# Lafferty1ab.net
KiCad netlist of a schematic drawn in EAGLE
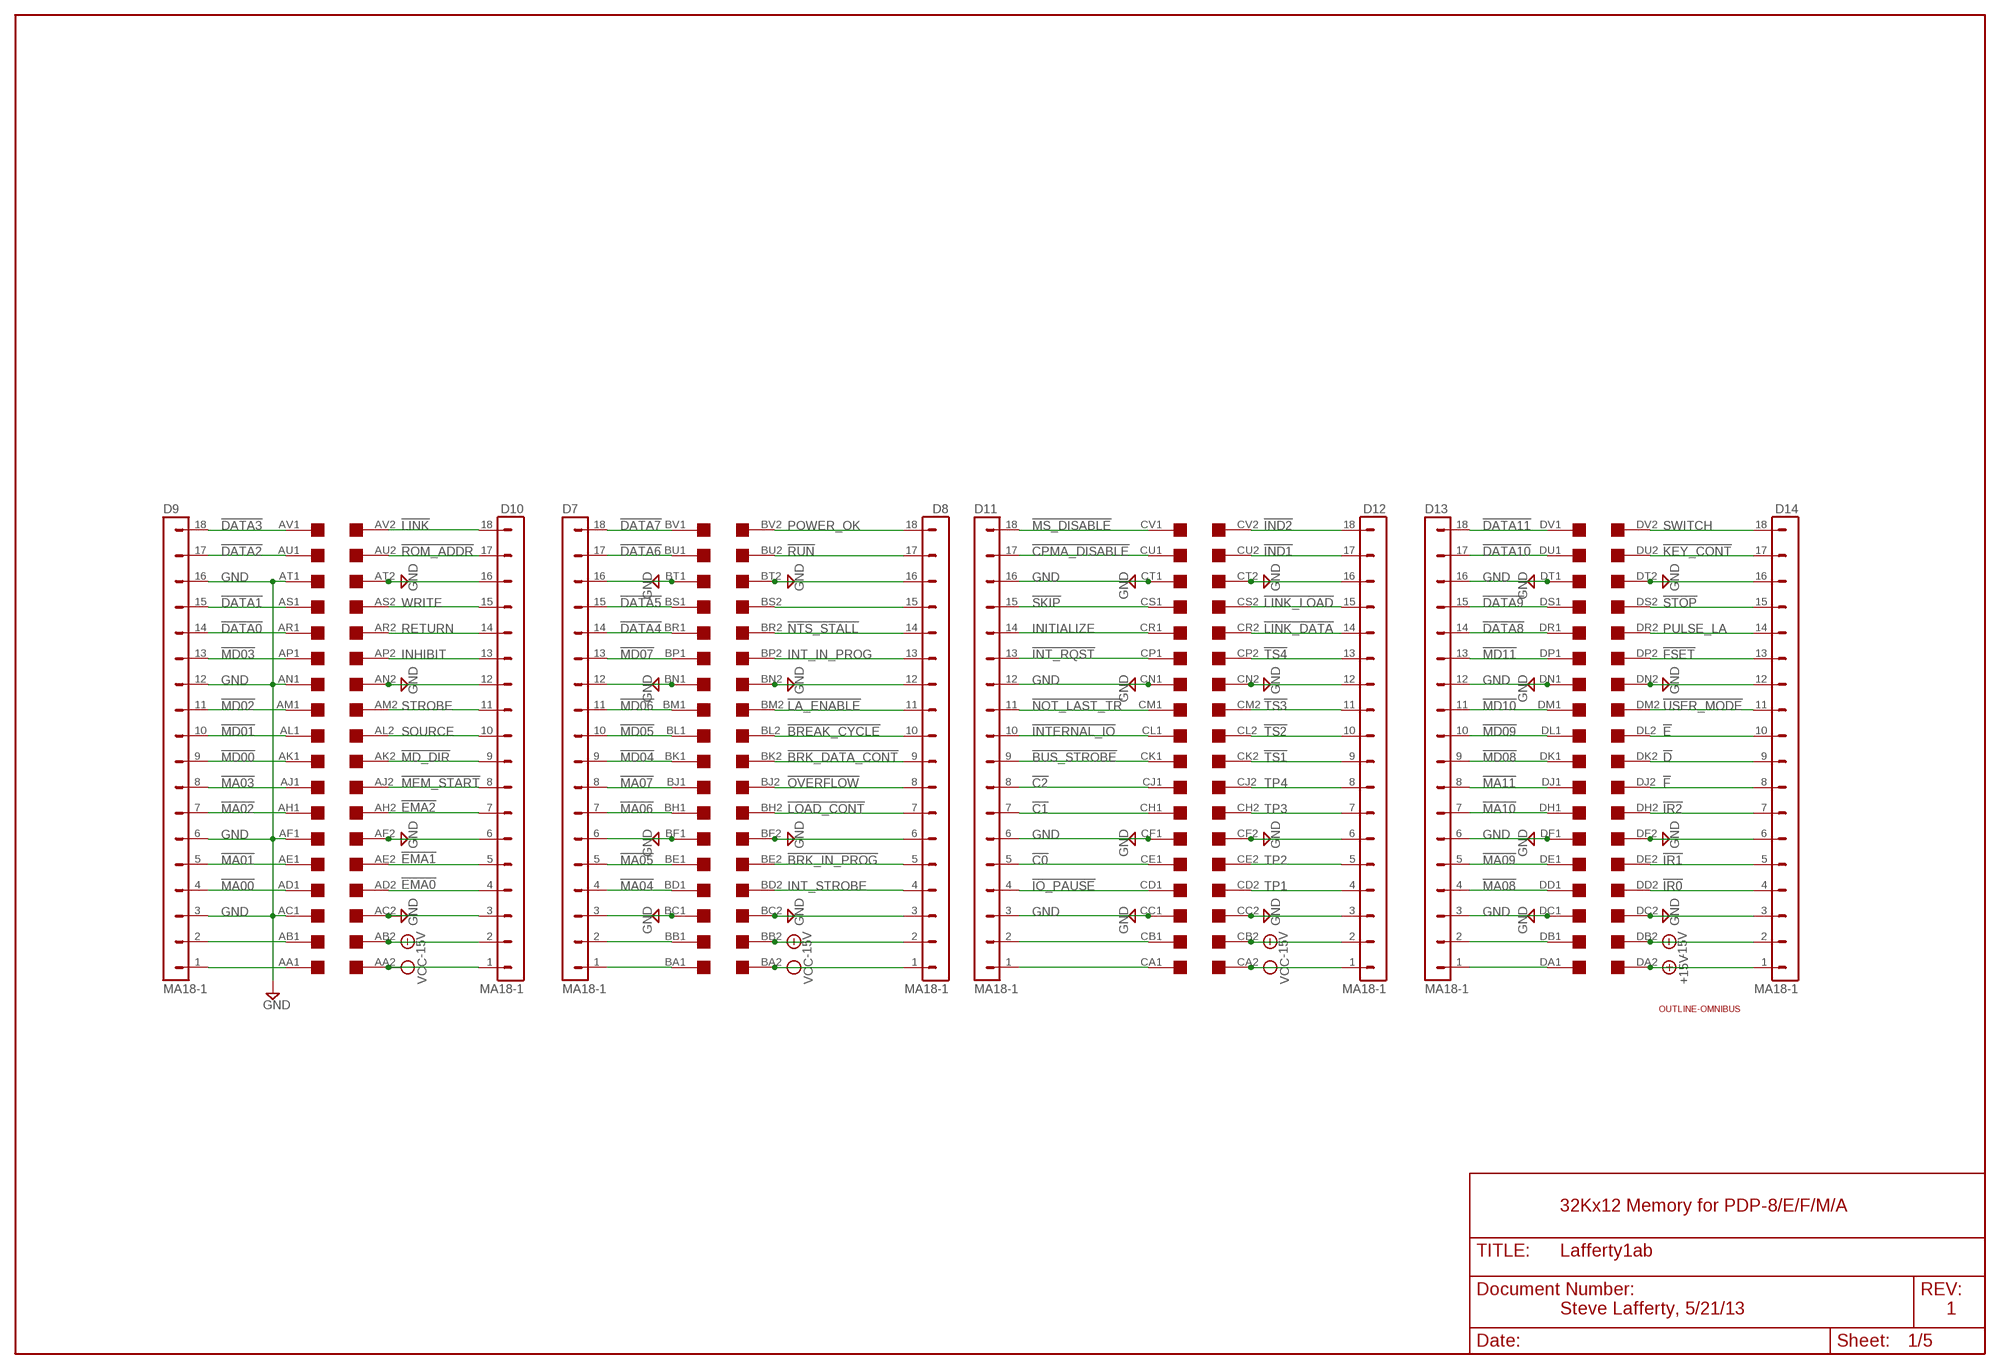
[diagram p0: schematic, sheet 1]
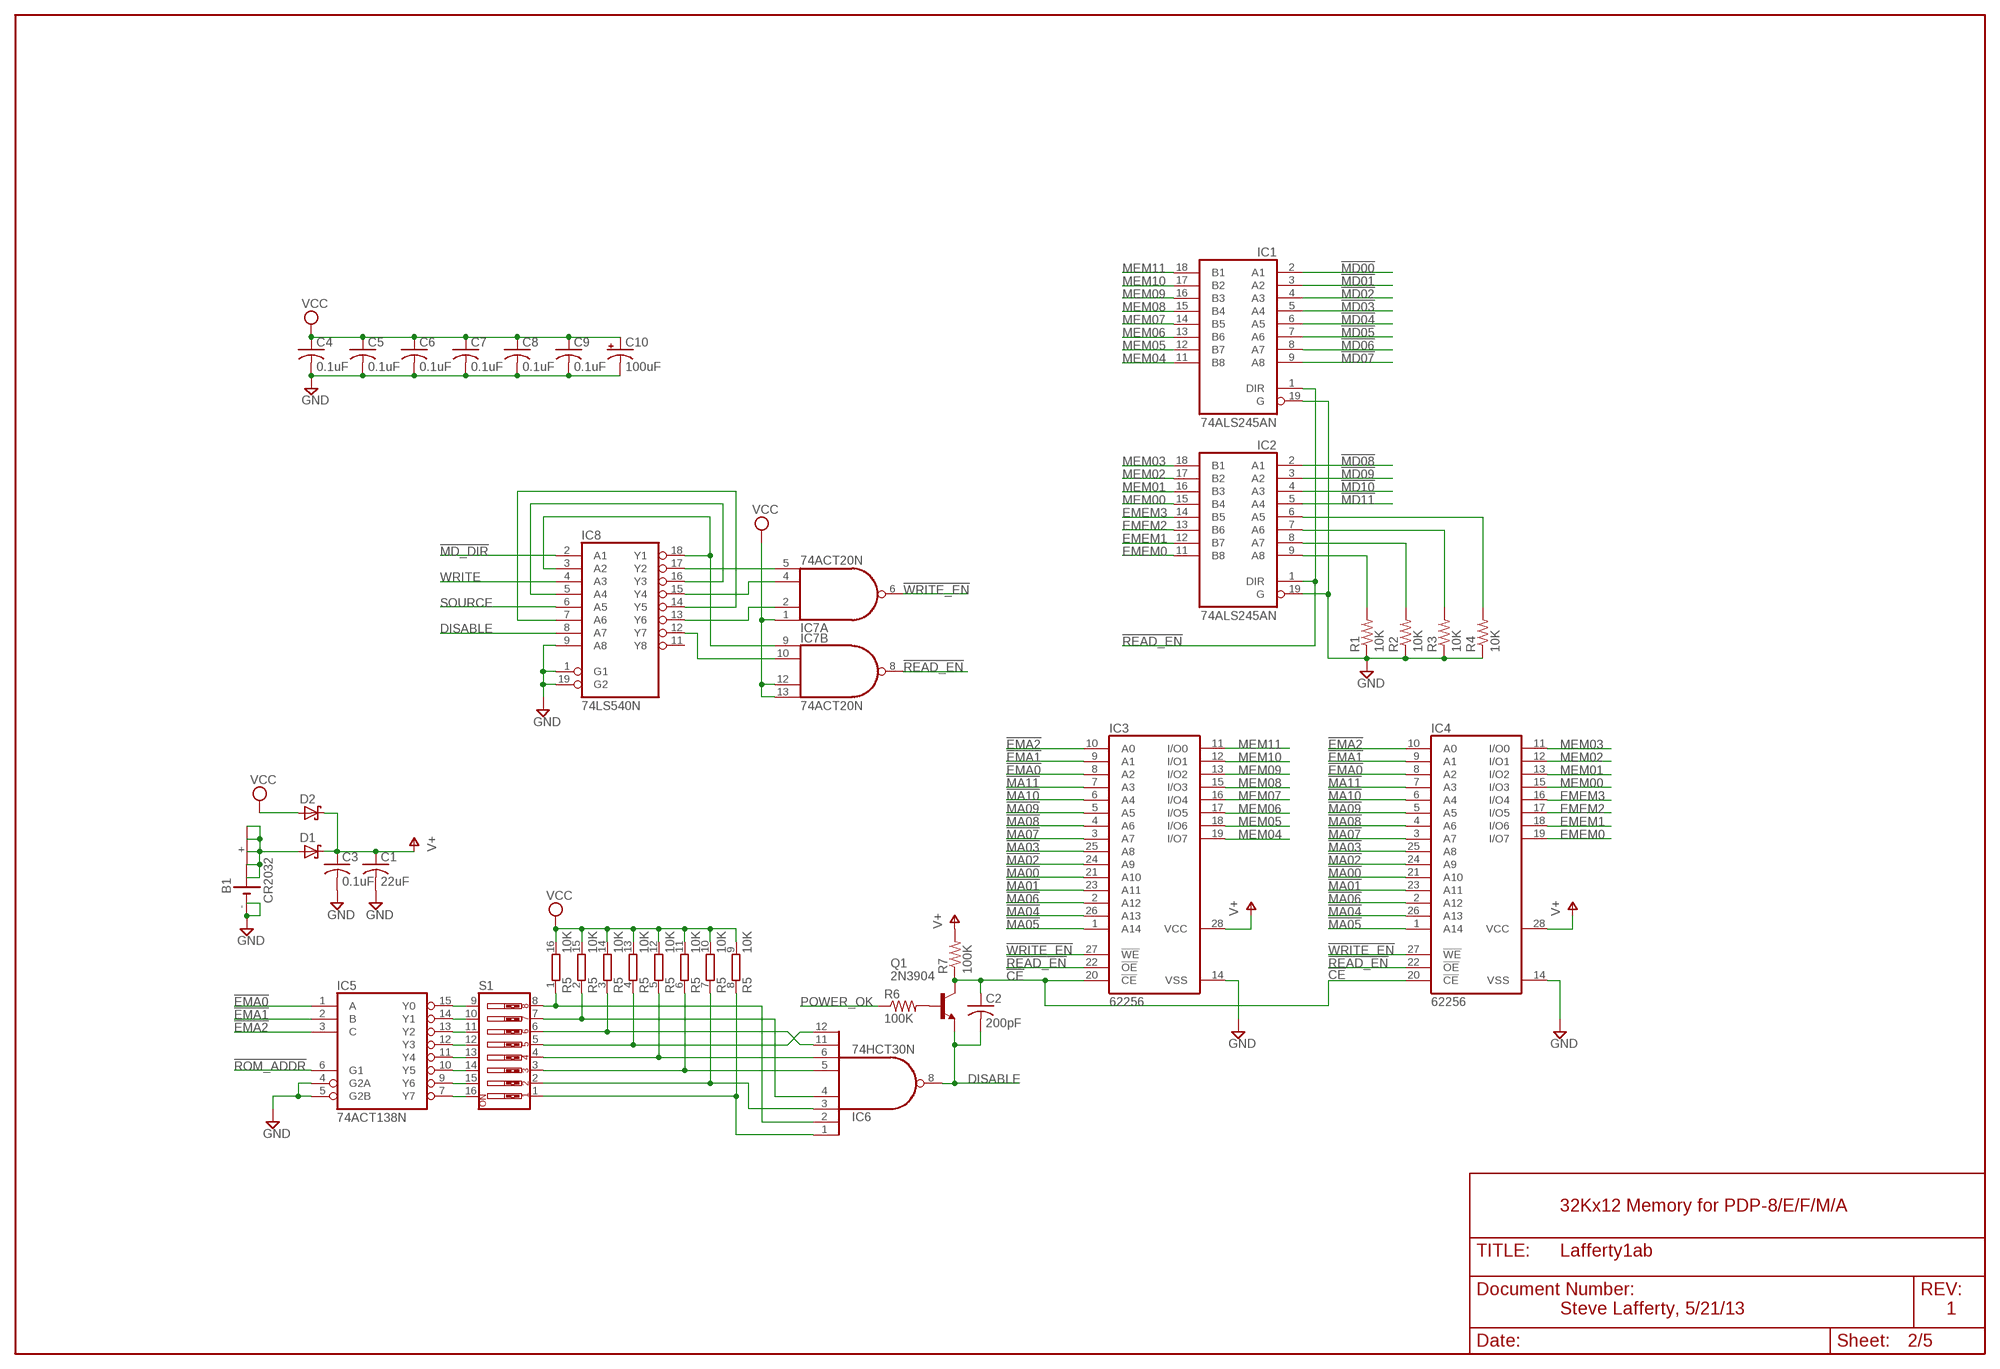
[diagram p1: schematic, sheet 2]
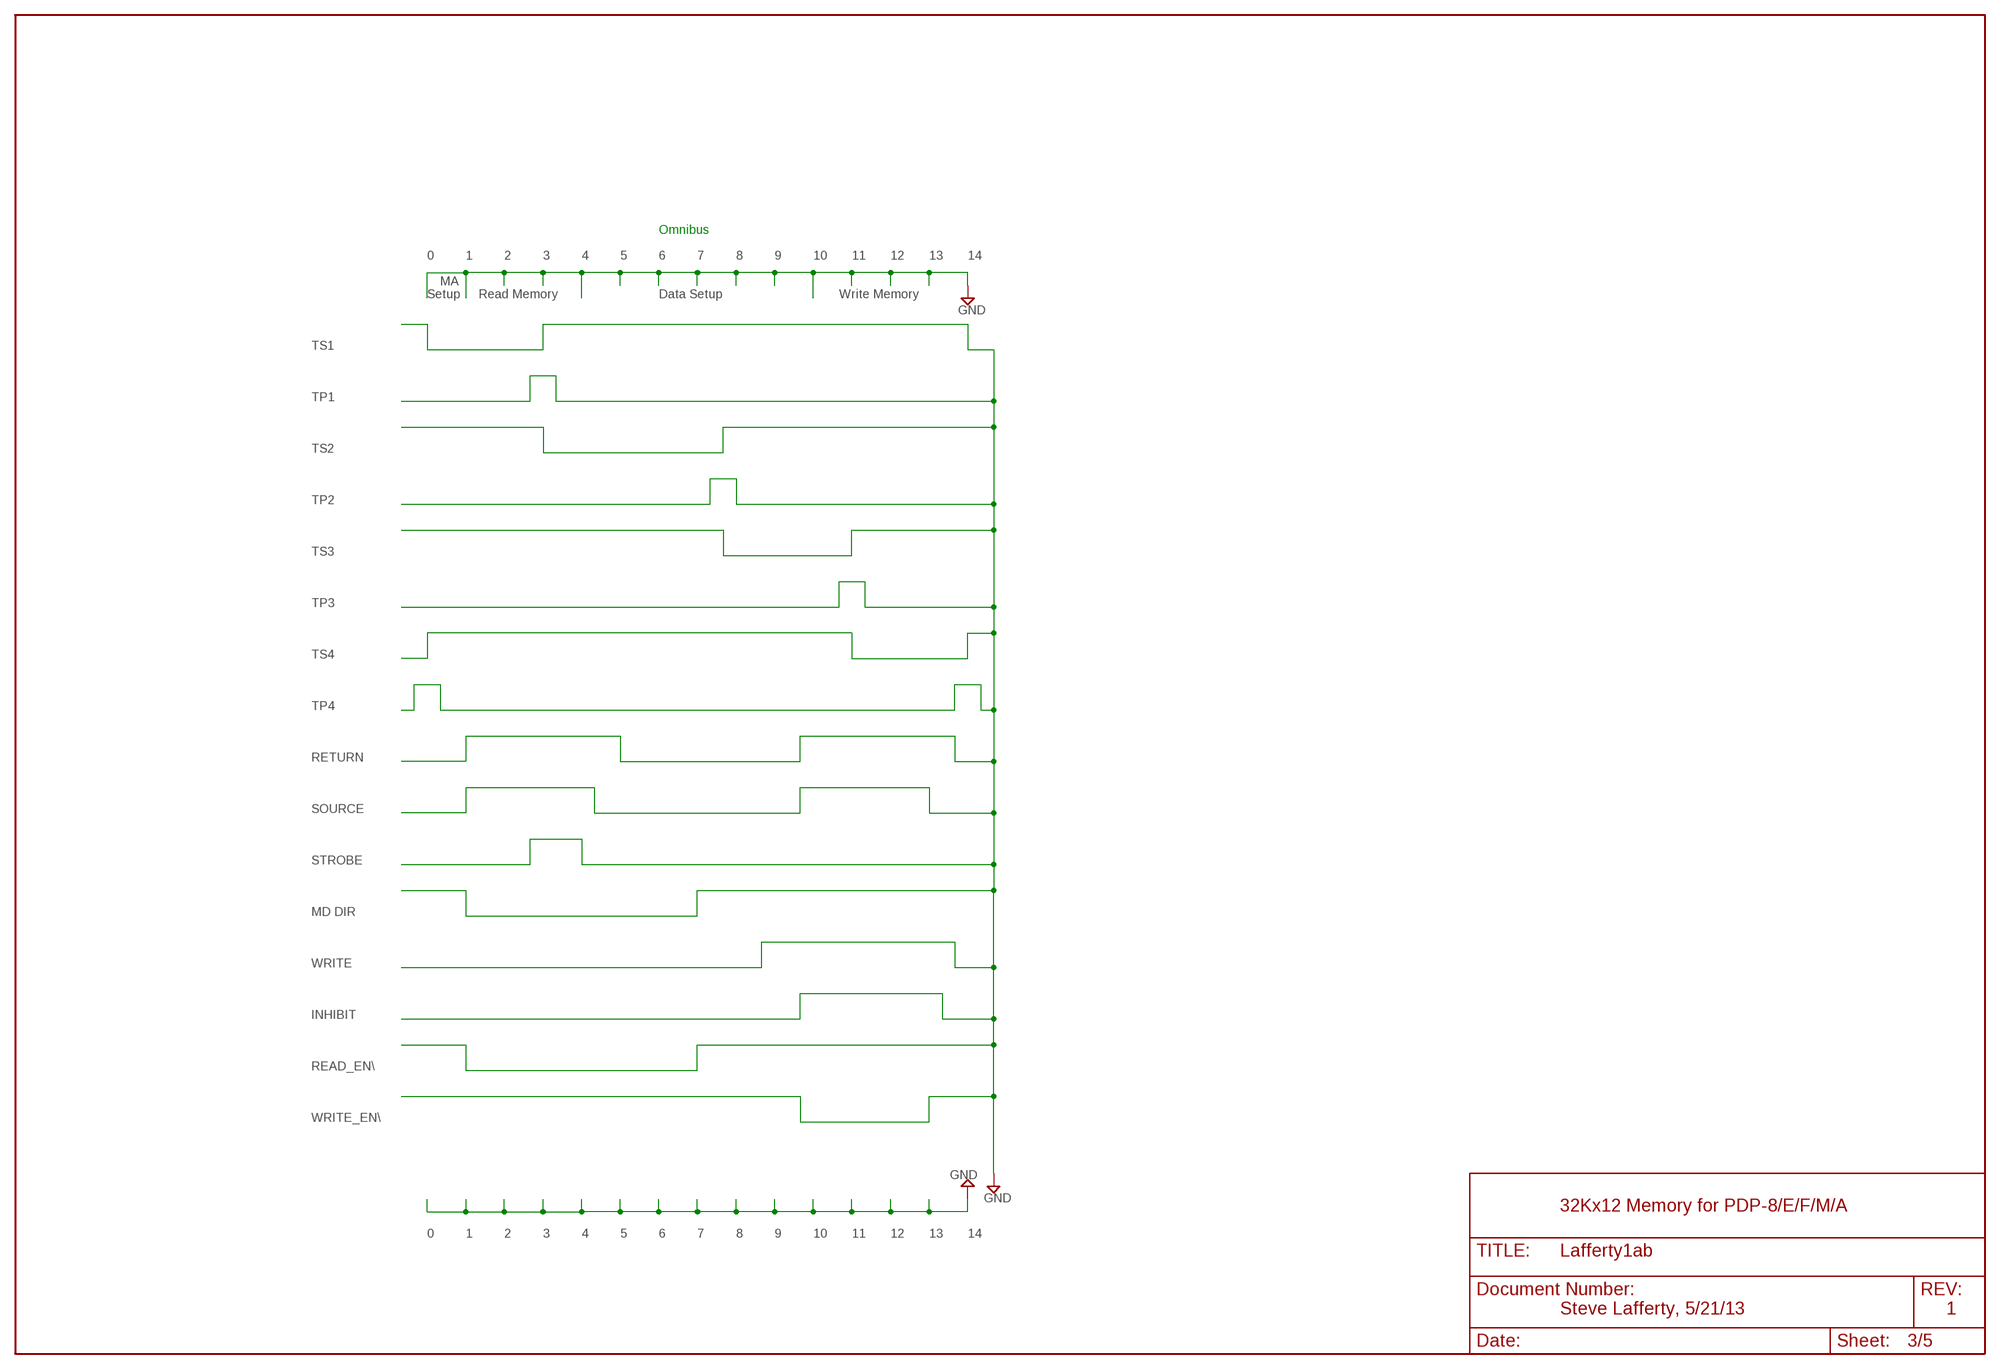
[diagram p2: schematic, sheet 3]
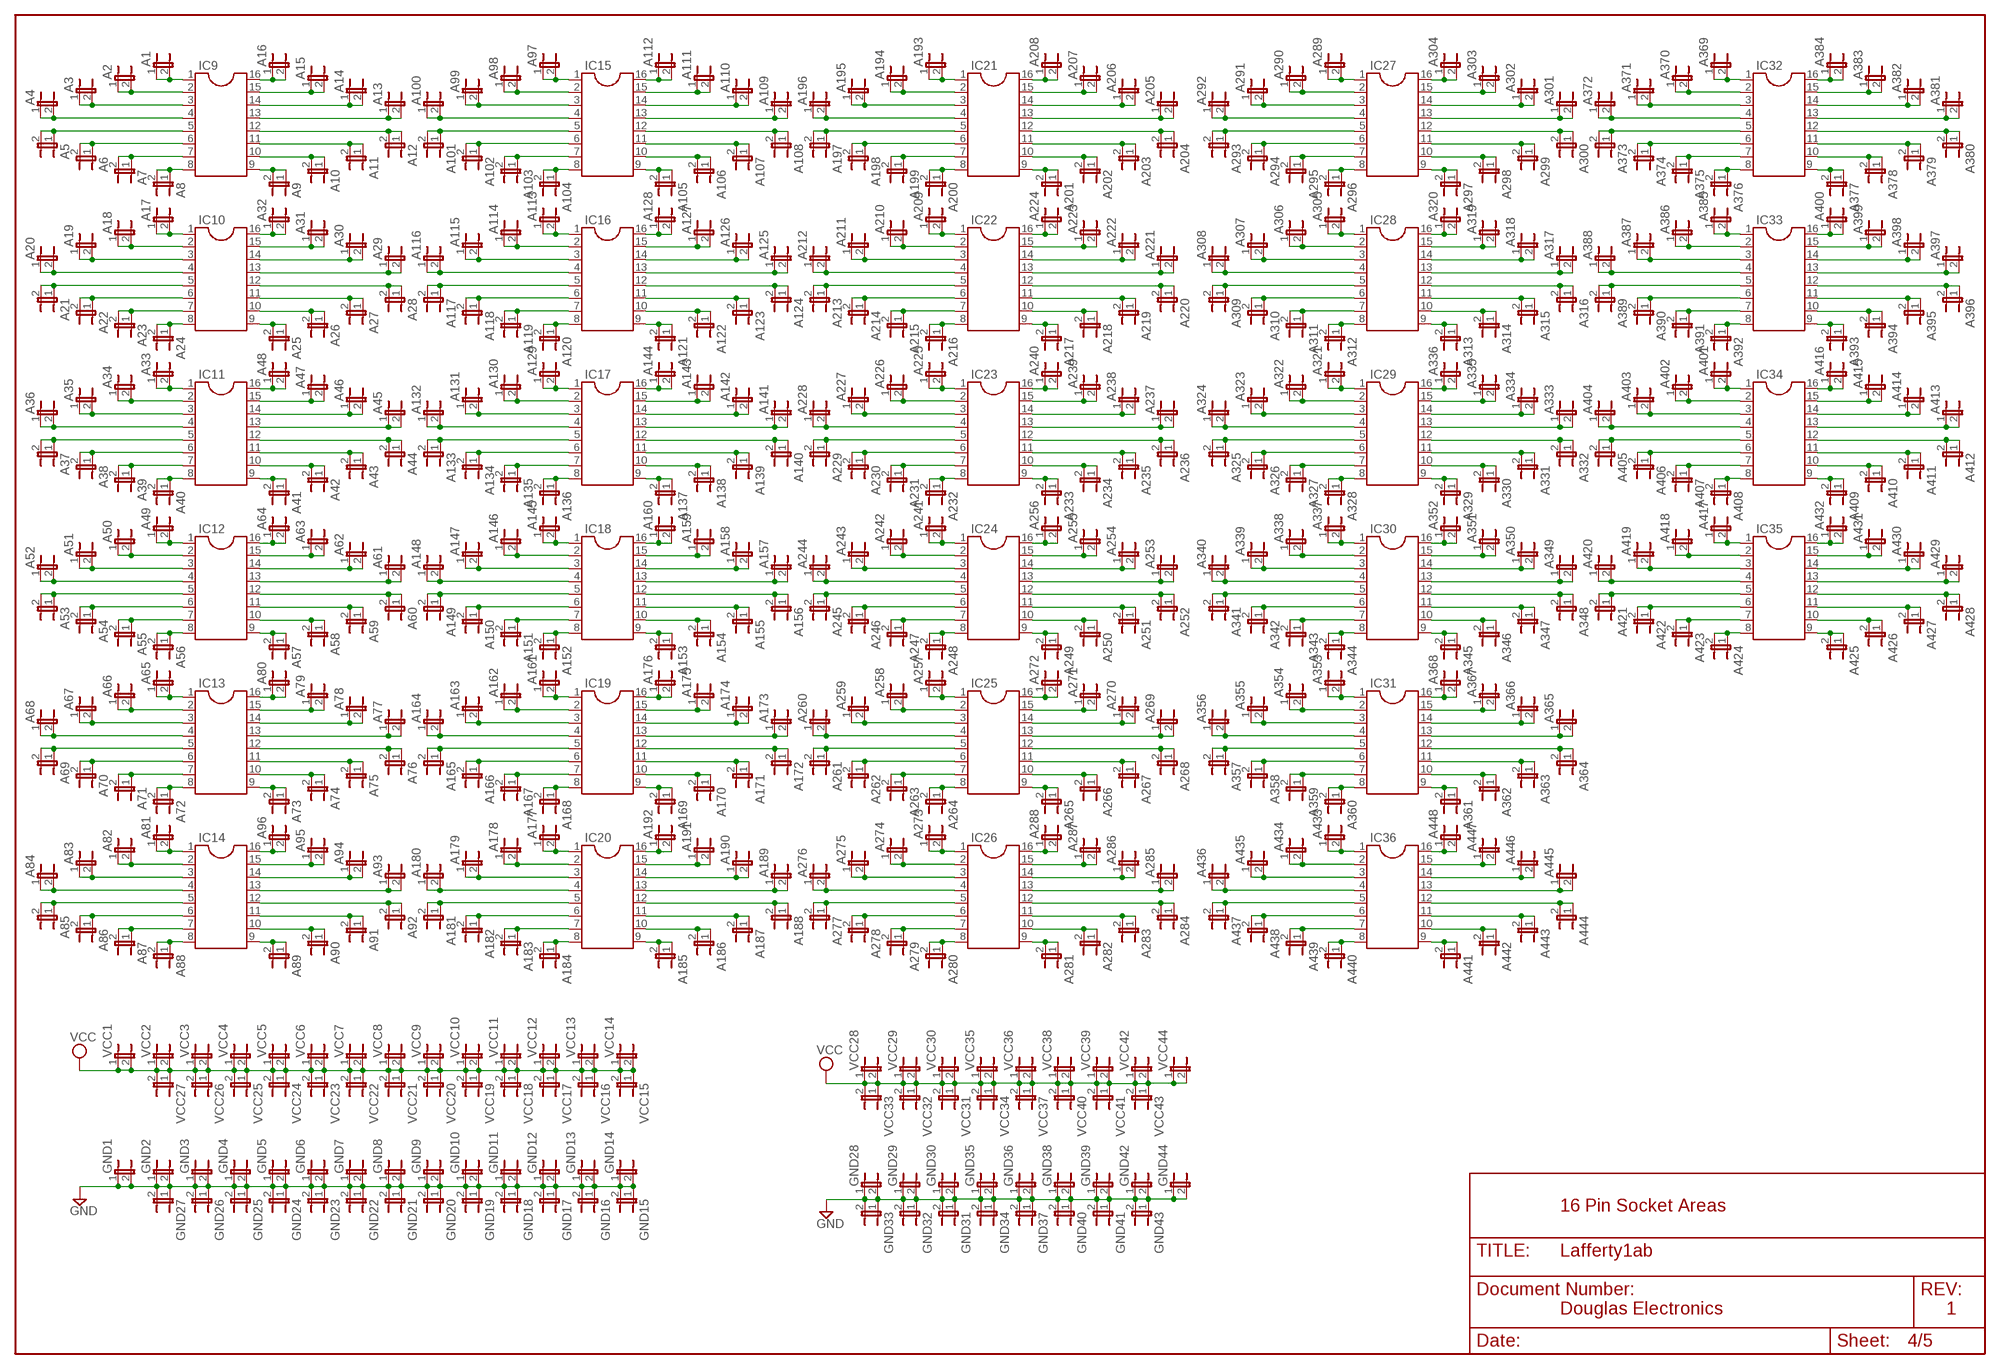
[diagram p3: schematic, sheet 4]
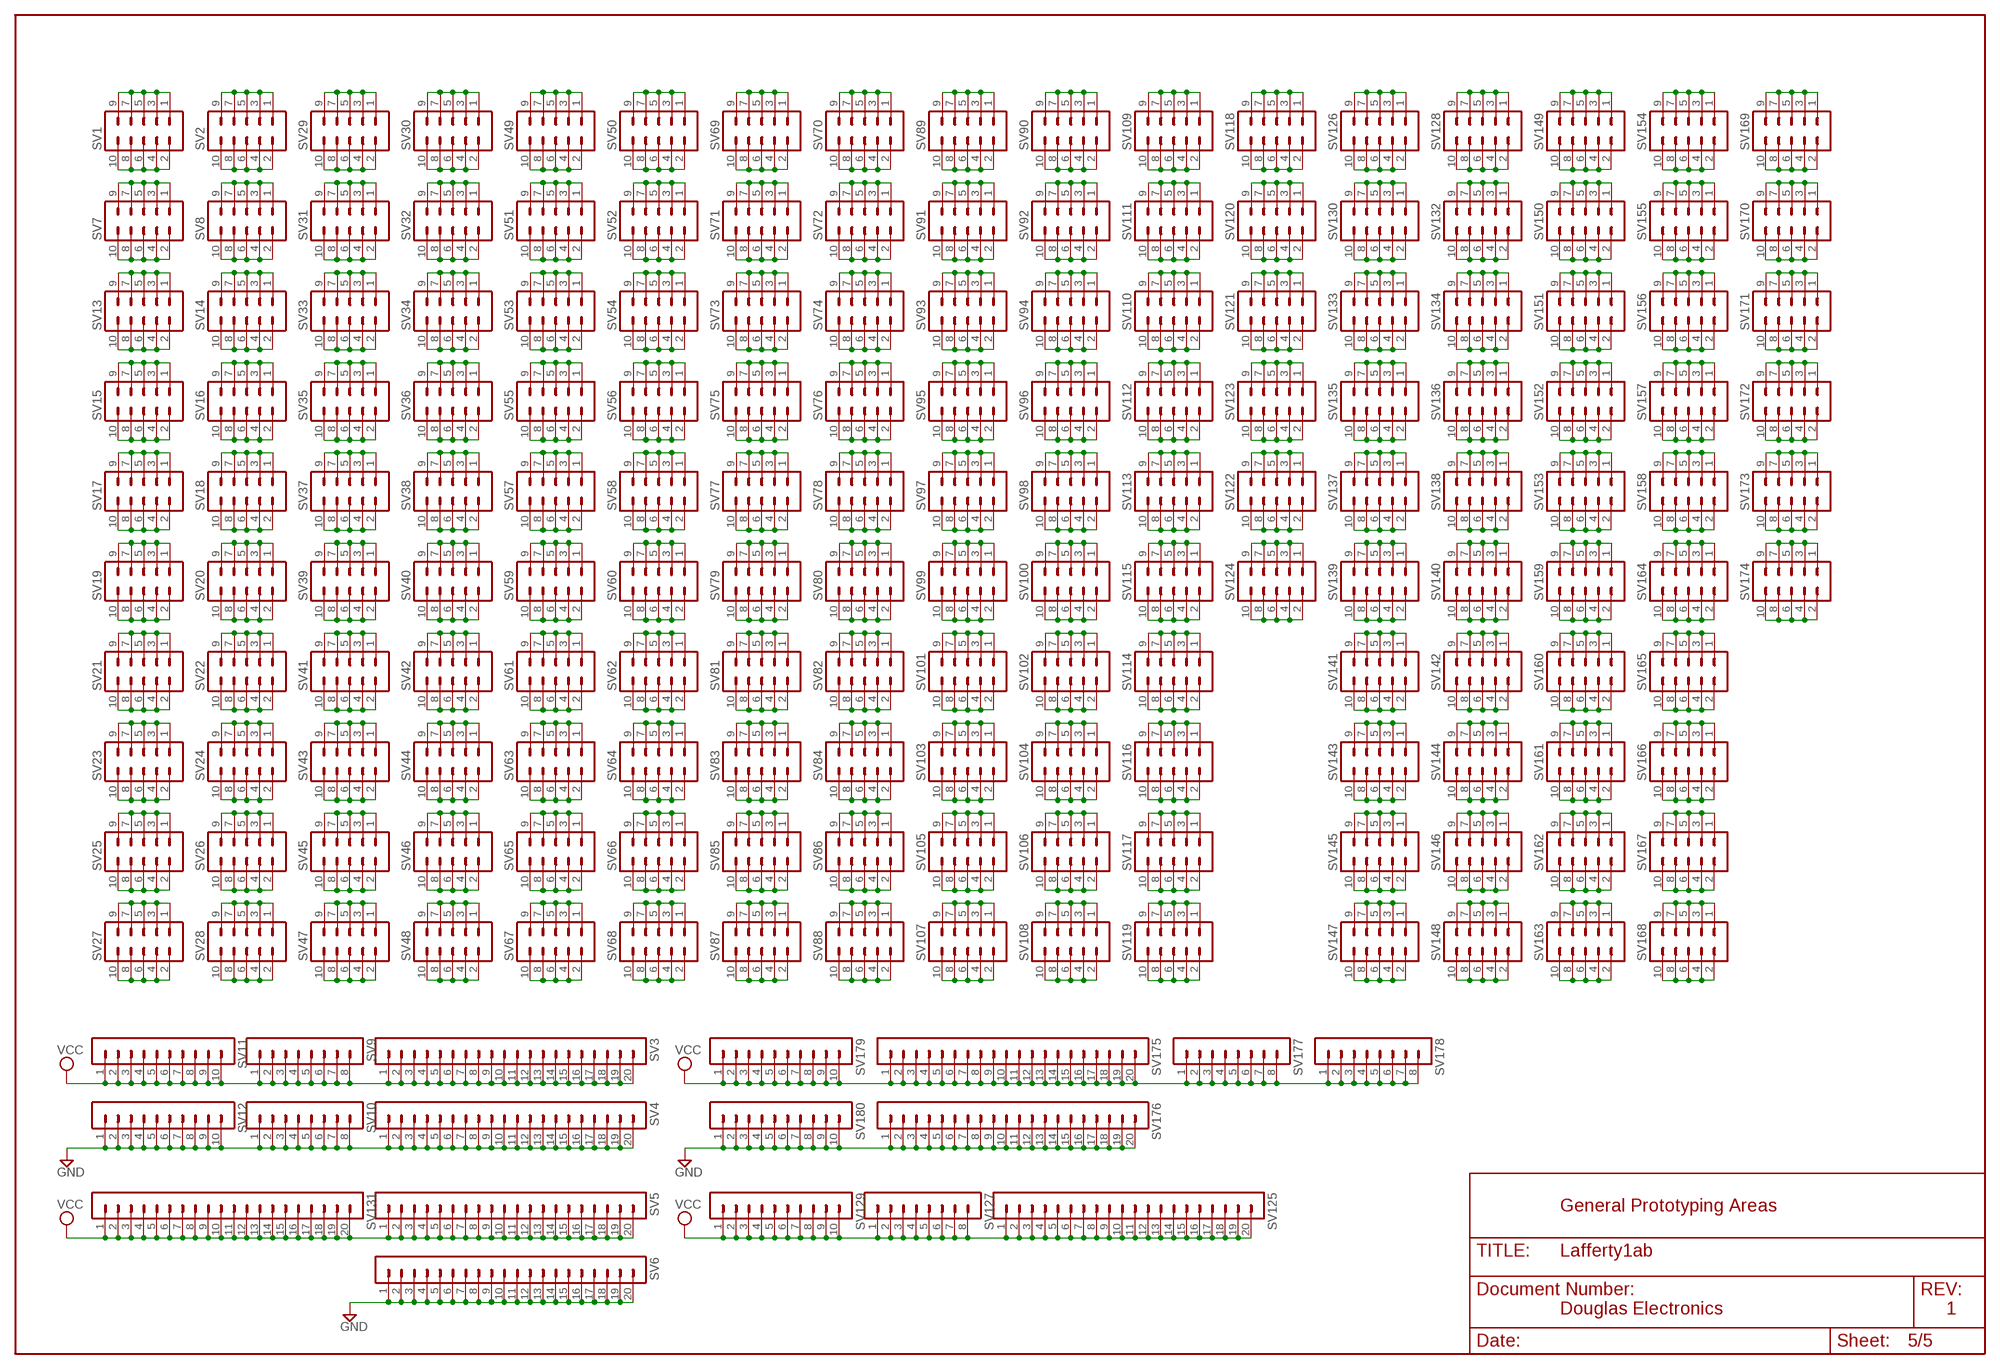
[diagram p4: schematic, sheet 5]

(export (version "E")
  (design (tool "Eeschema 10.0.6"))
  (components
    (comp (ref "D7")
      (value "MA18-1")
      (footprint "eagle-import:MA18-1")
      (libsource (lib "eagle-import") (part "MA18-1"))
    )
    (comp (ref "D8")
      (value "MA18-1")
      (footprint "eagle-import:MA18-1")
      (libsource (lib "eagle-import") (part "MA18-1"))
    )
    (comp (ref "D9")
      (value "MA18-1")
      (footprint "eagle-import:MA18-1")
      (libsource (lib "eagle-import") (part "MA18-1"))
    )
    (comp (ref "D10")
      (value "MA18-1")
      (footprint "eagle-import:MA18-1")
      (libsource (lib "eagle-import") (part "MA18-1"))
    )
    (comp (ref "D11")
      (value "MA18-1")
      (footprint "eagle-import:MA18-1")
      (libsource (lib "eagle-import") (part "MA18-1"))
    )
    (comp (ref "D12")
      (value "MA18-1")
      (footprint "eagle-import:MA18-1")
      (libsource (lib "eagle-import") (part "MA18-1"))
    )
    (comp (ref "D13")
      (value "MA18-1")
      (footprint "eagle-import:MA18-1")
      (libsource (lib "eagle-import") (part "MA18-1"))
    )
    (comp (ref "D14")
      (value "MA18-1")
      (footprint "eagle-import:MA18-1")
      (libsource (lib "eagle-import") (part "MA18-1"))
    )
    (comp (ref "U$1")
      (value "OUTLINE-OMNIBUS")
      (footprint "eagle-import:OMNIBUS")
      (libsource (lib "eagle-import") (part "OUTLINE-OMNIBUS"))
    )
    (comp (ref "U$2")
      (value "QUAD")
      (footprint "eagle-import:EDGE-CON8")
      (libsource (lib "eagle-import") (part "QUAD"))
    )
    (comp (ref "SV1")
      (value "MA05-2")
      (footprint "eagle-import:MA05-2")
      (libsource (lib "eagle-import") (part "MA05-2"))
    )
    (comp (ref "SV2")
      (value "MA05-2")
      (footprint "eagle-import:MA05-2")
      (libsource (lib "eagle-import") (part "MA05-2"))
    )
    (comp (ref "SV3")
      (value "MA20-1")
      (footprint "eagle-import:MA20-1")
      (libsource (lib "eagle-import") (part "MA20-1"))
    )
    (comp (ref "SV4")
      (value "MA20-1")
      (footprint "eagle-import:MA20-1")
      (libsource (lib "eagle-import") (part "MA20-1"))
    )
    (comp (ref "SV5")
      (value "MA20-1")
      (footprint "eagle-import:MA20-1")
      (libsource (lib "eagle-import") (part "MA20-1"))
    )
    (comp (ref "SV6")
      (value "MA20-1")
      (footprint "eagle-import:MA20-1")
      (libsource (lib "eagle-import") (part "MA20-1"))
    )
    (comp (ref "SV7")
      (value "MA05-2")
      (footprint "eagle-import:MA05-2")
      (libsource (lib "eagle-import") (part "MA05-2"))
    )
    (comp (ref "SV8")
      (value "MA05-2")
      (footprint "eagle-import:MA05-2")
      (libsource (lib "eagle-import") (part "MA05-2"))
    )
    (comp (ref "SV9")
      (value "MA08-1")
      (footprint "eagle-import:MA08-1")
      (libsource (lib "eagle-import") (part "MA08-1"))
    )
    (comp (ref "SV10")
      (value "MA08-1")
      (footprint "eagle-import:MA08-1")
      (libsource (lib "eagle-import") (part "MA08-1"))
    )
    (comp (ref "SV11")
      (value "MA10-1")
      (footprint "eagle-import:MA10-1")
      (libsource (lib "eagle-import") (part "MA10-1"))
    )
    (comp (ref "SV12")
      (value "MA10-1")
      (footprint "eagle-import:MA10-1")
      (libsource (lib "eagle-import") (part "MA10-1"))
    )
    (comp (ref "SV13")
      (value "MA05-2")
      (footprint "eagle-import:MA05-2")
      (libsource (lib "eagle-import") (part "MA05-2"))
    )
    (comp (ref "SV14")
      (value "MA05-2")
      (footprint "eagle-import:MA05-2")
      (libsource (lib "eagle-import") (part "MA05-2"))
    )
    (comp (ref "SV15")
      (value "MA05-2")
      (footprint "eagle-import:MA05-2")
      (libsource (lib "eagle-import") (part "MA05-2"))
    )
    (comp (ref "SV16")
      (value "MA05-2")
      (footprint "eagle-import:MA05-2")
      (libsource (lib "eagle-import") (part "MA05-2"))
    )
    (comp (ref "SV17")
      (value "MA05-2")
      (footprint "eagle-import:MA05-2")
      (libsource (lib "eagle-import") (part "MA05-2"))
    )
    (comp (ref "SV18")
      (value "MA05-2")
      (footprint "eagle-import:MA05-2")
      (libsource (lib "eagle-import") (part "MA05-2"))
    )
    (comp (ref "SV19")
      (value "MA05-2")
      (footprint "eagle-import:MA05-2")
      (libsource (lib "eagle-import") (part "MA05-2"))
    )
    (comp (ref "SV20")
      (value "MA05-2")
      (footprint "eagle-import:MA05-2")
      (libsource (lib "eagle-import") (part "MA05-2"))
    )
    (comp (ref "SV21")
      (value "MA05-2")
      (footprint "eagle-import:MA05-2")
      (libsource (lib "eagle-import") (part "MA05-2"))
    )
    (comp (ref "SV22")
      (value "MA05-2")
      (footprint "eagle-import:MA05-2")
      (libsource (lib "eagle-import") (part "MA05-2"))
    )
    (comp (ref "SV23")
      (value "MA05-2")
      (footprint "eagle-import:MA05-2")
      (libsource (lib "eagle-import") (part "MA05-2"))
    )
    (comp (ref "SV24")
      (value "MA05-2")
      (footprint "eagle-import:MA05-2")
      (libsource (lib "eagle-import") (part "MA05-2"))
    )
    (comp (ref "SV25")
      (value "MA05-2")
      (footprint "eagle-import:MA05-2")
      (libsource (lib "eagle-import") (part "MA05-2"))
    )
    (comp (ref "SV26")
      (value "MA05-2")
      (footprint "eagle-import:MA05-2")
      (libsource (lib "eagle-import") (part "MA05-2"))
    )
    (comp (ref "SV27")
      (value "MA05-2")
      (footprint "eagle-import:MA05-2")
      (libsource (lib "eagle-import") (part "MA05-2"))
    )
    (comp (ref "SV28")
      (value "MA05-2")
      (footprint "eagle-import:MA05-2")
      (libsource (lib "eagle-import") (part "MA05-2"))
    )
    (comp (ref "SV29")
      (value "MA05-2")
      (footprint "eagle-import:MA05-2")
      (libsource (lib "eagle-import") (part "MA05-2"))
    )
    (comp (ref "SV30")
      (value "MA05-2")
      (footprint "eagle-import:MA05-2")
      (libsource (lib "eagle-import") (part "MA05-2"))
    )
    (comp (ref "SV31")
      (value "MA05-2")
      (footprint "eagle-import:MA05-2")
      (libsource (lib "eagle-import") (part "MA05-2"))
    )
    (comp (ref "SV32")
      (value "MA05-2")
      (footprint "eagle-import:MA05-2")
      (libsource (lib "eagle-import") (part "MA05-2"))
    )
    (comp (ref "SV33")
      (value "MA05-2")
      (footprint "eagle-import:MA05-2")
      (libsource (lib "eagle-import") (part "MA05-2"))
    )
    (comp (ref "SV34")
      (value "MA05-2")
      (footprint "eagle-import:MA05-2")
      (libsource (lib "eagle-import") (part "MA05-2"))
    )
    (comp (ref "SV35")
      (value "MA05-2")
      (footprint "eagle-import:MA05-2")
      (libsource (lib "eagle-import") (part "MA05-2"))
    )
    (comp (ref "SV36")
      (value "MA05-2")
      (footprint "eagle-import:MA05-2")
      (libsource (lib "eagle-import") (part "MA05-2"))
    )
    (comp (ref "SV37")
      (value "MA05-2")
      (footprint "eagle-import:MA05-2")
      (libsource (lib "eagle-import") (part "MA05-2"))
    )
    (comp (ref "SV38")
      (value "MA05-2")
      (footprint "eagle-import:MA05-2")
      (libsource (lib "eagle-import") (part "MA05-2"))
    )
    (comp (ref "SV39")
      (value "MA05-2")
      (footprint "eagle-import:MA05-2")
      (libsource (lib "eagle-import") (part "MA05-2"))
    )
    (comp (ref "SV40")
      (value "MA05-2")
      (footprint "eagle-import:MA05-2")
      (libsource (lib "eagle-import") (part "MA05-2"))
    )
    (comp (ref "SV41")
      (value "MA05-2")
      (footprint "eagle-import:MA05-2")
      (libsource (lib "eagle-import") (part "MA05-2"))
    )
    (comp (ref "SV42")
      (value "MA05-2")
      (footprint "eagle-import:MA05-2")
      (libsource (lib "eagle-import") (part "MA05-2"))
    )
    (comp (ref "SV43")
      (value "MA05-2")
      (footprint "eagle-import:MA05-2")
      (libsource (lib "eagle-import") (part "MA05-2"))
    )
    (comp (ref "SV44")
      (value "MA05-2")
      (footprint "eagle-import:MA05-2")
      (libsource (lib "eagle-import") (part "MA05-2"))
    )
    (comp (ref "SV45")
      (value "MA05-2")
      (footprint "eagle-import:MA05-2")
      (libsource (lib "eagle-import") (part "MA05-2"))
    )
    (comp (ref "SV46")
      (value "MA05-2")
      (footprint "eagle-import:MA05-2")
      (libsource (lib "eagle-import") (part "MA05-2"))
    )
    (comp (ref "SV47")
      (value "MA05-2")
      (footprint "eagle-import:MA05-2")
      (libsource (lib "eagle-import") (part "MA05-2"))
    )
    (comp (ref "SV48")
      (value "MA05-2")
      (footprint "eagle-import:MA05-2")
      (libsource (lib "eagle-import") (part "MA05-2"))
    )
    (comp (ref "SV49")
      (value "MA05-2")
      (footprint "eagle-import:MA05-2")
      (libsource (lib "eagle-import") (part "MA05-2"))
    )
    (comp (ref "SV50")
      (value "MA05-2")
      (footprint "eagle-import:MA05-2")
      (libsource (lib "eagle-import") (part "MA05-2"))
    )
    (comp (ref "SV51")
      (value "MA05-2")
      (footprint "eagle-import:MA05-2")
      (libsource (lib "eagle-import") (part "MA05-2"))
    )
    (comp (ref "SV52")
      (value "MA05-2")
      (footprint "eagle-import:MA05-2")
      (libsource (lib "eagle-import") (part "MA05-2"))
    )
    (comp (ref "SV53")
      (value "MA05-2")
      (footprint "eagle-import:MA05-2")
      (libsource (lib "eagle-import") (part "MA05-2"))
    )
    (comp (ref "SV54")
      (value "MA05-2")
      (footprint "eagle-import:MA05-2")
      (libsource (lib "eagle-import") (part "MA05-2"))
    )
    (comp (ref "SV55")
      (value "MA05-2")
      (footprint "eagle-import:MA05-2")
      (libsource (lib "eagle-import") (part "MA05-2"))
    )
    (comp (ref "SV56")
      (value "MA05-2")
      (footprint "eagle-import:MA05-2")
      (libsource (lib "eagle-import") (part "MA05-2"))
    )
    (comp (ref "SV57")
      (value "MA05-2")
      (footprint "eagle-import:MA05-2")
      (libsource (lib "eagle-import") (part "MA05-2"))
    )
    (comp (ref "SV58")
      (value "MA05-2")
      (footprint "eagle-import:MA05-2")
      (libsource (lib "eagle-import") (part "MA05-2"))
    )
    (comp (ref "SV59")
      (value "MA05-2")
      (footprint "eagle-import:MA05-2")
      (libsource (lib "eagle-import") (part "MA05-2"))
    )
    (comp (ref "SV60")
      (value "MA05-2")
      (footprint "eagle-import:MA05-2")
      (libsource (lib "eagle-import") (part "MA05-2"))
    )
    (comp (ref "SV61")
      (value "MA05-2")
      (footprint "eagle-import:MA05-2")
      (libsource (lib "eagle-import") (part "MA05-2"))
    )
    (comp (ref "SV62")
      (value "MA05-2")
      (footprint "eagle-import:MA05-2")
      (libsource (lib "eagle-import") (part "MA05-2"))
    )
    (comp (ref "SV63")
      (value "MA05-2")
      (footprint "eagle-import:MA05-2")
      (libsource (lib "eagle-import") (part "MA05-2"))
    )
    (comp (ref "SV64")
      (value "MA05-2")
      (footprint "eagle-import:MA05-2")
      (libsource (lib "eagle-import") (part "MA05-2"))
    )
    (comp (ref "SV65")
      (value "MA05-2")
      (footprint "eagle-import:MA05-2")
      (libsource (lib "eagle-import") (part "MA05-2"))
    )
    (comp (ref "SV66")
      (value "MA05-2")
      (footprint "eagle-import:MA05-2")
      (libsource (lib "eagle-import") (part "MA05-2"))
    )
    (comp (ref "SV67")
      (value "MA05-2")
      (footprint "eagle-import:MA05-2")
      (libsource (lib "eagle-import") (part "MA05-2"))
    )
    (comp (ref "SV68")
      (value "MA05-2")
      (footprint "eagle-import:MA05-2")
      (libsource (lib "eagle-import") (part "MA05-2"))
    )
    (comp (ref "SV69")
      (value "MA05-2")
      (footprint "eagle-import:MA05-2")
      (libsource (lib "eagle-import") (part "MA05-2"))
    )
    (comp (ref "SV70")
      (value "MA05-2")
      (footprint "eagle-import:MA05-2")
      (libsource (lib "eagle-import") (part "MA05-2"))
    )
    (comp (ref "SV71")
      (value "MA05-2")
      (footprint "eagle-import:MA05-2")
      (libsource (lib "eagle-import") (part "MA05-2"))
    )
    (comp (ref "SV72")
      (value "MA05-2")
      (footprint "eagle-import:MA05-2")
      (libsource (lib "eagle-import") (part "MA05-2"))
    )
    (comp (ref "SV73")
      (value "MA05-2")
      (footprint "eagle-import:MA05-2")
      (libsource (lib "eagle-import") (part "MA05-2"))
    )
    (comp (ref "SV74")
      (value "MA05-2")
      (footprint "eagle-import:MA05-2")
      (libsource (lib "eagle-import") (part "MA05-2"))
    )
    (comp (ref "SV75")
      (value "MA05-2")
      (footprint "eagle-import:MA05-2")
      (libsource (lib "eagle-import") (part "MA05-2"))
    )
    (comp (ref "SV76")
      (value "MA05-2")
      (footprint "eagle-import:MA05-2")
      (libsource (lib "eagle-import") (part "MA05-2"))
    )
    (comp (ref "SV77")
      (value "MA05-2")
      (footprint "eagle-import:MA05-2")
      (libsource (lib "eagle-import") (part "MA05-2"))
    )
    (comp (ref "SV78")
      (value "MA05-2")
      (footprint "eagle-import:MA05-2")
      (libsource (lib "eagle-import") (part "MA05-2"))
    )
    (comp (ref "SV79")
      (value "MA05-2")
      (footprint "eagle-import:MA05-2")
      (libsource (lib "eagle-import") (part "MA05-2"))
    )
    (comp (ref "SV80")
      (value "MA05-2")
      (footprint "eagle-import:MA05-2")
      (libsource (lib "eagle-import") (part "MA05-2"))
    )
    (comp (ref "SV81")
      (value "MA05-2")
      (footprint "eagle-import:MA05-2")
      (libsource (lib "eagle-import") (part "MA05-2"))
    )
    (comp (ref "SV82")
      (value "MA05-2")
      (footprint "eagle-import:MA05-2")
      (libsource (lib "eagle-import") (part "MA05-2"))
    )
    (comp (ref "SV83")
      (value "MA05-2")
      (footprint "eagle-import:MA05-2")
      (libsource (lib "eagle-import") (part "MA05-2"))
    )
    (comp (ref "SV84")
      (value "MA05-2")
      (footprint "eagle-import:MA05-2")
      (libsource (lib "eagle-import") (part "MA05-2"))
    )
    (comp (ref "SV85")
      (value "MA05-2")
      (footprint "eagle-import:MA05-2")
      (libsource (lib "eagle-import") (part "MA05-2"))
    )
    (comp (ref "SV86")
      (value "MA05-2")
      (footprint "eagle-import:MA05-2")
      (libsource (lib "eagle-import") (part "MA05-2"))
    )
    (comp (ref "SV87")
      (value "MA05-2")
      (footprint "eagle-import:MA05-2")
      (libsource (lib "eagle-import") (part "MA05-2"))
    )
    (comp (ref "SV88")
      (value "MA05-2")
      (footprint "eagle-import:MA05-2")
      (libsource (lib "eagle-import") (part "MA05-2"))
    )
    (comp (ref "SV89")
      (value "MA05-2")
      (footprint "eagle-import:MA05-2")
      (libsource (lib "eagle-import") (part "MA05-2"))
    )
    (comp (ref "SV90")
      (value "MA05-2")
      (footprint "eagle-import:MA05-2")
      (libsource (lib "eagle-import") (part "MA05-2"))
    )
    (comp (ref "SV91")
      (value "MA05-2")
      (footprint "eagle-import:MA05-2")
      (libsource (lib "eagle-import") (part "MA05-2"))
    )
    (comp (ref "SV92")
      (value "MA05-2")
      (footprint "eagle-import:MA05-2")
      (libsource (lib "eagle-import") (part "MA05-2"))
    )
    (comp (ref "SV93")
      (value "MA05-2")
      (footprint "eagle-import:MA05-2")
      (libsource (lib "eagle-import") (part "MA05-2"))
    )
    (comp (ref "SV94")
      (value "MA05-2")
      (footprint "eagle-import:MA05-2")
      (libsource (lib "eagle-import") (part "MA05-2"))
    )
    (comp (ref "SV95")
      (value "MA05-2")
      (footprint "eagle-import:MA05-2")
      (libsource (lib "eagle-import") (part "MA05-2"))
    )
    (comp (ref "SV96")
      (value "MA05-2")
      (footprint "eagle-import:MA05-2")
      (libsource (lib "eagle-import") (part "MA05-2"))
    )
    (comp (ref "SV97")
      (value "MA05-2")
      (footprint "eagle-import:MA05-2")
      (libsource (lib "eagle-import") (part "MA05-2"))
    )
    (comp (ref "SV98")
      (value "MA05-2")
      (footprint "eagle-import:MA05-2")
      (libsource (lib "eagle-import") (part "MA05-2"))
    )
    (comp (ref "SV99")
      (value "MA05-2")
      (footprint "eagle-import:MA05-2")
      (libsource (lib "eagle-import") (part "MA05-2"))
    )
    (comp (ref "SV100")
      (value "MA05-2")
      (footprint "eagle-import:MA05-2")
      (libsource (lib "eagle-import") (part "MA05-2"))
    )
    (comp (ref "SV101")
      (value "MA05-2")
      (footprint "eagle-import:MA05-2")
      (libsource (lib "eagle-import") (part "MA05-2"))
    )
    (comp (ref "SV102")
      (value "MA05-2")
      (footprint "eagle-import:MA05-2")
      (libsource (lib "eagle-import") (part "MA05-2"))
    )
    (comp (ref "SV103")
      (value "MA05-2")
      (footprint "eagle-import:MA05-2")
      (libsource (lib "eagle-import") (part "MA05-2"))
    )
    (comp (ref "SV104")
      (value "MA05-2")
      (footprint "eagle-import:MA05-2")
      (libsource (lib "eagle-import") (part "MA05-2"))
    )
    (comp (ref "SV105")
      (value "MA05-2")
      (footprint "eagle-import:MA05-2")
      (libsource (lib "eagle-import") (part "MA05-2"))
    )
    (comp (ref "SV106")
      (value "MA05-2")
      (footprint "eagle-import:MA05-2")
      (libsource (lib "eagle-import") (part "MA05-2"))
    )
    (comp (ref "SV107")
      (value "MA05-2")
      (footprint "eagle-import:MA05-2")
      (libsource (lib "eagle-import") (part "MA05-2"))
    )
    (comp (ref "SV108")
      (value "MA05-2")
      (footprint "eagle-import:MA05-2")
      (libsource (lib "eagle-import") (part "MA05-2"))
    )
    (comp (ref "SV109")
      (value "MA05-2")
      (footprint "eagle-import:MA05-2")
      (libsource (lib "eagle-import") (part "MA05-2"))
    )
    (comp (ref "SV110")
      (value "MA05-2")
      (footprint "eagle-import:MA05-2")
      (libsource (lib "eagle-import") (part "MA05-2"))
    )
    (comp (ref "SV111")
      (value "MA05-2")
      (footprint "eagle-import:MA05-2")
      (libsource (lib "eagle-import") (part "MA05-2"))
    )
    (comp (ref "SV112")
      (value "MA05-2")
      (footprint "eagle-import:MA05-2")
      (libsource (lib "eagle-import") (part "MA05-2"))
    )
    (comp (ref "SV113")
      (value "MA05-2")
      (footprint "eagle-import:MA05-2")
      (libsource (lib "eagle-import") (part "MA05-2"))
    )
    (comp (ref "SV114")
      (value "MA05-2")
      (footprint "eagle-import:MA05-2")
      (libsource (lib "eagle-import") (part "MA05-2"))
    )
    (comp (ref "SV115")
      (value "MA05-2")
      (footprint "eagle-import:MA05-2")
      (libsource (lib "eagle-import") (part "MA05-2"))
    )
    (comp (ref "SV116")
      (value "MA05-2")
      (footprint "eagle-import:MA05-2")
      (libsource (lib "eagle-import") (part "MA05-2"))
    )
    (comp (ref "SV117")
      (value "MA05-2")
      (footprint "eagle-import:MA05-2")
      (libsource (lib "eagle-import") (part "MA05-2"))
    )
    (comp (ref "SV118")
      (value "MA05-2")
      (footprint "eagle-import:MA05-2")
      (libsource (lib "eagle-import") (part "MA05-2"))
    )
    (comp (ref "SV119")
      (value "MA05-2")
      (footprint "eagle-import:MA05-2")
      (libsource (lib "eagle-import") (part "MA05-2"))
    )
    (comp (ref "SV120")
      (value "MA05-2")
      (footprint "eagle-import:MA05-2")
      (libsource (lib "eagle-import") (part "MA05-2"))
    )
    (comp (ref "SV121")
      (value "MA05-2")
      (footprint "eagle-import:MA05-2")
      (libsource (lib "eagle-import") (part "MA05-2"))
    )
    (comp (ref "SV122")
      (value "MA05-2")
      (footprint "eagle-import:MA05-2")
      (libsource (lib "eagle-import") (part "MA05-2"))
    )
    (comp (ref "SV123")
      (value "MA05-2")
      (footprint "eagle-import:MA05-2")
      (libsource (lib "eagle-import") (part "MA05-2"))
    )
    (comp (ref "SV124")
      (value "MA05-2")
      (footprint "eagle-import:MA05-2")
      (libsource (lib "eagle-import") (part "MA05-2"))
    )
    (comp (ref "SV125")
      (value "MA20-1")
      (footprint "eagle-import:MA20-1")
      (libsource (lib "eagle-import") (part "MA20-1"))
    )
    (comp (ref "SV126")
      (value "MA05-2")
      (footprint "eagle-import:MA05-2")
      (libsource (lib "eagle-import") (part "MA05-2"))
    )
    (comp (ref "SV127")
      (value "MA08-1")
      (footprint "eagle-import:MA08-1")
      (libsource (lib "eagle-import") (part "MA08-1"))
    )
    (comp (ref "SV128")
      (value "MA05-2")
      (footprint "eagle-import:MA05-2")
      (libsource (lib "eagle-import") (part "MA05-2"))
    )
    (comp (ref "SV129")
      (value "MA10-1")
      (footprint "eagle-import:MA10-1")
      (libsource (lib "eagle-import") (part "MA10-1"))
    )
    (comp (ref "SV130")
      (value "MA05-2")
      (footprint "eagle-import:MA05-2")
      (libsource (lib "eagle-import") (part "MA05-2"))
    )
    (comp (ref "SV131")
      (value "MA20-1")
      (footprint "eagle-import:MA20-1")
      (libsource (lib "eagle-import") (part "MA20-1"))
    )
    (comp (ref "SV132")
      (value "MA05-2")
      (footprint "eagle-import:MA05-2")
      (libsource (lib "eagle-import") (part "MA05-2"))
    )
    (comp (ref "SV133")
      (value "MA05-2")
      (footprint "eagle-import:MA05-2")
      (libsource (lib "eagle-import") (part "MA05-2"))
    )
    (comp (ref "SV134")
      (value "MA05-2")
      (footprint "eagle-import:MA05-2")
      (libsource (lib "eagle-import") (part "MA05-2"))
    )
    (comp (ref "SV135")
      (value "MA05-2")
      (footprint "eagle-import:MA05-2")
      (libsource (lib "eagle-import") (part "MA05-2"))
    )
    (comp (ref "SV136")
      (value "MA05-2")
      (footprint "eagle-import:MA05-2")
      (libsource (lib "eagle-import") (part "MA05-2"))
    )
    (comp (ref "SV137")
      (value "MA05-2")
      (footprint "eagle-import:MA05-2")
      (libsource (lib "eagle-import") (part "MA05-2"))
    )
    (comp (ref "SV138")
      (value "MA05-2")
      (footprint "eagle-import:MA05-2")
      (libsource (lib "eagle-import") (part "MA05-2"))
    )
    (comp (ref "SV139")
      (value "MA05-2")
      (footprint "eagle-import:MA05-2")
      (libsource (lib "eagle-import") (part "MA05-2"))
    )
    (comp (ref "SV140")
      (value "MA05-2")
      (footprint "eagle-import:MA05-2")
      (libsource (lib "eagle-import") (part "MA05-2"))
    )
    (comp (ref "SV141")
      (value "MA05-2")
      (footprint "eagle-import:MA05-2")
      (libsource (lib "eagle-import") (part "MA05-2"))
    )
    (comp (ref "SV142")
      (value "MA05-2")
      (footprint "eagle-import:MA05-2")
      (libsource (lib "eagle-import") (part "MA05-2"))
    )
    (comp (ref "SV143")
      (value "MA05-2")
      (footprint "eagle-import:MA05-2")
      (libsource (lib "eagle-import") (part "MA05-2"))
    )
    (comp (ref "SV144")
      (value "MA05-2")
      (footprint "eagle-import:MA05-2")
      (libsource (lib "eagle-import") (part "MA05-2"))
    )
    (comp (ref "SV145")
      (value "MA05-2")
      (footprint "eagle-import:MA05-2")
      (libsource (lib "eagle-import") (part "MA05-2"))
    )
    (comp (ref "SV146")
      (value "MA05-2")
      (footprint "eagle-import:MA05-2")
      (libsource (lib "eagle-import") (part "MA05-2"))
    )
    (comp (ref "SV147")
      (value "MA05-2")
      (footprint "eagle-import:MA05-2")
      (libsource (lib "eagle-import") (part "MA05-2"))
    )
    (comp (ref "SV148")
      (value "MA05-2")
      (footprint "eagle-import:MA05-2")
      (libsource (lib "eagle-import") (part "MA05-2"))
    )
    (comp (ref "SV149")
      (value "MA05-2")
      (footprint "eagle-import:MA05-2")
      (libsource (lib "eagle-import") (part "MA05-2"))
    )
    (comp (ref "SV150")
      (value "MA05-2")
      (footprint "eagle-import:MA05-2")
      (libsource (lib "eagle-import") (part "MA05-2"))
    )
    (comp (ref "SV151")
      (value "MA05-2")
      (footprint "eagle-import:MA05-2")
      (libsource (lib "eagle-import") (part "MA05-2"))
    )
    (comp (ref "SV152")
      (value "MA05-2")
      (footprint "eagle-import:MA05-2")
      (libsource (lib "eagle-import") (part "MA05-2"))
    )
    (comp (ref "SV153")
      (value "MA05-2")
      (footprint "eagle-import:MA05-2")
      (libsource (lib "eagle-import") (part "MA05-2"))
    )
    (comp (ref "SV154")
      (value "MA05-2")
      (footprint "eagle-import:MA05-2")
      (libsource (lib "eagle-import") (part "MA05-2"))
    )
    (comp (ref "SV155")
      (value "MA05-2")
      (footprint "eagle-import:MA05-2")
      (libsource (lib "eagle-import") (part "MA05-2"))
    )
    (comp (ref "SV156")
      (value "MA05-2")
      (footprint "eagle-import:MA05-2")
      (libsource (lib "eagle-import") (part "MA05-2"))
    )
    (comp (ref "SV157")
      (value "MA05-2")
      (footprint "eagle-import:MA05-2")
      (libsource (lib "eagle-import") (part "MA05-2"))
    )
    (comp (ref "SV158")
      (value "MA05-2")
      (footprint "eagle-import:MA05-2")
      (libsource (lib "eagle-import") (part "MA05-2"))
    )
    (comp (ref "SV159")
      (value "MA05-2")
      (footprint "eagle-import:MA05-2")
      (libsource (lib "eagle-import") (part "MA05-2"))
    )
    (comp (ref "SV160")
      (value "MA05-2")
      (footprint "eagle-import:MA05-2")
      (libsource (lib "eagle-import") (part "MA05-2"))
    )
    (comp (ref "SV161")
      (value "MA05-2")
      (footprint "eagle-import:MA05-2")
      (libsource (lib "eagle-import") (part "MA05-2"))
    )
    (comp (ref "SV162")
      (value "MA05-2")
      (footprint "eagle-import:MA05-2")
      (libsource (lib "eagle-import") (part "MA05-2"))
    )
    (comp (ref "SV163")
      (value "MA05-2")
      (footprint "eagle-import:MA05-2")
      (libsource (lib "eagle-import") (part "MA05-2"))
    )
    (comp (ref "SV164")
      (value "MA05-2")
      (footprint "eagle-import:MA05-2")
      (libsource (lib "eagle-import") (part "MA05-2"))
    )
    (comp (ref "SV165")
      (value "MA05-2")
      (footprint "eagle-import:MA05-2")
      (libsource (lib "eagle-import") (part "MA05-2"))
    )
    (comp (ref "SV166")
      (value "MA05-2")
      (footprint "eagle-import:MA05-2")
      (libsource (lib "eagle-import") (part "MA05-2"))
    )
    (comp (ref "SV167")
      (value "MA05-2")
      (footprint "eagle-import:MA05-2")
      (libsource (lib "eagle-import") (part "MA05-2"))
    )
    (comp (ref "SV168")
      (value "MA05-2")
      (footprint "eagle-import:MA05-2")
      (libsource (lib "eagle-import") (part "MA05-2"))
    )
    (comp (ref "SV169")
      (value "MA05-2")
      (footprint "eagle-import:MA05-2")
      (libsource (lib "eagle-import") (part "MA05-2"))
    )
    (comp (ref "SV170")
      (value "MA05-2")
      (footprint "eagle-import:MA05-2")
      (libsource (lib "eagle-import") (part "MA05-2"))
    )
    (comp (ref "SV171")
      (value "MA05-2")
      (footprint "eagle-import:MA05-2")
      (libsource (lib "eagle-import") (part "MA05-2"))
    )
    (comp (ref "SV172")
      (value "MA05-2")
      (footprint "eagle-import:MA05-2")
      (libsource (lib "eagle-import") (part "MA05-2"))
    )
    (comp (ref "SV173")
      (value "MA05-2")
      (footprint "eagle-import:MA05-2")
      (libsource (lib "eagle-import") (part "MA05-2"))
    )
    (comp (ref "SV174")
      (value "MA05-2")
      (footprint "eagle-import:MA05-2")
      (libsource (lib "eagle-import") (part "MA05-2"))
    )
    (comp (ref "SV175")
      (value "MA20-1")
      (footprint "eagle-import:MA20-1")
      (libsource (lib "eagle-import") (part "MA20-1"))
    )
    (comp (ref "SV176")
      (value "MA20-1")
      (footprint "eagle-import:MA20-1")
      (libsource (lib "eagle-import") (part "MA20-1"))
    )
    (comp (ref "SV177")
      (value "MA08-1")
      (footprint "eagle-import:MA08-1")
      (libsource (lib "eagle-import") (part "MA08-1"))
    )
    (comp (ref "SV178")
      (value "MA08-1")
      (footprint "eagle-import:MA08-1")
      (libsource (lib "eagle-import") (part "MA08-1"))
    )
    (comp (ref "SV179")
      (value "MA10-1")
      (footprint "eagle-import:MA10-1")
      (libsource (lib "eagle-import") (part "MA10-1"))
    )
    (comp (ref "SV180")
      (value "MA10-1")
      (footprint "eagle-import:MA10-1")
      (libsource (lib "eagle-import") (part "MA10-1"))
    )
    (comp (ref "A1")
      (value "JP1E")
      (footprint "eagle-import:JP1")
      (libsource (lib "eagle-import") (part "JP1E"))
    )
    (comp (ref "A2")
      (value "JP1E")
      (footprint "eagle-import:JP1")
      (libsource (lib "eagle-import") (part "JP1E"))
    )
    (comp (ref "A3")
      (value "JP1E")
      (footprint "eagle-import:JP1")
      (libsource (lib "eagle-import") (part "JP1E"))
    )
    (comp (ref "A4")
      (value "JP1E")
      (footprint "eagle-import:JP1")
      (libsource (lib "eagle-import") (part "JP1E"))
    )
    (comp (ref "A5")
      (value "JP1E")
      (footprint "eagle-import:JP1")
      (libsource (lib "eagle-import") (part "JP1E"))
    )
    (comp (ref "A6")
      (value "JP1E")
      (footprint "eagle-import:JP1")
      (libsource (lib "eagle-import") (part "JP1E"))
    )
    (comp (ref "A7")
      (value "JP1E")
      (footprint "eagle-import:JP1")
      (libsource (lib "eagle-import") (part "JP1E"))
    )
    (comp (ref "A8")
      (value "JP1E")
      (footprint "eagle-import:JP1")
      (libsource (lib "eagle-import") (part "JP1E"))
    )
    (comp (ref "A9")
      (value "JP1E")
      (footprint "eagle-import:JP1")
      (libsource (lib "eagle-import") (part "JP1E"))
    )
    (comp (ref "A10")
      (value "JP1E")
      (footprint "eagle-import:JP1")
      (libsource (lib "eagle-import") (part "JP1E"))
    )
    (comp (ref "A11")
      (value "JP1E")
      (footprint "eagle-import:JP1")
      (libsource (lib "eagle-import") (part "JP1E"))
    )
    (comp (ref "A12")
      (value "JP1E")
      (footprint "eagle-import:JP1")
      (libsource (lib "eagle-import") (part "JP1E"))
    )
    (comp (ref "A13")
      (value "JP1E")
      (footprint "eagle-import:JP1")
      (libsource (lib "eagle-import") (part "JP1E"))
    )
    (comp (ref "A14")
      (value "JP1E")
      (footprint "eagle-import:JP1")
      (libsource (lib "eagle-import") (part "JP1E"))
    )
    (comp (ref "A15")
      (value "JP1E")
      (footprint "eagle-import:JP1")
      (libsource (lib "eagle-import") (part "JP1E"))
    )
    (comp (ref "A16")
      (value "JP1E")
      (footprint "eagle-import:JP1")
      (libsource (lib "eagle-import") (part "JP1E"))
    )
    (comp (ref "A17")
      (value "JP1E")
      (footprint "eagle-import:JP1")
      (libsource (lib "eagle-import") (part "JP1E"))
    )
    (comp (ref "A18")
      (value "JP1E")
      (footprint "eagle-import:JP1")
      (libsource (lib "eagle-import") (part "JP1E"))
    )
    (comp (ref "A19")
      (value "JP1E")
      (footprint "eagle-import:JP1")
      (libsource (lib "eagle-import") (part "JP1E"))
    )
    (comp (ref "A20")
      (value "JP1E")
      (footprint "eagle-import:JP1")
      (libsource (lib "eagle-import") (part "JP1E"))
    )
    (comp (ref "A21")
      (value "JP1E")
      (footprint "eagle-import:JP1")
      (libsource (lib "eagle-import") (part "JP1E"))
    )
    (comp (ref "A22")
      (value "JP1E")
      (footprint "eagle-import:JP1")
      (libsource (lib "eagle-import") (part "JP1E"))
    )
    (comp (ref "A23")
      (value "JP1E")
      (footprint "eagle-import:JP1")
      (libsource (lib "eagle-import") (part "JP1E"))
    )
    (comp (ref "A24")
      (value "JP1E")
      (footprint "eagle-import:JP1")
      (libsource (lib "eagle-import") (part "JP1E"))
    )
    (comp (ref "A25")
      (value "JP1E")
      (footprint "eagle-import:JP1")
      (libsource (lib "eagle-import") (part "JP1E"))
    )
    (comp (ref "A26")
      (value "JP1E")
      (footprint "eagle-import:JP1")
      (libsource (lib "eagle-import") (part "JP1E"))
    )
    (comp (ref "A27")
      (value "JP1E")
      (footprint "eagle-import:JP1")
      (libsource (lib "eagle-import") (part "JP1E"))
    )
    (comp (ref "A28")
      (value "JP1E")
      (footprint "eagle-import:JP1")
      (libsource (lib "eagle-import") (part "JP1E"))
    )
    (comp (ref "A29")
      (value "JP1E")
      (footprint "eagle-import:JP1")
      (libsource (lib "eagle-import") (part "JP1E"))
    )
    (comp (ref "A30")
      (value "JP1E")
      (footprint "eagle-import:JP1")
      (libsource (lib "eagle-import") (part "JP1E"))
    )
    (comp (ref "A31")
      (value "JP1E")
      (footprint "eagle-import:JP1")
      (libsource (lib "eagle-import") (part "JP1E"))
    )
    (comp (ref "A32")
      (value "JP1E")
      (footprint "eagle-import:JP1")
      (libsource (lib "eagle-import") (part "JP1E"))
    )
    (comp (ref "A33")
      (value "JP1E")
      (footprint "eagle-import:JP1")
      (libsource (lib "eagle-import") (part "JP1E"))
    )
    (comp (ref "A34")
      (value "JP1E")
      (footprint "eagle-import:JP1")
      (libsource (lib "eagle-import") (part "JP1E"))
    )
    (comp (ref "A35")
      (value "JP1E")
      (footprint "eagle-import:JP1")
      (libsource (lib "eagle-import") (part "JP1E"))
    )
    (comp (ref "A36")
      (value "JP1E")
      (footprint "eagle-import:JP1")
      (libsource (lib "eagle-import") (part "JP1E"))
    )
    (comp (ref "A37")
      (value "JP1E")
      (footprint "eagle-import:JP1")
      (libsource (lib "eagle-import") (part "JP1E"))
    )
    (comp (ref "A38")
      (value "JP1E")
      (footprint "eagle-import:JP1")
      (libsource (lib "eagle-import") (part "JP1E"))
    )
    (comp (ref "A39")
      (value "JP1E")
      (footprint "eagle-import:JP1")
      (libsource (lib "eagle-import") (part "JP1E"))
    )
    (comp (ref "A40")
      (value "JP1E")
      (footprint "eagle-import:JP1")
      (libsource (lib "eagle-import") (part "JP1E"))
    )
    (comp (ref "A41")
      (value "JP1E")
      (footprint "eagle-import:JP1")
      (libsource (lib "eagle-import") (part "JP1E"))
    )
    (comp (ref "A42")
      (value "JP1E")
      (footprint "eagle-import:JP1")
      (libsource (lib "eagle-import") (part "JP1E"))
    )
    (comp (ref "A43")
      (value "JP1E")
      (footprint "eagle-import:JP1")
      (libsource (lib "eagle-import") (part "JP1E"))
    )
    (comp (ref "A44")
      (value "JP1E")
      (footprint "eagle-import:JP1")
      (libsource (lib "eagle-import") (part "JP1E"))
    )
    (comp (ref "A45")
      (value "JP1E")
      (footprint "eagle-import:JP1")
      (libsource (lib "eagle-import") (part "JP1E"))
    )
    (comp (ref "A46")
      (value "JP1E")
      (footprint "eagle-import:JP1")
      (libsource (lib "eagle-import") (part "JP1E"))
    )
    (comp (ref "A47")
      (value "JP1E")
      (footprint "eagle-import:JP1")
      (libsource (lib "eagle-import") (part "JP1E"))
    )
    (comp (ref "A48")
      (value "JP1E")
      (footprint "eagle-import:JP1")
      (libsource (lib "eagle-import") (part "JP1E"))
    )
    (comp (ref "A49")
      (value "JP1E")
      (footprint "eagle-import:JP1")
      (libsource (lib "eagle-import") (part "JP1E"))
    )
    (comp (ref "A50")
      (value "JP1E")
      (footprint "eagle-import:JP1")
      (libsource (lib "eagle-import") (part "JP1E"))
    )
    (comp (ref "A51")
      (value "JP1E")
      (footprint "eagle-import:JP1")
      (libsource (lib "eagle-import") (part "JP1E"))
    )
    (comp (ref "A52")
      (value "JP1E")
      (footprint "eagle-import:JP1")
      (libsource (lib "eagle-import") (part "JP1E"))
    )
    (comp (ref "A53")
      (value "JP1E")
      (footprint "eagle-import:JP1")
      (libsource (lib "eagle-import") (part "JP1E"))
    )
    (comp (ref "A54")
      (value "JP1E")
      (footprint "eagle-import:JP1")
      (libsource (lib "eagle-import") (part "JP1E"))
    )
    (comp (ref "A55")
      (value "JP1E")
      (footprint "eagle-import:JP1")
      (libsource (lib "eagle-import") (part "JP1E"))
    )
    (comp (ref "A56")
      (value "JP1E")
      (footprint "eagle-import:JP1")
      (libsource (lib "eagle-import") (part "JP1E"))
    )
    (comp (ref "A57")
      (value "JP1E")
      (footprint "eagle-import:JP1")
      (libsource (lib "eagle-import") (part "JP1E"))
    )
    (comp (ref "A58")
      (value "JP1E")
      (footprint "eagle-import:JP1")
      (libsource (lib "eagle-import") (part "JP1E"))
    )
    (comp (ref "A59")
      (value "JP1E")
      (footprint "eagle-import:JP1")
      (libsource (lib "eagle-import") (part "JP1E"))
    )
    (comp (ref "A60")
      (value "JP1E")
      (footprint "eagle-import:JP1")
      (libsource (lib "eagle-import") (part "JP1E"))
    )
    (comp (ref "A61")
      (value "JP1E")
      (footprint "eagle-import:JP1")
      (libsource (lib "eagle-import") (part "JP1E"))
    )
    (comp (ref "A62")
      (value "JP1E")
      (footprint "eagle-import:JP1")
      (libsource (lib "eagle-import") (part "JP1E"))
    )
    (comp (ref "A63")
      (value "JP1E")
      (footprint "eagle-import:JP1")
      (libsource (lib "eagle-import") (part "JP1E"))
    )
    (comp (ref "A64")
      (value "JP1E")
      (footprint "eagle-import:JP1")
      (libsource (lib "eagle-import") (part "JP1E"))
    )
    (comp (ref "A65")
      (value "JP1E")
      (footprint "eagle-import:JP1")
      (libsource (lib "eagle-import") (part "JP1E"))
    )
    (comp (ref "A66")
      (value "JP1E")
      (footprint "eagle-import:JP1")
      (libsource (lib "eagle-import") (part "JP1E"))
    )
    (comp (ref "A67")
      (value "JP1E")
      (footprint "eagle-import:JP1")
      (libsource (lib "eagle-import") (part "JP1E"))
    )
    (comp (ref "A68")
      (value "JP1E")
      (footprint "eagle-import:JP1")
      (libsource (lib "eagle-import") (part "JP1E"))
    )
    (comp (ref "A69")
      (value "JP1E")
      (footprint "eagle-import:JP1")
      (libsource (lib "eagle-import") (part "JP1E"))
    )
    (comp (ref "A70")
      (value "JP1E")
      (footprint "eagle-import:JP1")
      (libsource (lib "eagle-import") (part "JP1E"))
    )
    (comp (ref "A71")
      (value "JP1E")
      (footprint "eagle-import:JP1")
      (libsource (lib "eagle-import") (part "JP1E"))
    )
    (comp (ref "A72")
      (value "JP1E")
      (footprint "eagle-import:JP1")
      (libsource (lib "eagle-import") (part "JP1E"))
    )
    (comp (ref "A73")
      (value "JP1E")
      (footprint "eagle-import:JP1")
      (libsource (lib "eagle-import") (part "JP1E"))
    )
    (comp (ref "A74")
      (value "JP1E")
      (footprint "eagle-import:JP1")
      (libsource (lib "eagle-import") (part "JP1E"))
    )
    (comp (ref "A75")
      (value "JP1E")
      (footprint "eagle-import:JP1")
      (libsource (lib "eagle-import") (part "JP1E"))
    )
    (comp (ref "A76")
      (value "JP1E")
      (footprint "eagle-import:JP1")
      (libsource (lib "eagle-import") (part "JP1E"))
    )
    (comp (ref "A77")
      (value "JP1E")
      (footprint "eagle-import:JP1")
      (libsource (lib "eagle-import") (part "JP1E"))
    )
    (comp (ref "A78")
      (value "JP1E")
      (footprint "eagle-import:JP1")
      (libsource (lib "eagle-import") (part "JP1E"))
    )
    (comp (ref "A79")
      (value "JP1E")
      (footprint "eagle-import:JP1")
      (libsource (lib "eagle-import") (part "JP1E"))
    )
    (comp (ref "A80")
      (value "JP1E")
      (footprint "eagle-import:JP1")
      (libsource (lib "eagle-import") (part "JP1E"))
    )
    (comp (ref "A81")
      (value "JP1E")
      (footprint "eagle-import:JP1")
      (libsource (lib "eagle-import") (part "JP1E"))
    )
    (comp (ref "A82")
      (value "JP1E")
      (footprint "eagle-import:JP1")
      (libsource (lib "eagle-import") (part "JP1E"))
    )
    (comp (ref "A83")
      (value "JP1E")
      (footprint "eagle-import:JP1")
      (libsource (lib "eagle-import") (part "JP1E"))
    )
    (comp (ref "A84")
      (value "JP1E")
      (footprint "eagle-import:JP1")
      (libsource (lib "eagle-import") (part "JP1E"))
    )
    (comp (ref "A85")
      (value "JP1E")
      (footprint "eagle-import:JP1")
      (libsource (lib "eagle-import") (part "JP1E"))
    )
    (comp (ref "A86")
      (value "JP1E")
      (footprint "eagle-import:JP1")
      (libsource (lib "eagle-import") (part "JP1E"))
    )
    (comp (ref "A87")
      (value "JP1E")
      (footprint "eagle-import:JP1")
      (libsource (lib "eagle-import") (part "JP1E"))
    )
    (comp (ref "A88")
      (value "JP1E")
      (footprint "eagle-import:JP1")
      (libsource (lib "eagle-import") (part "JP1E"))
    )
    (comp (ref "A89")
      (value "JP1E")
      (footprint "eagle-import:JP1")
      (libsource (lib "eagle-import") (part "JP1E"))
    )
    (comp (ref "A90")
      (value "JP1E")
      (footprint "eagle-import:JP1")
      (libsource (lib "eagle-import") (part "JP1E"))
    )
    (comp (ref "A91")
      (value "JP1E")
      (footprint "eagle-import:JP1")
      (libsource (lib "eagle-import") (part "JP1E"))
    )
    (comp (ref "A92")
      (value "JP1E")
      (footprint "eagle-import:JP1")
      (libsource (lib "eagle-import") (part "JP1E"))
    )
    (comp (ref "A93")
      (value "JP1E")
      (footprint "eagle-import:JP1")
      (libsource (lib "eagle-import") (part "JP1E"))
    )
    (comp (ref "A94")
      (value "JP1E")
      (footprint "eagle-import:JP1")
      (libsource (lib "eagle-import") (part "JP1E"))
    )
    (comp (ref "A95")
      (value "JP1E")
      (footprint "eagle-import:JP1")
      (libsource (lib "eagle-import") (part "JP1E"))
    )
    (comp (ref "A96")
      (value "JP1E")
      (footprint "eagle-import:JP1")
      (libsource (lib "eagle-import") (part "JP1E"))
    )
    (comp (ref "A97")
      (value "JP1E")
      (footprint "eagle-import:JP1")
      (libsource (lib "eagle-import") (part "JP1E"))
    )
    (comp (ref "A98")
      (value "JP1E")
      (footprint "eagle-import:JP1")
      (libsource (lib "eagle-import") (part "JP1E"))
    )
    (comp (ref "A99")
      (value "JP1E")
      (footprint "eagle-import:JP1")
      (libsource (lib "eagle-import") (part "JP1E"))
    )
    (comp (ref "A100")
      (value "JP1E")
      (footprint "eagle-import:JP1")
      (libsource (lib "eagle-import") (part "JP1E"))
    )
    (comp (ref "A101")
      (value "JP1E")
      (footprint "eagle-import:JP1")
      (libsource (lib "eagle-import") (part "JP1E"))
    )
    (comp (ref "A102")
      (value "JP1E")
      (footprint "eagle-import:JP1")
      (libsource (lib "eagle-import") (part "JP1E"))
    )
    (comp (ref "A103")
      (value "JP1E")
      (footprint "eagle-import:JP1")
      (libsource (lib "eagle-import") (part "JP1E"))
    )
    (comp (ref "A104")
      (value "JP1E")
      (footprint "eagle-import:JP1")
      (libsource (lib "eagle-import") (part "JP1E"))
    )
    (comp (ref "A105")
      (value "JP1E")
      (footprint "eagle-import:JP1")
      (libsource (lib "eagle-import") (part "JP1E"))
    )
    (comp (ref "A106")
      (value "JP1E")
      (footprint "eagle-import:JP1")
      (libsource (lib "eagle-import") (part "JP1E"))
    )
    (comp (ref "A107")
      (value "JP1E")
      (footprint "eagle-import:JP1")
      (libsource (lib "eagle-import") (part "JP1E"))
    )
    (comp (ref "A108")
      (value "JP1E")
      (footprint "eagle-import:JP1")
      (libsource (lib "eagle-import") (part "JP1E"))
    )
    (comp (ref "A109")
      (value "JP1E")
      (footprint "eagle-import:JP1")
      (libsource (lib "eagle-import") (part "JP1E"))
    )
    (comp (ref "A110")
      (value "JP1E")
      (footprint "eagle-import:JP1")
      (libsource (lib "eagle-import") (part "JP1E"))
    )
    (comp (ref "A111")
      (value "JP1E")
      (footprint "eagle-import:JP1")
      (libsource (lib "eagle-import") (part "JP1E"))
    )
    (comp (ref "A112")
      (value "JP1E")
      (footprint "eagle-import:JP1")
      (libsource (lib "eagle-import") (part "JP1E"))
    )
    (comp (ref "A113")
      (value "JP1E")
      (footprint "eagle-import:JP1")
      (libsource (lib "eagle-import") (part "JP1E"))
    )
    (comp (ref "A114")
      (value "JP1E")
      (footprint "eagle-import:JP1")
      (libsource (lib "eagle-import") (part "JP1E"))
    )
    (comp (ref "A115")
      (value "JP1E")
      (footprint "eagle-import:JP1")
      (libsource (lib "eagle-import") (part "JP1E"))
    )
    (comp (ref "A116")
      (value "JP1E")
      (footprint "eagle-import:JP1")
      (libsource (lib "eagle-import") (part "JP1E"))
    )
    (comp (ref "A117")
      (value "JP1E")
      (footprint "eagle-import:JP1")
      (libsource (lib "eagle-import") (part "JP1E"))
    )
    (comp (ref "A118")
      (value "JP1E")
      (footprint "eagle-import:JP1")
      (libsource (lib "eagle-import") (part "JP1E"))
    )
    (comp (ref "A119")
      (value "JP1E")
      (footprint "eagle-import:JP1")
      (libsource (lib "eagle-import") (part "JP1E"))
    )
    (comp (ref "A120")
      (value "JP1E")
      (footprint "eagle-import:JP1")
      (libsource (lib "eagle-import") (part "JP1E"))
    )
    (comp (ref "A121")
      (value "JP1E")
      (footprint "eagle-import:JP1")
      (libsource (lib "eagle-import") (part "JP1E"))
    )
    (comp (ref "A122")
      (value "JP1E")
      (footprint "eagle-import:JP1")
      (libsource (lib "eagle-import") (part "JP1E"))
    )
    (comp (ref "A123")
      (value "JP1E")
      (footprint "eagle-import:JP1")
      (libsource (lib "eagle-import") (part "JP1E"))
    )
    (comp (ref "A124")
      (value "JP1E")
      (footprint "eagle-import:JP1")
      (libsource (lib "eagle-import") (part "JP1E"))
    )
    (comp (ref "A125")
      (value "JP1E")
      (footprint "eagle-import:JP1")
      (libsource (lib "eagle-import") (part "JP1E"))
    )
    (comp (ref "A126")
      (value "JP1E")
      (footprint "eagle-import:JP1")
      (libsource (lib "eagle-import") (part "JP1E"))
    )
    (comp (ref "A127")
      (value "JP1E")
      (footprint "eagle-import:JP1")
      (libsource (lib "eagle-import") (part "JP1E"))
    )
    (comp (ref "A128")
      (value "JP1E")
      (footprint "eagle-import:JP1")
      (libsource (lib "eagle-import") (part "JP1E"))
    )
    (comp (ref "A129")
      (value "JP1E")
      (footprint "eagle-import:JP1")
      (libsource (lib "eagle-import") (part "JP1E"))
    )
    (comp (ref "A130")
      (value "JP1E")
      (footprint "eagle-import:JP1")
      (libsource (lib "eagle-import") (part "JP1E"))
    )
    (comp (ref "A131")
      (value "JP1E")
      (footprint "eagle-import:JP1")
      (libsource (lib "eagle-import") (part "JP1E"))
    )
    (comp (ref "A132")
      (value "JP1E")
      (footprint "eagle-import:JP1")
      (libsource (lib "eagle-import") (part "JP1E"))
    )
    (comp (ref "A133")
      (value "JP1E")
      (footprint "eagle-import:JP1")
      (libsource (lib "eagle-import") (part "JP1E"))
    )
    (comp (ref "A134")
      (value "JP1E")
      (footprint "eagle-import:JP1")
      (libsource (lib "eagle-import") (part "JP1E"))
    )
    (comp (ref "A135")
      (value "JP1E")
      (footprint "eagle-import:JP1")
      (libsource (lib "eagle-import") (part "JP1E"))
    )
    (comp (ref "A136")
      (value "JP1E")
      (footprint "eagle-import:JP1")
      (libsource (lib "eagle-import") (part "JP1E"))
    )
    (comp (ref "A137")
      (value "JP1E")
      (footprint "eagle-import:JP1")
      (libsource (lib "eagle-import") (part "JP1E"))
    )
    (comp (ref "A138")
      (value "JP1E")
      (footprint "eagle-import:JP1")
      (libsource (lib "eagle-import") (part "JP1E"))
    )
    (comp (ref "A139")
      (value "JP1E")
      (footprint "eagle-import:JP1")
      (libsource (lib "eagle-import") (part "JP1E"))
    )
    (comp (ref "A140")
      (value "JP1E")
      (footprint "eagle-import:JP1")
      (libsource (lib "eagle-import") (part "JP1E"))
    )
    (comp (ref "A141")
      (value "JP1E")
      (footprint "eagle-import:JP1")
      (libsource (lib "eagle-import") (part "JP1E"))
    )
    (comp (ref "A142")
      (value "JP1E")
      (footprint "eagle-import:JP1")
      (libsource (lib "eagle-import") (part "JP1E"))
    )
    (comp (ref "A143")
      (value "JP1E")
      (footprint "eagle-import:JP1")
      (libsource (lib "eagle-import") (part "JP1E"))
    )
    (comp (ref "A144")
      (value "JP1E")
      (footprint "eagle-import:JP1")
      (libsource (lib "eagle-import") (part "JP1E"))
    )
    (comp (ref "A145")
      (value "JP1E")
      (footprint "eagle-import:JP1")
      (libsource (lib "eagle-import") (part "JP1E"))
    )
    (comp (ref "A146")
      (value "JP1E")
      (footprint "eagle-import:JP1")
      (libsource (lib "eagle-import") (part "JP1E"))
    )
    (comp (ref "A147")
      (value "JP1E")
      (footprint "eagle-import:JP1")
      (libsource (lib "eagle-import") (part "JP1E"))
    )
    (comp (ref "A148")
      (value "JP1E")
      (footprint "eagle-import:JP1")
      (libsource (lib "eagle-import") (part "JP1E"))
    )
    (comp (ref "A149")
      (value "JP1E")
      (footprint "eagle-import:JP1")
      (libsource (lib "eagle-import") (part "JP1E"))
    )
    (comp (ref "A150")
      (value "JP1E")
      (footprint "eagle-import:JP1")
      (libsource (lib "eagle-import") (part "JP1E"))
    )
    (comp (ref "A151")
      (value "JP1E")
      (footprint "eagle-import:JP1")
      (libsource (lib "eagle-import") (part "JP1E"))
    )
    (comp (ref "A152")
      (value "JP1E")
      (footprint "eagle-import:JP1")
      (libsource (lib "eagle-import") (part "JP1E"))
    )
    (comp (ref "A153")
      (value "JP1E")
      (footprint "eagle-import:JP1")
      (libsource (lib "eagle-import") (part "JP1E"))
    )
    (comp (ref "A154")
      (value "JP1E")
      (footprint "eagle-import:JP1")
      (libsource (lib "eagle-import") (part "JP1E"))
    )
    (comp (ref "A155")
      (value "JP1E")
      (footprint "eagle-import:JP1")
      (libsource (lib "eagle-import") (part "JP1E"))
    )
    (comp (ref "A156")
      (value "JP1E")
      (footprint "eagle-import:JP1")
      (libsource (lib "eagle-import") (part "JP1E"))
    )
    (comp (ref "A157")
      (value "JP1E")
      (footprint "eagle-import:JP1")
      (libsource (lib "eagle-import") (part "JP1E"))
    )
    (comp (ref "A158")
      (value "JP1E")
      (footprint "eagle-import:JP1")
      (libsource (lib "eagle-import") (part "JP1E"))
    )
    (comp (ref "A159")
      (value "JP1E")
      (footprint "eagle-import:JP1")
      (libsource (lib "eagle-import") (part "JP1E"))
    )
    (comp (ref "A160")
      (value "JP1E")
      (footprint "eagle-import:JP1")
      (libsource (lib "eagle-import") (part "JP1E"))
    )
    (comp (ref "A161")
      (value "JP1E")
      (footprint "eagle-import:JP1")
      (libsource (lib "eagle-import") (part "JP1E"))
    )
    (comp (ref "A162")
      (value "JP1E")
      (footprint "eagle-import:JP1")
      (libsource (lib "eagle-import") (part "JP1E"))
    )
    (comp (ref "A163")
      (value "JP1E")
      (footprint "eagle-import:JP1")
      (libsource (lib "eagle-import") (part "JP1E"))
    )
    (comp (ref "A164")
      (value "JP1E")
      (footprint "eagle-import:JP1")
      (libsource (lib "eagle-import") (part "JP1E"))
    )
    (comp (ref "A165")
      (value "JP1E")
      (footprint "eagle-import:JP1")
      (libsource (lib "eagle-import") (part "JP1E"))
    )
    (comp (ref "A166")
      (value "JP1E")
      (footprint "eagle-import:JP1")
      (libsource (lib "eagle-import") (part "JP1E"))
    )
    (comp (ref "A167")
      (value "JP1E")
      (footprint "eagle-import:JP1")
      (libsource (lib "eagle-import") (part "JP1E"))
    )
    (comp (ref "A168")
      (value "JP1E")
      (footprint "eagle-import:JP1")
      (libsource (lib "eagle-import") (part "JP1E"))
    )
    (comp (ref "A169")
      (value "JP1E")
      (footprint "eagle-import:JP1")
      (libsource (lib "eagle-import") (part "JP1E"))
    )
    (comp (ref "A170")
      (value "JP1E")
      (footprint "eagle-import:JP1")
      (libsource (lib "eagle-import") (part "JP1E"))
    )
    (comp (ref "A171")
      (value "JP1E")
      (footprint "eagle-import:JP1")
      (libsource (lib "eagle-import") (part "JP1E"))
    )
    (comp (ref "A172")
      (value "JP1E")
      (footprint "eagle-import:JP1")
      (libsource (lib "eagle-import") (part "JP1E"))
    )
    (comp (ref "A173")
      (value "JP1E")
      (footprint "eagle-import:JP1")
      (libsource (lib "eagle-import") (part "JP1E"))
    )
    (comp (ref "A174")
      (value "JP1E")
      (footprint "eagle-import:JP1")
      (libsource (lib "eagle-import") (part "JP1E"))
    )
    (comp (ref "A175")
      (value "JP1E")
      (footprint "eagle-import:JP1")
      (libsource (lib "eagle-import") (part "JP1E"))
    )
    (comp (ref "A176")
      (value "JP1E")
      (footprint "eagle-import:JP1")
      (libsource (lib "eagle-import") (part "JP1E"))
    )
    (comp (ref "A177")
      (value "JP1E")
      (footprint "eagle-import:JP1")
      (libsource (lib "eagle-import") (part "JP1E"))
    )
    (comp (ref "A178")
      (value "JP1E")
      (footprint "eagle-import:JP1")
      (libsource (lib "eagle-import") (part "JP1E"))
    )
    (comp (ref "A179")
      (value "JP1E")
      (footprint "eagle-import:JP1")
      (libsource (lib "eagle-import") (part "JP1E"))
    )
    (comp (ref "A180")
      (value "JP1E")
      (footprint "eagle-import:JP1")
      (libsource (lib "eagle-import") (part "JP1E"))
    )
    (comp (ref "A181")
      (value "JP1E")
      (footprint "eagle-import:JP1")
      (libsource (lib "eagle-import") (part "JP1E"))
    )
    (comp (ref "A182")
      (value "JP1E")
      (footprint "eagle-import:JP1")
      (libsource (lib "eagle-import") (part "JP1E"))
    )
    (comp (ref "A183")
      (value "JP1E")
      (footprint "eagle-import:JP1")
      (libsource (lib "eagle-import") (part "JP1E"))
    )
    (comp (ref "A184")
      (value "JP1E")
      (footprint "eagle-import:JP1")
      (libsource (lib "eagle-import") (part "JP1E"))
    )
    (comp (ref "A185")
      (value "JP1E")
      (footprint "eagle-import:JP1")
      (libsource (lib "eagle-import") (part "JP1E"))
    )
    (comp (ref "A186")
      (value "JP1E")
      (footprint "eagle-import:JP1")
      (libsource (lib "eagle-import") (part "JP1E"))
    )
    (comp (ref "A187")
      (value "JP1E")
      (footprint "eagle-import:JP1")
      (libsource (lib "eagle-import") (part "JP1E"))
    )
    (comp (ref "A188")
      (value "JP1E")
      (footprint "eagle-import:JP1")
      (libsource (lib "eagle-import") (part "JP1E"))
    )
    (comp (ref "A189")
      (value "JP1E")
      (footprint "eagle-import:JP1")
      (libsource (lib "eagle-import") (part "JP1E"))
    )
    (comp (ref "A190")
      (value "JP1E")
      (footprint "eagle-import:JP1")
      (libsource (lib "eagle-import") (part "JP1E"))
    )
    (comp (ref "A191")
      (value "JP1E")
      (footprint "eagle-import:JP1")
      (libsource (lib "eagle-import") (part "JP1E"))
    )
    (comp (ref "A192")
      (value "JP1E")
      (footprint "eagle-import:JP1")
      (libsource (lib "eagle-import") (part "JP1E"))
    )
    (comp (ref "A193")
      (value "JP1E")
      (footprint "eagle-import:JP1")
      (libsource (lib "eagle-import") (part "JP1E"))
    )
    (comp (ref "A194")
      (value "JP1E")
      (footprint "eagle-import:JP1")
      (libsource (lib "eagle-import") (part "JP1E"))
    )
    (comp (ref "A195")
      (value "JP1E")
      (footprint "eagle-import:JP1")
      (libsource (lib "eagle-import") (part "JP1E"))
    )
    (comp (ref "A196")
      (value "JP1E")
      (footprint "eagle-import:JP1")
      (libsource (lib "eagle-import") (part "JP1E"))
    )
    (comp (ref "A197")
      (value "JP1E")
      (footprint "eagle-import:JP1")
      (libsource (lib "eagle-import") (part "JP1E"))
    )
    (comp (ref "A198")
      (value "JP1E")
      (footprint "eagle-import:JP1")
      (libsource (lib "eagle-import") (part "JP1E"))
    )
    (comp (ref "A199")
      (value "JP1E")
      (footprint "eagle-import:JP1")
      (libsource (lib "eagle-import") (part "JP1E"))
    )
    (comp (ref "A200")
      (value "JP1E")
      (footprint "eagle-import:JP1")
      (libsource (lib "eagle-import") (part "JP1E"))
    )
    (comp (ref "A201")
      (value "JP1E")
      (footprint "eagle-import:JP1")
      (libsource (lib "eagle-import") (part "JP1E"))
    )
    (comp (ref "A202")
      (value "JP1E")
      (footprint "eagle-import:JP1")
      (libsource (lib "eagle-import") (part "JP1E"))
    )
    (comp (ref "A203")
      (value "JP1E")
      (footprint "eagle-import:JP1")
      (libsource (lib "eagle-import") (part "JP1E"))
    )
    (comp (ref "A204")
      (value "JP1E")
      (footprint "eagle-import:JP1")
      (libsource (lib "eagle-import") (part "JP1E"))
    )
    (comp (ref "A205")
      (value "JP1E")
      (footprint "eagle-import:JP1")
      (libsource (lib "eagle-import") (part "JP1E"))
    )
    (comp (ref "A206")
      (value "JP1E")
      (footprint "eagle-import:JP1")
      (libsource (lib "eagle-import") (part "JP1E"))
    )
    (comp (ref "A207")
      (value "JP1E")
      (footprint "eagle-import:JP1")
      (libsource (lib "eagle-import") (part "JP1E"))
    )
    (comp (ref "A208")
      (value "JP1E")
      (footprint "eagle-import:JP1")
      (libsource (lib "eagle-import") (part "JP1E"))
    )
    (comp (ref "A209")
      (value "JP1E")
      (footprint "eagle-import:JP1")
      (libsource (lib "eagle-import") (part "JP1E"))
    )
    (comp (ref "A210")
      (value "JP1E")
      (footprint "eagle-import:JP1")
      (libsource (lib "eagle-import") (part "JP1E"))
    )
    (comp (ref "A211")
      (value "JP1E")
      (footprint "eagle-import:JP1")
      (libsource (lib "eagle-import") (part "JP1E"))
    )
    (comp (ref "A212")
      (value "JP1E")
      (footprint "eagle-import:JP1")
      (libsource (lib "eagle-import") (part "JP1E"))
    )
    (comp (ref "A213")
      (value "JP1E")
      (footprint "eagle-import:JP1")
      (libsource (lib "eagle-import") (part "JP1E"))
    )
    (comp (ref "A214")
      (value "JP1E")
      (footprint "eagle-import:JP1")
      (libsource (lib "eagle-import") (part "JP1E"))
    )
    (comp (ref "A215")
      (value "JP1E")
      (footprint "eagle-import:JP1")
      (libsource (lib "eagle-import") (part "JP1E"))
    )
    (comp (ref "A216")
      (value "JP1E")
      (footprint "eagle-import:JP1")
      (libsource (lib "eagle-import") (part "JP1E"))
    )
    (comp (ref "A217")
      (value "JP1E")
      (footprint "eagle-import:JP1")
      (libsource (lib "eagle-import") (part "JP1E"))
    )
    (comp (ref "A218")
      (value "JP1E")
      (footprint "eagle-import:JP1")
      (libsource (lib "eagle-import") (part "JP1E"))
    )
    (comp (ref "A219")
      (value "JP1E")
      (footprint "eagle-import:JP1")
      (libsource (lib "eagle-import") (part "JP1E"))
    )
    (comp (ref "A220")
      (value "JP1E")
      (footprint "eagle-import:JP1")
      (libsource (lib "eagle-import") (part "JP1E"))
    )
    (comp (ref "A221")
      (value "JP1E")
      (footprint "eagle-import:JP1")
      (libsource (lib "eagle-import") (part "JP1E"))
    )
    (comp (ref "A222")
      (value "JP1E")
      (footprint "eagle-import:JP1")
      (libsource (lib "eagle-import") (part "JP1E"))
    )
    (comp (ref "A223")
      (value "JP1E")
      (footprint "eagle-import:JP1")
      (libsource (lib "eagle-import") (part "JP1E"))
    )
    (comp (ref "A224")
      (value "JP1E")
      (footprint "eagle-import:JP1")
      (libsource (lib "eagle-import") (part "JP1E"))
    )
    (comp (ref "A225")
      (value "JP1E")
      (footprint "eagle-import:JP1")
      (libsource (lib "eagle-import") (part "JP1E"))
    )
    (comp (ref "A226")
      (value "JP1E")
      (footprint "eagle-import:JP1")
      (libsource (lib "eagle-import") (part "JP1E"))
    )
    (comp (ref "A227")
      (value "JP1E")
      (footprint "eagle-import:JP1")
      (libsource (lib "eagle-import") (part "JP1E"))
    )
    (comp (ref "A228")
      (value "JP1E")
      (footprint "eagle-import:JP1")
      (libsource (lib "eagle-import") (part "JP1E"))
    )
    (comp (ref "A229")
      (value "JP1E")
      (footprint "eagle-import:JP1")
      (libsource (lib "eagle-import") (part "JP1E"))
    )
    (comp (ref "A230")
      (value "JP1E")
      (footprint "eagle-import:JP1")
      (libsource (lib "eagle-import") (part "JP1E"))
    )
    (comp (ref "A231")
      (value "JP1E")
      (footprint "eagle-import:JP1")
      (libsource (lib "eagle-import") (part "JP1E"))
    )
    (comp (ref "A232")
      (value "JP1E")
      (footprint "eagle-import:JP1")
      (libsource (lib "eagle-import") (part "JP1E"))
    )
    (comp (ref "A233")
      (value "JP1E")
      (footprint "eagle-import:JP1")
      (libsource (lib "eagle-import") (part "JP1E"))
    )
    (comp (ref "A234")
      (value "JP1E")
      (footprint "eagle-import:JP1")
      (libsource (lib "eagle-import") (part "JP1E"))
    )
    (comp (ref "A235")
      (value "JP1E")
      (footprint "eagle-import:JP1")
      (libsource (lib "eagle-import") (part "JP1E"))
    )
    (comp (ref "A236")
      (value "JP1E")
      (footprint "eagle-import:JP1")
      (libsource (lib "eagle-import") (part "JP1E"))
    )
    (comp (ref "A237")
      (value "JP1E")
      (footprint "eagle-import:JP1")
      (libsource (lib "eagle-import") (part "JP1E"))
    )
    (comp (ref "A238")
      (value "JP1E")
      (footprint "eagle-import:JP1")
      (libsource (lib "eagle-import") (part "JP1E"))
    )
    (comp (ref "A239")
      (value "JP1E")
      (footprint "eagle-import:JP1")
      (libsource (lib "eagle-import") (part "JP1E"))
    )
    (comp (ref "A240")
      (value "JP1E")
      (footprint "eagle-import:JP1")
      (libsource (lib "eagle-import") (part "JP1E"))
    )
    (comp (ref "A241")
      (value "JP1E")
      (footprint "eagle-import:JP1")
      (libsource (lib "eagle-import") (part "JP1E"))
    )
    (comp (ref "A242")
      (value "JP1E")
      (footprint "eagle-import:JP1")
      (libsource (lib "eagle-import") (part "JP1E"))
    )
    (comp (ref "A243")
      (value "JP1E")
      (footprint "eagle-import:JP1")
      (libsource (lib "eagle-import") (part "JP1E"))
    )
    (comp (ref "A244")
      (value "JP1E")
      (footprint "eagle-import:JP1")
      (libsource (lib "eagle-import") (part "JP1E"))
    )
    (comp (ref "A245")
      (value "JP1E")
      (footprint "eagle-import:JP1")
      (libsource (lib "eagle-import") (part "JP1E"))
    )
    (comp (ref "A246")
      (value "JP1E")
      (footprint "eagle-import:JP1")
      (libsource (lib "eagle-import") (part "JP1E"))
    )
    (comp (ref "A247")
      (value "JP1E")
      (footprint "eagle-import:JP1")
      (libsource (lib "eagle-import") (part "JP1E"))
    )
    (comp (ref "A248")
      (value "JP1E")
      (footprint "eagle-import:JP1")
      (libsource (lib "eagle-import") (part "JP1E"))
    )
    (comp (ref "A249")
      (value "JP1E")
      (footprint "eagle-import:JP1")
      (libsource (lib "eagle-import") (part "JP1E"))
    )
    (comp (ref "A250")
      (value "JP1E")
      (footprint "eagle-import:JP1")
      (libsource (lib "eagle-import") (part "JP1E"))
    )
    (comp (ref "A251")
      (value "JP1E")
      (footprint "eagle-import:JP1")
      (libsource (lib "eagle-import") (part "JP1E"))
    )
    (comp (ref "A252")
      (value "JP1E")
      (footprint "eagle-import:JP1")
      (libsource (lib "eagle-import") (part "JP1E"))
    )
    (comp (ref "A253")
      (value "JP1E")
      (footprint "eagle-import:JP1")
      (libsource (lib "eagle-import") (part "JP1E"))
    )
    (comp (ref "A254")
      (value "JP1E")
      (footprint "eagle-import:JP1")
      (libsource (lib "eagle-import") (part "JP1E"))
    )
    (comp (ref "A255")
      (value "JP1E")
      (footprint "eagle-import:JP1")
      (libsource (lib "eagle-import") (part "JP1E"))
    )
    (comp (ref "A256")
      (value "JP1E")
      (footprint "eagle-import:JP1")
      (libsource (lib "eagle-import") (part "JP1E"))
    )
    (comp (ref "A257")
      (value "JP1E")
      (footprint "eagle-import:JP1")
      (libsource (lib "eagle-import") (part "JP1E"))
    )
    (comp (ref "A258")
      (value "JP1E")
      (footprint "eagle-import:JP1")
      (libsource (lib "eagle-import") (part "JP1E"))
    )
    (comp (ref "A259")
      (value "JP1E")
      (footprint "eagle-import:JP1")
      (libsource (lib "eagle-import") (part "JP1E"))
    )
    (comp (ref "A260")
      (value "JP1E")
      (footprint "eagle-import:JP1")
      (libsource (lib "eagle-import") (part "JP1E"))
    )
    (comp (ref "A261")
      (value "JP1E")
      (footprint "eagle-import:JP1")
      (libsource (lib "eagle-import") (part "JP1E"))
    )
    (comp (ref "A262")
      (value "JP1E")
      (footprint "eagle-import:JP1")
      (libsource (lib "eagle-import") (part "JP1E"))
    )
    (comp (ref "A263")
      (value "JP1E")
      (footprint "eagle-import:JP1")
      (libsource (lib "eagle-import") (part "JP1E"))
    )
    (comp (ref "A264")
      (value "JP1E")
      (footprint "eagle-import:JP1")
      (libsource (lib "eagle-import") (part "JP1E"))
    )
    (comp (ref "A265")
      (value "JP1E")
      (footprint "eagle-import:JP1")
      (libsource (lib "eagle-import") (part "JP1E"))
    )
    (comp (ref "A266")
      (value "JP1E")
      (footprint "eagle-import:JP1")
      (libsource (lib "eagle-import") (part "JP1E"))
    )
    (comp (ref "A267")
      (value "JP1E")
      (footprint "eagle-import:JP1")
      (libsource (lib "eagle-import") (part "JP1E"))
    )
    (comp (ref "A268")
      (value "JP1E")
      (footprint "eagle-import:JP1")
      (libsource (lib "eagle-import") (part "JP1E"))
    )
    (comp (ref "A269")
      (value "JP1E")
      (footprint "eagle-import:JP1")
      (libsource (lib "eagle-import") (part "JP1E"))
    )
    (comp (ref "A270")
      (value "JP1E")
      (footprint "eagle-import:JP1")
      (libsource (lib "eagle-import") (part "JP1E"))
    )
    (comp (ref "A271")
      (value "JP1E")
      (footprint "eagle-import:JP1")
      (libsource (lib "eagle-import") (part "JP1E"))
    )
    (comp (ref "A272")
      (value "JP1E")
      (footprint "eagle-import:JP1")
      (libsource (lib "eagle-import") (part "JP1E"))
    )
    (comp (ref "A273")
      (value "JP1E")
      (footprint "eagle-import:JP1")
      (libsource (lib "eagle-import") (part "JP1E"))
    )
    (comp (ref "A274")
      (value "JP1E")
      (footprint "eagle-import:JP1")
      (libsource (lib "eagle-import") (part "JP1E"))
    )
    (comp (ref "A275")
      (value "JP1E")
      (footprint "eagle-import:JP1")
      (libsource (lib "eagle-import") (part "JP1E"))
    )
    (comp (ref "A276")
      (value "JP1E")
      (footprint "eagle-import:JP1")
      (libsource (lib "eagle-import") (part "JP1E"))
    )
    (comp (ref "A277")
      (value "JP1E")
      (footprint "eagle-import:JP1")
      (libsource (lib "eagle-import") (part "JP1E"))
    )
    (comp (ref "A278")
      (value "JP1E")
      (footprint "eagle-import:JP1")
      (libsource (lib "eagle-import") (part "JP1E"))
    )
    (comp (ref "A279")
      (value "JP1E")
      (footprint "eagle-import:JP1")
      (libsource (lib "eagle-import") (part "JP1E"))
    )
    (comp (ref "A280")
      (value "JP1E")
      (footprint "eagle-import:JP1")
      (libsource (lib "eagle-import") (part "JP1E"))
    )
    (comp (ref "A281")
      (value "JP1E")
      (footprint "eagle-import:JP1")
      (libsource (lib "eagle-import") (part "JP1E"))
    )
    (comp (ref "A282")
      (value "JP1E")
      (footprint "eagle-import:JP1")
      (libsource (lib "eagle-import") (part "JP1E"))
    )
    (comp (ref "A283")
      (value "JP1E")
      (footprint "eagle-import:JP1")
      (libsource (lib "eagle-import") (part "JP1E"))
    )
    (comp (ref "A284")
      (value "JP1E")
      (footprint "eagle-import:JP1")
      (libsource (lib "eagle-import") (part "JP1E"))
    )
    (comp (ref "A285")
      (value "JP1E")
      (footprint "eagle-import:JP1")
      (libsource (lib "eagle-import") (part "JP1E"))
    )
    (comp (ref "A286")
      (value "JP1E")
      (footprint "eagle-import:JP1")
      (libsource (lib "eagle-import") (part "JP1E"))
    )
    (comp (ref "A287")
      (value "JP1E")
      (footprint "eagle-import:JP1")
      (libsource (lib "eagle-import") (part "JP1E"))
    )
    (comp (ref "A288")
      (value "JP1E")
      (footprint "eagle-import:JP1")
      (libsource (lib "eagle-import") (part "JP1E"))
    )
    (comp (ref "A289")
      (value "JP1E")
      (footprint "eagle-import:JP1")
      (libsource (lib "eagle-import") (part "JP1E"))
    )
    (comp (ref "A290")
      (value "JP1E")
      (footprint "eagle-import:JP1")
      (libsource (lib "eagle-import") (part "JP1E"))
    )
    (comp (ref "A291")
      (value "JP1E")
      (footprint "eagle-import:JP1")
      (libsource (lib "eagle-import") (part "JP1E"))
    )
    (comp (ref "A292")
      (value "JP1E")
      (footprint "eagle-import:JP1")
      (libsource (lib "eagle-import") (part "JP1E"))
    )
    (comp (ref "A293")
      (value "JP1E")
      (footprint "eagle-import:JP1")
      (libsource (lib "eagle-import") (part "JP1E"))
    )
    (comp (ref "A294")
      (value "JP1E")
      (footprint "eagle-import:JP1")
      (libsource (lib "eagle-import") (part "JP1E"))
    )
    (comp (ref "A295")
      (value "JP1E")
      (footprint "eagle-import:JP1")
      (libsource (lib "eagle-import") (part "JP1E"))
    )
    (comp (ref "A296")
      (value "JP1E")
      (footprint "eagle-import:JP1")
      (libsource (lib "eagle-import") (part "JP1E"))
    )
    (comp (ref "A297")
      (value "JP1E")
      (footprint "eagle-import:JP1")
      (libsource (lib "eagle-import") (part "JP1E"))
    )
    (comp (ref "A298")
      (value "JP1E")
      (footprint "eagle-import:JP1")
      (libsource (lib "eagle-import") (part "JP1E"))
    )
    (comp (ref "A299")
      (value "JP1E")
      (footprint "eagle-import:JP1")
      (libsource (lib "eagle-import") (part "JP1E"))
    )
    (comp (ref "A300")
      (value "JP1E")
      (footprint "eagle-import:JP1")
      (libsource (lib "eagle-import") (part "JP1E"))
    )
    (comp (ref "A301")
      (value "JP1E")
      (footprint "eagle-import:JP1")
      (libsource (lib "eagle-import") (part "JP1E"))
    )
    (comp (ref "A302")
      (value "JP1E")
      (footprint "eagle-import:JP1")
      (libsource (lib "eagle-import") (part "JP1E"))
    )
    (comp (ref "A303")
      (value "JP1E")
      (footprint "eagle-import:JP1")
      (libsource (lib "eagle-import") (part "JP1E"))
    )
    (comp (ref "A304")
      (value "JP1E")
      (footprint "eagle-import:JP1")
      (libsource (lib "eagle-import") (part "JP1E"))
    )
    (comp (ref "A305")
      (value "JP1E")
      (footprint "eagle-import:JP1")
      (libsource (lib "eagle-import") (part "JP1E"))
    )
    (comp (ref "A306")
      (value "JP1E")
      (footprint "eagle-import:JP1")
      (libsource (lib "eagle-import") (part "JP1E"))
    )
    (comp (ref "A307")
      (value "JP1E")
      (footprint "eagle-import:JP1")
      (libsource (lib "eagle-import") (part "JP1E"))
    )
    (comp (ref "A308")
      (value "JP1E")
      (footprint "eagle-import:JP1")
      (libsource (lib "eagle-import") (part "JP1E"))
    )
    (comp (ref "A309")
      (value "JP1E")
      (footprint "eagle-import:JP1")
      (libsource (lib "eagle-import") (part "JP1E"))
    )
    (comp (ref "A310")
      (value "JP1E")
      (footprint "eagle-import:JP1")
      (libsource (lib "eagle-import") (part "JP1E"))
    )
    (comp (ref "A311")
      (value "JP1E")
      (footprint "eagle-import:JP1")
      (libsource (lib "eagle-import") (part "JP1E"))
    )
    (comp (ref "A312")
      (value "JP1E")
      (footprint "eagle-import:JP1")
      (libsource (lib "eagle-import") (part "JP1E"))
    )
    (comp (ref "A313")
      (value "JP1E")
      (footprint "eagle-import:JP1")
      (libsource (lib "eagle-import") (part "JP1E"))
    )
    (comp (ref "A314")
      (value "JP1E")
      (footprint "eagle-import:JP1")
      (libsource (lib "eagle-import") (part "JP1E"))
    )
    (comp (ref "A315")
      (value "JP1E")
      (footprint "eagle-import:JP1")
      (libsource (lib "eagle-import") (part "JP1E"))
    )
    (comp (ref "A316")
      (value "JP1E")
      (footprint "eagle-import:JP1")
      (libsource (lib "eagle-import") (part "JP1E"))
    )
    (comp (ref "A317")
      (value "JP1E")
      (footprint "eagle-import:JP1")
      (libsource (lib "eagle-import") (part "JP1E"))
    )
    (comp (ref "A318")
      (value "JP1E")
      (footprint "eagle-import:JP1")
      (libsource (lib "eagle-import") (part "JP1E"))
    )
    (comp (ref "A319")
      (value "JP1E")
      (footprint "eagle-import:JP1")
      (libsource (lib "eagle-import") (part "JP1E"))
    )
    (comp (ref "A320")
      (value "JP1E")
      (footprint "eagle-import:JP1")
      (libsource (lib "eagle-import") (part "JP1E"))
    )
    (comp (ref "A321")
      (value "JP1E")
      (footprint "eagle-import:JP1")
      (libsource (lib "eagle-import") (part "JP1E"))
    )
    (comp (ref "A322")
      (value "JP1E")
      (footprint "eagle-import:JP1")
      (libsource (lib "eagle-import") (part "JP1E"))
    )
    (comp (ref "A323")
      (value "JP1E")
      (footprint "eagle-import:JP1")
      (libsource (lib "eagle-import") (part "JP1E"))
    )
    (comp (ref "A324")
      (value "JP1E")
      (footprint "eagle-import:JP1")
      (libsource (lib "eagle-import") (part "JP1E"))
    )
    (comp (ref "A325")
      (value "JP1E")
      (footprint "eagle-import:JP1")
      (libsource (lib "eagle-import") (part "JP1E"))
    )
    (comp (ref "A326")
      (value "JP1E")
      (footprint "eagle-import:JP1")
      (libsource (lib "eagle-import") (part "JP1E"))
    )
    (comp (ref "A327")
      (value "JP1E")
      (footprint "eagle-import:JP1")
      (libsource (lib "eagle-import") (part "JP1E"))
    )
    (comp (ref "A328")
      (value "JP1E")
      (footprint "eagle-import:JP1")
      (libsource (lib "eagle-import") (part "JP1E"))
    )
    (comp (ref "A329")
      (value "JP1E")
      (footprint "eagle-import:JP1")
      (libsource (lib "eagle-import") (part "JP1E"))
    )
    (comp (ref "A330")
      (value "JP1E")
      (footprint "eagle-import:JP1")
      (libsource (lib "eagle-import") (part "JP1E"))
    )
    (comp (ref "A331")
      (value "JP1E")
      (footprint "eagle-import:JP1")
      (libsource (lib "eagle-import") (part "JP1E"))
    )
    (comp (ref "A332")
      (value "JP1E")
      (footprint "eagle-import:JP1")
      (libsource (lib "eagle-import") (part "JP1E"))
    )
    (comp (ref "A333")
      (value "JP1E")
      (footprint "eagle-import:JP1")
      (libsource (lib "eagle-import") (part "JP1E"))
    )
    (comp (ref "A334")
      (value "JP1E")
      (footprint "eagle-import:JP1")
      (libsource (lib "eagle-import") (part "JP1E"))
    )
    (comp (ref "A335")
      (value "JP1E")
      (footprint "eagle-import:JP1")
      (libsource (lib "eagle-import") (part "JP1E"))
    )
    (comp (ref "A336")
      (value "JP1E")
      (footprint "eagle-import:JP1")
      (libsource (lib "eagle-import") (part "JP1E"))
    )
    (comp (ref "A337")
      (value "JP1E")
      (footprint "eagle-import:JP1")
      (libsource (lib "eagle-import") (part "JP1E"))
    )
    (comp (ref "A338")
      (value "JP1E")
      (footprint "eagle-import:JP1")
      (libsource (lib "eagle-import") (part "JP1E"))
    )
    (comp (ref "A339")
      (value "JP1E")
      (footprint "eagle-import:JP1")
      (libsource (lib "eagle-import") (part "JP1E"))
    )
    (comp (ref "A340")
      (value "JP1E")
      (footprint "eagle-import:JP1")
      (libsource (lib "eagle-import") (part "JP1E"))
    )
    (comp (ref "A341")
      (value "JP1E")
      (footprint "eagle-import:JP1")
      (libsource (lib "eagle-import") (part "JP1E"))
    )
    (comp (ref "A342")
      (value "JP1E")
      (footprint "eagle-import:JP1")
      (libsource (lib "eagle-import") (part "JP1E"))
    )
    (comp (ref "A343")
      (value "JP1E")
      (footprint "eagle-import:JP1")
      (libsource (lib "eagle-import") (part "JP1E"))
    )
    (comp (ref "A344")
      (value "JP1E")
      (footprint "eagle-import:JP1")
      (libsource (lib "eagle-import") (part "JP1E"))
    )
    (comp (ref "A345")
      (value "JP1E")
      (footprint "eagle-import:JP1")
      (libsource (lib "eagle-import") (part "JP1E"))
    )
    (comp (ref "A346")
      (value "JP1E")
      (footprint "eagle-import:JP1")
      (libsource (lib "eagle-import") (part "JP1E"))
    )
    (comp (ref "A347")
      (value "JP1E")
      (footprint "eagle-import:JP1")
      (libsource (lib "eagle-import") (part "JP1E"))
    )
    (comp (ref "A348")
      (value "JP1E")
      (footprint "eagle-import:JP1")
      (libsource (lib "eagle-import") (part "JP1E"))
    )
    (comp (ref "A349")
      (value "JP1E")
      (footprint "eagle-import:JP1")
      (libsource (lib "eagle-import") (part "JP1E"))
    )
    (comp (ref "A350")
      (value "JP1E")
      (footprint "eagle-import:JP1")
      (libsource (lib "eagle-import") (part "JP1E"))
    )
    (comp (ref "A351")
      (value "JP1E")
      (footprint "eagle-import:JP1")
      (libsource (lib "eagle-import") (part "JP1E"))
    )
    (comp (ref "A352")
      (value "JP1E")
      (footprint "eagle-import:JP1")
      (libsource (lib "eagle-import") (part "JP1E"))
    )
    (comp (ref "A353")
      (value "JP1E")
      (footprint "eagle-import:JP1")
      (libsource (lib "eagle-import") (part "JP1E"))
    )
    (comp (ref "A354")
      (value "JP1E")
      (footprint "eagle-import:JP1")
      (libsource (lib "eagle-import") (part "JP1E"))
    )
    (comp (ref "A355")
      (value "JP1E")
      (footprint "eagle-import:JP1")
      (libsource (lib "eagle-import") (part "JP1E"))
    )
    (comp (ref "A356")
      (value "JP1E")
      (footprint "eagle-import:JP1")
      (libsource (lib "eagle-import") (part "JP1E"))
    )
    (comp (ref "A357")
      (value "JP1E")
      (footprint "eagle-import:JP1")
      (libsource (lib "eagle-import") (part "JP1E"))
    )
    (comp (ref "A358")
      (value "JP1E")
      (footprint "eagle-import:JP1")
      (libsource (lib "eagle-import") (part "JP1E"))
    )
    (comp (ref "A359")
      (value "JP1E")
      (footprint "eagle-import:JP1")
      (libsource (lib "eagle-import") (part "JP1E"))
    )
    (comp (ref "A360")
      (value "JP1E")
      (footprint "eagle-import:JP1")
      (libsource (lib "eagle-import") (part "JP1E"))
    )
    (comp (ref "A361")
      (value "JP1E")
      (footprint "eagle-import:JP1")
      (libsource (lib "eagle-import") (part "JP1E"))
    )
    (comp (ref "A362")
      (value "JP1E")
      (footprint "eagle-import:JP1")
      (libsource (lib "eagle-import") (part "JP1E"))
    )
    (comp (ref "A363")
      (value "JP1E")
      (footprint "eagle-import:JP1")
      (libsource (lib "eagle-import") (part "JP1E"))
    )
    (comp (ref "A364")
      (value "JP1E")
      (footprint "eagle-import:JP1")
      (libsource (lib "eagle-import") (part "JP1E"))
    )
    (comp (ref "A365")
      (value "JP1E")
      (footprint "eagle-import:JP1")
      (libsource (lib "eagle-import") (part "JP1E"))
    )
    (comp (ref "A366")
      (value "JP1E")
      (footprint "eagle-import:JP1")
      (libsource (lib "eagle-import") (part "JP1E"))
    )
    (comp (ref "A367")
      (value "JP1E")
      (footprint "eagle-import:JP1")
      (libsource (lib "eagle-import") (part "JP1E"))
    )
    (comp (ref "A368")
      (value "JP1E")
      (footprint "eagle-import:JP1")
      (libsource (lib "eagle-import") (part "JP1E"))
    )
    (comp (ref "A369")
      (value "JP1E")
      (footprint "eagle-import:JP1")
      (libsource (lib "eagle-import") (part "JP1E"))
    )
    (comp (ref "A370")
      (value "JP1E")
      (footprint "eagle-import:JP1")
      (libsource (lib "eagle-import") (part "JP1E"))
    )
    (comp (ref "A371")
      (value "JP1E")
      (footprint "eagle-import:JP1")
      (libsource (lib "eagle-import") (part "JP1E"))
    )
    (comp (ref "A372")
      (value "JP1E")
      (footprint "eagle-import:JP1")
      (libsource (lib "eagle-import") (part "JP1E"))
    )
    (comp (ref "A373")
      (value "JP1E")
      (footprint "eagle-import:JP1")
      (libsource (lib "eagle-import") (part "JP1E"))
    )
    (comp (ref "A374")
      (value "JP1E")
      (footprint "eagle-import:JP1")
      (libsource (lib "eagle-import") (part "JP1E"))
    )
    (comp (ref "A375")
      (value "JP1E")
      (footprint "eagle-import:JP1")
      (libsource (lib "eagle-import") (part "JP1E"))
    )
    (comp (ref "A376")
      (value "JP1E")
      (footprint "eagle-import:JP1")
      (libsource (lib "eagle-import") (part "JP1E"))
    )
    (comp (ref "A377")
      (value "JP1E")
      (footprint "eagle-import:JP1")
      (libsource (lib "eagle-import") (part "JP1E"))
    )
    (comp (ref "A378")
      (value "JP1E")
      (footprint "eagle-import:JP1")
      (libsource (lib "eagle-import") (part "JP1E"))
    )
    (comp (ref "A379")
      (value "JP1E")
      (footprint "eagle-import:JP1")
      (libsource (lib "eagle-import") (part "JP1E"))
    )
    (comp (ref "A380")
      (value "JP1E")
      (footprint "eagle-import:JP1")
      (libsource (lib "eagle-import") (part "JP1E"))
    )
    (comp (ref "A381")
      (value "JP1E")
      (footprint "eagle-import:JP1")
      (libsource (lib "eagle-import") (part "JP1E"))
    )
    (comp (ref "A382")
      (value "JP1E")
      (footprint "eagle-import:JP1")
      (libsource (lib "eagle-import") (part "JP1E"))
    )
    (comp (ref "A383")
      (value "JP1E")
      (footprint "eagle-import:JP1")
      (libsource (lib "eagle-import") (part "JP1E"))
    )
    (comp (ref "A384")
      (value "JP1E")
      (footprint "eagle-import:JP1")
      (libsource (lib "eagle-import") (part "JP1E"))
    )
    (comp (ref "A385")
      (value "JP1E")
      (footprint "eagle-import:JP1")
      (libsource (lib "eagle-import") (part "JP1E"))
    )
    (comp (ref "A386")
      (value "JP1E")
      (footprint "eagle-import:JP1")
      (libsource (lib "eagle-import") (part "JP1E"))
    )
    (comp (ref "A387")
      (value "JP1E")
      (footprint "eagle-import:JP1")
      (libsource (lib "eagle-import") (part "JP1E"))
    )
    (comp (ref "A388")
      (value "JP1E")
      (footprint "eagle-import:JP1")
      (libsource (lib "eagle-import") (part "JP1E"))
    )
    (comp (ref "A389")
      (value "JP1E")
      (footprint "eagle-import:JP1")
      (libsource (lib "eagle-import") (part "JP1E"))
    )
    (comp (ref "A390")
      (value "JP1E")
      (footprint "eagle-import:JP1")
      (libsource (lib "eagle-import") (part "JP1E"))
    )
    (comp (ref "A391")
      (value "JP1E")
      (footprint "eagle-import:JP1")
      (libsource (lib "eagle-import") (part "JP1E"))
    )
    (comp (ref "A392")
      (value "JP1E")
      (footprint "eagle-import:JP1")
      (libsource (lib "eagle-import") (part "JP1E"))
    )
    (comp (ref "A393")
      (value "JP1E")
      (footprint "eagle-import:JP1")
      (libsource (lib "eagle-import") (part "JP1E"))
    )
    (comp (ref "A394")
      (value "JP1E")
      (footprint "eagle-import:JP1")
      (libsource (lib "eagle-import") (part "JP1E"))
    )
    (comp (ref "A395")
      (value "JP1E")
      (footprint "eagle-import:JP1")
      (libsource (lib "eagle-import") (part "JP1E"))
    )
    (comp (ref "A396")
      (value "JP1E")
      (footprint "eagle-import:JP1")
      (libsource (lib "eagle-import") (part "JP1E"))
    )
    (comp (ref "A397")
      (value "JP1E")
      (footprint "eagle-import:JP1")
      (libsource (lib "eagle-import") (part "JP1E"))
    )
    (comp (ref "A398")
      (value "JP1E")
      (footprint "eagle-import:JP1")
      (libsource (lib "eagle-import") (part "JP1E"))
    )
    (comp (ref "A399")
      (value "JP1E")
      (footprint "eagle-import:JP1")
      (libsource (lib "eagle-import") (part "JP1E"))
    )
    (comp (ref "A400")
      (value "JP1E")
      (footprint "eagle-import:JP1")
      (libsource (lib "eagle-import") (part "JP1E"))
    )
    (comp (ref "A401")
      (value "JP1E")
      (footprint "eagle-import:JP1")
      (libsource (lib "eagle-import") (part "JP1E"))
    )
    (comp (ref "A402")
      (value "JP1E")
      (footprint "eagle-import:JP1")
      (libsource (lib "eagle-import") (part "JP1E"))
    )
    (comp (ref "A403")
      (value "JP1E")
      (footprint "eagle-import:JP1")
      (libsource (lib "eagle-import") (part "JP1E"))
    )
    (comp (ref "A404")
      (value "JP1E")
      (footprint "eagle-import:JP1")
      (libsource (lib "eagle-import") (part "JP1E"))
    )
    (comp (ref "A405")
      (value "JP1E")
      (footprint "eagle-import:JP1")
      (libsource (lib "eagle-import") (part "JP1E"))
    )
    (comp (ref "A406")
      (value "JP1E")
      (footprint "eagle-import:JP1")
      (libsource (lib "eagle-import") (part "JP1E"))
    )
    (comp (ref "A407")
      (value "JP1E")
      (footprint "eagle-import:JP1")
      (libsource (lib "eagle-import") (part "JP1E"))
    )
    (comp (ref "A408")
      (value "JP1E")
      (footprint "eagle-import:JP1")
      (libsource (lib "eagle-import") (part "JP1E"))
    )
    (comp (ref "A409")
      (value "JP1E")
      (footprint "eagle-import:JP1")
      (libsource (lib "eagle-import") (part "JP1E"))
    )
    (comp (ref "A410")
      (value "JP1E")
      (footprint "eagle-import:JP1")
      (libsource (lib "eagle-import") (part "JP1E"))
    )
    (comp (ref "A411")
      (value "JP1E")
      (footprint "eagle-import:JP1")
      (libsource (lib "eagle-import") (part "JP1E"))
    )
    (comp (ref "A412")
      (value "JP1E")
      (footprint "eagle-import:JP1")
      (libsource (lib "eagle-import") (part "JP1E"))
    )
    (comp (ref "A413")
      (value "JP1E")
      (footprint "eagle-import:JP1")
      (libsource (lib "eagle-import") (part "JP1E"))
    )
    (comp (ref "A414")
      (value "JP1E")
      (footprint "eagle-import:JP1")
      (libsource (lib "eagle-import") (part "JP1E"))
    )
    (comp (ref "A415")
      (value "JP1E")
      (footprint "eagle-import:JP1")
      (libsource (lib "eagle-import") (part "JP1E"))
    )
    (comp (ref "A416")
      (value "JP1E")
      (footprint "eagle-import:JP1")
      (libsource (lib "eagle-import") (part "JP1E"))
    )
    (comp (ref "A417")
      (value "JP1E")
      (footprint "eagle-import:JP1")
      (libsource (lib "eagle-import") (part "JP1E"))
    )
    (comp (ref "A418")
      (value "JP1E")
      (footprint "eagle-import:JP1")
      (libsource (lib "eagle-import") (part "JP1E"))
    )
    (comp (ref "A419")
      (value "JP1E")
      (footprint "eagle-import:JP1")
      (libsource (lib "eagle-import") (part "JP1E"))
    )
    (comp (ref "A420")
      (value "JP1E")
      (footprint "eagle-import:JP1")
      (libsource (lib "eagle-import") (part "JP1E"))
    )
    (comp (ref "A421")
      (value "JP1E")
      (footprint "eagle-import:JP1")
      (libsource (lib "eagle-import") (part "JP1E"))
    )
    (comp (ref "A422")
      (value "JP1E")
      (footprint "eagle-import:JP1")
      (libsource (lib "eagle-import") (part "JP1E"))
    )
    (comp (ref "A423")
      (value "JP1E")
      (footprint "eagle-import:JP1")
      (libsource (lib "eagle-import") (part "JP1E"))
    )
    (comp (ref "A424")
      (value "JP1E")
      (footprint "eagle-import:JP1")
      (libsource (lib "eagle-import") (part "JP1E"))
    )
    (comp (ref "A425")
      (value "JP1E")
      (footprint "eagle-import:JP1")
      (libsource (lib "eagle-import") (part "JP1E"))
    )
    (comp (ref "A426")
      (value "JP1E")
      (footprint "eagle-import:JP1")
      (libsource (lib "eagle-import") (part "JP1E"))
    )
    (comp (ref "A427")
      (value "JP1E")
      (footprint "eagle-import:JP1")
      (libsource (lib "eagle-import") (part "JP1E"))
    )
    (comp (ref "A428")
      (value "JP1E")
      (footprint "eagle-import:JP1")
      (libsource (lib "eagle-import") (part "JP1E"))
    )
    (comp (ref "A429")
      (value "JP1E")
      (footprint "eagle-import:JP1")
      (libsource (lib "eagle-import") (part "JP1E"))
    )
    (comp (ref "A430")
      (value "JP1E")
      (footprint "eagle-import:JP1")
      (libsource (lib "eagle-import") (part "JP1E"))
    )
    (comp (ref "A431")
      (value "JP1E")
      (footprint "eagle-import:JP1")
      (libsource (lib "eagle-import") (part "JP1E"))
    )
    (comp (ref "A432")
      (value "JP1E")
      (footprint "eagle-import:JP1")
      (libsource (lib "eagle-import") (part "JP1E"))
    )
    (comp (ref "A433")
      (value "JP1E")
      (footprint "eagle-import:JP1")
      (libsource (lib "eagle-import") (part "JP1E"))
    )
    (comp (ref "A434")
      (value "JP1E")
      (footprint "eagle-import:JP1")
      (libsource (lib "eagle-import") (part "JP1E"))
    )
    (comp (ref "A435")
      (value "JP1E")
      (footprint "eagle-import:JP1")
      (libsource (lib "eagle-import") (part "JP1E"))
    )
    (comp (ref "A436")
      (value "JP1E")
      (footprint "eagle-import:JP1")
      (libsource (lib "eagle-import") (part "JP1E"))
    )
    (comp (ref "A437")
      (value "JP1E")
      (footprint "eagle-import:JP1")
      (libsource (lib "eagle-import") (part "JP1E"))
    )
    (comp (ref "A438")
      (value "JP1E")
      (footprint "eagle-import:JP1")
      (libsource (lib "eagle-import") (part "JP1E"))
    )
    (comp (ref "A439")
      (value "JP1E")
      (footprint "eagle-import:JP1")
      (libsource (lib "eagle-import") (part "JP1E"))
    )
    (comp (ref "A440")
      (value "JP1E")
      (footprint "eagle-import:JP1")
      (libsource (lib "eagle-import") (part "JP1E"))
    )
    (comp (ref "A441")
      (value "JP1E")
      (footprint "eagle-import:JP1")
      (libsource (lib "eagle-import") (part "JP1E"))
    )
    (comp (ref "A442")
      (value "JP1E")
      (footprint "eagle-import:JP1")
      (libsource (lib "eagle-import") (part "JP1E"))
    )
    (comp (ref "A443")
      (value "JP1E")
      (footprint "eagle-import:JP1")
      (libsource (lib "eagle-import") (part "JP1E"))
    )
    (comp (ref "A444")
      (value "JP1E")
      (footprint "eagle-import:JP1")
      (libsource (lib "eagle-import") (part "JP1E"))
    )
    (comp (ref "A445")
      (value "JP1E")
      (footprint "eagle-import:JP1")
      (libsource (lib "eagle-import") (part "JP1E"))
    )
    (comp (ref "A446")
      (value "JP1E")
      (footprint "eagle-import:JP1")
      (libsource (lib "eagle-import") (part "JP1E"))
    )
    (comp (ref "A447")
      (value "JP1E")
      (footprint "eagle-import:JP1")
      (libsource (lib "eagle-import") (part "JP1E"))
    )
    (comp (ref "A448")
      (value "JP1E")
      (footprint "eagle-import:JP1")
      (libsource (lib "eagle-import") (part "JP1E"))
    )
    (comp (ref "GND1")
      (value "JP1E")
      (footprint "eagle-import:JP1")
      (libsource (lib "eagle-import") (part "JP1E"))
    )
    (comp (ref "GND2")
      (value "JP1E")
      (footprint "eagle-import:JP1")
      (libsource (lib "eagle-import") (part "JP1E"))
    )
    (comp (ref "GND3")
      (value "JP1E")
      (footprint "eagle-import:JP1")
      (libsource (lib "eagle-import") (part "JP1E"))
    )
    (comp (ref "GND4")
      (value "JP1E")
      (footprint "eagle-import:JP1")
      (libsource (lib "eagle-import") (part "JP1E"))
    )
    (comp (ref "GND5")
      (value "JP1E")
      (footprint "eagle-import:JP1")
      (libsource (lib "eagle-import") (part "JP1E"))
    )
    (comp (ref "GND6")
      (value "JP1E")
      (footprint "eagle-import:JP1")
      (libsource (lib "eagle-import") (part "JP1E"))
    )
    (comp (ref "GND7")
      (value "JP1E")
      (footprint "eagle-import:JP1")
      (libsource (lib "eagle-import") (part "JP1E"))
    )
    (comp (ref "GND8")
      (value "JP1E")
      (footprint "eagle-import:JP1")
      (libsource (lib "eagle-import") (part "JP1E"))
    )
    (comp (ref "GND9")
      (value "JP1E")
      (footprint "eagle-import:JP1")
      (libsource (lib "eagle-import") (part "JP1E"))
    )
    (comp (ref "GND10")
      (value "JP1E")
      (footprint "eagle-import:JP1")
      (libsource (lib "eagle-import") (part "JP1E"))
    )
    (comp (ref "GND11")
      (value "JP1E")
      (footprint "eagle-import:JP1")
      (libsource (lib "eagle-import") (part "JP1E"))
    )
    (comp (ref "GND12")
      (value "JP1E")
      (footprint "eagle-import:JP1")
      (libsource (lib "eagle-import") (part "JP1E"))
    )
    (comp (ref "GND13")
      (value "JP1E")
      (footprint "eagle-import:JP1")
      (libsource (lib "eagle-import") (part "JP1E"))
    )
    (comp (ref "GND14")
      (value "JP1E")
      (footprint "eagle-import:JP1")
      (libsource (lib "eagle-import") (part "JP1E"))
    )
    (comp (ref "GND15")
      (value "JP1E")
      (footprint "eagle-import:JP1")
      (libsource (lib "eagle-import") (part "JP1E"))
    )
    (comp (ref "GND16")
      (value "JP1E")
      (footprint "eagle-import:JP1")
      (libsource (lib "eagle-import") (part "JP1E"))
    )
    (comp (ref "GND17")
      (value "JP1E")
      (footprint "eagle-import:JP1")
      (libsource (lib "eagle-import") (part "JP1E"))
    )
    (comp (ref "GND18")
      (value "JP1E")
      (footprint "eagle-import:JP1")
      (libsource (lib "eagle-import") (part "JP1E"))
    )
    (comp (ref "GND19")
      (value "JP1E")
      (footprint "eagle-import:JP1")
      (libsource (lib "eagle-import") (part "JP1E"))
    )
    (comp (ref "GND20")
      (value "JP1E")
      (footprint "eagle-import:JP1")
      (libsource (lib "eagle-import") (part "JP1E"))
    )
    (comp (ref "GND21")
      (value "JP1E")
      (footprint "eagle-import:JP1")
      (libsource (lib "eagle-import") (part "JP1E"))
    )
    (comp (ref "GND22")
      (value "JP1E")
      (footprint "eagle-import:JP1")
      (libsource (lib "eagle-import") (part "JP1E"))
    )
    (comp (ref "GND23")
      (value "JP1E")
      (footprint "eagle-import:JP1")
      (libsource (lib "eagle-import") (part "JP1E"))
    )
    (comp (ref "GND24")
      (value "JP1E")
      (footprint "eagle-import:JP1")
      (libsource (lib "eagle-import") (part "JP1E"))
    )
    (comp (ref "GND25")
      (value "JP1E")
      (footprint "eagle-import:JP1")
      (libsource (lib "eagle-import") (part "JP1E"))
    )
    (comp (ref "GND26")
      (value "JP1E")
      (footprint "eagle-import:JP1")
      (libsource (lib "eagle-import") (part "JP1E"))
    )
    (comp (ref "GND27")
      (value "JP1E")
      (footprint "eagle-import:JP1")
      (libsource (lib "eagle-import") (part "JP1E"))
    )
    (comp (ref "GND28")
      (value "JP1E")
      (footprint "eagle-import:JP1")
      (libsource (lib "eagle-import") (part "JP1E"))
    )
    (comp (ref "GND29")
      (value "JP1E")
      (footprint "eagle-import:JP1")
      (libsource (lib "eagle-import") (part "JP1E"))
    )
    (comp (ref "GND30")
      (value "JP1E")
      (footprint "eagle-import:JP1")
      (libsource (lib "eagle-import") (part "JP1E"))
    )
    (comp (ref "GND31")
      (value "JP1E")
      (footprint "eagle-import:JP1")
      (libsource (lib "eagle-import") (part "JP1E"))
    )
    (comp (ref "GND32")
      (value "JP1E")
      (footprint "eagle-import:JP1")
      (libsource (lib "eagle-import") (part "JP1E"))
    )
    (comp (ref "GND33")
      (value "JP1E")
      (footprint "eagle-import:JP1")
      (libsource (lib "eagle-import") (part "JP1E"))
    )
    (comp (ref "GND34")
      (value "JP1E")
      (footprint "eagle-import:JP1")
      (libsource (lib "eagle-import") (part "JP1E"))
    )
    (comp (ref "GND35")
      (value "JP1E")
      (footprint "eagle-import:JP1")
      (libsource (lib "eagle-import") (part "JP1E"))
    )
    (comp (ref "GND36")
      (value "JP1E")
      (footprint "eagle-import:JP1")
      (libsource (lib "eagle-import") (part "JP1E"))
    )
    (comp (ref "GND37")
      (value "JP1E")
      (footprint "eagle-import:JP1")
      (libsource (lib "eagle-import") (part "JP1E"))
    )
    (comp (ref "GND38")
      (value "JP1E")
      (footprint "eagle-import:JP1")
      (libsource (lib "eagle-import") (part "JP1E"))
    )
    (comp (ref "GND39")
      (value "JP1E")
      (footprint "eagle-import:JP1")
      (libsource (lib "eagle-import") (part "JP1E"))
    )
    (comp (ref "GND40")
      (value "JP1E")
      (footprint "eagle-import:JP1")
      (libsource (lib "eagle-import") (part "JP1E"))
    )
    (comp (ref "GND41")
      (value "JP1E")
      (footprint "eagle-import:JP1")
      (libsource (lib "eagle-import") (part "JP1E"))
    )
    (comp (ref "GND42")
      (value "JP1E")
      (footprint "eagle-import:JP1")
      (libsource (lib "eagle-import") (part "JP1E"))
    )
    (comp (ref "GND43")
      (value "JP1E")
      (footprint "eagle-import:JP1")
      (libsource (lib "eagle-import") (part "JP1E"))
    )
    (comp (ref "GND44")
      (value "JP1E")
      (footprint "eagle-import:JP1")
      (libsource (lib "eagle-import") (part "JP1E"))
    )
    (comp (ref "IC9")
      (value "DIL16")
      (footprint "eagle-import:DIL16")
      (libsource (lib "eagle-import") (part "DIL16"))
    )
    (comp (ref "IC10")
      (value "DIL16")
      (footprint "eagle-import:DIL16")
      (libsource (lib "eagle-import") (part "DIL16"))
    )
    (comp (ref "IC11")
      (value "DIL16")
      (footprint "eagle-import:DIL16")
      (libsource (lib "eagle-import") (part "DIL16"))
    )
    (comp (ref "IC12")
      (value "DIL16")
      (footprint "eagle-import:DIL16")
      (libsource (lib "eagle-import") (part "DIL16"))
    )
    (comp (ref "IC13")
      (value "DIL16")
      (footprint "eagle-import:DIL16")
      (libsource (lib "eagle-import") (part "DIL16"))
    )
    (comp (ref "IC14")
      (value "DIL16")
      (footprint "eagle-import:DIL16")
      (libsource (lib "eagle-import") (part "DIL16"))
    )
    (comp (ref "IC15")
      (value "DIL16")
      (footprint "eagle-import:DIL16")
      (libsource (lib "eagle-import") (part "DIL16"))
    )
    (comp (ref "IC16")
      (value "DIL16")
      (footprint "eagle-import:DIL16")
      (libsource (lib "eagle-import") (part "DIL16"))
    )
    (comp (ref "IC17")
      (value "DIL16")
      (footprint "eagle-import:DIL16")
      (libsource (lib "eagle-import") (part "DIL16"))
    )
    (comp (ref "IC18")
      (value "DIL16")
      (footprint "eagle-import:DIL16")
      (libsource (lib "eagle-import") (part "DIL16"))
    )
    (comp (ref "IC19")
      (value "DIL16")
      (footprint "eagle-import:DIL16")
      (libsource (lib "eagle-import") (part "DIL16"))
    )
    (comp (ref "IC20")
      (value "DIL16")
      (footprint "eagle-import:DIL16")
      (libsource (lib "eagle-import") (part "DIL16"))
    )
    (comp (ref "IC21")
      (value "DIL16")
      (footprint "eagle-import:DIL16")
      (libsource (lib "eagle-import") (part "DIL16"))
    )
    (comp (ref "IC22")
      (value "DIL16")
      (footprint "eagle-import:DIL16")
      (libsource (lib "eagle-import") (part "DIL16"))
    )
    (comp (ref "IC23")
      (value "DIL16")
      (footprint "eagle-import:DIL16")
      (libsource (lib "eagle-import") (part "DIL16"))
    )
    (comp (ref "IC24")
      (value "DIL16")
      (footprint "eagle-import:DIL16")
      (libsource (lib "eagle-import") (part "DIL16"))
    )
    (comp (ref "IC25")
      (value "DIL16")
      (footprint "eagle-import:DIL16")
      (libsource (lib "eagle-import") (part "DIL16"))
    )
    (comp (ref "IC26")
      (value "DIL16")
      (footprint "eagle-import:DIL16")
      (libsource (lib "eagle-import") (part "DIL16"))
    )
    (comp (ref "IC27")
      (value "DIL16")
      (footprint "eagle-import:DIL16")
      (libsource (lib "eagle-import") (part "DIL16"))
    )
    (comp (ref "IC28")
      (value "DIL16")
      (footprint "eagle-import:DIL16")
      (libsource (lib "eagle-import") (part "DIL16"))
    )
    (comp (ref "IC29")
      (value "DIL16")
      (footprint "eagle-import:DIL16")
      (libsource (lib "eagle-import") (part "DIL16"))
    )
    (comp (ref "IC30")
      (value "DIL16")
      (footprint "eagle-import:DIL16")
      (libsource (lib "eagle-import") (part "DIL16"))
    )
    (comp (ref "IC31")
      (value "DIL16")
      (footprint "eagle-import:DIL16")
      (libsource (lib "eagle-import") (part "DIL16"))
    )
    (comp (ref "IC32")
      (value "DIL16")
      (footprint "eagle-import:DIL16")
      (libsource (lib "eagle-import") (part "DIL16"))
    )
    (comp (ref "IC33")
      (value "DIL16")
      (footprint "eagle-import:DIL16")
      (libsource (lib "eagle-import") (part "DIL16"))
    )
    (comp (ref "IC34")
      (value "DIL16")
      (footprint "eagle-import:DIL16")
      (libsource (lib "eagle-import") (part "DIL16"))
    )
    (comp (ref "IC35")
      (value "DIL16")
      (footprint "eagle-import:DIL16")
      (libsource (lib "eagle-import") (part "DIL16"))
    )
    (comp (ref "IC36")
      (value "DIL16")
      (footprint "eagle-import:DIL16")
      (libsource (lib "eagle-import") (part "DIL16"))
    )
    (comp (ref "VCC1")
      (value "JP1E")
      (footprint "eagle-import:JP1")
      (libsource (lib "eagle-import") (part "JP1E"))
    )
    (comp (ref "VCC2")
      (value "JP1E")
      (footprint "eagle-import:JP1")
      (libsource (lib "eagle-import") (part "JP1E"))
    )
    (comp (ref "VCC3")
      (value "JP1E")
      (footprint "eagle-import:JP1")
      (libsource (lib "eagle-import") (part "JP1E"))
    )
    (comp (ref "VCC4")
      (value "JP1E")
      (footprint "eagle-import:JP1")
      (libsource (lib "eagle-import") (part "JP1E"))
    )
    (comp (ref "VCC5")
      (value "JP1E")
      (footprint "eagle-import:JP1")
      (libsource (lib "eagle-import") (part "JP1E"))
    )
    (comp (ref "VCC6")
      (value "JP1E")
      (footprint "eagle-import:JP1")
      (libsource (lib "eagle-import") (part "JP1E"))
    )
    (comp (ref "VCC7")
      (value "JP1E")
      (footprint "eagle-import:JP1")
      (libsource (lib "eagle-import") (part "JP1E"))
    )
    (comp (ref "VCC8")
      (value "JP1E")
      (footprint "eagle-import:JP1")
      (libsource (lib "eagle-import") (part "JP1E"))
    )
    (comp (ref "VCC9")
      (value "JP1E")
      (footprint "eagle-import:JP1")
      (libsource (lib "eagle-import") (part "JP1E"))
    )
    (comp (ref "VCC10")
      (value "JP1E")
      (footprint "eagle-import:JP1")
      (libsource (lib "eagle-import") (part "JP1E"))
    )
    (comp (ref "VCC11")
      (value "JP1E")
      (footprint "eagle-import:JP1")
      (libsource (lib "eagle-import") (part "JP1E"))
    )
    (comp (ref "VCC12")
      (value "JP1E")
      (footprint "eagle-import:JP1")
      (libsource (lib "eagle-import") (part "JP1E"))
    )
    (comp (ref "VCC13")
      (value "JP1E")
      (footprint "eagle-import:JP1")
      (libsource (lib "eagle-import") (part "JP1E"))
    )
    (comp (ref "VCC14")
      (value "JP1E")
      (footprint "eagle-import:JP1")
      (libsource (lib "eagle-import") (part "JP1E"))
    )
    (comp (ref "VCC15")
      (value "JP1E")
      (footprint "eagle-import:JP1")
      (libsource (lib "eagle-import") (part "JP1E"))
    )
    (comp (ref "VCC16")
      (value "JP1E")
      (footprint "eagle-import:JP1")
      (libsource (lib "eagle-import") (part "JP1E"))
    )
    (comp (ref "VCC17")
      (value "JP1E")
      (footprint "eagle-import:JP1")
      (libsource (lib "eagle-import") (part "JP1E"))
    )
    (comp (ref "VCC18")
      (value "JP1E")
      (footprint "eagle-import:JP1")
      (libsource (lib "eagle-import") (part "JP1E"))
    )
    (comp (ref "VCC19")
      (value "JP1E")
      (footprint "eagle-import:JP1")
      (libsource (lib "eagle-import") (part "JP1E"))
    )
    (comp (ref "VCC20")
      (value "JP1E")
      (footprint "eagle-import:JP1")
      (libsource (lib "eagle-import") (part "JP1E"))
    )
    (comp (ref "VCC21")
      (value "JP1E")
      (footprint "eagle-import:JP1")
      (libsource (lib "eagle-import") (part "JP1E"))
    )
    (comp (ref "VCC22")
      (value "JP1E")
      (footprint "eagle-import:JP1")
      (libsource (lib "eagle-import") (part "JP1E"))
    )
    (comp (ref "VCC23")
      (value "JP1E")
      (footprint "eagle-import:JP1")
      (libsource (lib "eagle-import") (part "JP1E"))
    )
    (comp (ref "VCC24")
      (value "JP1E")
      (footprint "eagle-import:JP1")
      (libsource (lib "eagle-import") (part "JP1E"))
    )
    (comp (ref "VCC25")
      (value "JP1E")
      (footprint "eagle-import:JP1")
      (libsource (lib "eagle-import") (part "JP1E"))
    )
    (comp (ref "VCC26")
      (value "JP1E")
      (footprint "eagle-import:JP1")
      (libsource (lib "eagle-import") (part "JP1E"))
    )
    (comp (ref "VCC27")
      (value "JP1E")
      (footprint "eagle-import:JP1")
      (libsource (lib "eagle-import") (part "JP1E"))
    )
    (comp (ref "VCC28")
      (value "JP1E")
      (footprint "eagle-import:JP1")
      (libsource (lib "eagle-import") (part "JP1E"))
    )
    (comp (ref "VCC29")
      (value "JP1E")
      (footprint "eagle-import:JP1")
      (libsource (lib "eagle-import") (part "JP1E"))
    )
    (comp (ref "VCC30")
      (value "JP1E")
      (footprint "eagle-import:JP1")
      (libsource (lib "eagle-import") (part "JP1E"))
    )
    (comp (ref "VCC31")
      (value "JP1E")
      (footprint "eagle-import:JP1")
      (libsource (lib "eagle-import") (part "JP1E"))
    )
    (comp (ref "VCC32")
      (value "JP1E")
      (footprint "eagle-import:JP1")
      (libsource (lib "eagle-import") (part "JP1E"))
    )
    (comp (ref "VCC33")
      (value "JP1E")
      (footprint "eagle-import:JP1")
      (libsource (lib "eagle-import") (part "JP1E"))
    )
    (comp (ref "VCC34")
      (value "JP1E")
      (footprint "eagle-import:JP1")
      (libsource (lib "eagle-import") (part "JP1E"))
    )
    (comp (ref "VCC35")
      (value "JP1E")
      (footprint "eagle-import:JP1")
      (libsource (lib "eagle-import") (part "JP1E"))
    )
    (comp (ref "VCC36")
      (value "JP1E")
      (footprint "eagle-import:JP1")
      (libsource (lib "eagle-import") (part "JP1E"))
    )
    (comp (ref "VCC37")
      (value "JP1E")
      (footprint "eagle-import:JP1")
      (libsource (lib "eagle-import") (part "JP1E"))
    )
    (comp (ref "VCC38")
      (value "JP1E")
      (footprint "eagle-import:JP1")
      (libsource (lib "eagle-import") (part "JP1E"))
    )
    (comp (ref "VCC39")
      (value "JP1E")
      (footprint "eagle-import:JP1")
      (libsource (lib "eagle-import") (part "JP1E"))
    )
    (comp (ref "VCC40")
      (value "JP1E")
      (footprint "eagle-import:JP1")
      (libsource (lib "eagle-import") (part "JP1E"))
    )
    (comp (ref "VCC41")
      (value "JP1E")
      (footprint "eagle-import:JP1")
      (libsource (lib "eagle-import") (part "JP1E"))
    )
    (comp (ref "VCC42")
      (value "JP1E")
      (footprint "eagle-import:JP1")
      (libsource (lib "eagle-import") (part "JP1E"))
    )
    (comp (ref "VCC43")
      (value "JP1E")
      (footprint "eagle-import:JP1")
      (libsource (lib "eagle-import") (part "JP1E"))
    )
    (comp (ref "VCC44")
      (value "JP1E")
      (footprint "eagle-import:JP1")
      (libsource (lib "eagle-import") (part "JP1E"))
    )
    (comp (ref "B1")
      (value "CR2032")
      (footprint "eagle-import:B2430UNI")
      (libsource (lib "eagle-import") (part "B2430UNI"))
    )
    (comp (ref "C1")
      (value "22uF")
      (footprint "eagle-import:C050-025X075")
      (libsource (lib "eagle-import") (part "C-US050-025X075"))
    )
    (comp (ref "C2")
      (value "200pF")
      (footprint "eagle-import:C050-025X075")
      (libsource (lib "eagle-import") (part "C-US050-025X075"))
    )
    (comp (ref "C3")
      (value "0.1uF")
      (footprint "eagle-import:C050-025X075")
      (libsource (lib "eagle-import") (part "C-US050-025X075"))
    )
    (comp (ref "C4")
      (value "0.1uF")
      (footprint "eagle-import:C050-025X075")
      (libsource (lib "eagle-import") (part "C-US050-025X075"))
    )
    (comp (ref "C5")
      (value "0.1uF")
      (footprint "eagle-import:C050-025X075")
      (libsource (lib "eagle-import") (part "C-US050-025X075"))
    )
    (comp (ref "C6")
      (value "0.1uF")
      (footprint "eagle-import:C050-025X075")
      (libsource (lib "eagle-import") (part "C-US050-025X075"))
    )
    (comp (ref "C7")
      (value "0.1uF")
      (footprint "eagle-import:C050-025X075")
      (libsource (lib "eagle-import") (part "C-US050-025X075"))
    )
    (comp (ref "C8")
      (value "0.1uF")
      (footprint "eagle-import:C050-025X075")
      (libsource (lib "eagle-import") (part "C-US050-025X075"))
    )
    (comp (ref "C9")
      (value "0.1uF")
      (footprint "eagle-import:C050-025X075")
      (libsource (lib "eagle-import") (part "C-US050-025X075"))
    )
    (comp (ref "C10")
      (value "100uF")
      (footprint "eagle-import:E12-8")
      (libsource (lib "eagle-import") (part "CPOL-USE20-8AXIAL"))
    )
    (comp (ref "D1")
      (value "BAT19")
      (footprint "eagle-import:DO35-10")
      (libsource (lib "eagle-import") (part "BAT19"))
    )
    (comp (ref "D2")
      (value "BAT19")
      (footprint "eagle-import:DO35-10")
      (libsource (lib "eagle-import") (part "BAT19"))
    )
    (comp (ref "IC1")
      (value "74ALS245AN")
      (footprint "eagle-import:DIL20")
      (libsource (lib "eagle-import") (part "74245NLS"))
    )
    (comp (ref "IC2")
      (value "74ALS245AN")
      (footprint "eagle-import:DIL20")
      (libsource (lib "eagle-import") (part "74245NLS"))
    )
    (comp (ref "IC3")
      (value "62256")
      (footprint "eagle-import:DIL28-6")
      (libsource (lib "eagle-import") (part "58C256P"))
    )
    (comp (ref "IC4")
      (value "62256")
      (footprint "eagle-import:DIL28-6")
      (libsource (lib "eagle-import") (part "58C256P"))
    )
    (comp (ref "IC5")
      (value "74ACT138N")
      (footprint "eagle-import:DIL16")
      (libsource (lib "eagle-import") (part "74138NLS"))
    )
    (comp (ref "IC6")
      (value "74HCT30N")
      (footprint "eagle-import:DIL14")
      (libsource (lib "eagle-import") (part "7430NLS"))
    )
    (comp (ref "IC7")
      (value "74ACT20N")
      (footprint "eagle-import:DIL14")
      (libsource (lib "eagle-import") (part "7420NLS"))
    )
    (comp (ref "IC8")
      (value "74LS540N")
      (footprint "eagle-import:DIL20")
      (libsource (lib "eagle-import") (part "74540NLS"))
    )
    (comp (ref "Q1")
      (value "2N3904")
      (footprint "eagle-import:TO92")
      (libsource (lib "eagle-import") (part "2N3904"))
    )
    (comp (ref "R1")
      (value "10K")
      (footprint "eagle-import:0207_10")
      (libsource (lib "eagle-import") (part "R-US_0207/10"))
    )
    (comp (ref "R2")
      (value "10K")
      (footprint "eagle-import:0207_10")
      (libsource (lib "eagle-import") (part "R-US_0207/10"))
    )
    (comp (ref "R3")
      (value "10K")
      (footprint "eagle-import:0207_10")
      (libsource (lib "eagle-import") (part "R-US_0207/10"))
    )
    (comp (ref "R4")
      (value "10K")
      (footprint "eagle-import:0207_10")
      (libsource (lib "eagle-import") (part "R-US_0207/10"))
    )
    (comp (ref "R5")
      (value "10K")
      (footprint "eagle-import:DIL16")
      (libsource (lib "eagle-import") (part "8R-P"))
    )
    (comp (ref "R6")
      (value "100K")
      (footprint "eagle-import:0207_10")
      (libsource (lib "eagle-import") (part "R-US_0207/10"))
    )
    (comp (ref "R7")
      (value "100K")
      (footprint "eagle-import:0207_10")
      (libsource (lib "eagle-import") (part "R-US_0207/10"))
    )
    (comp (ref "S1")
      (value "SW_DIP-8")
      (footprint "eagle-import:EDG-08")
      (libsource (lib "eagle-import") (part "SW_DIP-8"))
    )
  )
  (nets
    (net (code "1") (name "+15V") (class "Default")
      (node (ref "D14") (pin "1") (pinfunction "1_1") (pintype "passive"))
      (node (ref "U$2") (pin "DA2") (pinfunction "1_DA2") (pintype "passive"))
    )
    (net (code "2") (name "-15V") (class "Default")
      (node (ref "D10") (pin "2") (pinfunction "2_2") (pintype "passive"))
      (node (ref "D12") (pin "2") (pinfunction "2_2") (pintype "passive"))
      (node (ref "D14") (pin "2") (pinfunction "2_2") (pintype "passive"))
      (node (ref "D8") (pin "2") (pinfunction "2_2") (pintype "passive"))
      (node (ref "U$2") (pin "AB2") (pinfunction "1_AB2") (pintype "passive"))
      (node (ref "U$2") (pin "BB2") (pinfunction "1_BB2") (pintype "passive"))
      (node (ref "U$2") (pin "CB2") (pinfunction "1_CB2") (pintype "passive"))
      (node (ref "U$2") (pin "DB2") (pinfunction "1_DB2") (pintype "passive"))
    )
    (net (code "3") (name "DISABLE") (class "Default")
      (node (ref "C2") (pin "2") (pinfunction "2_2") (pintype "passive"))
      (node (ref "IC6") (pin "8") (pinfunction "O_8") (pintype "output"))
      (node (ref "IC8") (pin "8") (pinfunction "A7_8") (pintype "input"))
      (node (ref "Q1") (pin "3") (pinfunction "E_3") (pintype "passive"))
    )
    (net (code "4") (name "EMEM0") (class "Default")
      (node (ref "IC2") (pin "11") (pinfunction "B8_11") (pintype "bidirectional"))
      (node (ref "IC4") (pin "19") (pinfunction "I/O7_19") (pintype "tri_state"))
    )
    (net (code "5") (name "EMEM1") (class "Default")
      (node (ref "IC2") (pin "12") (pinfunction "B7_12") (pintype "bidirectional"))
      (node (ref "IC4") (pin "18") (pinfunction "I/O6_18") (pintype "tri_state"))
    )
    (net (code "6") (name "EMEM2") (class "Default")
      (node (ref "IC2") (pin "13") (pinfunction "B6_13") (pintype "bidirectional"))
      (node (ref "IC4") (pin "17") (pinfunction "I/O5_17") (pintype "tri_state"))
    )
    (net (code "7") (name "EMEM3") (class "Default")
      (node (ref "IC2") (pin "14") (pinfunction "B5_14") (pintype "bidirectional"))
      (node (ref "IC4") (pin "16") (pinfunction "I/O4_16") (pintype "tri_state"))
    )
    (net (code "8") (name "GND") (class "Default")
      (node (ref "B1") (pin "-") (pinfunction "-_-") (pintype "passive"))
      (node (ref "B1") (pin "-@1") (pinfunction "-_-@1") (pintype "passive"))
      (node (ref "C1") (pin "2") (pinfunction "2_2") (pintype "passive"))
      (node (ref "C10") (pin "-") (pinfunction "-_-") (pintype "passive"))
      (node (ref "C3") (pin "2") (pinfunction "2_2") (pintype "passive"))
      (node (ref "C4") (pin "2") (pinfunction "2_2") (pintype "passive"))
      (node (ref "C5") (pin "2") (pinfunction "2_2") (pintype "passive"))
      (node (ref "C6") (pin "2") (pinfunction "2_2") (pintype "passive"))
      (node (ref "C7") (pin "2") (pinfunction "2_2") (pintype "passive"))
      (node (ref "C8") (pin "2") (pinfunction "2_2") (pintype "passive"))
      (node (ref "C9") (pin "2") (pinfunction "2_2") (pintype "passive"))
      (node (ref "D10") (pin "12") (pinfunction "12_12") (pintype "passive"))
      (node (ref "D10") (pin "16") (pinfunction "16_16") (pintype "passive"))
      (node (ref "D10") (pin "3") (pinfunction "3_3") (pintype "passive"))
      (node (ref "D10") (pin "6") (pinfunction "6_6") (pintype "passive"))
      (node (ref "D11") (pin "12") (pinfunction "12_12") (pintype "passive"))
      (node (ref "D11") (pin "16") (pinfunction "16_16") (pintype "passive"))
      (node (ref "D11") (pin "3") (pinfunction "3_3") (pintype "passive"))
      (node (ref "D11") (pin "6") (pinfunction "6_6") (pintype "passive"))
      (node (ref "D12") (pin "12") (pinfunction "12_12") (pintype "passive"))
      (node (ref "D12") (pin "16") (pinfunction "16_16") (pintype "passive"))
      (node (ref "D12") (pin "3") (pinfunction "3_3") (pintype "passive"))
      (node (ref "D12") (pin "6") (pinfunction "6_6") (pintype "passive"))
      (node (ref "D13") (pin "12") (pinfunction "12_12") (pintype "passive"))
      (node (ref "D13") (pin "16") (pinfunction "16_16") (pintype "passive"))
      (node (ref "D13") (pin "3") (pinfunction "3_3") (pintype "passive"))
      (node (ref "D13") (pin "6") (pinfunction "6_6") (pintype "passive"))
      (node (ref "D14") (pin "12") (pinfunction "12_12") (pintype "passive"))
      (node (ref "D14") (pin "16") (pinfunction "16_16") (pintype "passive"))
      (node (ref "D14") (pin "3") (pinfunction "3_3") (pintype "passive"))
      (node (ref "D14") (pin "6") (pinfunction "6_6") (pintype "passive"))
      (node (ref "D7") (pin "12") (pinfunction "12_12") (pintype "passive"))
      (node (ref "D7") (pin "16") (pinfunction "16_16") (pintype "passive"))
      (node (ref "D7") (pin "3") (pinfunction "3_3") (pintype "passive"))
      (node (ref "D7") (pin "6") (pinfunction "6_6") (pintype "passive"))
      (node (ref "D8") (pin "12") (pinfunction "12_12") (pintype "passive"))
      (node (ref "D8") (pin "16") (pinfunction "16_16") (pintype "passive"))
      (node (ref "D8") (pin "3") (pinfunction "3_3") (pintype "passive"))
      (node (ref "D8") (pin "6") (pinfunction "6_6") (pintype "passive"))
      (node (ref "D9") (pin "12") (pinfunction "12_12") (pintype "passive"))
      (node (ref "D9") (pin "16") (pinfunction "16_16") (pintype "passive"))
      (node (ref "D9") (pin "3") (pinfunction "3_3") (pintype "passive"))
      (node (ref "D9") (pin "6") (pinfunction "6_6") (pintype "passive"))
      (node (ref "GND1") (pin "1") (pinfunction "1_1") (pintype "passive"))
      (node (ref "GND1") (pin "2") (pinfunction "2_2") (pintype "passive"))
      (node (ref "GND10") (pin "1") (pinfunction "1_1") (pintype "passive"))
      (node (ref "GND10") (pin "2") (pinfunction "2_2") (pintype "passive"))
      (node (ref "GND11") (pin "1") (pinfunction "1_1") (pintype "passive"))
      (node (ref "GND11") (pin "2") (pinfunction "2_2") (pintype "passive"))
      (node (ref "GND12") (pin "1") (pinfunction "1_1") (pintype "passive"))
      (node (ref "GND12") (pin "2") (pinfunction "2_2") (pintype "passive"))
      (node (ref "GND13") (pin "1") (pinfunction "1_1") (pintype "passive"))
      (node (ref "GND13") (pin "2") (pinfunction "2_2") (pintype "passive"))
      (node (ref "GND14") (pin "1") (pinfunction "1_1") (pintype "passive"))
      (node (ref "GND14") (pin "2") (pinfunction "2_2") (pintype "passive"))
      (node (ref "GND15") (pin "1") (pinfunction "1_1") (pintype "passive"))
      (node (ref "GND15") (pin "2") (pinfunction "2_2") (pintype "passive"))
      (node (ref "GND16") (pin "1") (pinfunction "1_1") (pintype "passive"))
      (node (ref "GND16") (pin "2") (pinfunction "2_2") (pintype "passive"))
      (node (ref "GND17") (pin "1") (pinfunction "1_1") (pintype "passive"))
      (node (ref "GND17") (pin "2") (pinfunction "2_2") (pintype "passive"))
      (node (ref "GND18") (pin "1") (pinfunction "1_1") (pintype "passive"))
      (node (ref "GND18") (pin "2") (pinfunction "2_2") (pintype "passive"))
      (node (ref "GND19") (pin "1") (pinfunction "1_1") (pintype "passive"))
      (node (ref "GND19") (pin "2") (pinfunction "2_2") (pintype "passive"))
      (node (ref "GND2") (pin "1") (pinfunction "1_1") (pintype "passive"))
      (node (ref "GND2") (pin "2") (pinfunction "2_2") (pintype "passive"))
      (node (ref "GND20") (pin "1") (pinfunction "1_1") (pintype "passive"))
      (node (ref "GND20") (pin "2") (pinfunction "2_2") (pintype "passive"))
      (node (ref "GND21") (pin "1") (pinfunction "1_1") (pintype "passive"))
      (node (ref "GND21") (pin "2") (pinfunction "2_2") (pintype "passive"))
      (node (ref "GND22") (pin "1") (pinfunction "1_1") (pintype "passive"))
      (node (ref "GND22") (pin "2") (pinfunction "2_2") (pintype "passive"))
      (node (ref "GND23") (pin "1") (pinfunction "1_1") (pintype "passive"))
      (node (ref "GND23") (pin "2") (pinfunction "2_2") (pintype "passive"))
      (node (ref "GND24") (pin "1") (pinfunction "1_1") (pintype "passive"))
      (node (ref "GND24") (pin "2") (pinfunction "2_2") (pintype "passive"))
      (node (ref "GND25") (pin "1") (pinfunction "1_1") (pintype "passive"))
      (node (ref "GND25") (pin "2") (pinfunction "2_2") (pintype "passive"))
      (node (ref "GND26") (pin "1") (pinfunction "1_1") (pintype "passive"))
      (node (ref "GND26") (pin "2") (pinfunction "2_2") (pintype "passive"))
      (node (ref "GND27") (pin "1") (pinfunction "1_1") (pintype "passive"))
      (node (ref "GND27") (pin "2") (pinfunction "2_2") (pintype "passive"))
      (node (ref "GND28") (pin "1") (pinfunction "1_1") (pintype "passive"))
      (node (ref "GND28") (pin "2") (pinfunction "2_2") (pintype "passive"))
      (node (ref "GND29") (pin "1") (pinfunction "1_1") (pintype "passive"))
      (node (ref "GND29") (pin "2") (pinfunction "2_2") (pintype "passive"))
      (node (ref "GND3") (pin "1") (pinfunction "1_1") (pintype "passive"))
      (node (ref "GND3") (pin "2") (pinfunction "2_2") (pintype "passive"))
      (node (ref "GND30") (pin "1") (pinfunction "1_1") (pintype "passive"))
      (node (ref "GND30") (pin "2") (pinfunction "2_2") (pintype "passive"))
      (node (ref "GND31") (pin "1") (pinfunction "1_1") (pintype "passive"))
      (node (ref "GND31") (pin "2") (pinfunction "2_2") (pintype "passive"))
      (node (ref "GND32") (pin "1") (pinfunction "1_1") (pintype "passive"))
      (node (ref "GND32") (pin "2") (pinfunction "2_2") (pintype "passive"))
      (node (ref "GND33") (pin "1") (pinfunction "1_1") (pintype "passive"))
      (node (ref "GND33") (pin "2") (pinfunction "2_2") (pintype "passive"))
      (node (ref "GND34") (pin "1") (pinfunction "1_1") (pintype "passive"))
      (node (ref "GND34") (pin "2") (pinfunction "2_2") (pintype "passive"))
      (node (ref "GND35") (pin "1") (pinfunction "1_1") (pintype "passive"))
      (node (ref "GND35") (pin "2") (pinfunction "2_2") (pintype "passive"))
      (node (ref "GND36") (pin "1") (pinfunction "1_1") (pintype "passive"))
      (node (ref "GND36") (pin "2") (pinfunction "2_2") (pintype "passive"))
      (node (ref "GND37") (pin "1") (pinfunction "1_1") (pintype "passive"))
      (node (ref "GND37") (pin "2") (pinfunction "2_2") (pintype "passive"))
      (node (ref "GND38") (pin "1") (pinfunction "1_1") (pintype "passive"))
      (node (ref "GND38") (pin "2") (pinfunction "2_2") (pintype "passive"))
      (node (ref "GND39") (pin "1") (pinfunction "1_1") (pintype "passive"))
      (node (ref "GND39") (pin "2") (pinfunction "2_2") (pintype "passive"))
      (node (ref "GND4") (pin "1") (pinfunction "1_1") (pintype "passive"))
      (node (ref "GND4") (pin "2") (pinfunction "2_2") (pintype "passive"))
      (node (ref "GND40") (pin "1") (pinfunction "1_1") (pintype "passive"))
      (node (ref "GND40") (pin "2") (pinfunction "2_2") (pintype "passive"))
      (node (ref "GND41") (pin "1") (pinfunction "1_1") (pintype "passive"))
      (node (ref "GND41") (pin "2") (pinfunction "2_2") (pintype "passive"))
      (node (ref "GND42") (pin "1") (pinfunction "1_1") (pintype "passive"))
      (node (ref "GND42") (pin "2") (pinfunction "2_2") (pintype "passive"))
      (node (ref "GND43") (pin "1") (pinfunction "1_1") (pintype "passive"))
      (node (ref "GND43") (pin "2") (pinfunction "2_2") (pintype "passive"))
      (node (ref "GND44") (pin "1") (pinfunction "1_1") (pintype "passive"))
      (node (ref "GND44") (pin "2") (pinfunction "2_2") (pintype "passive"))
      (node (ref "GND5") (pin "1") (pinfunction "1_1") (pintype "passive"))
      (node (ref "GND5") (pin "2") (pinfunction "2_2") (pintype "passive"))
      (node (ref "GND6") (pin "1") (pinfunction "1_1") (pintype "passive"))
      (node (ref "GND6") (pin "2") (pinfunction "2_2") (pintype "passive"))
      (node (ref "GND7") (pin "1") (pinfunction "1_1") (pintype "passive"))
      (node (ref "GND7") (pin "2") (pinfunction "2_2") (pintype "passive"))
      (node (ref "GND8") (pin "1") (pinfunction "1_1") (pintype "passive"))
      (node (ref "GND8") (pin "2") (pinfunction "2_2") (pintype "passive"))
      (node (ref "GND9") (pin "1") (pinfunction "1_1") (pintype "passive"))
      (node (ref "GND9") (pin "2") (pinfunction "2_2") (pintype "passive"))
      (node (ref "IC1") (pin "19") (pinfunction "G_19") (pintype "input"))
      (node (ref "IC2") (pin "19") (pinfunction "G_19") (pintype "input"))
      (node (ref "IC3") (pin "14") (pinfunction "VSS_14") (pintype "power_in"))
      (node (ref "IC4") (pin "14") (pinfunction "VSS_14") (pintype "power_in"))
      (node (ref "IC5") (pin "4") (pinfunction "G2A_4") (pintype "input"))
      (node (ref "IC5") (pin "5") (pinfunction "G2B_5") (pintype "input"))
      (node (ref "IC8") (pin "1") (pinfunction "G1_1") (pintype "input"))
      (node (ref "IC8") (pin "19") (pinfunction "G2_19") (pintype "input"))
      (node (ref "IC8") (pin "9") (pinfunction "A8_9") (pintype "input"))
      (node (ref "R1") (pin "1") (pinfunction "1_1") (pintype "passive"))
      (node (ref "R2") (pin "1") (pinfunction "1_1") (pintype "passive"))
      (node (ref "R3") (pin "1") (pinfunction "1_1") (pintype "passive"))
      (node (ref "R4") (pin "1") (pinfunction "1_1") (pintype "passive"))
      (node (ref "SV10") (pin "1") (pinfunction "1_1") (pintype "passive"))
      (node (ref "SV10") (pin "2") (pinfunction "2_2") (pintype "passive"))
      (node (ref "SV10") (pin "3") (pinfunction "3_3") (pintype "passive"))
      (node (ref "SV10") (pin "4") (pinfunction "4_4") (pintype "passive"))
      (node (ref "SV10") (pin "5") (pinfunction "5_5") (pintype "passive"))
      (node (ref "SV10") (pin "6") (pinfunction "6_6") (pintype "passive"))
      (node (ref "SV10") (pin "7") (pinfunction "7_7") (pintype "passive"))
      (node (ref "SV10") (pin "8") (pinfunction "8_8") (pintype "passive"))
      (node (ref "SV12") (pin "1") (pinfunction "1_1") (pintype "passive"))
      (node (ref "SV12") (pin "10") (pinfunction "10_10") (pintype "passive"))
      (node (ref "SV12") (pin "2") (pinfunction "2_2") (pintype "passive"))
      (node (ref "SV12") (pin "3") (pinfunction "3_3") (pintype "passive"))
      (node (ref "SV12") (pin "4") (pinfunction "4_4") (pintype "passive"))
      (node (ref "SV12") (pin "5") (pinfunction "5_5") (pintype "passive"))
      (node (ref "SV12") (pin "6") (pinfunction "6_6") (pintype "passive"))
      (node (ref "SV12") (pin "7") (pinfunction "7_7") (pintype "passive"))
      (node (ref "SV12") (pin "8") (pinfunction "8_8") (pintype "passive"))
      (node (ref "SV12") (pin "9") (pinfunction "9_9") (pintype "passive"))
      (node (ref "SV176") (pin "1") (pinfunction "1_1") (pintype "passive"))
      (node (ref "SV176") (pin "10") (pinfunction "10_10") (pintype "passive"))
      (node (ref "SV176") (pin "11") (pinfunction "11_11") (pintype "passive"))
      (node (ref "SV176") (pin "12") (pinfunction "12_12") (pintype "passive"))
      (node (ref "SV176") (pin "13") (pinfunction "13_13") (pintype "passive"))
      (node (ref "SV176") (pin "14") (pinfunction "14_14") (pintype "passive"))
      (node (ref "SV176") (pin "15") (pinfunction "15_15") (pintype "passive"))
      (node (ref "SV176") (pin "16") (pinfunction "16_16") (pintype "passive"))
      (node (ref "SV176") (pin "17") (pinfunction "17_17") (pintype "passive"))
      (node (ref "SV176") (pin "18") (pinfunction "18_18") (pintype "passive"))
      (node (ref "SV176") (pin "19") (pinfunction "19_19") (pintype "passive"))
      (node (ref "SV176") (pin "2") (pinfunction "2_2") (pintype "passive"))
      (node (ref "SV176") (pin "20") (pinfunction "20_20") (pintype "passive"))
      (node (ref "SV176") (pin "3") (pinfunction "3_3") (pintype "passive"))
      (node (ref "SV176") (pin "4") (pinfunction "4_4") (pintype "passive"))
      (node (ref "SV176") (pin "5") (pinfunction "5_5") (pintype "passive"))
      (node (ref "SV176") (pin "6") (pinfunction "6_6") (pintype "passive"))
      (node (ref "SV176") (pin "7") (pinfunction "7_7") (pintype "passive"))
      (node (ref "SV176") (pin "8") (pinfunction "8_8") (pintype "passive"))
      (node (ref "SV176") (pin "9") (pinfunction "9_9") (pintype "passive"))
      (node (ref "SV180") (pin "1") (pinfunction "1_1") (pintype "passive"))
      (node (ref "SV180") (pin "10") (pinfunction "10_10") (pintype "passive"))
      (node (ref "SV180") (pin "2") (pinfunction "2_2") (pintype "passive"))
      (node (ref "SV180") (pin "3") (pinfunction "3_3") (pintype "passive"))
      (node (ref "SV180") (pin "4") (pinfunction "4_4") (pintype "passive"))
      (node (ref "SV180") (pin "5") (pinfunction "5_5") (pintype "passive"))
      (node (ref "SV180") (pin "6") (pinfunction "6_6") (pintype "passive"))
      (node (ref "SV180") (pin "7") (pinfunction "7_7") (pintype "passive"))
      (node (ref "SV180") (pin "8") (pinfunction "8_8") (pintype "passive"))
      (node (ref "SV180") (pin "9") (pinfunction "9_9") (pintype "passive"))
      (node (ref "SV4") (pin "1") (pinfunction "1_1") (pintype "passive"))
      (node (ref "SV4") (pin "10") (pinfunction "10_10") (pintype "passive"))
      (node (ref "SV4") (pin "11") (pinfunction "11_11") (pintype "passive"))
      (node (ref "SV4") (pin "12") (pinfunction "12_12") (pintype "passive"))
      (node (ref "SV4") (pin "13") (pinfunction "13_13") (pintype "passive"))
      (node (ref "SV4") (pin "14") (pinfunction "14_14") (pintype "passive"))
      (node (ref "SV4") (pin "15") (pinfunction "15_15") (pintype "passive"))
      (node (ref "SV4") (pin "16") (pinfunction "16_16") (pintype "passive"))
      (node (ref "SV4") (pin "17") (pinfunction "17_17") (pintype "passive"))
      (node (ref "SV4") (pin "18") (pinfunction "18_18") (pintype "passive"))
      (node (ref "SV4") (pin "19") (pinfunction "19_19") (pintype "passive"))
      (node (ref "SV4") (pin "2") (pinfunction "2_2") (pintype "passive"))
      (node (ref "SV4") (pin "20") (pinfunction "20_20") (pintype "passive"))
      (node (ref "SV4") (pin "3") (pinfunction "3_3") (pintype "passive"))
      (node (ref "SV4") (pin "4") (pinfunction "4_4") (pintype "passive"))
      (node (ref "SV4") (pin "5") (pinfunction "5_5") (pintype "passive"))
      (node (ref "SV4") (pin "6") (pinfunction "6_6") (pintype "passive"))
      (node (ref "SV4") (pin "7") (pinfunction "7_7") (pintype "passive"))
      (node (ref "SV4") (pin "8") (pinfunction "8_8") (pintype "passive"))
      (node (ref "SV4") (pin "9") (pinfunction "9_9") (pintype "passive"))
      (node (ref "SV6") (pin "1") (pinfunction "1_1") (pintype "passive"))
      (node (ref "SV6") (pin "10") (pinfunction "10_10") (pintype "passive"))
      (node (ref "SV6") (pin "11") (pinfunction "11_11") (pintype "passive"))
      (node (ref "SV6") (pin "12") (pinfunction "12_12") (pintype "passive"))
      (node (ref "SV6") (pin "13") (pinfunction "13_13") (pintype "passive"))
      (node (ref "SV6") (pin "14") (pinfunction "14_14") (pintype "passive"))
      (node (ref "SV6") (pin "15") (pinfunction "15_15") (pintype "passive"))
      (node (ref "SV6") (pin "16") (pinfunction "16_16") (pintype "passive"))
      (node (ref "SV6") (pin "17") (pinfunction "17_17") (pintype "passive"))
      (node (ref "SV6") (pin "18") (pinfunction "18_18") (pintype "passive"))
      (node (ref "SV6") (pin "19") (pinfunction "19_19") (pintype "passive"))
      (node (ref "SV6") (pin "2") (pinfunction "2_2") (pintype "passive"))
      (node (ref "SV6") (pin "20") (pinfunction "20_20") (pintype "passive"))
      (node (ref "SV6") (pin "3") (pinfunction "3_3") (pintype "passive"))
      (node (ref "SV6") (pin "4") (pinfunction "4_4") (pintype "passive"))
      (node (ref "SV6") (pin "5") (pinfunction "5_5") (pintype "passive"))
      (node (ref "SV6") (pin "6") (pinfunction "6_6") (pintype "passive"))
      (node (ref "SV6") (pin "7") (pinfunction "7_7") (pintype "passive"))
      (node (ref "SV6") (pin "8") (pinfunction "8_8") (pintype "passive"))
      (node (ref "SV6") (pin "9") (pinfunction "9_9") (pintype "passive"))
      (node (ref "U$2") (pin "AC1") (pinfunction "1_AC1") (pintype "passive"))
      (node (ref "U$2") (pin "AC2") (pinfunction "1_AC2") (pintype "passive"))
      (node (ref "U$2") (pin "AF1") (pinfunction "1_AF1") (pintype "passive"))
      (node (ref "U$2") (pin "AF2") (pinfunction "1_AF2") (pintype "passive"))
      (node (ref "U$2") (pin "AN1") (pinfunction "1_AN1") (pintype "passive"))
      (node (ref "U$2") (pin "AN2") (pinfunction "1_AN2") (pintype "passive"))
      (node (ref "U$2") (pin "AT1") (pinfunction "1_AT1") (pintype "passive"))
      (node (ref "U$2") (pin "AT2") (pinfunction "1_AT2") (pintype "passive"))
      (node (ref "U$2") (pin "BC1") (pinfunction "1_BC1") (pintype "passive"))
      (node (ref "U$2") (pin "BC2") (pinfunction "1_BC2") (pintype "passive"))
      (node (ref "U$2") (pin "BF1") (pinfunction "1_BF1") (pintype "passive"))
      (node (ref "U$2") (pin "BF2") (pinfunction "1_BF2") (pintype "passive"))
      (node (ref "U$2") (pin "BN1") (pinfunction "1_BN1") (pintype "passive"))
      (node (ref "U$2") (pin "BN2") (pinfunction "1_BN2") (pintype "passive"))
      (node (ref "U$2") (pin "BT1") (pinfunction "1_BT1") (pintype "passive"))
      (node (ref "U$2") (pin "BT2") (pinfunction "1_BT2") (pintype "passive"))
      (node (ref "U$2") (pin "CC1") (pinfunction "1_CC1") (pintype "passive"))
      (node (ref "U$2") (pin "CC2") (pinfunction "1_CC2") (pintype "passive"))
      (node (ref "U$2") (pin "CF1") (pinfunction "1_CF1") (pintype "passive"))
      (node (ref "U$2") (pin "CF2") (pinfunction "1_CF2") (pintype "passive"))
      (node (ref "U$2") (pin "CN1") (pinfunction "1_CN1") (pintype "passive"))
      (node (ref "U$2") (pin "CN2") (pinfunction "1_CN2") (pintype "passive"))
      (node (ref "U$2") (pin "CT1") (pinfunction "1_CT1") (pintype "passive"))
      (node (ref "U$2") (pin "CT2") (pinfunction "1_CT2") (pintype "passive"))
      (node (ref "U$2") (pin "DC1") (pinfunction "1_DC1") (pintype "passive"))
      (node (ref "U$2") (pin "DC2") (pinfunction "1_DC2") (pintype "passive"))
      (node (ref "U$2") (pin "DF1") (pinfunction "1_DF1") (pintype "passive"))
      (node (ref "U$2") (pin "DF2") (pinfunction "1_DF2") (pintype "passive"))
      (node (ref "U$2") (pin "DN1") (pinfunction "1_DN1") (pintype "passive"))
      (node (ref "U$2") (pin "DN2") (pinfunction "1_DN2") (pintype "passive"))
      (node (ref "U$2") (pin "DT1") (pinfunction "1_DT1") (pintype "passive"))
      (node (ref "U$2") (pin "DT2") (pinfunction "1_DT2") (pintype "passive"))
    )
    (net (code "9") (name "INHIBIT") (class "Default")
      (node (ref "D10") (pin "13") (pinfunction "13_13") (pintype "passive"))
      (node (ref "U$2") (pin "AP2") (pinfunction "1_AP2") (pintype "passive"))
    )
    (net (code "10") (name "INITIALIZE") (class "Default")
      (node (ref "D11") (pin "14") (pinfunction "14_14") (pintype "passive"))
      (node (ref "U$2") (pin "CR1") (pinfunction "1_CR1") (pintype "passive"))
    )
    (net (code "11") (name "INT_IN_PROG") (class "Default")
      (node (ref "D8") (pin "13") (pinfunction "13_13") (pintype "passive"))
      (node (ref "U$2") (pin "BP2") (pinfunction "1_BP2") (pintype "passive"))
    )
    (net (code "12") (name "INT_STROBE") (class "Default")
      (node (ref "D8") (pin "4") (pinfunction "4_4") (pintype "passive"))
      (node (ref "U$2") (pin "BD2") (pinfunction "1_BD2") (pintype "passive"))
    )
    (net (code "13") (name "MEM00") (class "Default")
      (node (ref "IC2") (pin "15") (pinfunction "B4_15") (pintype "bidirectional"))
      (node (ref "IC4") (pin "15") (pinfunction "I/O3_15") (pintype "tri_state"))
    )
    (net (code "14") (name "MEM01") (class "Default")
      (node (ref "IC2") (pin "16") (pinfunction "B3_16") (pintype "bidirectional"))
      (node (ref "IC4") (pin "13") (pinfunction "I/O2_13") (pintype "tri_state"))
    )
    (net (code "15") (name "MEM02") (class "Default")
      (node (ref "IC2") (pin "17") (pinfunction "B2_17") (pintype "bidirectional"))
      (node (ref "IC4") (pin "12") (pinfunction "I/O1_12") (pintype "tri_state"))
    )
    (net (code "16") (name "MEM03") (class "Default")
      (node (ref "IC2") (pin "18") (pinfunction "B1_18") (pintype "bidirectional"))
      (node (ref "IC4") (pin "11") (pinfunction "I/O0_11") (pintype "tri_state"))
    )
    (net (code "17") (name "MEM04") (class "Default")
      (node (ref "IC1") (pin "11") (pinfunction "B8_11") (pintype "bidirectional"))
      (node (ref "IC3") (pin "19") (pinfunction "I/O7_19") (pintype "tri_state"))
    )
    (net (code "18") (name "MEM05") (class "Default")
      (node (ref "IC1") (pin "12") (pinfunction "B7_12") (pintype "bidirectional"))
      (node (ref "IC3") (pin "18") (pinfunction "I/O6_18") (pintype "tri_state"))
    )
    (net (code "19") (name "MEM06") (class "Default")
      (node (ref "IC1") (pin "13") (pinfunction "B6_13") (pintype "bidirectional"))
      (node (ref "IC3") (pin "17") (pinfunction "I/O5_17") (pintype "tri_state"))
    )
    (net (code "20") (name "MEM07") (class "Default")
      (node (ref "IC1") (pin "14") (pinfunction "B5_14") (pintype "bidirectional"))
      (node (ref "IC3") (pin "16") (pinfunction "I/O4_16") (pintype "tri_state"))
    )
    (net (code "21") (name "MEM08") (class "Default")
      (node (ref "IC1") (pin "15") (pinfunction "B4_15") (pintype "bidirectional"))
      (node (ref "IC3") (pin "15") (pinfunction "I/O3_15") (pintype "tri_state"))
    )
    (net (code "22") (name "MEM09") (class "Default")
      (node (ref "IC1") (pin "16") (pinfunction "B3_16") (pintype "bidirectional"))
      (node (ref "IC3") (pin "13") (pinfunction "I/O2_13") (pintype "tri_state"))
    )
    (net (code "23") (name "MEM10") (class "Default")
      (node (ref "IC1") (pin "17") (pinfunction "B2_17") (pintype "bidirectional"))
      (node (ref "IC3") (pin "12") (pinfunction "I/O1_12") (pintype "tri_state"))
    )
    (net (code "24") (name "MEM11") (class "Default")
      (node (ref "IC1") (pin "18") (pinfunction "B1_18") (pintype "bidirectional"))
      (node (ref "IC3") (pin "11") (pinfunction "I/O0_11") (pintype "tri_state"))
    )
    (net (code "25") (name "Net-(A1-Pad1)") (class "Default")
      (node (ref "A1") (pin "1") (pinfunction "1_1") (pintype "passive"))
      (node (ref "A1") (pin "2") (pinfunction "2_2") (pintype "passive"))
      (node (ref "IC9") (pin "1") (pinfunction "1_1") (pintype "passive"))
    )
    (net (code "26") (name "Net-(A2-Pad1)") (class "Default")
      (node (ref "A2") (pin "1") (pinfunction "1_1") (pintype "passive"))
      (node (ref "A2") (pin "2") (pinfunction "2_2") (pintype "passive"))
      (node (ref "IC9") (pin "2") (pinfunction "2_2") (pintype "passive"))
    )
    (net (code "27") (name "Net-(A3-Pad1)") (class "Default")
      (node (ref "A3") (pin "1") (pinfunction "1_1") (pintype "passive"))
      (node (ref "A3") (pin "2") (pinfunction "2_2") (pintype "passive"))
      (node (ref "IC9") (pin "3") (pinfunction "3_3") (pintype "passive"))
    )
    (net (code "28") (name "Net-(A4-Pad1)") (class "Default")
      (node (ref "A4") (pin "1") (pinfunction "1_1") (pintype "passive"))
      (node (ref "A4") (pin "2") (pinfunction "2_2") (pintype "passive"))
      (node (ref "IC9") (pin "4") (pinfunction "4_4") (pintype "passive"))
    )
    (net (code "29") (name "Net-(A5-Pad1)") (class "Default")
      (node (ref "A5") (pin "1") (pinfunction "1_1") (pintype "passive"))
      (node (ref "A5") (pin "2") (pinfunction "2_2") (pintype "passive"))
      (node (ref "IC9") (pin "5") (pinfunction "5_5") (pintype "passive"))
    )
    (net (code "30") (name "Net-(A6-Pad1)") (class "Default")
      (node (ref "A6") (pin "1") (pinfunction "1_1") (pintype "passive"))
      (node (ref "A6") (pin "2") (pinfunction "2_2") (pintype "passive"))
      (node (ref "IC9") (pin "6") (pinfunction "6_6") (pintype "passive"))
    )
    (net (code "31") (name "Net-(A7-Pad1)") (class "Default")
      (node (ref "A7") (pin "1") (pinfunction "1_1") (pintype "passive"))
      (node (ref "A7") (pin "2") (pinfunction "2_2") (pintype "passive"))
      (node (ref "IC9") (pin "7") (pinfunction "7_7") (pintype "passive"))
    )
    (net (code "32") (name "Net-(A8-Pad1)") (class "Default")
      (node (ref "A8") (pin "1") (pinfunction "1_1") (pintype "passive"))
      (node (ref "A8") (pin "2") (pinfunction "2_2") (pintype "passive"))
      (node (ref "IC9") (pin "8") (pinfunction "8_8") (pintype "passive"))
    )
    (net (code "33") (name "Net-(A9-Pad1)") (class "Default")
      (node (ref "A9") (pin "1") (pinfunction "1_1") (pintype "passive"))
      (node (ref "A9") (pin "2") (pinfunction "2_2") (pintype "passive"))
      (node (ref "IC9") (pin "9") (pinfunction "9_9") (pintype "passive"))
    )
    (net (code "34") (name "Net-(A10-Pad1)") (class "Default")
      (node (ref "A10") (pin "1") (pinfunction "1_1") (pintype "passive"))
      (node (ref "A10") (pin "2") (pinfunction "2_2") (pintype "passive"))
      (node (ref "IC9") (pin "10") (pinfunction "10_10") (pintype "passive"))
    )
    (net (code "35") (name "Net-(A11-Pad1)") (class "Default")
      (node (ref "A11") (pin "1") (pinfunction "1_1") (pintype "passive"))
      (node (ref "A11") (pin "2") (pinfunction "2_2") (pintype "passive"))
      (node (ref "IC9") (pin "11") (pinfunction "11_11") (pintype "passive"))
    )
    (net (code "36") (name "Net-(A12-Pad1)") (class "Default")
      (node (ref "A12") (pin "1") (pinfunction "1_1") (pintype "passive"))
      (node (ref "A12") (pin "2") (pinfunction "2_2") (pintype "passive"))
      (node (ref "IC9") (pin "12") (pinfunction "12_12") (pintype "passive"))
    )
    (net (code "37") (name "Net-(A13-Pad1)") (class "Default")
      (node (ref "A13") (pin "1") (pinfunction "1_1") (pintype "passive"))
      (node (ref "A13") (pin "2") (pinfunction "2_2") (pintype "passive"))
      (node (ref "IC9") (pin "13") (pinfunction "13_13") (pintype "passive"))
    )
    (net (code "38") (name "Net-(A14-Pad1)") (class "Default")
      (node (ref "A14") (pin "1") (pinfunction "1_1") (pintype "passive"))
      (node (ref "A14") (pin "2") (pinfunction "2_2") (pintype "passive"))
      (node (ref "IC9") (pin "14") (pinfunction "14_14") (pintype "passive"))
    )
    (net (code "39") (name "Net-(A15-Pad1)") (class "Default")
      (node (ref "A15") (pin "1") (pinfunction "1_1") (pintype "passive"))
      (node (ref "A15") (pin "2") (pinfunction "2_2") (pintype "passive"))
      (node (ref "IC9") (pin "15") (pinfunction "15_15") (pintype "passive"))
    )
    (net (code "40") (name "Net-(A16-Pad1)") (class "Default")
      (node (ref "A16") (pin "1") (pinfunction "1_1") (pintype "passive"))
      (node (ref "A16") (pin "2") (pinfunction "2_2") (pintype "passive"))
      (node (ref "IC9") (pin "16") (pinfunction "16_16") (pintype "passive"))
    )
    (net (code "41") (name "Net-(A17-Pad1)") (class "Default")
      (node (ref "A17") (pin "1") (pinfunction "1_1") (pintype "passive"))
      (node (ref "A17") (pin "2") (pinfunction "2_2") (pintype "passive"))
      (node (ref "IC10") (pin "1") (pinfunction "1_1") (pintype "passive"))
    )
    (net (code "42") (name "Net-(A18-Pad1)") (class "Default")
      (node (ref "A18") (pin "1") (pinfunction "1_1") (pintype "passive"))
      (node (ref "A18") (pin "2") (pinfunction "2_2") (pintype "passive"))
      (node (ref "IC10") (pin "2") (pinfunction "2_2") (pintype "passive"))
    )
    (net (code "43") (name "Net-(A19-Pad1)") (class "Default")
      (node (ref "A19") (pin "1") (pinfunction "1_1") (pintype "passive"))
      (node (ref "A19") (pin "2") (pinfunction "2_2") (pintype "passive"))
      (node (ref "IC10") (pin "3") (pinfunction "3_3") (pintype "passive"))
    )
    (net (code "44") (name "Net-(A20-Pad1)") (class "Default")
      (node (ref "A20") (pin "1") (pinfunction "1_1") (pintype "passive"))
      (node (ref "A20") (pin "2") (pinfunction "2_2") (pintype "passive"))
      (node (ref "IC10") (pin "4") (pinfunction "4_4") (pintype "passive"))
    )
    (net (code "45") (name "Net-(A21-Pad1)") (class "Default")
      (node (ref "A21") (pin "1") (pinfunction "1_1") (pintype "passive"))
      (node (ref "A21") (pin "2") (pinfunction "2_2") (pintype "passive"))
      (node (ref "IC10") (pin "5") (pinfunction "5_5") (pintype "passive"))
    )
    (net (code "46") (name "Net-(A22-Pad1)") (class "Default")
      (node (ref "A22") (pin "1") (pinfunction "1_1") (pintype "passive"))
      (node (ref "A22") (pin "2") (pinfunction "2_2") (pintype "passive"))
      (node (ref "IC10") (pin "6") (pinfunction "6_6") (pintype "passive"))
    )
    (net (code "47") (name "Net-(A23-Pad1)") (class "Default")
      (node (ref "A23") (pin "1") (pinfunction "1_1") (pintype "passive"))
      (node (ref "A23") (pin "2") (pinfunction "2_2") (pintype "passive"))
      (node (ref "IC10") (pin "7") (pinfunction "7_7") (pintype "passive"))
    )
    (net (code "48") (name "Net-(A24-Pad1)") (class "Default")
      (node (ref "A24") (pin "1") (pinfunction "1_1") (pintype "passive"))
      (node (ref "A24") (pin "2") (pinfunction "2_2") (pintype "passive"))
      (node (ref "IC10") (pin "8") (pinfunction "8_8") (pintype "passive"))
    )
    (net (code "49") (name "Net-(A25-Pad1)") (class "Default")
      (node (ref "A25") (pin "1") (pinfunction "1_1") (pintype "passive"))
      (node (ref "A25") (pin "2") (pinfunction "2_2") (pintype "passive"))
      (node (ref "IC10") (pin "9") (pinfunction "9_9") (pintype "passive"))
    )
    (net (code "50") (name "Net-(A26-Pad1)") (class "Default")
      (node (ref "A26") (pin "1") (pinfunction "1_1") (pintype "passive"))
      (node (ref "A26") (pin "2") (pinfunction "2_2") (pintype "passive"))
      (node (ref "IC10") (pin "10") (pinfunction "10_10") (pintype "passive"))
    )
    (net (code "51") (name "Net-(A27-Pad1)") (class "Default")
      (node (ref "A27") (pin "1") (pinfunction "1_1") (pintype "passive"))
      (node (ref "A27") (pin "2") (pinfunction "2_2") (pintype "passive"))
      (node (ref "IC10") (pin "11") (pinfunction "11_11") (pintype "passive"))
    )
    (net (code "52") (name "Net-(A28-Pad1)") (class "Default")
      (node (ref "A28") (pin "1") (pinfunction "1_1") (pintype "passive"))
      (node (ref "A28") (pin "2") (pinfunction "2_2") (pintype "passive"))
      (node (ref "IC10") (pin "12") (pinfunction "12_12") (pintype "passive"))
    )
    (net (code "53") (name "Net-(A29-Pad1)") (class "Default")
      (node (ref "A29") (pin "1") (pinfunction "1_1") (pintype "passive"))
      (node (ref "A29") (pin "2") (pinfunction "2_2") (pintype "passive"))
      (node (ref "IC10") (pin "13") (pinfunction "13_13") (pintype "passive"))
    )
    (net (code "54") (name "Net-(A30-Pad1)") (class "Default")
      (node (ref "A30") (pin "1") (pinfunction "1_1") (pintype "passive"))
      (node (ref "A30") (pin "2") (pinfunction "2_2") (pintype "passive"))
      (node (ref "IC10") (pin "14") (pinfunction "14_14") (pintype "passive"))
    )
    (net (code "55") (name "Net-(A31-Pad1)") (class "Default")
      (node (ref "A31") (pin "1") (pinfunction "1_1") (pintype "passive"))
      (node (ref "A31") (pin "2") (pinfunction "2_2") (pintype "passive"))
      (node (ref "IC10") (pin "15") (pinfunction "15_15") (pintype "passive"))
    )
    (net (code "56") (name "Net-(A32-Pad1)") (class "Default")
      (node (ref "A32") (pin "1") (pinfunction "1_1") (pintype "passive"))
      (node (ref "A32") (pin "2") (pinfunction "2_2") (pintype "passive"))
      (node (ref "IC10") (pin "16") (pinfunction "16_16") (pintype "passive"))
    )
    (net (code "57") (name "Net-(A33-Pad1)") (class "Default")
      (node (ref "A33") (pin "1") (pinfunction "1_1") (pintype "passive"))
      (node (ref "A33") (pin "2") (pinfunction "2_2") (pintype "passive"))
      (node (ref "IC11") (pin "1") (pinfunction "1_1") (pintype "passive"))
    )
    (net (code "58") (name "Net-(A34-Pad1)") (class "Default")
      (node (ref "A34") (pin "1") (pinfunction "1_1") (pintype "passive"))
      (node (ref "A34") (pin "2") (pinfunction "2_2") (pintype "passive"))
      (node (ref "IC11") (pin "2") (pinfunction "2_2") (pintype "passive"))
    )
    (net (code "59") (name "Net-(A35-Pad1)") (class "Default")
      (node (ref "A35") (pin "1") (pinfunction "1_1") (pintype "passive"))
      (node (ref "A35") (pin "2") (pinfunction "2_2") (pintype "passive"))
      (node (ref "IC11") (pin "3") (pinfunction "3_3") (pintype "passive"))
    )
    (net (code "60") (name "Net-(A36-Pad1)") (class "Default")
      (node (ref "A36") (pin "1") (pinfunction "1_1") (pintype "passive"))
      (node (ref "A36") (pin "2") (pinfunction "2_2") (pintype "passive"))
      (node (ref "IC11") (pin "4") (pinfunction "4_4") (pintype "passive"))
    )
    (net (code "61") (name "Net-(A37-Pad1)") (class "Default")
      (node (ref "A37") (pin "1") (pinfunction "1_1") (pintype "passive"))
      (node (ref "A37") (pin "2") (pinfunction "2_2") (pintype "passive"))
      (node (ref "IC11") (pin "5") (pinfunction "5_5") (pintype "passive"))
    )
    (net (code "62") (name "Net-(A38-Pad1)") (class "Default")
      (node (ref "A38") (pin "1") (pinfunction "1_1") (pintype "passive"))
      (node (ref "A38") (pin "2") (pinfunction "2_2") (pintype "passive"))
      (node (ref "IC11") (pin "6") (pinfunction "6_6") (pintype "passive"))
    )
    (net (code "63") (name "Net-(A39-Pad1)") (class "Default")
      (node (ref "A39") (pin "1") (pinfunction "1_1") (pintype "passive"))
      (node (ref "A39") (pin "2") (pinfunction "2_2") (pintype "passive"))
      (node (ref "IC11") (pin "7") (pinfunction "7_7") (pintype "passive"))
    )
    (net (code "64") (name "Net-(A40-Pad1)") (class "Default")
      (node (ref "A40") (pin "1") (pinfunction "1_1") (pintype "passive"))
      (node (ref "A40") (pin "2") (pinfunction "2_2") (pintype "passive"))
      (node (ref "IC11") (pin "8") (pinfunction "8_8") (pintype "passive"))
    )
    (net (code "65") (name "Net-(A41-Pad1)") (class "Default")
      (node (ref "A41") (pin "1") (pinfunction "1_1") (pintype "passive"))
      (node (ref "A41") (pin "2") (pinfunction "2_2") (pintype "passive"))
      (node (ref "IC11") (pin "9") (pinfunction "9_9") (pintype "passive"))
    )
    (net (code "66") (name "Net-(A42-Pad1)") (class "Default")
      (node (ref "A42") (pin "1") (pinfunction "1_1") (pintype "passive"))
      (node (ref "A42") (pin "2") (pinfunction "2_2") (pintype "passive"))
      (node (ref "IC11") (pin "10") (pinfunction "10_10") (pintype "passive"))
    )
    (net (code "67") (name "Net-(A43-Pad1)") (class "Default")
      (node (ref "A43") (pin "1") (pinfunction "1_1") (pintype "passive"))
      (node (ref "A43") (pin "2") (pinfunction "2_2") (pintype "passive"))
      (node (ref "IC11") (pin "11") (pinfunction "11_11") (pintype "passive"))
    )
    (net (code "68") (name "Net-(A44-Pad1)") (class "Default")
      (node (ref "A44") (pin "1") (pinfunction "1_1") (pintype "passive"))
      (node (ref "A44") (pin "2") (pinfunction "2_2") (pintype "passive"))
      (node (ref "IC11") (pin "12") (pinfunction "12_12") (pintype "passive"))
    )
    (net (code "69") (name "Net-(A45-Pad1)") (class "Default")
      (node (ref "A45") (pin "1") (pinfunction "1_1") (pintype "passive"))
      (node (ref "A45") (pin "2") (pinfunction "2_2") (pintype "passive"))
      (node (ref "IC11") (pin "13") (pinfunction "13_13") (pintype "passive"))
    )
    (net (code "70") (name "Net-(A46-Pad1)") (class "Default")
      (node (ref "A46") (pin "1") (pinfunction "1_1") (pintype "passive"))
      (node (ref "A46") (pin "2") (pinfunction "2_2") (pintype "passive"))
      (node (ref "IC11") (pin "14") (pinfunction "14_14") (pintype "passive"))
    )
    (net (code "71") (name "Net-(A47-Pad1)") (class "Default")
      (node (ref "A47") (pin "1") (pinfunction "1_1") (pintype "passive"))
      (node (ref "A47") (pin "2") (pinfunction "2_2") (pintype "passive"))
      (node (ref "IC11") (pin "15") (pinfunction "15_15") (pintype "passive"))
    )
    (net (code "72") (name "Net-(A48-Pad1)") (class "Default")
      (node (ref "A48") (pin "1") (pinfunction "1_1") (pintype "passive"))
      (node (ref "A48") (pin "2") (pinfunction "2_2") (pintype "passive"))
      (node (ref "IC11") (pin "16") (pinfunction "16_16") (pintype "passive"))
    )
    (net (code "73") (name "Net-(A49-Pad1)") (class "Default")
      (node (ref "A49") (pin "1") (pinfunction "1_1") (pintype "passive"))
      (node (ref "A49") (pin "2") (pinfunction "2_2") (pintype "passive"))
      (node (ref "IC12") (pin "1") (pinfunction "1_1") (pintype "passive"))
    )
    (net (code "74") (name "Net-(A50-Pad1)") (class "Default")
      (node (ref "A50") (pin "1") (pinfunction "1_1") (pintype "passive"))
      (node (ref "A50") (pin "2") (pinfunction "2_2") (pintype "passive"))
      (node (ref "IC12") (pin "2") (pinfunction "2_2") (pintype "passive"))
    )
    (net (code "75") (name "Net-(A51-Pad1)") (class "Default")
      (node (ref "A51") (pin "1") (pinfunction "1_1") (pintype "passive"))
      (node (ref "A51") (pin "2") (pinfunction "2_2") (pintype "passive"))
      (node (ref "IC12") (pin "3") (pinfunction "3_3") (pintype "passive"))
    )
    (net (code "76") (name "Net-(A52-Pad1)") (class "Default")
      (node (ref "A52") (pin "1") (pinfunction "1_1") (pintype "passive"))
      (node (ref "A52") (pin "2") (pinfunction "2_2") (pintype "passive"))
      (node (ref "IC12") (pin "4") (pinfunction "4_4") (pintype "passive"))
    )
    (net (code "77") (name "Net-(A53-Pad1)") (class "Default")
      (node (ref "A53") (pin "1") (pinfunction "1_1") (pintype "passive"))
      (node (ref "A53") (pin "2") (pinfunction "2_2") (pintype "passive"))
      (node (ref "IC12") (pin "5") (pinfunction "5_5") (pintype "passive"))
    )
    (net (code "78") (name "Net-(A54-Pad1)") (class "Default")
      (node (ref "A54") (pin "1") (pinfunction "1_1") (pintype "passive"))
      (node (ref "A54") (pin "2") (pinfunction "2_2") (pintype "passive"))
      (node (ref "IC12") (pin "6") (pinfunction "6_6") (pintype "passive"))
    )
    (net (code "79") (name "Net-(A55-Pad1)") (class "Default")
      (node (ref "A55") (pin "1") (pinfunction "1_1") (pintype "passive"))
      (node (ref "A55") (pin "2") (pinfunction "2_2") (pintype "passive"))
      (node (ref "IC12") (pin "7") (pinfunction "7_7") (pintype "passive"))
    )
    (net (code "80") (name "Net-(A56-Pad1)") (class "Default")
      (node (ref "A56") (pin "1") (pinfunction "1_1") (pintype "passive"))
      (node (ref "A56") (pin "2") (pinfunction "2_2") (pintype "passive"))
      (node (ref "IC12") (pin "8") (pinfunction "8_8") (pintype "passive"))
    )
    (net (code "81") (name "Net-(A57-Pad1)") (class "Default")
      (node (ref "A57") (pin "1") (pinfunction "1_1") (pintype "passive"))
      (node (ref "A57") (pin "2") (pinfunction "2_2") (pintype "passive"))
      (node (ref "IC12") (pin "9") (pinfunction "9_9") (pintype "passive"))
    )
    (net (code "82") (name "Net-(A58-Pad1)") (class "Default")
      (node (ref "A58") (pin "1") (pinfunction "1_1") (pintype "passive"))
      (node (ref "A58") (pin "2") (pinfunction "2_2") (pintype "passive"))
      (node (ref "IC12") (pin "10") (pinfunction "10_10") (pintype "passive"))
    )
    (net (code "83") (name "Net-(A59-Pad1)") (class "Default")
      (node (ref "A59") (pin "1") (pinfunction "1_1") (pintype "passive"))
      (node (ref "A59") (pin "2") (pinfunction "2_2") (pintype "passive"))
      (node (ref "IC12") (pin "11") (pinfunction "11_11") (pintype "passive"))
    )
    (net (code "84") (name "Net-(A60-Pad1)") (class "Default")
      (node (ref "A60") (pin "1") (pinfunction "1_1") (pintype "passive"))
      (node (ref "A60") (pin "2") (pinfunction "2_2") (pintype "passive"))
      (node (ref "IC12") (pin "12") (pinfunction "12_12") (pintype "passive"))
    )
    (net (code "85") (name "Net-(A61-Pad1)") (class "Default")
      (node (ref "A61") (pin "1") (pinfunction "1_1") (pintype "passive"))
      (node (ref "A61") (pin "2") (pinfunction "2_2") (pintype "passive"))
      (node (ref "IC12") (pin "13") (pinfunction "13_13") (pintype "passive"))
    )
    (net (code "86") (name "Net-(A62-Pad1)") (class "Default")
      (node (ref "A62") (pin "1") (pinfunction "1_1") (pintype "passive"))
      (node (ref "A62") (pin "2") (pinfunction "2_2") (pintype "passive"))
      (node (ref "IC12") (pin "14") (pinfunction "14_14") (pintype "passive"))
    )
    (net (code "87") (name "Net-(A63-Pad1)") (class "Default")
      (node (ref "A63") (pin "1") (pinfunction "1_1") (pintype "passive"))
      (node (ref "A63") (pin "2") (pinfunction "2_2") (pintype "passive"))
      (node (ref "IC12") (pin "15") (pinfunction "15_15") (pintype "passive"))
    )
    (net (code "88") (name "Net-(A64-Pad1)") (class "Default")
      (node (ref "A64") (pin "1") (pinfunction "1_1") (pintype "passive"))
      (node (ref "A64") (pin "2") (pinfunction "2_2") (pintype "passive"))
      (node (ref "IC12") (pin "16") (pinfunction "16_16") (pintype "passive"))
    )
    (net (code "89") (name "Net-(A65-Pad1)") (class "Default")
      (node (ref "A65") (pin "1") (pinfunction "1_1") (pintype "passive"))
      (node (ref "A65") (pin "2") (pinfunction "2_2") (pintype "passive"))
      (node (ref "IC13") (pin "1") (pinfunction "1_1") (pintype "passive"))
    )
    (net (code "90") (name "Net-(A66-Pad1)") (class "Default")
      (node (ref "A66") (pin "1") (pinfunction "1_1") (pintype "passive"))
      (node (ref "A66") (pin "2") (pinfunction "2_2") (pintype "passive"))
      (node (ref "IC13") (pin "2") (pinfunction "2_2") (pintype "passive"))
    )
    (net (code "91") (name "Net-(A67-Pad1)") (class "Default")
      (node (ref "A67") (pin "1") (pinfunction "1_1") (pintype "passive"))
      (node (ref "A67") (pin "2") (pinfunction "2_2") (pintype "passive"))
      (node (ref "IC13") (pin "3") (pinfunction "3_3") (pintype "passive"))
    )
    (net (code "92") (name "Net-(A68-Pad1)") (class "Default")
      (node (ref "A68") (pin "1") (pinfunction "1_1") (pintype "passive"))
      (node (ref "A68") (pin "2") (pinfunction "2_2") (pintype "passive"))
      (node (ref "IC13") (pin "4") (pinfunction "4_4") (pintype "passive"))
    )
    (net (code "93") (name "Net-(A69-Pad1)") (class "Default")
      (node (ref "A69") (pin "1") (pinfunction "1_1") (pintype "passive"))
      (node (ref "A69") (pin "2") (pinfunction "2_2") (pintype "passive"))
      (node (ref "IC13") (pin "5") (pinfunction "5_5") (pintype "passive"))
    )
    (net (code "94") (name "Net-(A70-Pad1)") (class "Default")
      (node (ref "A70") (pin "1") (pinfunction "1_1") (pintype "passive"))
      (node (ref "A70") (pin "2") (pinfunction "2_2") (pintype "passive"))
      (node (ref "IC13") (pin "6") (pinfunction "6_6") (pintype "passive"))
    )
    (net (code "95") (name "Net-(A71-Pad1)") (class "Default")
      (node (ref "A71") (pin "1") (pinfunction "1_1") (pintype "passive"))
      (node (ref "A71") (pin "2") (pinfunction "2_2") (pintype "passive"))
      (node (ref "IC13") (pin "7") (pinfunction "7_7") (pintype "passive"))
    )
    (net (code "96") (name "Net-(A72-Pad1)") (class "Default")
      (node (ref "A72") (pin "1") (pinfunction "1_1") (pintype "passive"))
      (node (ref "A72") (pin "2") (pinfunction "2_2") (pintype "passive"))
      (node (ref "IC13") (pin "8") (pinfunction "8_8") (pintype "passive"))
    )
    (net (code "97") (name "Net-(A73-Pad1)") (class "Default")
      (node (ref "A73") (pin "1") (pinfunction "1_1") (pintype "passive"))
      (node (ref "A73") (pin "2") (pinfunction "2_2") (pintype "passive"))
      (node (ref "IC13") (pin "9") (pinfunction "9_9") (pintype "passive"))
    )
    (net (code "98") (name "Net-(A74-Pad1)") (class "Default")
      (node (ref "A74") (pin "1") (pinfunction "1_1") (pintype "passive"))
      (node (ref "A74") (pin "2") (pinfunction "2_2") (pintype "passive"))
      (node (ref "IC13") (pin "10") (pinfunction "10_10") (pintype "passive"))
    )
    (net (code "99") (name "Net-(A75-Pad1)") (class "Default")
      (node (ref "A75") (pin "1") (pinfunction "1_1") (pintype "passive"))
      (node (ref "A75") (pin "2") (pinfunction "2_2") (pintype "passive"))
      (node (ref "IC13") (pin "11") (pinfunction "11_11") (pintype "passive"))
    )
    (net (code "100") (name "Net-(A76-Pad1)") (class "Default")
      (node (ref "A76") (pin "1") (pinfunction "1_1") (pintype "passive"))
      (node (ref "A76") (pin "2") (pinfunction "2_2") (pintype "passive"))
      (node (ref "IC13") (pin "12") (pinfunction "12_12") (pintype "passive"))
    )
    (net (code "101") (name "Net-(A77-Pad1)") (class "Default")
      (node (ref "A77") (pin "1") (pinfunction "1_1") (pintype "passive"))
      (node (ref "A77") (pin "2") (pinfunction "2_2") (pintype "passive"))
      (node (ref "IC13") (pin "13") (pinfunction "13_13") (pintype "passive"))
    )
    (net (code "102") (name "Net-(A78-Pad1)") (class "Default")
      (node (ref "A78") (pin "1") (pinfunction "1_1") (pintype "passive"))
      (node (ref "A78") (pin "2") (pinfunction "2_2") (pintype "passive"))
      (node (ref "IC13") (pin "14") (pinfunction "14_14") (pintype "passive"))
    )
    (net (code "103") (name "Net-(A79-Pad1)") (class "Default")
      (node (ref "A79") (pin "1") (pinfunction "1_1") (pintype "passive"))
      (node (ref "A79") (pin "2") (pinfunction "2_2") (pintype "passive"))
      (node (ref "IC13") (pin "15") (pinfunction "15_15") (pintype "passive"))
    )
    (net (code "104") (name "Net-(A80-Pad1)") (class "Default")
      (node (ref "A80") (pin "1") (pinfunction "1_1") (pintype "passive"))
      (node (ref "A80") (pin "2") (pinfunction "2_2") (pintype "passive"))
      (node (ref "IC13") (pin "16") (pinfunction "16_16") (pintype "passive"))
    )
    (net (code "105") (name "Net-(A81-Pad1)") (class "Default")
      (node (ref "A81") (pin "1") (pinfunction "1_1") (pintype "passive"))
      (node (ref "A81") (pin "2") (pinfunction "2_2") (pintype "passive"))
      (node (ref "IC14") (pin "1") (pinfunction "1_1") (pintype "passive"))
    )
    (net (code "106") (name "Net-(A82-Pad1)") (class "Default")
      (node (ref "A82") (pin "1") (pinfunction "1_1") (pintype "passive"))
      (node (ref "A82") (pin "2") (pinfunction "2_2") (pintype "passive"))
      (node (ref "IC14") (pin "2") (pinfunction "2_2") (pintype "passive"))
    )
    (net (code "107") (name "Net-(A83-Pad1)") (class "Default")
      (node (ref "A83") (pin "1") (pinfunction "1_1") (pintype "passive"))
      (node (ref "A83") (pin "2") (pinfunction "2_2") (pintype "passive"))
      (node (ref "IC14") (pin "3") (pinfunction "3_3") (pintype "passive"))
    )
    (net (code "108") (name "Net-(A84-Pad1)") (class "Default")
      (node (ref "A84") (pin "1") (pinfunction "1_1") (pintype "passive"))
      (node (ref "A84") (pin "2") (pinfunction "2_2") (pintype "passive"))
      (node (ref "IC14") (pin "4") (pinfunction "4_4") (pintype "passive"))
    )
    (net (code "109") (name "Net-(A85-Pad1)") (class "Default")
      (node (ref "A85") (pin "1") (pinfunction "1_1") (pintype "passive"))
      (node (ref "A85") (pin "2") (pinfunction "2_2") (pintype "passive"))
      (node (ref "IC14") (pin "5") (pinfunction "5_5") (pintype "passive"))
    )
    (net (code "110") (name "Net-(A86-Pad1)") (class "Default")
      (node (ref "A86") (pin "1") (pinfunction "1_1") (pintype "passive"))
      (node (ref "A86") (pin "2") (pinfunction "2_2") (pintype "passive"))
      (node (ref "IC14") (pin "6") (pinfunction "6_6") (pintype "passive"))
    )
    (net (code "111") (name "Net-(A87-Pad1)") (class "Default")
      (node (ref "A87") (pin "1") (pinfunction "1_1") (pintype "passive"))
      (node (ref "A87") (pin "2") (pinfunction "2_2") (pintype "passive"))
      (node (ref "IC14") (pin "7") (pinfunction "7_7") (pintype "passive"))
    )
    (net (code "112") (name "Net-(A88-Pad1)") (class "Default")
      (node (ref "A88") (pin "1") (pinfunction "1_1") (pintype "passive"))
      (node (ref "A88") (pin "2") (pinfunction "2_2") (pintype "passive"))
      (node (ref "IC14") (pin "8") (pinfunction "8_8") (pintype "passive"))
    )
    (net (code "113") (name "Net-(A89-Pad1)") (class "Default")
      (node (ref "A89") (pin "1") (pinfunction "1_1") (pintype "passive"))
      (node (ref "A89") (pin "2") (pinfunction "2_2") (pintype "passive"))
      (node (ref "IC14") (pin "9") (pinfunction "9_9") (pintype "passive"))
    )
    (net (code "114") (name "Net-(A90-Pad1)") (class "Default")
      (node (ref "A90") (pin "1") (pinfunction "1_1") (pintype "passive"))
      (node (ref "A90") (pin "2") (pinfunction "2_2") (pintype "passive"))
      (node (ref "IC14") (pin "10") (pinfunction "10_10") (pintype "passive"))
    )
    (net (code "115") (name "Net-(A91-Pad1)") (class "Default")
      (node (ref "A91") (pin "1") (pinfunction "1_1") (pintype "passive"))
      (node (ref "A91") (pin "2") (pinfunction "2_2") (pintype "passive"))
      (node (ref "IC14") (pin "11") (pinfunction "11_11") (pintype "passive"))
    )
    (net (code "116") (name "Net-(A92-Pad1)") (class "Default")
      (node (ref "A92") (pin "1") (pinfunction "1_1") (pintype "passive"))
      (node (ref "A92") (pin "2") (pinfunction "2_2") (pintype "passive"))
      (node (ref "IC14") (pin "12") (pinfunction "12_12") (pintype "passive"))
    )
    (net (code "117") (name "Net-(A93-Pad1)") (class "Default")
      (node (ref "A93") (pin "1") (pinfunction "1_1") (pintype "passive"))
      (node (ref "A93") (pin "2") (pinfunction "2_2") (pintype "passive"))
      (node (ref "IC14") (pin "13") (pinfunction "13_13") (pintype "passive"))
    )
    (net (code "118") (name "Net-(A94-Pad1)") (class "Default")
      (node (ref "A94") (pin "1") (pinfunction "1_1") (pintype "passive"))
      (node (ref "A94") (pin "2") (pinfunction "2_2") (pintype "passive"))
      (node (ref "IC14") (pin "14") (pinfunction "14_14") (pintype "passive"))
    )
    (net (code "119") (name "Net-(A95-Pad1)") (class "Default")
      (node (ref "A95") (pin "1") (pinfunction "1_1") (pintype "passive"))
      (node (ref "A95") (pin "2") (pinfunction "2_2") (pintype "passive"))
      (node (ref "IC14") (pin "15") (pinfunction "15_15") (pintype "passive"))
    )
    (net (code "120") (name "Net-(A96-Pad1)") (class "Default")
      (node (ref "A96") (pin "1") (pinfunction "1_1") (pintype "passive"))
      (node (ref "A96") (pin "2") (pinfunction "2_2") (pintype "passive"))
      (node (ref "IC14") (pin "16") (pinfunction "16_16") (pintype "passive"))
    )
    (net (code "121") (name "Net-(A97-Pad1)") (class "Default")
      (node (ref "A97") (pin "1") (pinfunction "1_1") (pintype "passive"))
      (node (ref "A97") (pin "2") (pinfunction "2_2") (pintype "passive"))
      (node (ref "IC15") (pin "1") (pinfunction "1_1") (pintype "passive"))
    )
    (net (code "122") (name "Net-(A98-Pad1)") (class "Default")
      (node (ref "A98") (pin "1") (pinfunction "1_1") (pintype "passive"))
      (node (ref "A98") (pin "2") (pinfunction "2_2") (pintype "passive"))
      (node (ref "IC15") (pin "2") (pinfunction "2_2") (pintype "passive"))
    )
    (net (code "123") (name "Net-(A99-Pad1)") (class "Default")
      (node (ref "A99") (pin "1") (pinfunction "1_1") (pintype "passive"))
      (node (ref "A99") (pin "2") (pinfunction "2_2") (pintype "passive"))
      (node (ref "IC15") (pin "3") (pinfunction "3_3") (pintype "passive"))
    )
    (net (code "124") (name "Net-(A100-Pad1)") (class "Default")
      (node (ref "A100") (pin "1") (pinfunction "1_1") (pintype "passive"))
      (node (ref "A100") (pin "2") (pinfunction "2_2") (pintype "passive"))
      (node (ref "IC15") (pin "4") (pinfunction "4_4") (pintype "passive"))
    )
    (net (code "125") (name "Net-(A101-Pad1)") (class "Default")
      (node (ref "A101") (pin "1") (pinfunction "1_1") (pintype "passive"))
      (node (ref "A101") (pin "2") (pinfunction "2_2") (pintype "passive"))
      (node (ref "IC15") (pin "5") (pinfunction "5_5") (pintype "passive"))
    )
    (net (code "126") (name "Net-(A102-Pad1)") (class "Default")
      (node (ref "A102") (pin "1") (pinfunction "1_1") (pintype "passive"))
      (node (ref "A102") (pin "2") (pinfunction "2_2") (pintype "passive"))
      (node (ref "IC15") (pin "6") (pinfunction "6_6") (pintype "passive"))
    )
    (net (code "127") (name "Net-(A103-Pad1)") (class "Default")
      (node (ref "A103") (pin "1") (pinfunction "1_1") (pintype "passive"))
      (node (ref "A103") (pin "2") (pinfunction "2_2") (pintype "passive"))
      (node (ref "IC15") (pin "7") (pinfunction "7_7") (pintype "passive"))
    )
    (net (code "128") (name "Net-(A104-Pad1)") (class "Default")
      (node (ref "A104") (pin "1") (pinfunction "1_1") (pintype "passive"))
      (node (ref "A104") (pin "2") (pinfunction "2_2") (pintype "passive"))
      (node (ref "IC15") (pin "8") (pinfunction "8_8") (pintype "passive"))
    )
    (net (code "129") (name "Net-(A105-Pad1)") (class "Default")
      (node (ref "A105") (pin "1") (pinfunction "1_1") (pintype "passive"))
      (node (ref "A105") (pin "2") (pinfunction "2_2") (pintype "passive"))
      (node (ref "IC15") (pin "9") (pinfunction "9_9") (pintype "passive"))
    )
    (net (code "130") (name "Net-(A106-Pad1)") (class "Default")
      (node (ref "A106") (pin "1") (pinfunction "1_1") (pintype "passive"))
      (node (ref "A106") (pin "2") (pinfunction "2_2") (pintype "passive"))
      (node (ref "IC15") (pin "10") (pinfunction "10_10") (pintype "passive"))
    )
    (net (code "131") (name "Net-(A107-Pad1)") (class "Default")
      (node (ref "A107") (pin "1") (pinfunction "1_1") (pintype "passive"))
      (node (ref "A107") (pin "2") (pinfunction "2_2") (pintype "passive"))
      (node (ref "IC15") (pin "11") (pinfunction "11_11") (pintype "passive"))
    )
    (net (code "132") (name "Net-(A108-Pad1)") (class "Default")
      (node (ref "A108") (pin "1") (pinfunction "1_1") (pintype "passive"))
      (node (ref "A108") (pin "2") (pinfunction "2_2") (pintype "passive"))
      (node (ref "IC15") (pin "12") (pinfunction "12_12") (pintype "passive"))
    )
    (net (code "133") (name "Net-(A109-Pad1)") (class "Default")
      (node (ref "A109") (pin "1") (pinfunction "1_1") (pintype "passive"))
      (node (ref "A109") (pin "2") (pinfunction "2_2") (pintype "passive"))
      (node (ref "IC15") (pin "13") (pinfunction "13_13") (pintype "passive"))
    )
    (net (code "134") (name "Net-(A110-Pad1)") (class "Default")
      (node (ref "A110") (pin "1") (pinfunction "1_1") (pintype "passive"))
      (node (ref "A110") (pin "2") (pinfunction "2_2") (pintype "passive"))
      (node (ref "IC15") (pin "14") (pinfunction "14_14") (pintype "passive"))
    )
    (net (code "135") (name "Net-(A111-Pad1)") (class "Default")
      (node (ref "A111") (pin "1") (pinfunction "1_1") (pintype "passive"))
      (node (ref "A111") (pin "2") (pinfunction "2_2") (pintype "passive"))
      (node (ref "IC15") (pin "15") (pinfunction "15_15") (pintype "passive"))
    )
    (net (code "136") (name "Net-(A112-Pad1)") (class "Default")
      (node (ref "A112") (pin "1") (pinfunction "1_1") (pintype "passive"))
      (node (ref "A112") (pin "2") (pinfunction "2_2") (pintype "passive"))
      (node (ref "IC15") (pin "16") (pinfunction "16_16") (pintype "passive"))
    )
    (net (code "137") (name "Net-(A113-Pad1)") (class "Default")
      (node (ref "A113") (pin "1") (pinfunction "1_1") (pintype "passive"))
      (node (ref "A113") (pin "2") (pinfunction "2_2") (pintype "passive"))
      (node (ref "IC16") (pin "1") (pinfunction "1_1") (pintype "passive"))
    )
    (net (code "138") (name "Net-(A114-Pad1)") (class "Default")
      (node (ref "A114") (pin "1") (pinfunction "1_1") (pintype "passive"))
      (node (ref "A114") (pin "2") (pinfunction "2_2") (pintype "passive"))
      (node (ref "IC16") (pin "2") (pinfunction "2_2") (pintype "passive"))
    )
    (net (code "139") (name "Net-(A115-Pad1)") (class "Default")
      (node (ref "A115") (pin "1") (pinfunction "1_1") (pintype "passive"))
      (node (ref "A115") (pin "2") (pinfunction "2_2") (pintype "passive"))
      (node (ref "IC16") (pin "3") (pinfunction "3_3") (pintype "passive"))
    )
    (net (code "140") (name "Net-(A116-Pad1)") (class "Default")
      (node (ref "A116") (pin "1") (pinfunction "1_1") (pintype "passive"))
      (node (ref "A116") (pin "2") (pinfunction "2_2") (pintype "passive"))
      (node (ref "IC16") (pin "4") (pinfunction "4_4") (pintype "passive"))
    )
    (net (code "141") (name "Net-(A117-Pad1)") (class "Default")
      (node (ref "A117") (pin "1") (pinfunction "1_1") (pintype "passive"))
      (node (ref "A117") (pin "2") (pinfunction "2_2") (pintype "passive"))
      (node (ref "IC16") (pin "5") (pinfunction "5_5") (pintype "passive"))
    )
    (net (code "142") (name "Net-(A118-Pad1)") (class "Default")
      (node (ref "A118") (pin "1") (pinfunction "1_1") (pintype "passive"))
      (node (ref "A118") (pin "2") (pinfunction "2_2") (pintype "passive"))
      (node (ref "IC16") (pin "6") (pinfunction "6_6") (pintype "passive"))
    )
    (net (code "143") (name "Net-(A119-Pad1)") (class "Default")
      (node (ref "A119") (pin "1") (pinfunction "1_1") (pintype "passive"))
      (node (ref "A119") (pin "2") (pinfunction "2_2") (pintype "passive"))
      (node (ref "IC16") (pin "7") (pinfunction "7_7") (pintype "passive"))
    )
    (net (code "144") (name "Net-(A120-Pad1)") (class "Default")
      (node (ref "A120") (pin "1") (pinfunction "1_1") (pintype "passive"))
      (node (ref "A120") (pin "2") (pinfunction "2_2") (pintype "passive"))
      (node (ref "IC16") (pin "8") (pinfunction "8_8") (pintype "passive"))
    )
    (net (code "145") (name "Net-(A121-Pad1)") (class "Default")
      (node (ref "A121") (pin "1") (pinfunction "1_1") (pintype "passive"))
      (node (ref "A121") (pin "2") (pinfunction "2_2") (pintype "passive"))
      (node (ref "IC16") (pin "9") (pinfunction "9_9") (pintype "passive"))
    )
    (net (code "146") (name "Net-(A122-Pad1)") (class "Default")
      (node (ref "A122") (pin "1") (pinfunction "1_1") (pintype "passive"))
      (node (ref "A122") (pin "2") (pinfunction "2_2") (pintype "passive"))
      (node (ref "IC16") (pin "10") (pinfunction "10_10") (pintype "passive"))
    )
    (net (code "147") (name "Net-(A123-Pad1)") (class "Default")
      (node (ref "A123") (pin "1") (pinfunction "1_1") (pintype "passive"))
      (node (ref "A123") (pin "2") (pinfunction "2_2") (pintype "passive"))
      (node (ref "IC16") (pin "11") (pinfunction "11_11") (pintype "passive"))
    )
    (net (code "148") (name "Net-(A124-Pad1)") (class "Default")
      (node (ref "A124") (pin "1") (pinfunction "1_1") (pintype "passive"))
      (node (ref "A124") (pin "2") (pinfunction "2_2") (pintype "passive"))
      (node (ref "IC16") (pin "12") (pinfunction "12_12") (pintype "passive"))
    )
    (net (code "149") (name "Net-(A125-Pad1)") (class "Default")
      (node (ref "A125") (pin "1") (pinfunction "1_1") (pintype "passive"))
      (node (ref "A125") (pin "2") (pinfunction "2_2") (pintype "passive"))
      (node (ref "IC16") (pin "13") (pinfunction "13_13") (pintype "passive"))
    )
    (net (code "150") (name "Net-(A126-Pad1)") (class "Default")
      (node (ref "A126") (pin "1") (pinfunction "1_1") (pintype "passive"))
      (node (ref "A126") (pin "2") (pinfunction "2_2") (pintype "passive"))
      (node (ref "IC16") (pin "14") (pinfunction "14_14") (pintype "passive"))
    )
    (net (code "151") (name "Net-(A127-Pad1)") (class "Default")
      (node (ref "A127") (pin "1") (pinfunction "1_1") (pintype "passive"))
      (node (ref "A127") (pin "2") (pinfunction "2_2") (pintype "passive"))
      (node (ref "IC16") (pin "15") (pinfunction "15_15") (pintype "passive"))
    )
    (net (code "152") (name "Net-(A128-Pad1)") (class "Default")
      (node (ref "A128") (pin "1") (pinfunction "1_1") (pintype "passive"))
      (node (ref "A128") (pin "2") (pinfunction "2_2") (pintype "passive"))
      (node (ref "IC16") (pin "16") (pinfunction "16_16") (pintype "passive"))
    )
    (net (code "153") (name "Net-(A129-Pad1)") (class "Default")
      (node (ref "A129") (pin "1") (pinfunction "1_1") (pintype "passive"))
      (node (ref "A129") (pin "2") (pinfunction "2_2") (pintype "passive"))
      (node (ref "IC17") (pin "1") (pinfunction "1_1") (pintype "passive"))
    )
    (net (code "154") (name "Net-(A130-Pad1)") (class "Default")
      (node (ref "A130") (pin "1") (pinfunction "1_1") (pintype "passive"))
      (node (ref "A130") (pin "2") (pinfunction "2_2") (pintype "passive"))
      (node (ref "IC17") (pin "2") (pinfunction "2_2") (pintype "passive"))
    )
    (net (code "155") (name "Net-(A131-Pad1)") (class "Default")
      (node (ref "A131") (pin "1") (pinfunction "1_1") (pintype "passive"))
      (node (ref "A131") (pin "2") (pinfunction "2_2") (pintype "passive"))
      (node (ref "IC17") (pin "3") (pinfunction "3_3") (pintype "passive"))
    )
    (net (code "156") (name "Net-(A132-Pad1)") (class "Default")
      (node (ref "A132") (pin "1") (pinfunction "1_1") (pintype "passive"))
      (node (ref "A132") (pin "2") (pinfunction "2_2") (pintype "passive"))
      (node (ref "IC17") (pin "4") (pinfunction "4_4") (pintype "passive"))
    )
    (net (code "157") (name "Net-(A133-Pad1)") (class "Default")
      (node (ref "A133") (pin "1") (pinfunction "1_1") (pintype "passive"))
      (node (ref "A133") (pin "2") (pinfunction "2_2") (pintype "passive"))
      (node (ref "IC17") (pin "5") (pinfunction "5_5") (pintype "passive"))
    )
    (net (code "158") (name "Net-(A134-Pad1)") (class "Default")
      (node (ref "A134") (pin "1") (pinfunction "1_1") (pintype "passive"))
      (node (ref "A134") (pin "2") (pinfunction "2_2") (pintype "passive"))
      (node (ref "IC17") (pin "6") (pinfunction "6_6") (pintype "passive"))
    )
    (net (code "159") (name "Net-(A135-Pad1)") (class "Default")
      (node (ref "A135") (pin "1") (pinfunction "1_1") (pintype "passive"))
      (node (ref "A135") (pin "2") (pinfunction "2_2") (pintype "passive"))
      (node (ref "IC17") (pin "7") (pinfunction "7_7") (pintype "passive"))
    )
    (net (code "160") (name "Net-(A136-Pad1)") (class "Default")
      (node (ref "A136") (pin "1") (pinfunction "1_1") (pintype "passive"))
      (node (ref "A136") (pin "2") (pinfunction "2_2") (pintype "passive"))
      (node (ref "IC17") (pin "8") (pinfunction "8_8") (pintype "passive"))
    )
    (net (code "161") (name "Net-(A137-Pad1)") (class "Default")
      (node (ref "A137") (pin "1") (pinfunction "1_1") (pintype "passive"))
      (node (ref "A137") (pin "2") (pinfunction "2_2") (pintype "passive"))
      (node (ref "IC17") (pin "9") (pinfunction "9_9") (pintype "passive"))
    )
    (net (code "162") (name "Net-(A138-Pad1)") (class "Default")
      (node (ref "A138") (pin "1") (pinfunction "1_1") (pintype "passive"))
      (node (ref "A138") (pin "2") (pinfunction "2_2") (pintype "passive"))
      (node (ref "IC17") (pin "10") (pinfunction "10_10") (pintype "passive"))
    )
    (net (code "163") (name "Net-(A139-Pad1)") (class "Default")
      (node (ref "A139") (pin "1") (pinfunction "1_1") (pintype "passive"))
      (node (ref "A139") (pin "2") (pinfunction "2_2") (pintype "passive"))
      (node (ref "IC17") (pin "11") (pinfunction "11_11") (pintype "passive"))
    )
    (net (code "164") (name "Net-(A140-Pad1)") (class "Default")
      (node (ref "A140") (pin "1") (pinfunction "1_1") (pintype "passive"))
      (node (ref "A140") (pin "2") (pinfunction "2_2") (pintype "passive"))
      (node (ref "IC17") (pin "12") (pinfunction "12_12") (pintype "passive"))
    )
    (net (code "165") (name "Net-(A141-Pad1)") (class "Default")
      (node (ref "A141") (pin "1") (pinfunction "1_1") (pintype "passive"))
      (node (ref "A141") (pin "2") (pinfunction "2_2") (pintype "passive"))
      (node (ref "IC17") (pin "13") (pinfunction "13_13") (pintype "passive"))
    )
    (net (code "166") (name "Net-(A142-Pad1)") (class "Default")
      (node (ref "A142") (pin "1") (pinfunction "1_1") (pintype "passive"))
      (node (ref "A142") (pin "2") (pinfunction "2_2") (pintype "passive"))
      (node (ref "IC17") (pin "14") (pinfunction "14_14") (pintype "passive"))
    )
    (net (code "167") (name "Net-(A143-Pad1)") (class "Default")
      (node (ref "A143") (pin "1") (pinfunction "1_1") (pintype "passive"))
      (node (ref "A143") (pin "2") (pinfunction "2_2") (pintype "passive"))
      (node (ref "IC17") (pin "15") (pinfunction "15_15") (pintype "passive"))
    )
    (net (code "168") (name "Net-(A144-Pad1)") (class "Default")
      (node (ref "A144") (pin "1") (pinfunction "1_1") (pintype "passive"))
      (node (ref "A144") (pin "2") (pinfunction "2_2") (pintype "passive"))
      (node (ref "IC17") (pin "16") (pinfunction "16_16") (pintype "passive"))
    )
    (net (code "169") (name "Net-(A145-Pad1)") (class "Default")
      (node (ref "A145") (pin "1") (pinfunction "1_1") (pintype "passive"))
      (node (ref "A145") (pin "2") (pinfunction "2_2") (pintype "passive"))
      (node (ref "IC18") (pin "1") (pinfunction "1_1") (pintype "passive"))
    )
    (net (code "170") (name "Net-(A146-Pad1)") (class "Default")
      (node (ref "A146") (pin "1") (pinfunction "1_1") (pintype "passive"))
      (node (ref "A146") (pin "2") (pinfunction "2_2") (pintype "passive"))
      (node (ref "IC18") (pin "2") (pinfunction "2_2") (pintype "passive"))
    )
    (net (code "171") (name "Net-(A147-Pad1)") (class "Default")
      (node (ref "A147") (pin "1") (pinfunction "1_1") (pintype "passive"))
      (node (ref "A147") (pin "2") (pinfunction "2_2") (pintype "passive"))
      (node (ref "IC18") (pin "3") (pinfunction "3_3") (pintype "passive"))
    )
    (net (code "172") (name "Net-(A148-Pad1)") (class "Default")
      (node (ref "A148") (pin "1") (pinfunction "1_1") (pintype "passive"))
      (node (ref "A148") (pin "2") (pinfunction "2_2") (pintype "passive"))
      (node (ref "IC18") (pin "4") (pinfunction "4_4") (pintype "passive"))
    )
    (net (code "173") (name "Net-(A149-Pad1)") (class "Default")
      (node (ref "A149") (pin "1") (pinfunction "1_1") (pintype "passive"))
      (node (ref "A149") (pin "2") (pinfunction "2_2") (pintype "passive"))
      (node (ref "IC18") (pin "5") (pinfunction "5_5") (pintype "passive"))
    )
    (net (code "174") (name "Net-(A150-Pad1)") (class "Default")
      (node (ref "A150") (pin "1") (pinfunction "1_1") (pintype "passive"))
      (node (ref "A150") (pin "2") (pinfunction "2_2") (pintype "passive"))
      (node (ref "IC18") (pin "6") (pinfunction "6_6") (pintype "passive"))
    )
    (net (code "175") (name "Net-(A151-Pad1)") (class "Default")
      (node (ref "A151") (pin "1") (pinfunction "1_1") (pintype "passive"))
      (node (ref "A151") (pin "2") (pinfunction "2_2") (pintype "passive"))
      (node (ref "IC18") (pin "7") (pinfunction "7_7") (pintype "passive"))
    )
    (net (code "176") (name "Net-(A152-Pad1)") (class "Default")
      (node (ref "A152") (pin "1") (pinfunction "1_1") (pintype "passive"))
      (node (ref "A152") (pin "2") (pinfunction "2_2") (pintype "passive"))
      (node (ref "IC18") (pin "8") (pinfunction "8_8") (pintype "passive"))
    )
    (net (code "177") (name "Net-(A153-Pad1)") (class "Default")
      (node (ref "A153") (pin "1") (pinfunction "1_1") (pintype "passive"))
      (node (ref "A153") (pin "2") (pinfunction "2_2") (pintype "passive"))
      (node (ref "IC18") (pin "9") (pinfunction "9_9") (pintype "passive"))
    )
    (net (code "178") (name "Net-(A154-Pad1)") (class "Default")
      (node (ref "A154") (pin "1") (pinfunction "1_1") (pintype "passive"))
      (node (ref "A154") (pin "2") (pinfunction "2_2") (pintype "passive"))
      (node (ref "IC18") (pin "10") (pinfunction "10_10") (pintype "passive"))
    )
    (net (code "179") (name "Net-(A155-Pad1)") (class "Default")
      (node (ref "A155") (pin "1") (pinfunction "1_1") (pintype "passive"))
      (node (ref "A155") (pin "2") (pinfunction "2_2") (pintype "passive"))
      (node (ref "IC18") (pin "11") (pinfunction "11_11") (pintype "passive"))
    )
    (net (code "180") (name "Net-(A156-Pad1)") (class "Default")
      (node (ref "A156") (pin "1") (pinfunction "1_1") (pintype "passive"))
      (node (ref "A156") (pin "2") (pinfunction "2_2") (pintype "passive"))
      (node (ref "IC18") (pin "12") (pinfunction "12_12") (pintype "passive"))
    )
    (net (code "181") (name "Net-(A157-Pad1)") (class "Default")
      (node (ref "A157") (pin "1") (pinfunction "1_1") (pintype "passive"))
      (node (ref "A157") (pin "2") (pinfunction "2_2") (pintype "passive"))
      (node (ref "IC18") (pin "13") (pinfunction "13_13") (pintype "passive"))
    )
    (net (code "182") (name "Net-(A158-Pad1)") (class "Default")
      (node (ref "A158") (pin "1") (pinfunction "1_1") (pintype "passive"))
      (node (ref "A158") (pin "2") (pinfunction "2_2") (pintype "passive"))
      (node (ref "IC18") (pin "14") (pinfunction "14_14") (pintype "passive"))
    )
    (net (code "183") (name "Net-(A159-Pad1)") (class "Default")
      (node (ref "A159") (pin "1") (pinfunction "1_1") (pintype "passive"))
      (node (ref "A159") (pin "2") (pinfunction "2_2") (pintype "passive"))
      (node (ref "IC18") (pin "15") (pinfunction "15_15") (pintype "passive"))
    )
    (net (code "184") (name "Net-(A160-Pad1)") (class "Default")
      (node (ref "A160") (pin "1") (pinfunction "1_1") (pintype "passive"))
      (node (ref "A160") (pin "2") (pinfunction "2_2") (pintype "passive"))
      (node (ref "IC18") (pin "16") (pinfunction "16_16") (pintype "passive"))
    )
    (net (code "185") (name "Net-(A161-Pad1)") (class "Default")
      (node (ref "A161") (pin "1") (pinfunction "1_1") (pintype "passive"))
      (node (ref "A161") (pin "2") (pinfunction "2_2") (pintype "passive"))
      (node (ref "IC19") (pin "1") (pinfunction "1_1") (pintype "passive"))
    )
    (net (code "186") (name "Net-(A162-Pad1)") (class "Default")
      (node (ref "A162") (pin "1") (pinfunction "1_1") (pintype "passive"))
      (node (ref "A162") (pin "2") (pinfunction "2_2") (pintype "passive"))
      (node (ref "IC19") (pin "2") (pinfunction "2_2") (pintype "passive"))
    )
    (net (code "187") (name "Net-(A163-Pad1)") (class "Default")
      (node (ref "A163") (pin "1") (pinfunction "1_1") (pintype "passive"))
      (node (ref "A163") (pin "2") (pinfunction "2_2") (pintype "passive"))
      (node (ref "IC19") (pin "3") (pinfunction "3_3") (pintype "passive"))
    )
    (net (code "188") (name "Net-(A164-Pad1)") (class "Default")
      (node (ref "A164") (pin "1") (pinfunction "1_1") (pintype "passive"))
      (node (ref "A164") (pin "2") (pinfunction "2_2") (pintype "passive"))
      (node (ref "IC19") (pin "4") (pinfunction "4_4") (pintype "passive"))
    )
    (net (code "189") (name "Net-(A165-Pad1)") (class "Default")
      (node (ref "A165") (pin "1") (pinfunction "1_1") (pintype "passive"))
      (node (ref "A165") (pin "2") (pinfunction "2_2") (pintype "passive"))
      (node (ref "IC19") (pin "5") (pinfunction "5_5") (pintype "passive"))
    )
    (net (code "190") (name "Net-(A166-Pad1)") (class "Default")
      (node (ref "A166") (pin "1") (pinfunction "1_1") (pintype "passive"))
      (node (ref "A166") (pin "2") (pinfunction "2_2") (pintype "passive"))
      (node (ref "IC19") (pin "6") (pinfunction "6_6") (pintype "passive"))
    )
    (net (code "191") (name "Net-(A167-Pad1)") (class "Default")
      (node (ref "A167") (pin "1") (pinfunction "1_1") (pintype "passive"))
      (node (ref "A167") (pin "2") (pinfunction "2_2") (pintype "passive"))
      (node (ref "IC19") (pin "7") (pinfunction "7_7") (pintype "passive"))
    )
    (net (code "192") (name "Net-(A168-Pad1)") (class "Default")
      (node (ref "A168") (pin "1") (pinfunction "1_1") (pintype "passive"))
      (node (ref "A168") (pin "2") (pinfunction "2_2") (pintype "passive"))
      (node (ref "IC19") (pin "8") (pinfunction "8_8") (pintype "passive"))
    )
    (net (code "193") (name "Net-(A169-Pad1)") (class "Default")
      (node (ref "A169") (pin "1") (pinfunction "1_1") (pintype "passive"))
      (node (ref "A169") (pin "2") (pinfunction "2_2") (pintype "passive"))
      (node (ref "IC19") (pin "9") (pinfunction "9_9") (pintype "passive"))
    )
    (net (code "194") (name "Net-(A170-Pad1)") (class "Default")
      (node (ref "A170") (pin "1") (pinfunction "1_1") (pintype "passive"))
      (node (ref "A170") (pin "2") (pinfunction "2_2") (pintype "passive"))
      (node (ref "IC19") (pin "10") (pinfunction "10_10") (pintype "passive"))
    )
    (net (code "195") (name "Net-(A171-Pad1)") (class "Default")
      (node (ref "A171") (pin "1") (pinfunction "1_1") (pintype "passive"))
      (node (ref "A171") (pin "2") (pinfunction "2_2") (pintype "passive"))
      (node (ref "IC19") (pin "11") (pinfunction "11_11") (pintype "passive"))
    )
    (net (code "196") (name "Net-(A172-Pad1)") (class "Default")
      (node (ref "A172") (pin "1") (pinfunction "1_1") (pintype "passive"))
      (node (ref "A172") (pin "2") (pinfunction "2_2") (pintype "passive"))
      (node (ref "IC19") (pin "12") (pinfunction "12_12") (pintype "passive"))
    )
    (net (code "197") (name "Net-(A173-Pad1)") (class "Default")
      (node (ref "A173") (pin "1") (pinfunction "1_1") (pintype "passive"))
      (node (ref "A173") (pin "2") (pinfunction "2_2") (pintype "passive"))
      (node (ref "IC19") (pin "13") (pinfunction "13_13") (pintype "passive"))
    )
    (net (code "198") (name "Net-(A174-Pad1)") (class "Default")
      (node (ref "A174") (pin "1") (pinfunction "1_1") (pintype "passive"))
      (node (ref "A174") (pin "2") (pinfunction "2_2") (pintype "passive"))
      (node (ref "IC19") (pin "14") (pinfunction "14_14") (pintype "passive"))
    )
    (net (code "199") (name "Net-(A175-Pad1)") (class "Default")
      (node (ref "A175") (pin "1") (pinfunction "1_1") (pintype "passive"))
      (node (ref "A175") (pin "2") (pinfunction "2_2") (pintype "passive"))
      (node (ref "IC19") (pin "15") (pinfunction "15_15") (pintype "passive"))
    )
    (net (code "200") (name "Net-(A176-Pad1)") (class "Default")
      (node (ref "A176") (pin "1") (pinfunction "1_1") (pintype "passive"))
      (node (ref "A176") (pin "2") (pinfunction "2_2") (pintype "passive"))
      (node (ref "IC19") (pin "16") (pinfunction "16_16") (pintype "passive"))
    )
    (net (code "201") (name "Net-(A177-Pad1)") (class "Default")
      (node (ref "A177") (pin "1") (pinfunction "1_1") (pintype "passive"))
      (node (ref "A177") (pin "2") (pinfunction "2_2") (pintype "passive"))
      (node (ref "IC20") (pin "1") (pinfunction "1_1") (pintype "passive"))
    )
    (net (code "202") (name "Net-(A178-Pad1)") (class "Default")
      (node (ref "A178") (pin "1") (pinfunction "1_1") (pintype "passive"))
      (node (ref "A178") (pin "2") (pinfunction "2_2") (pintype "passive"))
      (node (ref "IC20") (pin "2") (pinfunction "2_2") (pintype "passive"))
    )
    (net (code "203") (name "Net-(A179-Pad1)") (class "Default")
      (node (ref "A179") (pin "1") (pinfunction "1_1") (pintype "passive"))
      (node (ref "A179") (pin "2") (pinfunction "2_2") (pintype "passive"))
      (node (ref "IC20") (pin "3") (pinfunction "3_3") (pintype "passive"))
    )
    (net (code "204") (name "Net-(A180-Pad1)") (class "Default")
      (node (ref "A180") (pin "1") (pinfunction "1_1") (pintype "passive"))
      (node (ref "A180") (pin "2") (pinfunction "2_2") (pintype "passive"))
      (node (ref "IC20") (pin "4") (pinfunction "4_4") (pintype "passive"))
    )
    (net (code "205") (name "Net-(A181-Pad1)") (class "Default")
      (node (ref "A181") (pin "1") (pinfunction "1_1") (pintype "passive"))
      (node (ref "A181") (pin "2") (pinfunction "2_2") (pintype "passive"))
      (node (ref "IC20") (pin "5") (pinfunction "5_5") (pintype "passive"))
    )
    (net (code "206") (name "Net-(A182-Pad1)") (class "Default")
      (node (ref "A182") (pin "1") (pinfunction "1_1") (pintype "passive"))
      (node (ref "A182") (pin "2") (pinfunction "2_2") (pintype "passive"))
      (node (ref "IC20") (pin "6") (pinfunction "6_6") (pintype "passive"))
    )
    (net (code "207") (name "Net-(A183-Pad1)") (class "Default")
      (node (ref "A183") (pin "1") (pinfunction "1_1") (pintype "passive"))
      (node (ref "A183") (pin "2") (pinfunction "2_2") (pintype "passive"))
      (node (ref "IC20") (pin "7") (pinfunction "7_7") (pintype "passive"))
    )
    (net (code "208") (name "Net-(A184-Pad1)") (class "Default")
      (node (ref "A184") (pin "1") (pinfunction "1_1") (pintype "passive"))
      (node (ref "A184") (pin "2") (pinfunction "2_2") (pintype "passive"))
      (node (ref "IC20") (pin "8") (pinfunction "8_8") (pintype "passive"))
    )
    (net (code "209") (name "Net-(A185-Pad1)") (class "Default")
      (node (ref "A185") (pin "1") (pinfunction "1_1") (pintype "passive"))
      (node (ref "A185") (pin "2") (pinfunction "2_2") (pintype "passive"))
      (node (ref "IC20") (pin "9") (pinfunction "9_9") (pintype "passive"))
    )
    (net (code "210") (name "Net-(A186-Pad1)") (class "Default")
      (node (ref "A186") (pin "1") (pinfunction "1_1") (pintype "passive"))
      (node (ref "A186") (pin "2") (pinfunction "2_2") (pintype "passive"))
      (node (ref "IC20") (pin "10") (pinfunction "10_10") (pintype "passive"))
    )
    (net (code "211") (name "Net-(A187-Pad1)") (class "Default")
      (node (ref "A187") (pin "1") (pinfunction "1_1") (pintype "passive"))
      (node (ref "A187") (pin "2") (pinfunction "2_2") (pintype "passive"))
      (node (ref "IC20") (pin "11") (pinfunction "11_11") (pintype "passive"))
    )
    (net (code "212") (name "Net-(A188-Pad1)") (class "Default")
      (node (ref "A188") (pin "1") (pinfunction "1_1") (pintype "passive"))
      (node (ref "A188") (pin "2") (pinfunction "2_2") (pintype "passive"))
      (node (ref "IC20") (pin "12") (pinfunction "12_12") (pintype "passive"))
    )
    (net (code "213") (name "Net-(A189-Pad1)") (class "Default")
      (node (ref "A189") (pin "1") (pinfunction "1_1") (pintype "passive"))
      (node (ref "A189") (pin "2") (pinfunction "2_2") (pintype "passive"))
      (node (ref "IC20") (pin "13") (pinfunction "13_13") (pintype "passive"))
    )
    (net (code "214") (name "Net-(A190-Pad1)") (class "Default")
      (node (ref "A190") (pin "1") (pinfunction "1_1") (pintype "passive"))
      (node (ref "A190") (pin "2") (pinfunction "2_2") (pintype "passive"))
      (node (ref "IC20") (pin "14") (pinfunction "14_14") (pintype "passive"))
    )
    (net (code "215") (name "Net-(A191-Pad1)") (class "Default")
      (node (ref "A191") (pin "1") (pinfunction "1_1") (pintype "passive"))
      (node (ref "A191") (pin "2") (pinfunction "2_2") (pintype "passive"))
      (node (ref "IC20") (pin "15") (pinfunction "15_15") (pintype "passive"))
    )
    (net (code "216") (name "Net-(A192-Pad1)") (class "Default")
      (node (ref "A192") (pin "1") (pinfunction "1_1") (pintype "passive"))
      (node (ref "A192") (pin "2") (pinfunction "2_2") (pintype "passive"))
      (node (ref "IC20") (pin "16") (pinfunction "16_16") (pintype "passive"))
    )
    (net (code "217") (name "Net-(A193-Pad1)") (class "Default")
      (node (ref "A193") (pin "1") (pinfunction "1_1") (pintype "passive"))
      (node (ref "A193") (pin "2") (pinfunction "2_2") (pintype "passive"))
      (node (ref "IC21") (pin "1") (pinfunction "1_1") (pintype "passive"))
    )
    (net (code "218") (name "Net-(A194-Pad1)") (class "Default")
      (node (ref "A194") (pin "1") (pinfunction "1_1") (pintype "passive"))
      (node (ref "A194") (pin "2") (pinfunction "2_2") (pintype "passive"))
      (node (ref "IC21") (pin "2") (pinfunction "2_2") (pintype "passive"))
    )
    (net (code "219") (name "Net-(A195-Pad1)") (class "Default")
      (node (ref "A195") (pin "1") (pinfunction "1_1") (pintype "passive"))
      (node (ref "A195") (pin "2") (pinfunction "2_2") (pintype "passive"))
      (node (ref "IC21") (pin "3") (pinfunction "3_3") (pintype "passive"))
    )
    (net (code "220") (name "Net-(A196-Pad1)") (class "Default")
      (node (ref "A196") (pin "1") (pinfunction "1_1") (pintype "passive"))
      (node (ref "A196") (pin "2") (pinfunction "2_2") (pintype "passive"))
      (node (ref "IC21") (pin "4") (pinfunction "4_4") (pintype "passive"))
    )
    (net (code "221") (name "Net-(A197-Pad1)") (class "Default")
      (node (ref "A197") (pin "1") (pinfunction "1_1") (pintype "passive"))
      (node (ref "A197") (pin "2") (pinfunction "2_2") (pintype "passive"))
      (node (ref "IC21") (pin "5") (pinfunction "5_5") (pintype "passive"))
    )
    (net (code "222") (name "Net-(A198-Pad1)") (class "Default")
      (node (ref "A198") (pin "1") (pinfunction "1_1") (pintype "passive"))
      (node (ref "A198") (pin "2") (pinfunction "2_2") (pintype "passive"))
      (node (ref "IC21") (pin "6") (pinfunction "6_6") (pintype "passive"))
    )
    (net (code "223") (name "Net-(A199-Pad1)") (class "Default")
      (node (ref "A199") (pin "1") (pinfunction "1_1") (pintype "passive"))
      (node (ref "A199") (pin "2") (pinfunction "2_2") (pintype "passive"))
      (node (ref "IC21") (pin "7") (pinfunction "7_7") (pintype "passive"))
    )
    (net (code "224") (name "Net-(A200-Pad1)") (class "Default")
      (node (ref "A200") (pin "1") (pinfunction "1_1") (pintype "passive"))
      (node (ref "A200") (pin "2") (pinfunction "2_2") (pintype "passive"))
      (node (ref "IC21") (pin "8") (pinfunction "8_8") (pintype "passive"))
    )
    (net (code "225") (name "Net-(A201-Pad1)") (class "Default")
      (node (ref "A201") (pin "1") (pinfunction "1_1") (pintype "passive"))
      (node (ref "A201") (pin "2") (pinfunction "2_2") (pintype "passive"))
      (node (ref "IC21") (pin "9") (pinfunction "9_9") (pintype "passive"))
    )
    (net (code "226") (name "Net-(A202-Pad1)") (class "Default")
      (node (ref "A202") (pin "1") (pinfunction "1_1") (pintype "passive"))
      (node (ref "A202") (pin "2") (pinfunction "2_2") (pintype "passive"))
      (node (ref "IC21") (pin "10") (pinfunction "10_10") (pintype "passive"))
    )
    (net (code "227") (name "Net-(A203-Pad1)") (class "Default")
      (node (ref "A203") (pin "1") (pinfunction "1_1") (pintype "passive"))
      (node (ref "A203") (pin "2") (pinfunction "2_2") (pintype "passive"))
      (node (ref "IC21") (pin "11") (pinfunction "11_11") (pintype "passive"))
    )
    (net (code "228") (name "Net-(A204-Pad1)") (class "Default")
      (node (ref "A204") (pin "1") (pinfunction "1_1") (pintype "passive"))
      (node (ref "A204") (pin "2") (pinfunction "2_2") (pintype "passive"))
      (node (ref "IC21") (pin "12") (pinfunction "12_12") (pintype "passive"))
    )
    (net (code "229") (name "Net-(A205-Pad1)") (class "Default")
      (node (ref "A205") (pin "1") (pinfunction "1_1") (pintype "passive"))
      (node (ref "A205") (pin "2") (pinfunction "2_2") (pintype "passive"))
      (node (ref "IC21") (pin "13") (pinfunction "13_13") (pintype "passive"))
    )
    (net (code "230") (name "Net-(A206-Pad1)") (class "Default")
      (node (ref "A206") (pin "1") (pinfunction "1_1") (pintype "passive"))
      (node (ref "A206") (pin "2") (pinfunction "2_2") (pintype "passive"))
      (node (ref "IC21") (pin "14") (pinfunction "14_14") (pintype "passive"))
    )
    (net (code "231") (name "Net-(A207-Pad1)") (class "Default")
      (node (ref "A207") (pin "1") (pinfunction "1_1") (pintype "passive"))
      (node (ref "A207") (pin "2") (pinfunction "2_2") (pintype "passive"))
      (node (ref "IC21") (pin "15") (pinfunction "15_15") (pintype "passive"))
    )
    (net (code "232") (name "Net-(A208-Pad1)") (class "Default")
      (node (ref "A208") (pin "1") (pinfunction "1_1") (pintype "passive"))
      (node (ref "A208") (pin "2") (pinfunction "2_2") (pintype "passive"))
      (node (ref "IC21") (pin "16") (pinfunction "16_16") (pintype "passive"))
    )
    (net (code "233") (name "Net-(A209-Pad1)") (class "Default")
      (node (ref "A209") (pin "1") (pinfunction "1_1") (pintype "passive"))
      (node (ref "A209") (pin "2") (pinfunction "2_2") (pintype "passive"))
      (node (ref "IC22") (pin "1") (pinfunction "1_1") (pintype "passive"))
    )
    (net (code "234") (name "Net-(A210-Pad1)") (class "Default")
      (node (ref "A210") (pin "1") (pinfunction "1_1") (pintype "passive"))
      (node (ref "A210") (pin "2") (pinfunction "2_2") (pintype "passive"))
      (node (ref "IC22") (pin "2") (pinfunction "2_2") (pintype "passive"))
    )
    (net (code "235") (name "Net-(A211-Pad1)") (class "Default")
      (node (ref "A211") (pin "1") (pinfunction "1_1") (pintype "passive"))
      (node (ref "A211") (pin "2") (pinfunction "2_2") (pintype "passive"))
      (node (ref "IC22") (pin "3") (pinfunction "3_3") (pintype "passive"))
    )
    (net (code "236") (name "Net-(A212-Pad1)") (class "Default")
      (node (ref "A212") (pin "1") (pinfunction "1_1") (pintype "passive"))
      (node (ref "A212") (pin "2") (pinfunction "2_2") (pintype "passive"))
      (node (ref "IC22") (pin "4") (pinfunction "4_4") (pintype "passive"))
    )
    (net (code "237") (name "Net-(A213-Pad1)") (class "Default")
      (node (ref "A213") (pin "1") (pinfunction "1_1") (pintype "passive"))
      (node (ref "A213") (pin "2") (pinfunction "2_2") (pintype "passive"))
      (node (ref "IC22") (pin "5") (pinfunction "5_5") (pintype "passive"))
    )
    (net (code "238") (name "Net-(A214-Pad1)") (class "Default")
      (node (ref "A214") (pin "1") (pinfunction "1_1") (pintype "passive"))
      (node (ref "A214") (pin "2") (pinfunction "2_2") (pintype "passive"))
      (node (ref "IC22") (pin "6") (pinfunction "6_6") (pintype "passive"))
    )
    (net (code "239") (name "Net-(A215-Pad1)") (class "Default")
      (node (ref "A215") (pin "1") (pinfunction "1_1") (pintype "passive"))
      (node (ref "A215") (pin "2") (pinfunction "2_2") (pintype "passive"))
      (node (ref "IC22") (pin "7") (pinfunction "7_7") (pintype "passive"))
    )
    (net (code "240") (name "Net-(A216-Pad1)") (class "Default")
      (node (ref "A216") (pin "1") (pinfunction "1_1") (pintype "passive"))
      (node (ref "A216") (pin "2") (pinfunction "2_2") (pintype "passive"))
      (node (ref "IC22") (pin "8") (pinfunction "8_8") (pintype "passive"))
    )
    (net (code "241") (name "Net-(A217-Pad1)") (class "Default")
      (node (ref "A217") (pin "1") (pinfunction "1_1") (pintype "passive"))
      (node (ref "A217") (pin "2") (pinfunction "2_2") (pintype "passive"))
      (node (ref "IC22") (pin "9") (pinfunction "9_9") (pintype "passive"))
    )
    (net (code "242") (name "Net-(A218-Pad1)") (class "Default")
      (node (ref "A218") (pin "1") (pinfunction "1_1") (pintype "passive"))
      (node (ref "A218") (pin "2") (pinfunction "2_2") (pintype "passive"))
      (node (ref "IC22") (pin "10") (pinfunction "10_10") (pintype "passive"))
    )
    (net (code "243") (name "Net-(A219-Pad1)") (class "Default")
      (node (ref "A219") (pin "1") (pinfunction "1_1") (pintype "passive"))
      (node (ref "A219") (pin "2") (pinfunction "2_2") (pintype "passive"))
      (node (ref "IC22") (pin "11") (pinfunction "11_11") (pintype "passive"))
    )
    (net (code "244") (name "Net-(A220-Pad1)") (class "Default")
      (node (ref "A220") (pin "1") (pinfunction "1_1") (pintype "passive"))
      (node (ref "A220") (pin "2") (pinfunction "2_2") (pintype "passive"))
      (node (ref "IC22") (pin "12") (pinfunction "12_12") (pintype "passive"))
    )
    (net (code "245") (name "Net-(A221-Pad1)") (class "Default")
      (node (ref "A221") (pin "1") (pinfunction "1_1") (pintype "passive"))
      (node (ref "A221") (pin "2") (pinfunction "2_2") (pintype "passive"))
      (node (ref "IC22") (pin "13") (pinfunction "13_13") (pintype "passive"))
    )
    (net (code "246") (name "Net-(A222-Pad1)") (class "Default")
      (node (ref "A222") (pin "1") (pinfunction "1_1") (pintype "passive"))
      (node (ref "A222") (pin "2") (pinfunction "2_2") (pintype "passive"))
      (node (ref "IC22") (pin "14") (pinfunction "14_14") (pintype "passive"))
    )
    (net (code "247") (name "Net-(A223-Pad1)") (class "Default")
      (node (ref "A223") (pin "1") (pinfunction "1_1") (pintype "passive"))
      (node (ref "A223") (pin "2") (pinfunction "2_2") (pintype "passive"))
      (node (ref "IC22") (pin "15") (pinfunction "15_15") (pintype "passive"))
    )
    (net (code "248") (name "Net-(A224-Pad1)") (class "Default")
      (node (ref "A224") (pin "1") (pinfunction "1_1") (pintype "passive"))
      (node (ref "A224") (pin "2") (pinfunction "2_2") (pintype "passive"))
      (node (ref "IC22") (pin "16") (pinfunction "16_16") (pintype "passive"))
    )
    (net (code "249") (name "Net-(A225-Pad1)") (class "Default")
      (node (ref "A225") (pin "1") (pinfunction "1_1") (pintype "passive"))
      (node (ref "A225") (pin "2") (pinfunction "2_2") (pintype "passive"))
      (node (ref "IC23") (pin "1") (pinfunction "1_1") (pintype "passive"))
    )
    (net (code "250") (name "Net-(A226-Pad1)") (class "Default")
      (node (ref "A226") (pin "1") (pinfunction "1_1") (pintype "passive"))
      (node (ref "A226") (pin "2") (pinfunction "2_2") (pintype "passive"))
      (node (ref "IC23") (pin "2") (pinfunction "2_2") (pintype "passive"))
    )
    (net (code "251") (name "Net-(A227-Pad1)") (class "Default")
      (node (ref "A227") (pin "1") (pinfunction "1_1") (pintype "passive"))
      (node (ref "A227") (pin "2") (pinfunction "2_2") (pintype "passive"))
      (node (ref "IC23") (pin "3") (pinfunction "3_3") (pintype "passive"))
    )
    (net (code "252") (name "Net-(A228-Pad1)") (class "Default")
      (node (ref "A228") (pin "1") (pinfunction "1_1") (pintype "passive"))
      (node (ref "A228") (pin "2") (pinfunction "2_2") (pintype "passive"))
      (node (ref "IC23") (pin "4") (pinfunction "4_4") (pintype "passive"))
    )
    (net (code "253") (name "Net-(A229-Pad1)") (class "Default")
      (node (ref "A229") (pin "1") (pinfunction "1_1") (pintype "passive"))
      (node (ref "A229") (pin "2") (pinfunction "2_2") (pintype "passive"))
      (node (ref "IC23") (pin "5") (pinfunction "5_5") (pintype "passive"))
    )
    (net (code "254") (name "Net-(A230-Pad1)") (class "Default")
      (node (ref "A230") (pin "1") (pinfunction "1_1") (pintype "passive"))
      (node (ref "A230") (pin "2") (pinfunction "2_2") (pintype "passive"))
      (node (ref "IC23") (pin "6") (pinfunction "6_6") (pintype "passive"))
    )
    (net (code "255") (name "Net-(A231-Pad1)") (class "Default")
      (node (ref "A231") (pin "1") (pinfunction "1_1") (pintype "passive"))
      (node (ref "A231") (pin "2") (pinfunction "2_2") (pintype "passive"))
      (node (ref "IC23") (pin "7") (pinfunction "7_7") (pintype "passive"))
    )
    (net (code "256") (name "Net-(A232-Pad1)") (class "Default")
      (node (ref "A232") (pin "1") (pinfunction "1_1") (pintype "passive"))
      (node (ref "A232") (pin "2") (pinfunction "2_2") (pintype "passive"))
      (node (ref "IC23") (pin "8") (pinfunction "8_8") (pintype "passive"))
    )
    (net (code "257") (name "Net-(A233-Pad1)") (class "Default")
      (node (ref "A233") (pin "1") (pinfunction "1_1") (pintype "passive"))
      (node (ref "A233") (pin "2") (pinfunction "2_2") (pintype "passive"))
      (node (ref "IC23") (pin "9") (pinfunction "9_9") (pintype "passive"))
    )
    (net (code "258") (name "Net-(A234-Pad1)") (class "Default")
      (node (ref "A234") (pin "1") (pinfunction "1_1") (pintype "passive"))
      (node (ref "A234") (pin "2") (pinfunction "2_2") (pintype "passive"))
      (node (ref "IC23") (pin "10") (pinfunction "10_10") (pintype "passive"))
    )
    (net (code "259") (name "Net-(A235-Pad1)") (class "Default")
      (node (ref "A235") (pin "1") (pinfunction "1_1") (pintype "passive"))
      (node (ref "A235") (pin "2") (pinfunction "2_2") (pintype "passive"))
      (node (ref "IC23") (pin "11") (pinfunction "11_11") (pintype "passive"))
    )
    (net (code "260") (name "Net-(A236-Pad1)") (class "Default")
      (node (ref "A236") (pin "1") (pinfunction "1_1") (pintype "passive"))
      (node (ref "A236") (pin "2") (pinfunction "2_2") (pintype "passive"))
      (node (ref "IC23") (pin "12") (pinfunction "12_12") (pintype "passive"))
    )
    (net (code "261") (name "Net-(A237-Pad1)") (class "Default")
      (node (ref "A237") (pin "1") (pinfunction "1_1") (pintype "passive"))
      (node (ref "A237") (pin "2") (pinfunction "2_2") (pintype "passive"))
      (node (ref "IC23") (pin "13") (pinfunction "13_13") (pintype "passive"))
    )
    (net (code "262") (name "Net-(A238-Pad1)") (class "Default")
      (node (ref "A238") (pin "1") (pinfunction "1_1") (pintype "passive"))
      (node (ref "A238") (pin "2") (pinfunction "2_2") (pintype "passive"))
      (node (ref "IC23") (pin "14") (pinfunction "14_14") (pintype "passive"))
    )
    (net (code "263") (name "Net-(A239-Pad1)") (class "Default")
      (node (ref "A239") (pin "1") (pinfunction "1_1") (pintype "passive"))
      (node (ref "A239") (pin "2") (pinfunction "2_2") (pintype "passive"))
      (node (ref "IC23") (pin "15") (pinfunction "15_15") (pintype "passive"))
    )
    (net (code "264") (name "Net-(A240-Pad1)") (class "Default")
      (node (ref "A240") (pin "1") (pinfunction "1_1") (pintype "passive"))
      (node (ref "A240") (pin "2") (pinfunction "2_2") (pintype "passive"))
      (node (ref "IC23") (pin "16") (pinfunction "16_16") (pintype "passive"))
    )
    (net (code "265") (name "Net-(A241-Pad1)") (class "Default")
      (node (ref "A241") (pin "1") (pinfunction "1_1") (pintype "passive"))
      (node (ref "A241") (pin "2") (pinfunction "2_2") (pintype "passive"))
      (node (ref "IC24") (pin "1") (pinfunction "1_1") (pintype "passive"))
    )
    (net (code "266") (name "Net-(A242-Pad1)") (class "Default")
      (node (ref "A242") (pin "1") (pinfunction "1_1") (pintype "passive"))
      (node (ref "A242") (pin "2") (pinfunction "2_2") (pintype "passive"))
      (node (ref "IC24") (pin "2") (pinfunction "2_2") (pintype "passive"))
    )
    (net (code "267") (name "Net-(A243-Pad1)") (class "Default")
      (node (ref "A243") (pin "1") (pinfunction "1_1") (pintype "passive"))
      (node (ref "A243") (pin "2") (pinfunction "2_2") (pintype "passive"))
      (node (ref "IC24") (pin "3") (pinfunction "3_3") (pintype "passive"))
    )
    (net (code "268") (name "Net-(A244-Pad1)") (class "Default")
      (node (ref "A244") (pin "1") (pinfunction "1_1") (pintype "passive"))
      (node (ref "A244") (pin "2") (pinfunction "2_2") (pintype "passive"))
      (node (ref "IC24") (pin "4") (pinfunction "4_4") (pintype "passive"))
    )
    (net (code "269") (name "Net-(A245-Pad1)") (class "Default")
      (node (ref "A245") (pin "1") (pinfunction "1_1") (pintype "passive"))
      (node (ref "A245") (pin "2") (pinfunction "2_2") (pintype "passive"))
      (node (ref "IC24") (pin "5") (pinfunction "5_5") (pintype "passive"))
    )
    (net (code "270") (name "Net-(A246-Pad1)") (class "Default")
      (node (ref "A246") (pin "1") (pinfunction "1_1") (pintype "passive"))
      (node (ref "A246") (pin "2") (pinfunction "2_2") (pintype "passive"))
      (node (ref "IC24") (pin "6") (pinfunction "6_6") (pintype "passive"))
    )
    (net (code "271") (name "Net-(A247-Pad1)") (class "Default")
      (node (ref "A247") (pin "1") (pinfunction "1_1") (pintype "passive"))
      (node (ref "A247") (pin "2") (pinfunction "2_2") (pintype "passive"))
      (node (ref "IC24") (pin "7") (pinfunction "7_7") (pintype "passive"))
    )
    (net (code "272") (name "Net-(A248-Pad1)") (class "Default")
      (node (ref "A248") (pin "1") (pinfunction "1_1") (pintype "passive"))
      (node (ref "A248") (pin "2") (pinfunction "2_2") (pintype "passive"))
      (node (ref "IC24") (pin "8") (pinfunction "8_8") (pintype "passive"))
    )
    (net (code "273") (name "Net-(A249-Pad1)") (class "Default")
      (node (ref "A249") (pin "1") (pinfunction "1_1") (pintype "passive"))
      (node (ref "A249") (pin "2") (pinfunction "2_2") (pintype "passive"))
      (node (ref "IC24") (pin "9") (pinfunction "9_9") (pintype "passive"))
    )
    (net (code "274") (name "Net-(A250-Pad1)") (class "Default")
      (node (ref "A250") (pin "1") (pinfunction "1_1") (pintype "passive"))
      (node (ref "A250") (pin "2") (pinfunction "2_2") (pintype "passive"))
      (node (ref "IC24") (pin "10") (pinfunction "10_10") (pintype "passive"))
    )
    (net (code "275") (name "Net-(A251-Pad1)") (class "Default")
      (node (ref "A251") (pin "1") (pinfunction "1_1") (pintype "passive"))
      (node (ref "A251") (pin "2") (pinfunction "2_2") (pintype "passive"))
      (node (ref "IC24") (pin "11") (pinfunction "11_11") (pintype "passive"))
    )
    (net (code "276") (name "Net-(A252-Pad1)") (class "Default")
      (node (ref "A252") (pin "1") (pinfunction "1_1") (pintype "passive"))
      (node (ref "A252") (pin "2") (pinfunction "2_2") (pintype "passive"))
      (node (ref "IC24") (pin "12") (pinfunction "12_12") (pintype "passive"))
    )
    (net (code "277") (name "Net-(A253-Pad1)") (class "Default")
      (node (ref "A253") (pin "1") (pinfunction "1_1") (pintype "passive"))
      (node (ref "A253") (pin "2") (pinfunction "2_2") (pintype "passive"))
      (node (ref "IC24") (pin "13") (pinfunction "13_13") (pintype "passive"))
    )
    (net (code "278") (name "Net-(A254-Pad1)") (class "Default")
      (node (ref "A254") (pin "1") (pinfunction "1_1") (pintype "passive"))
      (node (ref "A254") (pin "2") (pinfunction "2_2") (pintype "passive"))
      (node (ref "IC24") (pin "14") (pinfunction "14_14") (pintype "passive"))
    )
    (net (code "279") (name "Net-(A255-Pad1)") (class "Default")
      (node (ref "A255") (pin "1") (pinfunction "1_1") (pintype "passive"))
      (node (ref "A255") (pin "2") (pinfunction "2_2") (pintype "passive"))
      (node (ref "IC24") (pin "15") (pinfunction "15_15") (pintype "passive"))
    )
    (net (code "280") (name "Net-(A256-Pad1)") (class "Default")
      (node (ref "A256") (pin "1") (pinfunction "1_1") (pintype "passive"))
      (node (ref "A256") (pin "2") (pinfunction "2_2") (pintype "passive"))
      (node (ref "IC24") (pin "16") (pinfunction "16_16") (pintype "passive"))
    )
    (net (code "281") (name "Net-(A257-Pad1)") (class "Default")
      (node (ref "A257") (pin "1") (pinfunction "1_1") (pintype "passive"))
      (node (ref "A257") (pin "2") (pinfunction "2_2") (pintype "passive"))
      (node (ref "IC25") (pin "1") (pinfunction "1_1") (pintype "passive"))
    )
    (net (code "282") (name "Net-(A258-Pad1)") (class "Default")
      (node (ref "A258") (pin "1") (pinfunction "1_1") (pintype "passive"))
      (node (ref "A258") (pin "2") (pinfunction "2_2") (pintype "passive"))
      (node (ref "IC25") (pin "2") (pinfunction "2_2") (pintype "passive"))
    )
    (net (code "283") (name "Net-(A259-Pad1)") (class "Default")
      (node (ref "A259") (pin "1") (pinfunction "1_1") (pintype "passive"))
      (node (ref "A259") (pin "2") (pinfunction "2_2") (pintype "passive"))
      (node (ref "IC25") (pin "3") (pinfunction "3_3") (pintype "passive"))
    )
    (net (code "284") (name "Net-(A260-Pad1)") (class "Default")
      (node (ref "A260") (pin "1") (pinfunction "1_1") (pintype "passive"))
      (node (ref "A260") (pin "2") (pinfunction "2_2") (pintype "passive"))
      (node (ref "IC25") (pin "4") (pinfunction "4_4") (pintype "passive"))
    )
    (net (code "285") (name "Net-(A261-Pad1)") (class "Default")
      (node (ref "A261") (pin "1") (pinfunction "1_1") (pintype "passive"))
      (node (ref "A261") (pin "2") (pinfunction "2_2") (pintype "passive"))
      (node (ref "IC25") (pin "5") (pinfunction "5_5") (pintype "passive"))
    )
    (net (code "286") (name "Net-(A262-Pad1)") (class "Default")
      (node (ref "A262") (pin "1") (pinfunction "1_1") (pintype "passive"))
      (node (ref "A262") (pin "2") (pinfunction "2_2") (pintype "passive"))
      (node (ref "IC25") (pin "6") (pinfunction "6_6") (pintype "passive"))
    )
    (net (code "287") (name "Net-(A263-Pad1)") (class "Default")
      (node (ref "A263") (pin "1") (pinfunction "1_1") (pintype "passive"))
      (node (ref "A263") (pin "2") (pinfunction "2_2") (pintype "passive"))
      (node (ref "IC25") (pin "7") (pinfunction "7_7") (pintype "passive"))
    )
    (net (code "288") (name "Net-(A264-Pad1)") (class "Default")
      (node (ref "A264") (pin "1") (pinfunction "1_1") (pintype "passive"))
      (node (ref "A264") (pin "2") (pinfunction "2_2") (pintype "passive"))
      (node (ref "IC25") (pin "8") (pinfunction "8_8") (pintype "passive"))
    )
    (net (code "289") (name "Net-(A265-Pad1)") (class "Default")
      (node (ref "A265") (pin "1") (pinfunction "1_1") (pintype "passive"))
      (node (ref "A265") (pin "2") (pinfunction "2_2") (pintype "passive"))
      (node (ref "IC25") (pin "9") (pinfunction "9_9") (pintype "passive"))
    )
    (net (code "290") (name "Net-(A266-Pad1)") (class "Default")
      (node (ref "A266") (pin "1") (pinfunction "1_1") (pintype "passive"))
      (node (ref "A266") (pin "2") (pinfunction "2_2") (pintype "passive"))
      (node (ref "IC25") (pin "10") (pinfunction "10_10") (pintype "passive"))
    )
    (net (code "291") (name "Net-(A267-Pad1)") (class "Default")
      (node (ref "A267") (pin "1") (pinfunction "1_1") (pintype "passive"))
      (node (ref "A267") (pin "2") (pinfunction "2_2") (pintype "passive"))
      (node (ref "IC25") (pin "11") (pinfunction "11_11") (pintype "passive"))
    )
    (net (code "292") (name "Net-(A268-Pad1)") (class "Default")
      (node (ref "A268") (pin "1") (pinfunction "1_1") (pintype "passive"))
      (node (ref "A268") (pin "2") (pinfunction "2_2") (pintype "passive"))
      (node (ref "IC25") (pin "12") (pinfunction "12_12") (pintype "passive"))
    )
    (net (code "293") (name "Net-(A269-Pad1)") (class "Default")
      (node (ref "A269") (pin "1") (pinfunction "1_1") (pintype "passive"))
      (node (ref "A269") (pin "2") (pinfunction "2_2") (pintype "passive"))
      (node (ref "IC25") (pin "13") (pinfunction "13_13") (pintype "passive"))
    )
    (net (code "294") (name "Net-(A270-Pad1)") (class "Default")
      (node (ref "A270") (pin "1") (pinfunction "1_1") (pintype "passive"))
      (node (ref "A270") (pin "2") (pinfunction "2_2") (pintype "passive"))
      (node (ref "IC25") (pin "14") (pinfunction "14_14") (pintype "passive"))
    )
    (net (code "295") (name "Net-(A271-Pad1)") (class "Default")
      (node (ref "A271") (pin "1") (pinfunction "1_1") (pintype "passive"))
      (node (ref "A271") (pin "2") (pinfunction "2_2") (pintype "passive"))
      (node (ref "IC25") (pin "15") (pinfunction "15_15") (pintype "passive"))
    )
    (net (code "296") (name "Net-(A272-Pad1)") (class "Default")
      (node (ref "A272") (pin "1") (pinfunction "1_1") (pintype "passive"))
      (node (ref "A272") (pin "2") (pinfunction "2_2") (pintype "passive"))
      (node (ref "IC25") (pin "16") (pinfunction "16_16") (pintype "passive"))
    )
    (net (code "297") (name "Net-(A273-Pad1)") (class "Default")
      (node (ref "A273") (pin "1") (pinfunction "1_1") (pintype "passive"))
      (node (ref "A273") (pin "2") (pinfunction "2_2") (pintype "passive"))
      (node (ref "IC26") (pin "1") (pinfunction "1_1") (pintype "passive"))
    )
    (net (code "298") (name "Net-(A274-Pad1)") (class "Default")
      (node (ref "A274") (pin "1") (pinfunction "1_1") (pintype "passive"))
      (node (ref "A274") (pin "2") (pinfunction "2_2") (pintype "passive"))
      (node (ref "IC26") (pin "2") (pinfunction "2_2") (pintype "passive"))
    )
    (net (code "299") (name "Net-(A275-Pad1)") (class "Default")
      (node (ref "A275") (pin "1") (pinfunction "1_1") (pintype "passive"))
      (node (ref "A275") (pin "2") (pinfunction "2_2") (pintype "passive"))
      (node (ref "IC26") (pin "3") (pinfunction "3_3") (pintype "passive"))
    )
    (net (code "300") (name "Net-(A276-Pad1)") (class "Default")
      (node (ref "A276") (pin "1") (pinfunction "1_1") (pintype "passive"))
      (node (ref "A276") (pin "2") (pinfunction "2_2") (pintype "passive"))
      (node (ref "IC26") (pin "4") (pinfunction "4_4") (pintype "passive"))
    )
    (net (code "301") (name "Net-(A277-Pad1)") (class "Default")
      (node (ref "A277") (pin "1") (pinfunction "1_1") (pintype "passive"))
      (node (ref "A277") (pin "2") (pinfunction "2_2") (pintype "passive"))
      (node (ref "IC26") (pin "5") (pinfunction "5_5") (pintype "passive"))
    )
    (net (code "302") (name "Net-(A278-Pad1)") (class "Default")
      (node (ref "A278") (pin "1") (pinfunction "1_1") (pintype "passive"))
      (node (ref "A278") (pin "2") (pinfunction "2_2") (pintype "passive"))
      (node (ref "IC26") (pin "6") (pinfunction "6_6") (pintype "passive"))
    )
    (net (code "303") (name "Net-(A279-Pad1)") (class "Default")
      (node (ref "A279") (pin "1") (pinfunction "1_1") (pintype "passive"))
      (node (ref "A279") (pin "2") (pinfunction "2_2") (pintype "passive"))
      (node (ref "IC26") (pin "7") (pinfunction "7_7") (pintype "passive"))
    )
    (net (code "304") (name "Net-(A280-Pad1)") (class "Default")
      (node (ref "A280") (pin "1") (pinfunction "1_1") (pintype "passive"))
      (node (ref "A280") (pin "2") (pinfunction "2_2") (pintype "passive"))
      (node (ref "IC26") (pin "8") (pinfunction "8_8") (pintype "passive"))
    )
    (net (code "305") (name "Net-(A281-Pad1)") (class "Default")
      (node (ref "A281") (pin "1") (pinfunction "1_1") (pintype "passive"))
      (node (ref "A281") (pin "2") (pinfunction "2_2") (pintype "passive"))
      (node (ref "IC26") (pin "9") (pinfunction "9_9") (pintype "passive"))
    )
    (net (code "306") (name "Net-(A282-Pad1)") (class "Default")
      (node (ref "A282") (pin "1") (pinfunction "1_1") (pintype "passive"))
      (node (ref "A282") (pin "2") (pinfunction "2_2") (pintype "passive"))
      (node (ref "IC26") (pin "10") (pinfunction "10_10") (pintype "passive"))
    )
    (net (code "307") (name "Net-(A283-Pad1)") (class "Default")
      (node (ref "A283") (pin "1") (pinfunction "1_1") (pintype "passive"))
      (node (ref "A283") (pin "2") (pinfunction "2_2") (pintype "passive"))
      (node (ref "IC26") (pin "11") (pinfunction "11_11") (pintype "passive"))
    )
    (net (code "308") (name "Net-(A284-Pad1)") (class "Default")
      (node (ref "A284") (pin "1") (pinfunction "1_1") (pintype "passive"))
      (node (ref "A284") (pin "2") (pinfunction "2_2") (pintype "passive"))
      (node (ref "IC26") (pin "12") (pinfunction "12_12") (pintype "passive"))
    )
    (net (code "309") (name "Net-(A285-Pad1)") (class "Default")
      (node (ref "A285") (pin "1") (pinfunction "1_1") (pintype "passive"))
      (node (ref "A285") (pin "2") (pinfunction "2_2") (pintype "passive"))
      (node (ref "IC26") (pin "13") (pinfunction "13_13") (pintype "passive"))
    )
    (net (code "310") (name "Net-(A286-Pad1)") (class "Default")
      (node (ref "A286") (pin "1") (pinfunction "1_1") (pintype "passive"))
      (node (ref "A286") (pin "2") (pinfunction "2_2") (pintype "passive"))
      (node (ref "IC26") (pin "14") (pinfunction "14_14") (pintype "passive"))
    )
    (net (code "311") (name "Net-(A287-Pad1)") (class "Default")
      (node (ref "A287") (pin "1") (pinfunction "1_1") (pintype "passive"))
      (node (ref "A287") (pin "2") (pinfunction "2_2") (pintype "passive"))
      (node (ref "IC26") (pin "15") (pinfunction "15_15") (pintype "passive"))
    )
    (net (code "312") (name "Net-(A288-Pad1)") (class "Default")
      (node (ref "A288") (pin "1") (pinfunction "1_1") (pintype "passive"))
      (node (ref "A288") (pin "2") (pinfunction "2_2") (pintype "passive"))
      (node (ref "IC26") (pin "16") (pinfunction "16_16") (pintype "passive"))
    )
    (net (code "313") (name "Net-(A289-Pad1)") (class "Default")
      (node (ref "A289") (pin "1") (pinfunction "1_1") (pintype "passive"))
      (node (ref "A289") (pin "2") (pinfunction "2_2") (pintype "passive"))
      (node (ref "IC27") (pin "1") (pinfunction "1_1") (pintype "passive"))
    )
    (net (code "314") (name "Net-(A290-Pad1)") (class "Default")
      (node (ref "A290") (pin "1") (pinfunction "1_1") (pintype "passive"))
      (node (ref "A290") (pin "2") (pinfunction "2_2") (pintype "passive"))
      (node (ref "IC27") (pin "2") (pinfunction "2_2") (pintype "passive"))
    )
    (net (code "315") (name "Net-(A291-Pad1)") (class "Default")
      (node (ref "A291") (pin "1") (pinfunction "1_1") (pintype "passive"))
      (node (ref "A291") (pin "2") (pinfunction "2_2") (pintype "passive"))
      (node (ref "IC27") (pin "3") (pinfunction "3_3") (pintype "passive"))
    )
    (net (code "316") (name "Net-(A292-Pad1)") (class "Default")
      (node (ref "A292") (pin "1") (pinfunction "1_1") (pintype "passive"))
      (node (ref "A292") (pin "2") (pinfunction "2_2") (pintype "passive"))
      (node (ref "IC27") (pin "4") (pinfunction "4_4") (pintype "passive"))
    )
    (net (code "317") (name "Net-(A293-Pad1)") (class "Default")
      (node (ref "A293") (pin "1") (pinfunction "1_1") (pintype "passive"))
      (node (ref "A293") (pin "2") (pinfunction "2_2") (pintype "passive"))
      (node (ref "IC27") (pin "5") (pinfunction "5_5") (pintype "passive"))
    )
    (net (code "318") (name "Net-(A294-Pad1)") (class "Default")
      (node (ref "A294") (pin "1") (pinfunction "1_1") (pintype "passive"))
      (node (ref "A294") (pin "2") (pinfunction "2_2") (pintype "passive"))
      (node (ref "IC27") (pin "6") (pinfunction "6_6") (pintype "passive"))
    )
    (net (code "319") (name "Net-(A295-Pad1)") (class "Default")
      (node (ref "A295") (pin "1") (pinfunction "1_1") (pintype "passive"))
      (node (ref "A295") (pin "2") (pinfunction "2_2") (pintype "passive"))
      (node (ref "IC27") (pin "7") (pinfunction "7_7") (pintype "passive"))
    )
    (net (code "320") (name "Net-(A296-Pad1)") (class "Default")
      (node (ref "A296") (pin "1") (pinfunction "1_1") (pintype "passive"))
      (node (ref "A296") (pin "2") (pinfunction "2_2") (pintype "passive"))
      (node (ref "IC27") (pin "8") (pinfunction "8_8") (pintype "passive"))
    )
    (net (code "321") (name "Net-(A297-Pad1)") (class "Default")
      (node (ref "A297") (pin "1") (pinfunction "1_1") (pintype "passive"))
      (node (ref "A297") (pin "2") (pinfunction "2_2") (pintype "passive"))
      (node (ref "IC27") (pin "9") (pinfunction "9_9") (pintype "passive"))
    )
    (net (code "322") (name "Net-(A298-Pad1)") (class "Default")
      (node (ref "A298") (pin "1") (pinfunction "1_1") (pintype "passive"))
      (node (ref "A298") (pin "2") (pinfunction "2_2") (pintype "passive"))
      (node (ref "IC27") (pin "10") (pinfunction "10_10") (pintype "passive"))
    )
    (net (code "323") (name "Net-(A299-Pad1)") (class "Default")
      (node (ref "A299") (pin "1") (pinfunction "1_1") (pintype "passive"))
      (node (ref "A299") (pin "2") (pinfunction "2_2") (pintype "passive"))
      (node (ref "IC27") (pin "11") (pinfunction "11_11") (pintype "passive"))
    )
    (net (code "324") (name "Net-(A300-Pad1)") (class "Default")
      (node (ref "A300") (pin "1") (pinfunction "1_1") (pintype "passive"))
      (node (ref "A300") (pin "2") (pinfunction "2_2") (pintype "passive"))
      (node (ref "IC27") (pin "12") (pinfunction "12_12") (pintype "passive"))
    )
    (net (code "325") (name "Net-(A301-Pad1)") (class "Default")
      (node (ref "A301") (pin "1") (pinfunction "1_1") (pintype "passive"))
      (node (ref "A301") (pin "2") (pinfunction "2_2") (pintype "passive"))
      (node (ref "IC27") (pin "13") (pinfunction "13_13") (pintype "passive"))
    )
    (net (code "326") (name "Net-(A302-Pad1)") (class "Default")
      (node (ref "A302") (pin "1") (pinfunction "1_1") (pintype "passive"))
      (node (ref "A302") (pin "2") (pinfunction "2_2") (pintype "passive"))
      (node (ref "IC27") (pin "14") (pinfunction "14_14") (pintype "passive"))
    )
    (net (code "327") (name "Net-(A303-Pad1)") (class "Default")
      (node (ref "A303") (pin "1") (pinfunction "1_1") (pintype "passive"))
      (node (ref "A303") (pin "2") (pinfunction "2_2") (pintype "passive"))
      (node (ref "IC27") (pin "15") (pinfunction "15_15") (pintype "passive"))
    )
    (net (code "328") (name "Net-(A304-Pad1)") (class "Default")
      (node (ref "A304") (pin "1") (pinfunction "1_1") (pintype "passive"))
      (node (ref "A304") (pin "2") (pinfunction "2_2") (pintype "passive"))
      (node (ref "IC27") (pin "16") (pinfunction "16_16") (pintype "passive"))
    )
    (net (code "329") (name "Net-(A305-Pad1)") (class "Default")
      (node (ref "A305") (pin "1") (pinfunction "1_1") (pintype "passive"))
      (node (ref "A305") (pin "2") (pinfunction "2_2") (pintype "passive"))
      (node (ref "IC28") (pin "1") (pinfunction "1_1") (pintype "passive"))
    )
    (net (code "330") (name "Net-(A306-Pad1)") (class "Default")
      (node (ref "A306") (pin "1") (pinfunction "1_1") (pintype "passive"))
      (node (ref "A306") (pin "2") (pinfunction "2_2") (pintype "passive"))
      (node (ref "IC28") (pin "2") (pinfunction "2_2") (pintype "passive"))
    )
    (net (code "331") (name "Net-(A307-Pad1)") (class "Default")
      (node (ref "A307") (pin "1") (pinfunction "1_1") (pintype "passive"))
      (node (ref "A307") (pin "2") (pinfunction "2_2") (pintype "passive"))
      (node (ref "IC28") (pin "3") (pinfunction "3_3") (pintype "passive"))
    )
    (net (code "332") (name "Net-(A308-Pad1)") (class "Default")
      (node (ref "A308") (pin "1") (pinfunction "1_1") (pintype "passive"))
      (node (ref "A308") (pin "2") (pinfunction "2_2") (pintype "passive"))
      (node (ref "IC28") (pin "4") (pinfunction "4_4") (pintype "passive"))
    )
    (net (code "333") (name "Net-(A309-Pad1)") (class "Default")
      (node (ref "A309") (pin "1") (pinfunction "1_1") (pintype "passive"))
      (node (ref "A309") (pin "2") (pinfunction "2_2") (pintype "passive"))
      (node (ref "IC28") (pin "5") (pinfunction "5_5") (pintype "passive"))
    )
    (net (code "334") (name "Net-(A310-Pad1)") (class "Default")
      (node (ref "A310") (pin "1") (pinfunction "1_1") (pintype "passive"))
      (node (ref "A310") (pin "2") (pinfunction "2_2") (pintype "passive"))
      (node (ref "IC28") (pin "6") (pinfunction "6_6") (pintype "passive"))
    )
    (net (code "335") (name "Net-(A311-Pad1)") (class "Default")
      (node (ref "A311") (pin "1") (pinfunction "1_1") (pintype "passive"))
      (node (ref "A311") (pin "2") (pinfunction "2_2") (pintype "passive"))
      (node (ref "IC28") (pin "7") (pinfunction "7_7") (pintype "passive"))
    )
    (net (code "336") (name "Net-(A312-Pad1)") (class "Default")
      (node (ref "A312") (pin "1") (pinfunction "1_1") (pintype "passive"))
      (node (ref "A312") (pin "2") (pinfunction "2_2") (pintype "passive"))
      (node (ref "IC28") (pin "8") (pinfunction "8_8") (pintype "passive"))
    )
    (net (code "337") (name "Net-(A313-Pad1)") (class "Default")
      (node (ref "A313") (pin "1") (pinfunction "1_1") (pintype "passive"))
      (node (ref "A313") (pin "2") (pinfunction "2_2") (pintype "passive"))
      (node (ref "IC28") (pin "9") (pinfunction "9_9") (pintype "passive"))
    )
    (net (code "338") (name "Net-(A314-Pad1)") (class "Default")
      (node (ref "A314") (pin "1") (pinfunction "1_1") (pintype "passive"))
      (node (ref "A314") (pin "2") (pinfunction "2_2") (pintype "passive"))
      (node (ref "IC28") (pin "10") (pinfunction "10_10") (pintype "passive"))
    )
    (net (code "339") (name "Net-(A315-Pad1)") (class "Default")
      (node (ref "A315") (pin "1") (pinfunction "1_1") (pintype "passive"))
      (node (ref "A315") (pin "2") (pinfunction "2_2") (pintype "passive"))
      (node (ref "IC28") (pin "11") (pinfunction "11_11") (pintype "passive"))
    )
    (net (code "340") (name "Net-(A316-Pad1)") (class "Default")
      (node (ref "A316") (pin "1") (pinfunction "1_1") (pintype "passive"))
      (node (ref "A316") (pin "2") (pinfunction "2_2") (pintype "passive"))
      (node (ref "IC28") (pin "12") (pinfunction "12_12") (pintype "passive"))
    )
    (net (code "341") (name "Net-(A317-Pad1)") (class "Default")
      (node (ref "A317") (pin "1") (pinfunction "1_1") (pintype "passive"))
      (node (ref "A317") (pin "2") (pinfunction "2_2") (pintype "passive"))
      (node (ref "IC28") (pin "13") (pinfunction "13_13") (pintype "passive"))
    )
    (net (code "342") (name "Net-(A318-Pad1)") (class "Default")
      (node (ref "A318") (pin "1") (pinfunction "1_1") (pintype "passive"))
      (node (ref "A318") (pin "2") (pinfunction "2_2") (pintype "passive"))
      (node (ref "IC28") (pin "14") (pinfunction "14_14") (pintype "passive"))
    )
    (net (code "343") (name "Net-(A319-Pad1)") (class "Default")
      (node (ref "A319") (pin "1") (pinfunction "1_1") (pintype "passive"))
      (node (ref "A319") (pin "2") (pinfunction "2_2") (pintype "passive"))
      (node (ref "IC28") (pin "15") (pinfunction "15_15") (pintype "passive"))
    )
    (net (code "344") (name "Net-(A320-Pad1)") (class "Default")
      (node (ref "A320") (pin "1") (pinfunction "1_1") (pintype "passive"))
      (node (ref "A320") (pin "2") (pinfunction "2_2") (pintype "passive"))
      (node (ref "IC28") (pin "16") (pinfunction "16_16") (pintype "passive"))
    )
    (net (code "345") (name "Net-(A321-Pad1)") (class "Default")
      (node (ref "A321") (pin "1") (pinfunction "1_1") (pintype "passive"))
      (node (ref "A321") (pin "2") (pinfunction "2_2") (pintype "passive"))
      (node (ref "IC29") (pin "1") (pinfunction "1_1") (pintype "passive"))
    )
    (net (code "346") (name "Net-(A322-Pad1)") (class "Default")
      (node (ref "A322") (pin "1") (pinfunction "1_1") (pintype "passive"))
      (node (ref "A322") (pin "2") (pinfunction "2_2") (pintype "passive"))
      (node (ref "IC29") (pin "2") (pinfunction "2_2") (pintype "passive"))
    )
    (net (code "347") (name "Net-(A323-Pad1)") (class "Default")
      (node (ref "A323") (pin "1") (pinfunction "1_1") (pintype "passive"))
      (node (ref "A323") (pin "2") (pinfunction "2_2") (pintype "passive"))
      (node (ref "IC29") (pin "3") (pinfunction "3_3") (pintype "passive"))
    )
    (net (code "348") (name "Net-(A324-Pad1)") (class "Default")
      (node (ref "A324") (pin "1") (pinfunction "1_1") (pintype "passive"))
      (node (ref "A324") (pin "2") (pinfunction "2_2") (pintype "passive"))
      (node (ref "IC29") (pin "4") (pinfunction "4_4") (pintype "passive"))
    )
    (net (code "349") (name "Net-(A325-Pad1)") (class "Default")
      (node (ref "A325") (pin "1") (pinfunction "1_1") (pintype "passive"))
      (node (ref "A325") (pin "2") (pinfunction "2_2") (pintype "passive"))
      (node (ref "IC29") (pin "5") (pinfunction "5_5") (pintype "passive"))
    )
    (net (code "350") (name "Net-(A326-Pad1)") (class "Default")
      (node (ref "A326") (pin "1") (pinfunction "1_1") (pintype "passive"))
      (node (ref "A326") (pin "2") (pinfunction "2_2") (pintype "passive"))
      (node (ref "IC29") (pin "6") (pinfunction "6_6") (pintype "passive"))
    )
    (net (code "351") (name "Net-(A327-Pad1)") (class "Default")
      (node (ref "A327") (pin "1") (pinfunction "1_1") (pintype "passive"))
      (node (ref "A327") (pin "2") (pinfunction "2_2") (pintype "passive"))
      (node (ref "IC29") (pin "7") (pinfunction "7_7") (pintype "passive"))
    )
    (net (code "352") (name "Net-(A328-Pad1)") (class "Default")
      (node (ref "A328") (pin "1") (pinfunction "1_1") (pintype "passive"))
      (node (ref "A328") (pin "2") (pinfunction "2_2") (pintype "passive"))
      (node (ref "IC29") (pin "8") (pinfunction "8_8") (pintype "passive"))
    )
    (net (code "353") (name "Net-(A329-Pad1)") (class "Default")
      (node (ref "A329") (pin "1") (pinfunction "1_1") (pintype "passive"))
      (node (ref "A329") (pin "2") (pinfunction "2_2") (pintype "passive"))
      (node (ref "IC29") (pin "9") (pinfunction "9_9") (pintype "passive"))
    )
    (net (code "354") (name "Net-(A330-Pad1)") (class "Default")
      (node (ref "A330") (pin "1") (pinfunction "1_1") (pintype "passive"))
      (node (ref "A330") (pin "2") (pinfunction "2_2") (pintype "passive"))
      (node (ref "IC29") (pin "10") (pinfunction "10_10") (pintype "passive"))
    )
    (net (code "355") (name "Net-(A331-Pad1)") (class "Default")
      (node (ref "A331") (pin "1") (pinfunction "1_1") (pintype "passive"))
      (node (ref "A331") (pin "2") (pinfunction "2_2") (pintype "passive"))
      (node (ref "IC29") (pin "11") (pinfunction "11_11") (pintype "passive"))
    )
    (net (code "356") (name "Net-(A332-Pad1)") (class "Default")
      (node (ref "A332") (pin "1") (pinfunction "1_1") (pintype "passive"))
      (node (ref "A332") (pin "2") (pinfunction "2_2") (pintype "passive"))
      (node (ref "IC29") (pin "12") (pinfunction "12_12") (pintype "passive"))
    )
    (net (code "357") (name "Net-(A333-Pad1)") (class "Default")
      (node (ref "A333") (pin "1") (pinfunction "1_1") (pintype "passive"))
      (node (ref "A333") (pin "2") (pinfunction "2_2") (pintype "passive"))
      (node (ref "IC29") (pin "13") (pinfunction "13_13") (pintype "passive"))
    )
    (net (code "358") (name "Net-(A334-Pad1)") (class "Default")
      (node (ref "A334") (pin "1") (pinfunction "1_1") (pintype "passive"))
      (node (ref "A334") (pin "2") (pinfunction "2_2") (pintype "passive"))
      (node (ref "IC29") (pin "14") (pinfunction "14_14") (pintype "passive"))
    )
    (net (code "359") (name "Net-(A335-Pad1)") (class "Default")
      (node (ref "A335") (pin "1") (pinfunction "1_1") (pintype "passive"))
      (node (ref "A335") (pin "2") (pinfunction "2_2") (pintype "passive"))
      (node (ref "IC29") (pin "15") (pinfunction "15_15") (pintype "passive"))
    )
    (net (code "360") (name "Net-(A336-Pad1)") (class "Default")
      (node (ref "A336") (pin "1") (pinfunction "1_1") (pintype "passive"))
      (node (ref "A336") (pin "2") (pinfunction "2_2") (pintype "passive"))
      (node (ref "IC29") (pin "16") (pinfunction "16_16") (pintype "passive"))
    )
    (net (code "361") (name "Net-(A337-Pad1)") (class "Default")
      (node (ref "A337") (pin "1") (pinfunction "1_1") (pintype "passive"))
      (node (ref "A337") (pin "2") (pinfunction "2_2") (pintype "passive"))
      (node (ref "IC30") (pin "1") (pinfunction "1_1") (pintype "passive"))
    )
    (net (code "362") (name "Net-(A338-Pad1)") (class "Default")
      (node (ref "A338") (pin "1") (pinfunction "1_1") (pintype "passive"))
      (node (ref "A338") (pin "2") (pinfunction "2_2") (pintype "passive"))
      (node (ref "IC30") (pin "2") (pinfunction "2_2") (pintype "passive"))
    )
    (net (code "363") (name "Net-(A339-Pad1)") (class "Default")
      (node (ref "A339") (pin "1") (pinfunction "1_1") (pintype "passive"))
      (node (ref "A339") (pin "2") (pinfunction "2_2") (pintype "passive"))
      (node (ref "IC30") (pin "3") (pinfunction "3_3") (pintype "passive"))
    )
    (net (code "364") (name "Net-(A340-Pad1)") (class "Default")
      (node (ref "A340") (pin "1") (pinfunction "1_1") (pintype "passive"))
      (node (ref "A340") (pin "2") (pinfunction "2_2") (pintype "passive"))
      (node (ref "IC30") (pin "4") (pinfunction "4_4") (pintype "passive"))
    )
    (net (code "365") (name "Net-(A341-Pad1)") (class "Default")
      (node (ref "A341") (pin "1") (pinfunction "1_1") (pintype "passive"))
      (node (ref "A341") (pin "2") (pinfunction "2_2") (pintype "passive"))
      (node (ref "IC30") (pin "5") (pinfunction "5_5") (pintype "passive"))
    )
    (net (code "366") (name "Net-(A342-Pad1)") (class "Default")
      (node (ref "A342") (pin "1") (pinfunction "1_1") (pintype "passive"))
      (node (ref "A342") (pin "2") (pinfunction "2_2") (pintype "passive"))
      (node (ref "IC30") (pin "6") (pinfunction "6_6") (pintype "passive"))
    )
    (net (code "367") (name "Net-(A343-Pad1)") (class "Default")
      (node (ref "A343") (pin "1") (pinfunction "1_1") (pintype "passive"))
      (node (ref "A343") (pin "2") (pinfunction "2_2") (pintype "passive"))
      (node (ref "IC30") (pin "7") (pinfunction "7_7") (pintype "passive"))
    )
    (net (code "368") (name "Net-(A344-Pad1)") (class "Default")
      (node (ref "A344") (pin "1") (pinfunction "1_1") (pintype "passive"))
      (node (ref "A344") (pin "2") (pinfunction "2_2") (pintype "passive"))
      (node (ref "IC30") (pin "8") (pinfunction "8_8") (pintype "passive"))
    )
    (net (code "369") (name "Net-(A345-Pad1)") (class "Default")
      (node (ref "A345") (pin "1") (pinfunction "1_1") (pintype "passive"))
      (node (ref "A345") (pin "2") (pinfunction "2_2") (pintype "passive"))
      (node (ref "IC30") (pin "9") (pinfunction "9_9") (pintype "passive"))
    )
    (net (code "370") (name "Net-(A346-Pad1)") (class "Default")
      (node (ref "A346") (pin "1") (pinfunction "1_1") (pintype "passive"))
      (node (ref "A346") (pin "2") (pinfunction "2_2") (pintype "passive"))
      (node (ref "IC30") (pin "10") (pinfunction "10_10") (pintype "passive"))
    )
    (net (code "371") (name "Net-(A347-Pad1)") (class "Default")
      (node (ref "A347") (pin "1") (pinfunction "1_1") (pintype "passive"))
      (node (ref "A347") (pin "2") (pinfunction "2_2") (pintype "passive"))
      (node (ref "IC30") (pin "11") (pinfunction "11_11") (pintype "passive"))
    )
    (net (code "372") (name "Net-(A348-Pad1)") (class "Default")
      (node (ref "A348") (pin "1") (pinfunction "1_1") (pintype "passive"))
      (node (ref "A348") (pin "2") (pinfunction "2_2") (pintype "passive"))
      (node (ref "IC30") (pin "12") (pinfunction "12_12") (pintype "passive"))
    )
    (net (code "373") (name "Net-(A349-Pad1)") (class "Default")
      (node (ref "A349") (pin "1") (pinfunction "1_1") (pintype "passive"))
      (node (ref "A349") (pin "2") (pinfunction "2_2") (pintype "passive"))
      (node (ref "IC30") (pin "13") (pinfunction "13_13") (pintype "passive"))
    )
    (net (code "374") (name "Net-(A350-Pad1)") (class "Default")
      (node (ref "A350") (pin "1") (pinfunction "1_1") (pintype "passive"))
      (node (ref "A350") (pin "2") (pinfunction "2_2") (pintype "passive"))
      (node (ref "IC30") (pin "14") (pinfunction "14_14") (pintype "passive"))
    )
    (net (code "375") (name "Net-(A351-Pad1)") (class "Default")
      (node (ref "A351") (pin "1") (pinfunction "1_1") (pintype "passive"))
      (node (ref "A351") (pin "2") (pinfunction "2_2") (pintype "passive"))
      (node (ref "IC30") (pin "15") (pinfunction "15_15") (pintype "passive"))
    )
    (net (code "376") (name "Net-(A352-Pad1)") (class "Default")
      (node (ref "A352") (pin "1") (pinfunction "1_1") (pintype "passive"))
      (node (ref "A352") (pin "2") (pinfunction "2_2") (pintype "passive"))
      (node (ref "IC30") (pin "16") (pinfunction "16_16") (pintype "passive"))
    )
    (net (code "377") (name "Net-(A353-Pad1)") (class "Default")
      (node (ref "A353") (pin "1") (pinfunction "1_1") (pintype "passive"))
      (node (ref "A353") (pin "2") (pinfunction "2_2") (pintype "passive"))
      (node (ref "IC31") (pin "1") (pinfunction "1_1") (pintype "passive"))
    )
    (net (code "378") (name "Net-(A354-Pad1)") (class "Default")
      (node (ref "A354") (pin "1") (pinfunction "1_1") (pintype "passive"))
      (node (ref "A354") (pin "2") (pinfunction "2_2") (pintype "passive"))
      (node (ref "IC31") (pin "2") (pinfunction "2_2") (pintype "passive"))
    )
    (net (code "379") (name "Net-(A355-Pad1)") (class "Default")
      (node (ref "A355") (pin "1") (pinfunction "1_1") (pintype "passive"))
      (node (ref "A355") (pin "2") (pinfunction "2_2") (pintype "passive"))
      (node (ref "IC31") (pin "3") (pinfunction "3_3") (pintype "passive"))
    )
    (net (code "380") (name "Net-(A356-Pad1)") (class "Default")
      (node (ref "A356") (pin "1") (pinfunction "1_1") (pintype "passive"))
      (node (ref "A356") (pin "2") (pinfunction "2_2") (pintype "passive"))
      (node (ref "IC31") (pin "4") (pinfunction "4_4") (pintype "passive"))
    )
    (net (code "381") (name "Net-(A357-Pad1)") (class "Default")
      (node (ref "A357") (pin "1") (pinfunction "1_1") (pintype "passive"))
      (node (ref "A357") (pin "2") (pinfunction "2_2") (pintype "passive"))
      (node (ref "IC31") (pin "5") (pinfunction "5_5") (pintype "passive"))
    )
    (net (code "382") (name "Net-(A358-Pad1)") (class "Default")
      (node (ref "A358") (pin "1") (pinfunction "1_1") (pintype "passive"))
      (node (ref "A358") (pin "2") (pinfunction "2_2") (pintype "passive"))
      (node (ref "IC31") (pin "6") (pinfunction "6_6") (pintype "passive"))
    )
    (net (code "383") (name "Net-(A359-Pad1)") (class "Default")
      (node (ref "A359") (pin "1") (pinfunction "1_1") (pintype "passive"))
      (node (ref "A359") (pin "2") (pinfunction "2_2") (pintype "passive"))
      (node (ref "IC31") (pin "7") (pinfunction "7_7") (pintype "passive"))
    )
    (net (code "384") (name "Net-(A360-Pad1)") (class "Default")
      (node (ref "A360") (pin "1") (pinfunction "1_1") (pintype "passive"))
      (node (ref "A360") (pin "2") (pinfunction "2_2") (pintype "passive"))
      (node (ref "IC31") (pin "8") (pinfunction "8_8") (pintype "passive"))
    )
    (net (code "385") (name "Net-(A361-Pad1)") (class "Default")
      (node (ref "A361") (pin "1") (pinfunction "1_1") (pintype "passive"))
      (node (ref "A361") (pin "2") (pinfunction "2_2") (pintype "passive"))
      (node (ref "IC31") (pin "9") (pinfunction "9_9") (pintype "passive"))
    )
    (net (code "386") (name "Net-(A362-Pad1)") (class "Default")
      (node (ref "A362") (pin "1") (pinfunction "1_1") (pintype "passive"))
      (node (ref "A362") (pin "2") (pinfunction "2_2") (pintype "passive"))
      (node (ref "IC31") (pin "10") (pinfunction "10_10") (pintype "passive"))
    )
    (net (code "387") (name "Net-(A363-Pad1)") (class "Default")
      (node (ref "A363") (pin "1") (pinfunction "1_1") (pintype "passive"))
      (node (ref "A363") (pin "2") (pinfunction "2_2") (pintype "passive"))
      (node (ref "IC31") (pin "11") (pinfunction "11_11") (pintype "passive"))
    )
    (net (code "388") (name "Net-(A364-Pad1)") (class "Default")
      (node (ref "A364") (pin "1") (pinfunction "1_1") (pintype "passive"))
      (node (ref "A364") (pin "2") (pinfunction "2_2") (pintype "passive"))
      (node (ref "IC31") (pin "12") (pinfunction "12_12") (pintype "passive"))
    )
    (net (code "389") (name "Net-(A365-Pad1)") (class "Default")
      (node (ref "A365") (pin "1") (pinfunction "1_1") (pintype "passive"))
      (node (ref "A365") (pin "2") (pinfunction "2_2") (pintype "passive"))
      (node (ref "IC31") (pin "13") (pinfunction "13_13") (pintype "passive"))
    )
    (net (code "390") (name "Net-(A366-Pad1)") (class "Default")
      (node (ref "A366") (pin "1") (pinfunction "1_1") (pintype "passive"))
      (node (ref "A366") (pin "2") (pinfunction "2_2") (pintype "passive"))
      (node (ref "IC31") (pin "14") (pinfunction "14_14") (pintype "passive"))
    )
    (net (code "391") (name "Net-(A367-Pad1)") (class "Default")
      (node (ref "A367") (pin "1") (pinfunction "1_1") (pintype "passive"))
      (node (ref "A367") (pin "2") (pinfunction "2_2") (pintype "passive"))
      (node (ref "IC31") (pin "15") (pinfunction "15_15") (pintype "passive"))
    )
    (net (code "392") (name "Net-(A368-Pad1)") (class "Default")
      (node (ref "A368") (pin "1") (pinfunction "1_1") (pintype "passive"))
      (node (ref "A368") (pin "2") (pinfunction "2_2") (pintype "passive"))
      (node (ref "IC31") (pin "16") (pinfunction "16_16") (pintype "passive"))
    )
    (net (code "393") (name "Net-(A369-Pad1)") (class "Default")
      (node (ref "A369") (pin "1") (pinfunction "1_1") (pintype "passive"))
      (node (ref "A369") (pin "2") (pinfunction "2_2") (pintype "passive"))
      (node (ref "IC32") (pin "1") (pinfunction "1_1") (pintype "passive"))
    )
    (net (code "394") (name "Net-(A370-Pad1)") (class "Default")
      (node (ref "A370") (pin "1") (pinfunction "1_1") (pintype "passive"))
      (node (ref "A370") (pin "2") (pinfunction "2_2") (pintype "passive"))
      (node (ref "IC32") (pin "2") (pinfunction "2_2") (pintype "passive"))
    )
    (net (code "395") (name "Net-(A371-Pad1)") (class "Default")
      (node (ref "A371") (pin "1") (pinfunction "1_1") (pintype "passive"))
      (node (ref "A371") (pin "2") (pinfunction "2_2") (pintype "passive"))
      (node (ref "IC32") (pin "3") (pinfunction "3_3") (pintype "passive"))
    )
    (net (code "396") (name "Net-(A372-Pad1)") (class "Default")
      (node (ref "A372") (pin "1") (pinfunction "1_1") (pintype "passive"))
      (node (ref "A372") (pin "2") (pinfunction "2_2") (pintype "passive"))
      (node (ref "IC32") (pin "4") (pinfunction "4_4") (pintype "passive"))
    )
    (net (code "397") (name "Net-(A373-Pad1)") (class "Default")
      (node (ref "A373") (pin "1") (pinfunction "1_1") (pintype "passive"))
      (node (ref "A373") (pin "2") (pinfunction "2_2") (pintype "passive"))
      (node (ref "IC32") (pin "5") (pinfunction "5_5") (pintype "passive"))
    )
    (net (code "398") (name "Net-(A374-Pad1)") (class "Default")
      (node (ref "A374") (pin "1") (pinfunction "1_1") (pintype "passive"))
      (node (ref "A374") (pin "2") (pinfunction "2_2") (pintype "passive"))
      (node (ref "IC32") (pin "6") (pinfunction "6_6") (pintype "passive"))
    )
    (net (code "399") (name "Net-(A375-Pad1)") (class "Default")
      (node (ref "A375") (pin "1") (pinfunction "1_1") (pintype "passive"))
      (node (ref "A375") (pin "2") (pinfunction "2_2") (pintype "passive"))
      (node (ref "IC32") (pin "7") (pinfunction "7_7") (pintype "passive"))
    )
    (net (code "400") (name "Net-(A376-Pad1)") (class "Default")
      (node (ref "A376") (pin "1") (pinfunction "1_1") (pintype "passive"))
      (node (ref "A376") (pin "2") (pinfunction "2_2") (pintype "passive"))
      (node (ref "IC32") (pin "8") (pinfunction "8_8") (pintype "passive"))
    )
    (net (code "401") (name "Net-(A377-Pad1)") (class "Default")
      (node (ref "A377") (pin "1") (pinfunction "1_1") (pintype "passive"))
      (node (ref "A377") (pin "2") (pinfunction "2_2") (pintype "passive"))
      (node (ref "IC32") (pin "9") (pinfunction "9_9") (pintype "passive"))
    )
    (net (code "402") (name "Net-(A378-Pad1)") (class "Default")
      (node (ref "A378") (pin "1") (pinfunction "1_1") (pintype "passive"))
      (node (ref "A378") (pin "2") (pinfunction "2_2") (pintype "passive"))
      (node (ref "IC32") (pin "10") (pinfunction "10_10") (pintype "passive"))
    )
    (net (code "403") (name "Net-(A379-Pad1)") (class "Default")
      (node (ref "A379") (pin "1") (pinfunction "1_1") (pintype "passive"))
      (node (ref "A379") (pin "2") (pinfunction "2_2") (pintype "passive"))
      (node (ref "IC32") (pin "11") (pinfunction "11_11") (pintype "passive"))
    )
    (net (code "404") (name "Net-(A380-Pad1)") (class "Default")
      (node (ref "A380") (pin "1") (pinfunction "1_1") (pintype "passive"))
      (node (ref "A380") (pin "2") (pinfunction "2_2") (pintype "passive"))
      (node (ref "IC32") (pin "12") (pinfunction "12_12") (pintype "passive"))
    )
    (net (code "405") (name "Net-(A381-Pad1)") (class "Default")
      (node (ref "A381") (pin "1") (pinfunction "1_1") (pintype "passive"))
      (node (ref "A381") (pin "2") (pinfunction "2_2") (pintype "passive"))
      (node (ref "IC32") (pin "13") (pinfunction "13_13") (pintype "passive"))
    )
    (net (code "406") (name "Net-(A382-Pad1)") (class "Default")
      (node (ref "A382") (pin "1") (pinfunction "1_1") (pintype "passive"))
      (node (ref "A382") (pin "2") (pinfunction "2_2") (pintype "passive"))
      (node (ref "IC32") (pin "14") (pinfunction "14_14") (pintype "passive"))
    )
    (net (code "407") (name "Net-(A383-Pad1)") (class "Default")
      (node (ref "A383") (pin "1") (pinfunction "1_1") (pintype "passive"))
      (node (ref "A383") (pin "2") (pinfunction "2_2") (pintype "passive"))
      (node (ref "IC32") (pin "15") (pinfunction "15_15") (pintype "passive"))
    )
    (net (code "408") (name "Net-(A384-Pad1)") (class "Default")
      (node (ref "A384") (pin "1") (pinfunction "1_1") (pintype "passive"))
      (node (ref "A384") (pin "2") (pinfunction "2_2") (pintype "passive"))
      (node (ref "IC32") (pin "16") (pinfunction "16_16") (pintype "passive"))
    )
    (net (code "409") (name "Net-(A385-Pad1)") (class "Default")
      (node (ref "A385") (pin "1") (pinfunction "1_1") (pintype "passive"))
      (node (ref "A385") (pin "2") (pinfunction "2_2") (pintype "passive"))
      (node (ref "IC33") (pin "1") (pinfunction "1_1") (pintype "passive"))
    )
    (net (code "410") (name "Net-(A386-Pad1)") (class "Default")
      (node (ref "A386") (pin "1") (pinfunction "1_1") (pintype "passive"))
      (node (ref "A386") (pin "2") (pinfunction "2_2") (pintype "passive"))
      (node (ref "IC33") (pin "2") (pinfunction "2_2") (pintype "passive"))
    )
    (net (code "411") (name "Net-(A387-Pad1)") (class "Default")
      (node (ref "A387") (pin "1") (pinfunction "1_1") (pintype "passive"))
      (node (ref "A387") (pin "2") (pinfunction "2_2") (pintype "passive"))
      (node (ref "IC33") (pin "3") (pinfunction "3_3") (pintype "passive"))
    )
    (net (code "412") (name "Net-(A388-Pad1)") (class "Default")
      (node (ref "A388") (pin "1") (pinfunction "1_1") (pintype "passive"))
      (node (ref "A388") (pin "2") (pinfunction "2_2") (pintype "passive"))
      (node (ref "IC33") (pin "4") (pinfunction "4_4") (pintype "passive"))
    )
    (net (code "413") (name "Net-(A389-Pad1)") (class "Default")
      (node (ref "A389") (pin "1") (pinfunction "1_1") (pintype "passive"))
      (node (ref "A389") (pin "2") (pinfunction "2_2") (pintype "passive"))
      (node (ref "IC33") (pin "5") (pinfunction "5_5") (pintype "passive"))
    )
    (net (code "414") (name "Net-(A390-Pad1)") (class "Default")
      (node (ref "A390") (pin "1") (pinfunction "1_1") (pintype "passive"))
      (node (ref "A390") (pin "2") (pinfunction "2_2") (pintype "passive"))
      (node (ref "IC33") (pin "6") (pinfunction "6_6") (pintype "passive"))
    )
    (net (code "415") (name "Net-(A391-Pad1)") (class "Default")
      (node (ref "A391") (pin "1") (pinfunction "1_1") (pintype "passive"))
      (node (ref "A391") (pin "2") (pinfunction "2_2") (pintype "passive"))
      (node (ref "IC33") (pin "7") (pinfunction "7_7") (pintype "passive"))
    )
    (net (code "416") (name "Net-(A392-Pad1)") (class "Default")
      (node (ref "A392") (pin "1") (pinfunction "1_1") (pintype "passive"))
      (node (ref "A392") (pin "2") (pinfunction "2_2") (pintype "passive"))
      (node (ref "IC33") (pin "8") (pinfunction "8_8") (pintype "passive"))
    )
    (net (code "417") (name "Net-(A393-Pad1)") (class "Default")
      (node (ref "A393") (pin "1") (pinfunction "1_1") (pintype "passive"))
      (node (ref "A393") (pin "2") (pinfunction "2_2") (pintype "passive"))
      (node (ref "IC33") (pin "9") (pinfunction "9_9") (pintype "passive"))
    )
    (net (code "418") (name "Net-(A394-Pad1)") (class "Default")
      (node (ref "A394") (pin "1") (pinfunction "1_1") (pintype "passive"))
      (node (ref "A394") (pin "2") (pinfunction "2_2") (pintype "passive"))
      (node (ref "IC33") (pin "10") (pinfunction "10_10") (pintype "passive"))
    )
    (net (code "419") (name "Net-(A395-Pad1)") (class "Default")
      (node (ref "A395") (pin "1") (pinfunction "1_1") (pintype "passive"))
      (node (ref "A395") (pin "2") (pinfunction "2_2") (pintype "passive"))
      (node (ref "IC33") (pin "11") (pinfunction "11_11") (pintype "passive"))
    )
    (net (code "420") (name "Net-(A396-Pad1)") (class "Default")
      (node (ref "A396") (pin "1") (pinfunction "1_1") (pintype "passive"))
      (node (ref "A396") (pin "2") (pinfunction "2_2") (pintype "passive"))
      (node (ref "IC33") (pin "12") (pinfunction "12_12") (pintype "passive"))
    )
    (net (code "421") (name "Net-(A397-Pad1)") (class "Default")
      (node (ref "A397") (pin "1") (pinfunction "1_1") (pintype "passive"))
      (node (ref "A397") (pin "2") (pinfunction "2_2") (pintype "passive"))
      (node (ref "IC33") (pin "13") (pinfunction "13_13") (pintype "passive"))
    )
    (net (code "422") (name "Net-(A398-Pad1)") (class "Default")
      (node (ref "A398") (pin "1") (pinfunction "1_1") (pintype "passive"))
      (node (ref "A398") (pin "2") (pinfunction "2_2") (pintype "passive"))
      (node (ref "IC33") (pin "14") (pinfunction "14_14") (pintype "passive"))
    )
    (net (code "423") (name "Net-(A399-Pad1)") (class "Default")
      (node (ref "A399") (pin "1") (pinfunction "1_1") (pintype "passive"))
      (node (ref "A399") (pin "2") (pinfunction "2_2") (pintype "passive"))
      (node (ref "IC33") (pin "15") (pinfunction "15_15") (pintype "passive"))
    )
    (net (code "424") (name "Net-(A400-Pad1)") (class "Default")
      (node (ref "A400") (pin "1") (pinfunction "1_1") (pintype "passive"))
      (node (ref "A400") (pin "2") (pinfunction "2_2") (pintype "passive"))
      (node (ref "IC33") (pin "16") (pinfunction "16_16") (pintype "passive"))
    )
    (net (code "425") (name "Net-(A401-Pad1)") (class "Default")
      (node (ref "A401") (pin "1") (pinfunction "1_1") (pintype "passive"))
      (node (ref "A401") (pin "2") (pinfunction "2_2") (pintype "passive"))
      (node (ref "IC34") (pin "1") (pinfunction "1_1") (pintype "passive"))
    )
    (net (code "426") (name "Net-(A402-Pad1)") (class "Default")
      (node (ref "A402") (pin "1") (pinfunction "1_1") (pintype "passive"))
      (node (ref "A402") (pin "2") (pinfunction "2_2") (pintype "passive"))
      (node (ref "IC34") (pin "2") (pinfunction "2_2") (pintype "passive"))
    )
    (net (code "427") (name "Net-(A403-Pad1)") (class "Default")
      (node (ref "A403") (pin "1") (pinfunction "1_1") (pintype "passive"))
      (node (ref "A403") (pin "2") (pinfunction "2_2") (pintype "passive"))
      (node (ref "IC34") (pin "3") (pinfunction "3_3") (pintype "passive"))
    )
    (net (code "428") (name "Net-(A404-Pad1)") (class "Default")
      (node (ref "A404") (pin "1") (pinfunction "1_1") (pintype "passive"))
      (node (ref "A404") (pin "2") (pinfunction "2_2") (pintype "passive"))
      (node (ref "IC34") (pin "4") (pinfunction "4_4") (pintype "passive"))
    )
    (net (code "429") (name "Net-(A405-Pad1)") (class "Default")
      (node (ref "A405") (pin "1") (pinfunction "1_1") (pintype "passive"))
      (node (ref "A405") (pin "2") (pinfunction "2_2") (pintype "passive"))
      (node (ref "IC34") (pin "5") (pinfunction "5_5") (pintype "passive"))
    )
    (net (code "430") (name "Net-(A406-Pad1)") (class "Default")
      (node (ref "A406") (pin "1") (pinfunction "1_1") (pintype "passive"))
      (node (ref "A406") (pin "2") (pinfunction "2_2") (pintype "passive"))
      (node (ref "IC34") (pin "6") (pinfunction "6_6") (pintype "passive"))
    )
    (net (code "431") (name "Net-(A407-Pad1)") (class "Default")
      (node (ref "A407") (pin "1") (pinfunction "1_1") (pintype "passive"))
      (node (ref "A407") (pin "2") (pinfunction "2_2") (pintype "passive"))
      (node (ref "IC34") (pin "7") (pinfunction "7_7") (pintype "passive"))
    )
    (net (code "432") (name "Net-(A408-Pad1)") (class "Default")
      (node (ref "A408") (pin "1") (pinfunction "1_1") (pintype "passive"))
      (node (ref "A408") (pin "2") (pinfunction "2_2") (pintype "passive"))
      (node (ref "IC34") (pin "8") (pinfunction "8_8") (pintype "passive"))
    )
    (net (code "433") (name "Net-(A409-Pad1)") (class "Default")
      (node (ref "A409") (pin "1") (pinfunction "1_1") (pintype "passive"))
      (node (ref "A409") (pin "2") (pinfunction "2_2") (pintype "passive"))
      (node (ref "IC34") (pin "9") (pinfunction "9_9") (pintype "passive"))
    )
    (net (code "434") (name "Net-(A410-Pad1)") (class "Default")
      (node (ref "A410") (pin "1") (pinfunction "1_1") (pintype "passive"))
      (node (ref "A410") (pin "2") (pinfunction "2_2") (pintype "passive"))
      (node (ref "IC34") (pin "10") (pinfunction "10_10") (pintype "passive"))
    )
    (net (code "435") (name "Net-(A411-Pad1)") (class "Default")
      (node (ref "A411") (pin "1") (pinfunction "1_1") (pintype "passive"))
      (node (ref "A411") (pin "2") (pinfunction "2_2") (pintype "passive"))
      (node (ref "IC34") (pin "11") (pinfunction "11_11") (pintype "passive"))
    )
    (net (code "436") (name "Net-(A412-Pad1)") (class "Default")
      (node (ref "A412") (pin "1") (pinfunction "1_1") (pintype "passive"))
      (node (ref "A412") (pin "2") (pinfunction "2_2") (pintype "passive"))
      (node (ref "IC34") (pin "12") (pinfunction "12_12") (pintype "passive"))
    )
    (net (code "437") (name "Net-(A413-Pad1)") (class "Default")
      (node (ref "A413") (pin "1") (pinfunction "1_1") (pintype "passive"))
      (node (ref "A413") (pin "2") (pinfunction "2_2") (pintype "passive"))
      (node (ref "IC34") (pin "13") (pinfunction "13_13") (pintype "passive"))
    )
    (net (code "438") (name "Net-(A414-Pad1)") (class "Default")
      (node (ref "A414") (pin "1") (pinfunction "1_1") (pintype "passive"))
      (node (ref "A414") (pin "2") (pinfunction "2_2") (pintype "passive"))
      (node (ref "IC34") (pin "14") (pinfunction "14_14") (pintype "passive"))
    )
    (net (code "439") (name "Net-(A415-Pad1)") (class "Default")
      (node (ref "A415") (pin "1") (pinfunction "1_1") (pintype "passive"))
      (node (ref "A415") (pin "2") (pinfunction "2_2") (pintype "passive"))
      (node (ref "IC34") (pin "15") (pinfunction "15_15") (pintype "passive"))
    )
    (net (code "440") (name "Net-(A416-Pad1)") (class "Default")
      (node (ref "A416") (pin "1") (pinfunction "1_1") (pintype "passive"))
      (node (ref "A416") (pin "2") (pinfunction "2_2") (pintype "passive"))
      (node (ref "IC34") (pin "16") (pinfunction "16_16") (pintype "passive"))
    )
    (net (code "441") (name "Net-(A417-Pad1)") (class "Default")
      (node (ref "A417") (pin "1") (pinfunction "1_1") (pintype "passive"))
      (node (ref "A417") (pin "2") (pinfunction "2_2") (pintype "passive"))
      (node (ref "IC35") (pin "1") (pinfunction "1_1") (pintype "passive"))
    )
    (net (code "442") (name "Net-(A418-Pad1)") (class "Default")
      (node (ref "A418") (pin "1") (pinfunction "1_1") (pintype "passive"))
      (node (ref "A418") (pin "2") (pinfunction "2_2") (pintype "passive"))
      (node (ref "IC35") (pin "2") (pinfunction "2_2") (pintype "passive"))
    )
    (net (code "443") (name "Net-(A419-Pad1)") (class "Default")
      (node (ref "A419") (pin "1") (pinfunction "1_1") (pintype "passive"))
      (node (ref "A419") (pin "2") (pinfunction "2_2") (pintype "passive"))
      (node (ref "IC35") (pin "3") (pinfunction "3_3") (pintype "passive"))
    )
    (net (code "444") (name "Net-(A420-Pad1)") (class "Default")
      (node (ref "A420") (pin "1") (pinfunction "1_1") (pintype "passive"))
      (node (ref "A420") (pin "2") (pinfunction "2_2") (pintype "passive"))
      (node (ref "IC35") (pin "4") (pinfunction "4_4") (pintype "passive"))
    )
    (net (code "445") (name "Net-(A421-Pad1)") (class "Default")
      (node (ref "A421") (pin "1") (pinfunction "1_1") (pintype "passive"))
      (node (ref "A421") (pin "2") (pinfunction "2_2") (pintype "passive"))
      (node (ref "IC35") (pin "5") (pinfunction "5_5") (pintype "passive"))
    )
    (net (code "446") (name "Net-(A422-Pad1)") (class "Default")
      (node (ref "A422") (pin "1") (pinfunction "1_1") (pintype "passive"))
      (node (ref "A422") (pin "2") (pinfunction "2_2") (pintype "passive"))
      (node (ref "IC35") (pin "6") (pinfunction "6_6") (pintype "passive"))
    )
    (net (code "447") (name "Net-(A423-Pad1)") (class "Default")
      (node (ref "A423") (pin "1") (pinfunction "1_1") (pintype "passive"))
      (node (ref "A423") (pin "2") (pinfunction "2_2") (pintype "passive"))
      (node (ref "IC35") (pin "7") (pinfunction "7_7") (pintype "passive"))
    )
    (net (code "448") (name "Net-(A424-Pad1)") (class "Default")
      (node (ref "A424") (pin "1") (pinfunction "1_1") (pintype "passive"))
      (node (ref "A424") (pin "2") (pinfunction "2_2") (pintype "passive"))
      (node (ref "IC35") (pin "8") (pinfunction "8_8") (pintype "passive"))
    )
    (net (code "449") (name "Net-(A425-Pad1)") (class "Default")
      (node (ref "A425") (pin "1") (pinfunction "1_1") (pintype "passive"))
      (node (ref "A425") (pin "2") (pinfunction "2_2") (pintype "passive"))
      (node (ref "IC35") (pin "9") (pinfunction "9_9") (pintype "passive"))
    )
    (net (code "450") (name "Net-(A426-Pad1)") (class "Default")
      (node (ref "A426") (pin "1") (pinfunction "1_1") (pintype "passive"))
      (node (ref "A426") (pin "2") (pinfunction "2_2") (pintype "passive"))
      (node (ref "IC35") (pin "10") (pinfunction "10_10") (pintype "passive"))
    )
    (net (code "451") (name "Net-(A427-Pad1)") (class "Default")
      (node (ref "A427") (pin "1") (pinfunction "1_1") (pintype "passive"))
      (node (ref "A427") (pin "2") (pinfunction "2_2") (pintype "passive"))
      (node (ref "IC35") (pin "11") (pinfunction "11_11") (pintype "passive"))
    )
    (net (code "452") (name "Net-(A428-Pad1)") (class "Default")
      (node (ref "A428") (pin "1") (pinfunction "1_1") (pintype "passive"))
      (node (ref "A428") (pin "2") (pinfunction "2_2") (pintype "passive"))
      (node (ref "IC35") (pin "12") (pinfunction "12_12") (pintype "passive"))
    )
    (net (code "453") (name "Net-(A429-Pad1)") (class "Default")
      (node (ref "A429") (pin "1") (pinfunction "1_1") (pintype "passive"))
      (node (ref "A429") (pin "2") (pinfunction "2_2") (pintype "passive"))
      (node (ref "IC35") (pin "13") (pinfunction "13_13") (pintype "passive"))
    )
    (net (code "454") (name "Net-(A430-Pad1)") (class "Default")
      (node (ref "A430") (pin "1") (pinfunction "1_1") (pintype "passive"))
      (node (ref "A430") (pin "2") (pinfunction "2_2") (pintype "passive"))
      (node (ref "IC35") (pin "14") (pinfunction "14_14") (pintype "passive"))
    )
    (net (code "455") (name "Net-(A431-Pad1)") (class "Default")
      (node (ref "A431") (pin "1") (pinfunction "1_1") (pintype "passive"))
      (node (ref "A431") (pin "2") (pinfunction "2_2") (pintype "passive"))
      (node (ref "IC35") (pin "15") (pinfunction "15_15") (pintype "passive"))
    )
    (net (code "456") (name "Net-(A432-Pad1)") (class "Default")
      (node (ref "A432") (pin "1") (pinfunction "1_1") (pintype "passive"))
      (node (ref "A432") (pin "2") (pinfunction "2_2") (pintype "passive"))
      (node (ref "IC35") (pin "16") (pinfunction "16_16") (pintype "passive"))
    )
    (net (code "457") (name "Net-(A433-Pad1)") (class "Default")
      (node (ref "A433") (pin "1") (pinfunction "1_1") (pintype "passive"))
      (node (ref "A433") (pin "2") (pinfunction "2_2") (pintype "passive"))
      (node (ref "IC36") (pin "1") (pinfunction "1_1") (pintype "passive"))
    )
    (net (code "458") (name "Net-(A434-Pad1)") (class "Default")
      (node (ref "A434") (pin "1") (pinfunction "1_1") (pintype "passive"))
      (node (ref "A434") (pin "2") (pinfunction "2_2") (pintype "passive"))
      (node (ref "IC36") (pin "2") (pinfunction "2_2") (pintype "passive"))
    )
    (net (code "459") (name "Net-(A435-Pad1)") (class "Default")
      (node (ref "A435") (pin "1") (pinfunction "1_1") (pintype "passive"))
      (node (ref "A435") (pin "2") (pinfunction "2_2") (pintype "passive"))
      (node (ref "IC36") (pin "3") (pinfunction "3_3") (pintype "passive"))
    )
    (net (code "460") (name "Net-(A436-Pad1)") (class "Default")
      (node (ref "A436") (pin "1") (pinfunction "1_1") (pintype "passive"))
      (node (ref "A436") (pin "2") (pinfunction "2_2") (pintype "passive"))
      (node (ref "IC36") (pin "4") (pinfunction "4_4") (pintype "passive"))
    )
    (net (code "461") (name "Net-(A437-Pad1)") (class "Default")
      (node (ref "A437") (pin "1") (pinfunction "1_1") (pintype "passive"))
      (node (ref "A437") (pin "2") (pinfunction "2_2") (pintype "passive"))
      (node (ref "IC36") (pin "5") (pinfunction "5_5") (pintype "passive"))
    )
    (net (code "462") (name "Net-(A438-Pad1)") (class "Default")
      (node (ref "A438") (pin "1") (pinfunction "1_1") (pintype "passive"))
      (node (ref "A438") (pin "2") (pinfunction "2_2") (pintype "passive"))
      (node (ref "IC36") (pin "6") (pinfunction "6_6") (pintype "passive"))
    )
    (net (code "463") (name "Net-(A439-Pad1)") (class "Default")
      (node (ref "A439") (pin "1") (pinfunction "1_1") (pintype "passive"))
      (node (ref "A439") (pin "2") (pinfunction "2_2") (pintype "passive"))
      (node (ref "IC36") (pin "7") (pinfunction "7_7") (pintype "passive"))
    )
    (net (code "464") (name "Net-(A440-Pad1)") (class "Default")
      (node (ref "A440") (pin "1") (pinfunction "1_1") (pintype "passive"))
      (node (ref "A440") (pin "2") (pinfunction "2_2") (pintype "passive"))
      (node (ref "IC36") (pin "8") (pinfunction "8_8") (pintype "passive"))
    )
    (net (code "465") (name "Net-(A441-Pad1)") (class "Default")
      (node (ref "A441") (pin "1") (pinfunction "1_1") (pintype "passive"))
      (node (ref "A441") (pin "2") (pinfunction "2_2") (pintype "passive"))
      (node (ref "IC36") (pin "9") (pinfunction "9_9") (pintype "passive"))
    )
    (net (code "466") (name "Net-(A442-Pad1)") (class "Default")
      (node (ref "A442") (pin "1") (pinfunction "1_1") (pintype "passive"))
      (node (ref "A442") (pin "2") (pinfunction "2_2") (pintype "passive"))
      (node (ref "IC36") (pin "10") (pinfunction "10_10") (pintype "passive"))
    )
    (net (code "467") (name "Net-(A443-Pad1)") (class "Default")
      (node (ref "A443") (pin "1") (pinfunction "1_1") (pintype "passive"))
      (node (ref "A443") (pin "2") (pinfunction "2_2") (pintype "passive"))
      (node (ref "IC36") (pin "11") (pinfunction "11_11") (pintype "passive"))
    )
    (net (code "468") (name "Net-(A444-Pad1)") (class "Default")
      (node (ref "A444") (pin "1") (pinfunction "1_1") (pintype "passive"))
      (node (ref "A444") (pin "2") (pinfunction "2_2") (pintype "passive"))
      (node (ref "IC36") (pin "12") (pinfunction "12_12") (pintype "passive"))
    )
    (net (code "469") (name "Net-(A445-Pad1)") (class "Default")
      (node (ref "A445") (pin "1") (pinfunction "1_1") (pintype "passive"))
      (node (ref "A445") (pin "2") (pinfunction "2_2") (pintype "passive"))
      (node (ref "IC36") (pin "13") (pinfunction "13_13") (pintype "passive"))
    )
    (net (code "470") (name "Net-(A446-Pad1)") (class "Default")
      (node (ref "A446") (pin "1") (pinfunction "1_1") (pintype "passive"))
      (node (ref "A446") (pin "2") (pinfunction "2_2") (pintype "passive"))
      (node (ref "IC36") (pin "14") (pinfunction "14_14") (pintype "passive"))
    )
    (net (code "471") (name "Net-(A447-Pad1)") (class "Default")
      (node (ref "A447") (pin "1") (pinfunction "1_1") (pintype "passive"))
      (node (ref "A447") (pin "2") (pinfunction "2_2") (pintype "passive"))
      (node (ref "IC36") (pin "15") (pinfunction "15_15") (pintype "passive"))
    )
    (net (code "472") (name "Net-(A448-Pad1)") (class "Default")
      (node (ref "A448") (pin "1") (pinfunction "1_1") (pintype "passive"))
      (node (ref "A448") (pin "2") (pinfunction "2_2") (pintype "passive"))
      (node (ref "IC36") (pin "16") (pinfunction "16_16") (pintype "passive"))
    )
    (net (code "473") (name "Net-(B1-+-Pad+@1)") (class "Default")
      (node (ref "B1") (pin "+") (pinfunction "+_+") (pintype "passive"))
      (node (ref "B1") (pin "+@1") (pinfunction "+_+@1") (pintype "passive"))
      (node (ref "B1") (pin "+@2") (pinfunction "+_+@2") (pintype "passive"))
      (node (ref "B1") (pin "+@3") (pinfunction "+_+@3") (pintype "passive"))
      (node (ref "B1") (pin "+@4") (pinfunction "+_+@4") (pintype "passive"))
      (node (ref "D1") (pin "A") (pinfunction "A_A") (pintype "passive"))
    )
    (net (code "474") (name "Net-(IC2A-A5)") (class "Default")
      (node (ref "IC2") (pin "6") (pinfunction "A5_6") (pintype "bidirectional"))
      (node (ref "R4") (pin "2") (pinfunction "2_2") (pintype "passive"))
    )
    (net (code "475") (name "Net-(IC2A-A6)") (class "Default")
      (node (ref "IC2") (pin "7") (pinfunction "A6_7") (pintype "bidirectional"))
      (node (ref "R3") (pin "2") (pinfunction "2_2") (pintype "passive"))
    )
    (net (code "476") (name "Net-(IC2A-A7)") (class "Default")
      (node (ref "IC2") (pin "8") (pinfunction "A7_8") (pintype "bidirectional"))
      (node (ref "R2") (pin "2") (pinfunction "2_2") (pintype "passive"))
    )
    (net (code "477") (name "Net-(IC2A-A8)") (class "Default")
      (node (ref "IC2") (pin "9") (pinfunction "A8_9") (pintype "bidirectional"))
      (node (ref "R1") (pin "2") (pinfunction "2_2") (pintype "passive"))
    )
    (net (code "478") (name "Net-(IC5A-Y0)") (class "Default")
      (node (ref "IC5") (pin "15") (pinfunction "Y0_15") (pintype "output"))
      (node (ref "S1") (pin "9") (pinfunction "9_9") (pintype "passive"))
    )
    (net (code "479") (name "Net-(IC5A-Y1)") (class "Default")
      (node (ref "IC5") (pin "14") (pinfunction "Y1_14") (pintype "output"))
      (node (ref "S1") (pin "10") (pinfunction "10_10") (pintype "passive"))
    )
    (net (code "480") (name "Net-(IC5A-Y2)") (class "Default")
      (node (ref "IC5") (pin "13") (pinfunction "Y2_13") (pintype "output"))
      (node (ref "S1") (pin "11") (pinfunction "11_11") (pintype "passive"))
    )
    (net (code "481") (name "Net-(IC5A-Y3)") (class "Default")
      (node (ref "IC5") (pin "12") (pinfunction "Y3_12") (pintype "output"))
      (node (ref "S1") (pin "12") (pinfunction "12_12") (pintype "passive"))
    )
    (net (code "482") (name "Net-(IC5A-Y4)") (class "Default")
      (node (ref "IC5") (pin "11") (pinfunction "Y4_11") (pintype "output"))
      (node (ref "S1") (pin "13") (pinfunction "13_13") (pintype "passive"))
    )
    (net (code "483") (name "Net-(IC5A-Y5)") (class "Default")
      (node (ref "IC5") (pin "10") (pinfunction "Y5_10") (pintype "output"))
      (node (ref "S1") (pin "14") (pinfunction "14_14") (pintype "passive"))
    )
    (net (code "484") (name "Net-(IC5A-Y6)") (class "Default")
      (node (ref "IC5") (pin "9") (pinfunction "Y6_9") (pintype "output"))
      (node (ref "S1") (pin "15") (pinfunction "15_15") (pintype "passive"))
    )
    (net (code "485") (name "Net-(IC5A-Y7)") (class "Default")
      (node (ref "IC5") (pin "7") (pinfunction "Y7_7") (pintype "output"))
      (node (ref "S1") (pin "16") (pinfunction "16_16") (pintype "passive"))
    )
    (net (code "486") (name "Net-(IC6A-I0)") (class "Default")
      (node (ref "IC6") (pin "1") (pinfunction "I0_1") (pintype "input"))
      (node (ref "R5") (pin "8") (pinfunction "1_8") (pintype "passive"))
      (node (ref "S1") (pin "1") (pinfunction "1_1") (pintype "passive"))
    )
    (net (code "487") (name "Net-(IC6A-I1)") (class "Default")
      (node (ref "IC6") (pin "2") (pinfunction "I1_2") (pintype "input"))
      (node (ref "R5") (pin "1") (pinfunction "1_1") (pintype "passive"))
      (node (ref "S1") (pin "8") (pinfunction "8_8") (pintype "passive"))
    )
    (net (code "488") (name "Net-(IC6A-I2)") (class "Default")
      (node (ref "IC6") (pin "3") (pinfunction "I2_3") (pintype "input"))
      (node (ref "R5") (pin "7") (pinfunction "1_7") (pintype "passive"))
      (node (ref "S1") (pin "2") (pinfunction "2_2") (pintype "passive"))
    )
    (net (code "489") (name "Net-(IC6A-I3)") (class "Default")
      (node (ref "IC6") (pin "4") (pinfunction "I3_4") (pintype "input"))
      (node (ref "R5") (pin "2") (pinfunction "1_2") (pintype "passive"))
      (node (ref "S1") (pin "7") (pinfunction "7_7") (pintype "passive"))
    )
    (net (code "490") (name "Net-(IC6A-I4)") (class "Default")
      (node (ref "IC6") (pin "5") (pinfunction "I4_5") (pintype "input"))
      (node (ref "R5") (pin "6") (pinfunction "1_6") (pintype "passive"))
      (node (ref "S1") (pin "3") (pinfunction "3_3") (pintype "passive"))
    )
    (net (code "491") (name "Net-(IC6A-I5)") (class "Default")
      (node (ref "IC6") (pin "6") (pinfunction "I5_6") (pintype "input"))
      (node (ref "R5") (pin "5") (pinfunction "1_5") (pintype "passive"))
      (node (ref "S1") (pin "4") (pinfunction "4_4") (pintype "passive"))
    )
    (net (code "492") (name "Net-(IC6A-I6)") (class "Default")
      (node (ref "IC6") (pin "11") (pinfunction "I6_11") (pintype "input"))
      (node (ref "R5") (pin "3") (pinfunction "1_3") (pintype "passive"))
      (node (ref "S1") (pin "6") (pinfunction "6_6") (pintype "passive"))
    )
    (net (code "493") (name "Net-(IC6A-I7)") (class "Default")
      (node (ref "IC6") (pin "12") (pinfunction "I7_12") (pintype "input"))
      (node (ref "R5") (pin "4") (pinfunction "1_4") (pintype "passive"))
      (node (ref "S1") (pin "5") (pinfunction "5_5") (pintype "passive"))
    )
    (net (code "494") (name "Net-(IC7A-I1)") (class "Default")
      (node (ref "IC7") (pin "2") (pinfunction "I1_2") (pintype "input"))
      (node (ref "IC8") (pin "13") (pinfunction "Y6_13") (pintype "tri_state"))
    )
    (net (code "495") (name "Net-(IC7A-I2)") (class "Default")
      (node (ref "IC7") (pin "4") (pinfunction "I2_4") (pintype "input"))
      (node (ref "IC8") (pin "15") (pinfunction "Y4_15") (pintype "tri_state"))
    )
    (net (code "496") (name "Net-(IC7A-I3)") (class "Default")
      (node (ref "IC7") (pin "5") (pinfunction "I3_5") (pintype "input"))
      (node (ref "IC8") (pin "17") (pinfunction "Y2_17") (pintype "tri_state"))
    )
    (net (code "497") (name "Net-(IC7B-I0)") (class "Default")
      (node (ref "IC7") (pin "9") (pinfunction "I0_9") (pintype "input"))
      (node (ref "IC8") (pin "18") (pinfunction "Y1_18") (pintype "tri_state"))
      (node (ref "IC8") (pin "3") (pinfunction "A2_3") (pintype "input"))
    )
    (net (code "498") (name "Net-(IC7B-I1)") (class "Default")
      (node (ref "IC7") (pin "10") (pinfunction "I1_10") (pintype "input"))
      (node (ref "IC8") (pin "12") (pinfunction "Y7_12") (pintype "tri_state"))
    )
    (net (code "499") (name "Net-(IC8A-A4)") (class "Default")
      (node (ref "IC8") (pin "16") (pinfunction "Y3_16") (pintype "tri_state"))
      (node (ref "IC8") (pin "5") (pinfunction "A4_5") (pintype "input"))
    )
    (net (code "500") (name "Net-(IC8A-A6)") (class "Default")
      (node (ref "IC8") (pin "14") (pinfunction "Y5_14") (pintype "tri_state"))
      (node (ref "IC8") (pin "7") (pinfunction "A6_7") (pintype "input"))
    )
    (net (code "501") (name "Net-(Q1-B)") (class "Default")
      (node (ref "Q1") (pin "2") (pinfunction "B_2") (pintype "passive"))
      (node (ref "R6") (pin "2") (pinfunction "2_2") (pintype "passive"))
    )
    (net (code "502") (name "Net-(SV1-Pad1)") (class "Default")
      (node (ref "SV1") (pin "1") (pinfunction "1_1") (pintype "passive"))
      (node (ref "SV1") (pin "3") (pinfunction "3_3") (pintype "passive"))
      (node (ref "SV1") (pin "5") (pinfunction "5_5") (pintype "passive"))
      (node (ref "SV1") (pin "7") (pinfunction "7_7") (pintype "passive"))
      (node (ref "SV1") (pin "9") (pinfunction "9_9") (pintype "passive"))
    )
    (net (code "503") (name "Net-(SV1-Pad10)") (class "Default")
      (node (ref "SV1") (pin "10") (pinfunction "10_10") (pintype "passive"))
      (node (ref "SV1") (pin "2") (pinfunction "2_2") (pintype "passive"))
      (node (ref "SV1") (pin "4") (pinfunction "4_4") (pintype "passive"))
      (node (ref "SV1") (pin "6") (pinfunction "6_6") (pintype "passive"))
      (node (ref "SV1") (pin "8") (pinfunction "8_8") (pintype "passive"))
    )
    (net (code "504") (name "Net-(SV2-Pad1)") (class "Default")
      (node (ref "SV2") (pin "1") (pinfunction "1_1") (pintype "passive"))
      (node (ref "SV2") (pin "3") (pinfunction "3_3") (pintype "passive"))
      (node (ref "SV2") (pin "5") (pinfunction "5_5") (pintype "passive"))
      (node (ref "SV2") (pin "7") (pinfunction "7_7") (pintype "passive"))
      (node (ref "SV2") (pin "9") (pinfunction "9_9") (pintype "passive"))
    )
    (net (code "505") (name "Net-(SV2-Pad10)") (class "Default")
      (node (ref "SV2") (pin "10") (pinfunction "10_10") (pintype "passive"))
      (node (ref "SV2") (pin "2") (pinfunction "2_2") (pintype "passive"))
      (node (ref "SV2") (pin "4") (pinfunction "4_4") (pintype "passive"))
      (node (ref "SV2") (pin "6") (pinfunction "6_6") (pintype "passive"))
      (node (ref "SV2") (pin "8") (pinfunction "8_8") (pintype "passive"))
    )
    (net (code "506") (name "Net-(SV7-Pad1)") (class "Default")
      (node (ref "SV7") (pin "1") (pinfunction "1_1") (pintype "passive"))
      (node (ref "SV7") (pin "3") (pinfunction "3_3") (pintype "passive"))
      (node (ref "SV7") (pin "5") (pinfunction "5_5") (pintype "passive"))
      (node (ref "SV7") (pin "7") (pinfunction "7_7") (pintype "passive"))
      (node (ref "SV7") (pin "9") (pinfunction "9_9") (pintype "passive"))
    )
    (net (code "507") (name "Net-(SV7-Pad10)") (class "Default")
      (node (ref "SV7") (pin "10") (pinfunction "10_10") (pintype "passive"))
      (node (ref "SV7") (pin "2") (pinfunction "2_2") (pintype "passive"))
      (node (ref "SV7") (pin "4") (pinfunction "4_4") (pintype "passive"))
      (node (ref "SV7") (pin "6") (pinfunction "6_6") (pintype "passive"))
      (node (ref "SV7") (pin "8") (pinfunction "8_8") (pintype "passive"))
    )
    (net (code "508") (name "Net-(SV8-Pad1)") (class "Default")
      (node (ref "SV8") (pin "1") (pinfunction "1_1") (pintype "passive"))
      (node (ref "SV8") (pin "3") (pinfunction "3_3") (pintype "passive"))
      (node (ref "SV8") (pin "5") (pinfunction "5_5") (pintype "passive"))
      (node (ref "SV8") (pin "7") (pinfunction "7_7") (pintype "passive"))
      (node (ref "SV8") (pin "9") (pinfunction "9_9") (pintype "passive"))
    )
    (net (code "509") (name "Net-(SV8-Pad10)") (class "Default")
      (node (ref "SV8") (pin "10") (pinfunction "10_10") (pintype "passive"))
      (node (ref "SV8") (pin "2") (pinfunction "2_2") (pintype "passive"))
      (node (ref "SV8") (pin "4") (pinfunction "4_4") (pintype "passive"))
      (node (ref "SV8") (pin "6") (pinfunction "6_6") (pintype "passive"))
      (node (ref "SV8") (pin "8") (pinfunction "8_8") (pintype "passive"))
    )
    (net (code "510") (name "Net-(SV13-Pad1)") (class "Default")
      (node (ref "SV13") (pin "1") (pinfunction "1_1") (pintype "passive"))
      (node (ref "SV13") (pin "3") (pinfunction "3_3") (pintype "passive"))
      (node (ref "SV13") (pin "5") (pinfunction "5_5") (pintype "passive"))
      (node (ref "SV13") (pin "7") (pinfunction "7_7") (pintype "passive"))
      (node (ref "SV13") (pin "9") (pinfunction "9_9") (pintype "passive"))
    )
    (net (code "511") (name "Net-(SV13-Pad10)") (class "Default")
      (node (ref "SV13") (pin "10") (pinfunction "10_10") (pintype "passive"))
      (node (ref "SV13") (pin "2") (pinfunction "2_2") (pintype "passive"))
      (node (ref "SV13") (pin "4") (pinfunction "4_4") (pintype "passive"))
      (node (ref "SV13") (pin "6") (pinfunction "6_6") (pintype "passive"))
      (node (ref "SV13") (pin "8") (pinfunction "8_8") (pintype "passive"))
    )
    (net (code "512") (name "Net-(SV14-Pad1)") (class "Default")
      (node (ref "SV14") (pin "1") (pinfunction "1_1") (pintype "passive"))
      (node (ref "SV14") (pin "3") (pinfunction "3_3") (pintype "passive"))
      (node (ref "SV14") (pin "5") (pinfunction "5_5") (pintype "passive"))
      (node (ref "SV14") (pin "7") (pinfunction "7_7") (pintype "passive"))
      (node (ref "SV14") (pin "9") (pinfunction "9_9") (pintype "passive"))
    )
    (net (code "513") (name "Net-(SV14-Pad10)") (class "Default")
      (node (ref "SV14") (pin "10") (pinfunction "10_10") (pintype "passive"))
      (node (ref "SV14") (pin "2") (pinfunction "2_2") (pintype "passive"))
      (node (ref "SV14") (pin "4") (pinfunction "4_4") (pintype "passive"))
      (node (ref "SV14") (pin "6") (pinfunction "6_6") (pintype "passive"))
      (node (ref "SV14") (pin "8") (pinfunction "8_8") (pintype "passive"))
    )
    (net (code "514") (name "Net-(SV15-Pad1)") (class "Default")
      (node (ref "SV15") (pin "1") (pinfunction "1_1") (pintype "passive"))
      (node (ref "SV15") (pin "3") (pinfunction "3_3") (pintype "passive"))
      (node (ref "SV15") (pin "5") (pinfunction "5_5") (pintype "passive"))
      (node (ref "SV15") (pin "7") (pinfunction "7_7") (pintype "passive"))
      (node (ref "SV15") (pin "9") (pinfunction "9_9") (pintype "passive"))
    )
    (net (code "515") (name "Net-(SV15-Pad10)") (class "Default")
      (node (ref "SV15") (pin "10") (pinfunction "10_10") (pintype "passive"))
      (node (ref "SV15") (pin "2") (pinfunction "2_2") (pintype "passive"))
      (node (ref "SV15") (pin "4") (pinfunction "4_4") (pintype "passive"))
      (node (ref "SV15") (pin "6") (pinfunction "6_6") (pintype "passive"))
      (node (ref "SV15") (pin "8") (pinfunction "8_8") (pintype "passive"))
    )
    (net (code "516") (name "Net-(SV16-Pad1)") (class "Default")
      (node (ref "SV16") (pin "1") (pinfunction "1_1") (pintype "passive"))
      (node (ref "SV16") (pin "3") (pinfunction "3_3") (pintype "passive"))
      (node (ref "SV16") (pin "5") (pinfunction "5_5") (pintype "passive"))
      (node (ref "SV16") (pin "7") (pinfunction "7_7") (pintype "passive"))
      (node (ref "SV16") (pin "9") (pinfunction "9_9") (pintype "passive"))
    )
    (net (code "517") (name "Net-(SV16-Pad10)") (class "Default")
      (node (ref "SV16") (pin "10") (pinfunction "10_10") (pintype "passive"))
      (node (ref "SV16") (pin "2") (pinfunction "2_2") (pintype "passive"))
      (node (ref "SV16") (pin "4") (pinfunction "4_4") (pintype "passive"))
      (node (ref "SV16") (pin "6") (pinfunction "6_6") (pintype "passive"))
      (node (ref "SV16") (pin "8") (pinfunction "8_8") (pintype "passive"))
    )
    (net (code "518") (name "Net-(SV17-Pad1)") (class "Default")
      (node (ref "SV17") (pin "1") (pinfunction "1_1") (pintype "passive"))
      (node (ref "SV17") (pin "3") (pinfunction "3_3") (pintype "passive"))
      (node (ref "SV17") (pin "5") (pinfunction "5_5") (pintype "passive"))
      (node (ref "SV17") (pin "7") (pinfunction "7_7") (pintype "passive"))
      (node (ref "SV17") (pin "9") (pinfunction "9_9") (pintype "passive"))
    )
    (net (code "519") (name "Net-(SV17-Pad10)") (class "Default")
      (node (ref "SV17") (pin "10") (pinfunction "10_10") (pintype "passive"))
      (node (ref "SV17") (pin "2") (pinfunction "2_2") (pintype "passive"))
      (node (ref "SV17") (pin "4") (pinfunction "4_4") (pintype "passive"))
      (node (ref "SV17") (pin "6") (pinfunction "6_6") (pintype "passive"))
      (node (ref "SV17") (pin "8") (pinfunction "8_8") (pintype "passive"))
    )
    (net (code "520") (name "Net-(SV18-Pad1)") (class "Default")
      (node (ref "SV18") (pin "1") (pinfunction "1_1") (pintype "passive"))
      (node (ref "SV18") (pin "3") (pinfunction "3_3") (pintype "passive"))
      (node (ref "SV18") (pin "5") (pinfunction "5_5") (pintype "passive"))
      (node (ref "SV18") (pin "7") (pinfunction "7_7") (pintype "passive"))
      (node (ref "SV18") (pin "9") (pinfunction "9_9") (pintype "passive"))
    )
    (net (code "521") (name "Net-(SV18-Pad10)") (class "Default")
      (node (ref "SV18") (pin "10") (pinfunction "10_10") (pintype "passive"))
      (node (ref "SV18") (pin "2") (pinfunction "2_2") (pintype "passive"))
      (node (ref "SV18") (pin "4") (pinfunction "4_4") (pintype "passive"))
      (node (ref "SV18") (pin "6") (pinfunction "6_6") (pintype "passive"))
      (node (ref "SV18") (pin "8") (pinfunction "8_8") (pintype "passive"))
    )
    (net (code "522") (name "Net-(SV19-Pad1)") (class "Default")
      (node (ref "SV19") (pin "1") (pinfunction "1_1") (pintype "passive"))
      (node (ref "SV19") (pin "3") (pinfunction "3_3") (pintype "passive"))
      (node (ref "SV19") (pin "5") (pinfunction "5_5") (pintype "passive"))
      (node (ref "SV19") (pin "7") (pinfunction "7_7") (pintype "passive"))
      (node (ref "SV19") (pin "9") (pinfunction "9_9") (pintype "passive"))
    )
    (net (code "523") (name "Net-(SV19-Pad10)") (class "Default")
      (node (ref "SV19") (pin "10") (pinfunction "10_10") (pintype "passive"))
      (node (ref "SV19") (pin "2") (pinfunction "2_2") (pintype "passive"))
      (node (ref "SV19") (pin "4") (pinfunction "4_4") (pintype "passive"))
      (node (ref "SV19") (pin "6") (pinfunction "6_6") (pintype "passive"))
      (node (ref "SV19") (pin "8") (pinfunction "8_8") (pintype "passive"))
    )
    (net (code "524") (name "Net-(SV20-Pad1)") (class "Default")
      (node (ref "SV20") (pin "1") (pinfunction "1_1") (pintype "passive"))
      (node (ref "SV20") (pin "3") (pinfunction "3_3") (pintype "passive"))
      (node (ref "SV20") (pin "5") (pinfunction "5_5") (pintype "passive"))
      (node (ref "SV20") (pin "7") (pinfunction "7_7") (pintype "passive"))
      (node (ref "SV20") (pin "9") (pinfunction "9_9") (pintype "passive"))
    )
    (net (code "525") (name "Net-(SV20-Pad10)") (class "Default")
      (node (ref "SV20") (pin "10") (pinfunction "10_10") (pintype "passive"))
      (node (ref "SV20") (pin "2") (pinfunction "2_2") (pintype "passive"))
      (node (ref "SV20") (pin "4") (pinfunction "4_4") (pintype "passive"))
      (node (ref "SV20") (pin "6") (pinfunction "6_6") (pintype "passive"))
      (node (ref "SV20") (pin "8") (pinfunction "8_8") (pintype "passive"))
    )
    (net (code "526") (name "Net-(SV21-Pad1)") (class "Default")
      (node (ref "SV21") (pin "1") (pinfunction "1_1") (pintype "passive"))
      (node (ref "SV21") (pin "3") (pinfunction "3_3") (pintype "passive"))
      (node (ref "SV21") (pin "5") (pinfunction "5_5") (pintype "passive"))
      (node (ref "SV21") (pin "7") (pinfunction "7_7") (pintype "passive"))
      (node (ref "SV21") (pin "9") (pinfunction "9_9") (pintype "passive"))
    )
    (net (code "527") (name "Net-(SV21-Pad10)") (class "Default")
      (node (ref "SV21") (pin "10") (pinfunction "10_10") (pintype "passive"))
      (node (ref "SV21") (pin "2") (pinfunction "2_2") (pintype "passive"))
      (node (ref "SV21") (pin "4") (pinfunction "4_4") (pintype "passive"))
      (node (ref "SV21") (pin "6") (pinfunction "6_6") (pintype "passive"))
      (node (ref "SV21") (pin "8") (pinfunction "8_8") (pintype "passive"))
    )
    (net (code "528") (name "Net-(SV22-Pad1)") (class "Default")
      (node (ref "SV22") (pin "1") (pinfunction "1_1") (pintype "passive"))
      (node (ref "SV22") (pin "3") (pinfunction "3_3") (pintype "passive"))
      (node (ref "SV22") (pin "5") (pinfunction "5_5") (pintype "passive"))
      (node (ref "SV22") (pin "7") (pinfunction "7_7") (pintype "passive"))
      (node (ref "SV22") (pin "9") (pinfunction "9_9") (pintype "passive"))
    )
    (net (code "529") (name "Net-(SV22-Pad10)") (class "Default")
      (node (ref "SV22") (pin "10") (pinfunction "10_10") (pintype "passive"))
      (node (ref "SV22") (pin "2") (pinfunction "2_2") (pintype "passive"))
      (node (ref "SV22") (pin "4") (pinfunction "4_4") (pintype "passive"))
      (node (ref "SV22") (pin "6") (pinfunction "6_6") (pintype "passive"))
      (node (ref "SV22") (pin "8") (pinfunction "8_8") (pintype "passive"))
    )
    (net (code "530") (name "Net-(SV23-Pad1)") (class "Default")
      (node (ref "SV23") (pin "1") (pinfunction "1_1") (pintype "passive"))
      (node (ref "SV23") (pin "3") (pinfunction "3_3") (pintype "passive"))
      (node (ref "SV23") (pin "5") (pinfunction "5_5") (pintype "passive"))
      (node (ref "SV23") (pin "7") (pinfunction "7_7") (pintype "passive"))
      (node (ref "SV23") (pin "9") (pinfunction "9_9") (pintype "passive"))
    )
    (net (code "531") (name "Net-(SV23-Pad10)") (class "Default")
      (node (ref "SV23") (pin "10") (pinfunction "10_10") (pintype "passive"))
      (node (ref "SV23") (pin "2") (pinfunction "2_2") (pintype "passive"))
      (node (ref "SV23") (pin "4") (pinfunction "4_4") (pintype "passive"))
      (node (ref "SV23") (pin "6") (pinfunction "6_6") (pintype "passive"))
      (node (ref "SV23") (pin "8") (pinfunction "8_8") (pintype "passive"))
    )
    (net (code "532") (name "Net-(SV24-Pad1)") (class "Default")
      (node (ref "SV24") (pin "1") (pinfunction "1_1") (pintype "passive"))
      (node (ref "SV24") (pin "3") (pinfunction "3_3") (pintype "passive"))
      (node (ref "SV24") (pin "5") (pinfunction "5_5") (pintype "passive"))
      (node (ref "SV24") (pin "7") (pinfunction "7_7") (pintype "passive"))
      (node (ref "SV24") (pin "9") (pinfunction "9_9") (pintype "passive"))
    )
    (net (code "533") (name "Net-(SV24-Pad10)") (class "Default")
      (node (ref "SV24") (pin "10") (pinfunction "10_10") (pintype "passive"))
      (node (ref "SV24") (pin "2") (pinfunction "2_2") (pintype "passive"))
      (node (ref "SV24") (pin "4") (pinfunction "4_4") (pintype "passive"))
      (node (ref "SV24") (pin "6") (pinfunction "6_6") (pintype "passive"))
      (node (ref "SV24") (pin "8") (pinfunction "8_8") (pintype "passive"))
    )
    (net (code "534") (name "Net-(SV25-Pad1)") (class "Default")
      (node (ref "SV25") (pin "1") (pinfunction "1_1") (pintype "passive"))
      (node (ref "SV25") (pin "3") (pinfunction "3_3") (pintype "passive"))
      (node (ref "SV25") (pin "5") (pinfunction "5_5") (pintype "passive"))
      (node (ref "SV25") (pin "7") (pinfunction "7_7") (pintype "passive"))
      (node (ref "SV25") (pin "9") (pinfunction "9_9") (pintype "passive"))
    )
    (net (code "535") (name "Net-(SV25-Pad10)") (class "Default")
      (node (ref "SV25") (pin "10") (pinfunction "10_10") (pintype "passive"))
      (node (ref "SV25") (pin "2") (pinfunction "2_2") (pintype "passive"))
      (node (ref "SV25") (pin "4") (pinfunction "4_4") (pintype "passive"))
      (node (ref "SV25") (pin "6") (pinfunction "6_6") (pintype "passive"))
      (node (ref "SV25") (pin "8") (pinfunction "8_8") (pintype "passive"))
    )
    (net (code "536") (name "Net-(SV26-Pad1)") (class "Default")
      (node (ref "SV26") (pin "1") (pinfunction "1_1") (pintype "passive"))
      (node (ref "SV26") (pin "3") (pinfunction "3_3") (pintype "passive"))
      (node (ref "SV26") (pin "5") (pinfunction "5_5") (pintype "passive"))
      (node (ref "SV26") (pin "7") (pinfunction "7_7") (pintype "passive"))
      (node (ref "SV26") (pin "9") (pinfunction "9_9") (pintype "passive"))
    )
    (net (code "537") (name "Net-(SV26-Pad10)") (class "Default")
      (node (ref "SV26") (pin "10") (pinfunction "10_10") (pintype "passive"))
      (node (ref "SV26") (pin "2") (pinfunction "2_2") (pintype "passive"))
      (node (ref "SV26") (pin "4") (pinfunction "4_4") (pintype "passive"))
      (node (ref "SV26") (pin "6") (pinfunction "6_6") (pintype "passive"))
      (node (ref "SV26") (pin "8") (pinfunction "8_8") (pintype "passive"))
    )
    (net (code "538") (name "Net-(SV27-Pad1)") (class "Default")
      (node (ref "SV27") (pin "1") (pinfunction "1_1") (pintype "passive"))
      (node (ref "SV27") (pin "3") (pinfunction "3_3") (pintype "passive"))
      (node (ref "SV27") (pin "5") (pinfunction "5_5") (pintype "passive"))
      (node (ref "SV27") (pin "7") (pinfunction "7_7") (pintype "passive"))
      (node (ref "SV27") (pin "9") (pinfunction "9_9") (pintype "passive"))
    )
    (net (code "539") (name "Net-(SV27-Pad10)") (class "Default")
      (node (ref "SV27") (pin "10") (pinfunction "10_10") (pintype "passive"))
      (node (ref "SV27") (pin "2") (pinfunction "2_2") (pintype "passive"))
      (node (ref "SV27") (pin "4") (pinfunction "4_4") (pintype "passive"))
      (node (ref "SV27") (pin "6") (pinfunction "6_6") (pintype "passive"))
      (node (ref "SV27") (pin "8") (pinfunction "8_8") (pintype "passive"))
    )
    (net (code "540") (name "Net-(SV28-Pad1)") (class "Default")
      (node (ref "SV28") (pin "1") (pinfunction "1_1") (pintype "passive"))
      (node (ref "SV28") (pin "3") (pinfunction "3_3") (pintype "passive"))
      (node (ref "SV28") (pin "5") (pinfunction "5_5") (pintype "passive"))
      (node (ref "SV28") (pin "7") (pinfunction "7_7") (pintype "passive"))
      (node (ref "SV28") (pin "9") (pinfunction "9_9") (pintype "passive"))
    )
    (net (code "541") (name "Net-(SV28-Pad10)") (class "Default")
      (node (ref "SV28") (pin "10") (pinfunction "10_10") (pintype "passive"))
      (node (ref "SV28") (pin "2") (pinfunction "2_2") (pintype "passive"))
      (node (ref "SV28") (pin "4") (pinfunction "4_4") (pintype "passive"))
      (node (ref "SV28") (pin "6") (pinfunction "6_6") (pintype "passive"))
      (node (ref "SV28") (pin "8") (pinfunction "8_8") (pintype "passive"))
    )
    (net (code "542") (name "Net-(SV29-Pad1)") (class "Default")
      (node (ref "SV29") (pin "1") (pinfunction "1_1") (pintype "passive"))
      (node (ref "SV29") (pin "3") (pinfunction "3_3") (pintype "passive"))
      (node (ref "SV29") (pin "5") (pinfunction "5_5") (pintype "passive"))
      (node (ref "SV29") (pin "7") (pinfunction "7_7") (pintype "passive"))
      (node (ref "SV29") (pin "9") (pinfunction "9_9") (pintype "passive"))
    )
    (net (code "543") (name "Net-(SV29-Pad10)") (class "Default")
      (node (ref "SV29") (pin "10") (pinfunction "10_10") (pintype "passive"))
      (node (ref "SV29") (pin "2") (pinfunction "2_2") (pintype "passive"))
      (node (ref "SV29") (pin "4") (pinfunction "4_4") (pintype "passive"))
      (node (ref "SV29") (pin "6") (pinfunction "6_6") (pintype "passive"))
      (node (ref "SV29") (pin "8") (pinfunction "8_8") (pintype "passive"))
    )
    (net (code "544") (name "Net-(SV30-Pad1)") (class "Default")
      (node (ref "SV30") (pin "1") (pinfunction "1_1") (pintype "passive"))
      (node (ref "SV30") (pin "3") (pinfunction "3_3") (pintype "passive"))
      (node (ref "SV30") (pin "5") (pinfunction "5_5") (pintype "passive"))
      (node (ref "SV30") (pin "7") (pinfunction "7_7") (pintype "passive"))
      (node (ref "SV30") (pin "9") (pinfunction "9_9") (pintype "passive"))
    )
    (net (code "545") (name "Net-(SV30-Pad10)") (class "Default")
      (node (ref "SV30") (pin "10") (pinfunction "10_10") (pintype "passive"))
      (node (ref "SV30") (pin "2") (pinfunction "2_2") (pintype "passive"))
      (node (ref "SV30") (pin "4") (pinfunction "4_4") (pintype "passive"))
      (node (ref "SV30") (pin "6") (pinfunction "6_6") (pintype "passive"))
      (node (ref "SV30") (pin "8") (pinfunction "8_8") (pintype "passive"))
    )
    (net (code "546") (name "Net-(SV31-Pad1)") (class "Default")
      (node (ref "SV31") (pin "1") (pinfunction "1_1") (pintype "passive"))
      (node (ref "SV31") (pin "3") (pinfunction "3_3") (pintype "passive"))
      (node (ref "SV31") (pin "5") (pinfunction "5_5") (pintype "passive"))
      (node (ref "SV31") (pin "7") (pinfunction "7_7") (pintype "passive"))
      (node (ref "SV31") (pin "9") (pinfunction "9_9") (pintype "passive"))
    )
    (net (code "547") (name "Net-(SV31-Pad10)") (class "Default")
      (node (ref "SV31") (pin "10") (pinfunction "10_10") (pintype "passive"))
      (node (ref "SV31") (pin "2") (pinfunction "2_2") (pintype "passive"))
      (node (ref "SV31") (pin "4") (pinfunction "4_4") (pintype "passive"))
      (node (ref "SV31") (pin "6") (pinfunction "6_6") (pintype "passive"))
      (node (ref "SV31") (pin "8") (pinfunction "8_8") (pintype "passive"))
    )
    (net (code "548") (name "Net-(SV32-Pad1)") (class "Default")
      (node (ref "SV32") (pin "1") (pinfunction "1_1") (pintype "passive"))
      (node (ref "SV32") (pin "3") (pinfunction "3_3") (pintype "passive"))
      (node (ref "SV32") (pin "5") (pinfunction "5_5") (pintype "passive"))
      (node (ref "SV32") (pin "7") (pinfunction "7_7") (pintype "passive"))
      (node (ref "SV32") (pin "9") (pinfunction "9_9") (pintype "passive"))
    )
    (net (code "549") (name "Net-(SV32-Pad10)") (class "Default")
      (node (ref "SV32") (pin "10") (pinfunction "10_10") (pintype "passive"))
      (node (ref "SV32") (pin "2") (pinfunction "2_2") (pintype "passive"))
      (node (ref "SV32") (pin "4") (pinfunction "4_4") (pintype "passive"))
      (node (ref "SV32") (pin "6") (pinfunction "6_6") (pintype "passive"))
      (node (ref "SV32") (pin "8") (pinfunction "8_8") (pintype "passive"))
    )
    (net (code "550") (name "Net-(SV33-Pad1)") (class "Default")
      (node (ref "SV33") (pin "1") (pinfunction "1_1") (pintype "passive"))
      (node (ref "SV33") (pin "3") (pinfunction "3_3") (pintype "passive"))
      (node (ref "SV33") (pin "5") (pinfunction "5_5") (pintype "passive"))
      (node (ref "SV33") (pin "7") (pinfunction "7_7") (pintype "passive"))
      (node (ref "SV33") (pin "9") (pinfunction "9_9") (pintype "passive"))
    )
    (net (code "551") (name "Net-(SV33-Pad10)") (class "Default")
      (node (ref "SV33") (pin "10") (pinfunction "10_10") (pintype "passive"))
      (node (ref "SV33") (pin "2") (pinfunction "2_2") (pintype "passive"))
      (node (ref "SV33") (pin "4") (pinfunction "4_4") (pintype "passive"))
      (node (ref "SV33") (pin "6") (pinfunction "6_6") (pintype "passive"))
      (node (ref "SV33") (pin "8") (pinfunction "8_8") (pintype "passive"))
    )
    (net (code "552") (name "Net-(SV34-Pad1)") (class "Default")
      (node (ref "SV34") (pin "1") (pinfunction "1_1") (pintype "passive"))
      (node (ref "SV34") (pin "3") (pinfunction "3_3") (pintype "passive"))
      (node (ref "SV34") (pin "5") (pinfunction "5_5") (pintype "passive"))
      (node (ref "SV34") (pin "7") (pinfunction "7_7") (pintype "passive"))
      (node (ref "SV34") (pin "9") (pinfunction "9_9") (pintype "passive"))
    )
    (net (code "553") (name "Net-(SV34-Pad10)") (class "Default")
      (node (ref "SV34") (pin "10") (pinfunction "10_10") (pintype "passive"))
      (node (ref "SV34") (pin "2") (pinfunction "2_2") (pintype "passive"))
      (node (ref "SV34") (pin "4") (pinfunction "4_4") (pintype "passive"))
      (node (ref "SV34") (pin "6") (pinfunction "6_6") (pintype "passive"))
      (node (ref "SV34") (pin "8") (pinfunction "8_8") (pintype "passive"))
    )
    (net (code "554") (name "Net-(SV35-Pad1)") (class "Default")
      (node (ref "SV35") (pin "1") (pinfunction "1_1") (pintype "passive"))
      (node (ref "SV35") (pin "3") (pinfunction "3_3") (pintype "passive"))
      (node (ref "SV35") (pin "5") (pinfunction "5_5") (pintype "passive"))
      (node (ref "SV35") (pin "7") (pinfunction "7_7") (pintype "passive"))
      (node (ref "SV35") (pin "9") (pinfunction "9_9") (pintype "passive"))
    )
    (net (code "555") (name "Net-(SV35-Pad10)") (class "Default")
      (node (ref "SV35") (pin "10") (pinfunction "10_10") (pintype "passive"))
      (node (ref "SV35") (pin "2") (pinfunction "2_2") (pintype "passive"))
      (node (ref "SV35") (pin "4") (pinfunction "4_4") (pintype "passive"))
      (node (ref "SV35") (pin "6") (pinfunction "6_6") (pintype "passive"))
      (node (ref "SV35") (pin "8") (pinfunction "8_8") (pintype "passive"))
    )
    (net (code "556") (name "Net-(SV36-Pad1)") (class "Default")
      (node (ref "SV36") (pin "1") (pinfunction "1_1") (pintype "passive"))
      (node (ref "SV36") (pin "3") (pinfunction "3_3") (pintype "passive"))
      (node (ref "SV36") (pin "5") (pinfunction "5_5") (pintype "passive"))
      (node (ref "SV36") (pin "7") (pinfunction "7_7") (pintype "passive"))
      (node (ref "SV36") (pin "9") (pinfunction "9_9") (pintype "passive"))
    )
    (net (code "557") (name "Net-(SV36-Pad10)") (class "Default")
      (node (ref "SV36") (pin "10") (pinfunction "10_10") (pintype "passive"))
      (node (ref "SV36") (pin "2") (pinfunction "2_2") (pintype "passive"))
      (node (ref "SV36") (pin "4") (pinfunction "4_4") (pintype "passive"))
      (node (ref "SV36") (pin "6") (pinfunction "6_6") (pintype "passive"))
      (node (ref "SV36") (pin "8") (pinfunction "8_8") (pintype "passive"))
    )
    (net (code "558") (name "Net-(SV37-Pad1)") (class "Default")
      (node (ref "SV37") (pin "1") (pinfunction "1_1") (pintype "passive"))
      (node (ref "SV37") (pin "3") (pinfunction "3_3") (pintype "passive"))
      (node (ref "SV37") (pin "5") (pinfunction "5_5") (pintype "passive"))
      (node (ref "SV37") (pin "7") (pinfunction "7_7") (pintype "passive"))
      (node (ref "SV37") (pin "9") (pinfunction "9_9") (pintype "passive"))
    )
    (net (code "559") (name "Net-(SV37-Pad10)") (class "Default")
      (node (ref "SV37") (pin "10") (pinfunction "10_10") (pintype "passive"))
      (node (ref "SV37") (pin "2") (pinfunction "2_2") (pintype "passive"))
      (node (ref "SV37") (pin "4") (pinfunction "4_4") (pintype "passive"))
      (node (ref "SV37") (pin "6") (pinfunction "6_6") (pintype "passive"))
      (node (ref "SV37") (pin "8") (pinfunction "8_8") (pintype "passive"))
    )
    (net (code "560") (name "Net-(SV38-Pad1)") (class "Default")
      (node (ref "SV38") (pin "1") (pinfunction "1_1") (pintype "passive"))
      (node (ref "SV38") (pin "3") (pinfunction "3_3") (pintype "passive"))
      (node (ref "SV38") (pin "5") (pinfunction "5_5") (pintype "passive"))
      (node (ref "SV38") (pin "7") (pinfunction "7_7") (pintype "passive"))
      (node (ref "SV38") (pin "9") (pinfunction "9_9") (pintype "passive"))
    )
    (net (code "561") (name "Net-(SV38-Pad10)") (class "Default")
      (node (ref "SV38") (pin "10") (pinfunction "10_10") (pintype "passive"))
      (node (ref "SV38") (pin "2") (pinfunction "2_2") (pintype "passive"))
      (node (ref "SV38") (pin "4") (pinfunction "4_4") (pintype "passive"))
      (node (ref "SV38") (pin "6") (pinfunction "6_6") (pintype "passive"))
      (node (ref "SV38") (pin "8") (pinfunction "8_8") (pintype "passive"))
    )
    (net (code "562") (name "Net-(SV39-Pad1)") (class "Default")
      (node (ref "SV39") (pin "1") (pinfunction "1_1") (pintype "passive"))
      (node (ref "SV39") (pin "3") (pinfunction "3_3") (pintype "passive"))
      (node (ref "SV39") (pin "5") (pinfunction "5_5") (pintype "passive"))
      (node (ref "SV39") (pin "7") (pinfunction "7_7") (pintype "passive"))
      (node (ref "SV39") (pin "9") (pinfunction "9_9") (pintype "passive"))
    )
    (net (code "563") (name "Net-(SV39-Pad10)") (class "Default")
      (node (ref "SV39") (pin "10") (pinfunction "10_10") (pintype "passive"))
      (node (ref "SV39") (pin "2") (pinfunction "2_2") (pintype "passive"))
      (node (ref "SV39") (pin "4") (pinfunction "4_4") (pintype "passive"))
      (node (ref "SV39") (pin "6") (pinfunction "6_6") (pintype "passive"))
      (node (ref "SV39") (pin "8") (pinfunction "8_8") (pintype "passive"))
    )
    (net (code "564") (name "Net-(SV40-Pad1)") (class "Default")
      (node (ref "SV40") (pin "1") (pinfunction "1_1") (pintype "passive"))
      (node (ref "SV40") (pin "3") (pinfunction "3_3") (pintype "passive"))
      (node (ref "SV40") (pin "5") (pinfunction "5_5") (pintype "passive"))
      (node (ref "SV40") (pin "7") (pinfunction "7_7") (pintype "passive"))
      (node (ref "SV40") (pin "9") (pinfunction "9_9") (pintype "passive"))
    )
    (net (code "565") (name "Net-(SV40-Pad10)") (class "Default")
      (node (ref "SV40") (pin "10") (pinfunction "10_10") (pintype "passive"))
      (node (ref "SV40") (pin "2") (pinfunction "2_2") (pintype "passive"))
      (node (ref "SV40") (pin "4") (pinfunction "4_4") (pintype "passive"))
      (node (ref "SV40") (pin "6") (pinfunction "6_6") (pintype "passive"))
      (node (ref "SV40") (pin "8") (pinfunction "8_8") (pintype "passive"))
    )
    (net (code "566") (name "Net-(SV41-Pad1)") (class "Default")
      (node (ref "SV41") (pin "1") (pinfunction "1_1") (pintype "passive"))
      (node (ref "SV41") (pin "3") (pinfunction "3_3") (pintype "passive"))
      (node (ref "SV41") (pin "5") (pinfunction "5_5") (pintype "passive"))
      (node (ref "SV41") (pin "7") (pinfunction "7_7") (pintype "passive"))
      (node (ref "SV41") (pin "9") (pinfunction "9_9") (pintype "passive"))
    )
    (net (code "567") (name "Net-(SV41-Pad10)") (class "Default")
      (node (ref "SV41") (pin "10") (pinfunction "10_10") (pintype "passive"))
      (node (ref "SV41") (pin "2") (pinfunction "2_2") (pintype "passive"))
      (node (ref "SV41") (pin "4") (pinfunction "4_4") (pintype "passive"))
      (node (ref "SV41") (pin "6") (pinfunction "6_6") (pintype "passive"))
      (node (ref "SV41") (pin "8") (pinfunction "8_8") (pintype "passive"))
    )
    (net (code "568") (name "Net-(SV42-Pad1)") (class "Default")
      (node (ref "SV42") (pin "1") (pinfunction "1_1") (pintype "passive"))
      (node (ref "SV42") (pin "3") (pinfunction "3_3") (pintype "passive"))
      (node (ref "SV42") (pin "5") (pinfunction "5_5") (pintype "passive"))
      (node (ref "SV42") (pin "7") (pinfunction "7_7") (pintype "passive"))
      (node (ref "SV42") (pin "9") (pinfunction "9_9") (pintype "passive"))
    )
    (net (code "569") (name "Net-(SV42-Pad10)") (class "Default")
      (node (ref "SV42") (pin "10") (pinfunction "10_10") (pintype "passive"))
      (node (ref "SV42") (pin "2") (pinfunction "2_2") (pintype "passive"))
      (node (ref "SV42") (pin "4") (pinfunction "4_4") (pintype "passive"))
      (node (ref "SV42") (pin "6") (pinfunction "6_6") (pintype "passive"))
      (node (ref "SV42") (pin "8") (pinfunction "8_8") (pintype "passive"))
    )
    (net (code "570") (name "Net-(SV43-Pad1)") (class "Default")
      (node (ref "SV43") (pin "1") (pinfunction "1_1") (pintype "passive"))
      (node (ref "SV43") (pin "3") (pinfunction "3_3") (pintype "passive"))
      (node (ref "SV43") (pin "5") (pinfunction "5_5") (pintype "passive"))
      (node (ref "SV43") (pin "7") (pinfunction "7_7") (pintype "passive"))
      (node (ref "SV43") (pin "9") (pinfunction "9_9") (pintype "passive"))
    )
    (net (code "571") (name "Net-(SV43-Pad10)") (class "Default")
      (node (ref "SV43") (pin "10") (pinfunction "10_10") (pintype "passive"))
      (node (ref "SV43") (pin "2") (pinfunction "2_2") (pintype "passive"))
      (node (ref "SV43") (pin "4") (pinfunction "4_4") (pintype "passive"))
      (node (ref "SV43") (pin "6") (pinfunction "6_6") (pintype "passive"))
      (node (ref "SV43") (pin "8") (pinfunction "8_8") (pintype "passive"))
    )
    (net (code "572") (name "Net-(SV44-Pad1)") (class "Default")
      (node (ref "SV44") (pin "1") (pinfunction "1_1") (pintype "passive"))
      (node (ref "SV44") (pin "3") (pinfunction "3_3") (pintype "passive"))
      (node (ref "SV44") (pin "5") (pinfunction "5_5") (pintype "passive"))
      (node (ref "SV44") (pin "7") (pinfunction "7_7") (pintype "passive"))
      (node (ref "SV44") (pin "9") (pinfunction "9_9") (pintype "passive"))
    )
    (net (code "573") (name "Net-(SV44-Pad10)") (class "Default")
      (node (ref "SV44") (pin "10") (pinfunction "10_10") (pintype "passive"))
      (node (ref "SV44") (pin "2") (pinfunction "2_2") (pintype "passive"))
      (node (ref "SV44") (pin "4") (pinfunction "4_4") (pintype "passive"))
      (node (ref "SV44") (pin "6") (pinfunction "6_6") (pintype "passive"))
      (node (ref "SV44") (pin "8") (pinfunction "8_8") (pintype "passive"))
    )
    (net (code "574") (name "Net-(SV45-Pad1)") (class "Default")
      (node (ref "SV45") (pin "1") (pinfunction "1_1") (pintype "passive"))
      (node (ref "SV45") (pin "3") (pinfunction "3_3") (pintype "passive"))
      (node (ref "SV45") (pin "5") (pinfunction "5_5") (pintype "passive"))
      (node (ref "SV45") (pin "7") (pinfunction "7_7") (pintype "passive"))
      (node (ref "SV45") (pin "9") (pinfunction "9_9") (pintype "passive"))
    )
    (net (code "575") (name "Net-(SV45-Pad10)") (class "Default")
      (node (ref "SV45") (pin "10") (pinfunction "10_10") (pintype "passive"))
      (node (ref "SV45") (pin "2") (pinfunction "2_2") (pintype "passive"))
      (node (ref "SV45") (pin "4") (pinfunction "4_4") (pintype "passive"))
      (node (ref "SV45") (pin "6") (pinfunction "6_6") (pintype "passive"))
      (node (ref "SV45") (pin "8") (pinfunction "8_8") (pintype "passive"))
    )
    (net (code "576") (name "Net-(SV46-Pad1)") (class "Default")
      (node (ref "SV46") (pin "1") (pinfunction "1_1") (pintype "passive"))
      (node (ref "SV46") (pin "3") (pinfunction "3_3") (pintype "passive"))
      (node (ref "SV46") (pin "5") (pinfunction "5_5") (pintype "passive"))
      (node (ref "SV46") (pin "7") (pinfunction "7_7") (pintype "passive"))
      (node (ref "SV46") (pin "9") (pinfunction "9_9") (pintype "passive"))
    )
    (net (code "577") (name "Net-(SV46-Pad10)") (class "Default")
      (node (ref "SV46") (pin "10") (pinfunction "10_10") (pintype "passive"))
      (node (ref "SV46") (pin "2") (pinfunction "2_2") (pintype "passive"))
      (node (ref "SV46") (pin "4") (pinfunction "4_4") (pintype "passive"))
      (node (ref "SV46") (pin "6") (pinfunction "6_6") (pintype "passive"))
      (node (ref "SV46") (pin "8") (pinfunction "8_8") (pintype "passive"))
    )
    (net (code "578") (name "Net-(SV47-Pad1)") (class "Default")
      (node (ref "SV47") (pin "1") (pinfunction "1_1") (pintype "passive"))
      (node (ref "SV47") (pin "3") (pinfunction "3_3") (pintype "passive"))
      (node (ref "SV47") (pin "5") (pinfunction "5_5") (pintype "passive"))
      (node (ref "SV47") (pin "7") (pinfunction "7_7") (pintype "passive"))
      (node (ref "SV47") (pin "9") (pinfunction "9_9") (pintype "passive"))
    )
    (net (code "579") (name "Net-(SV47-Pad10)") (class "Default")
      (node (ref "SV47") (pin "10") (pinfunction "10_10") (pintype "passive"))
      (node (ref "SV47") (pin "2") (pinfunction "2_2") (pintype "passive"))
      (node (ref "SV47") (pin "4") (pinfunction "4_4") (pintype "passive"))
      (node (ref "SV47") (pin "6") (pinfunction "6_6") (pintype "passive"))
      (node (ref "SV47") (pin "8") (pinfunction "8_8") (pintype "passive"))
    )
    (net (code "580") (name "Net-(SV48-Pad1)") (class "Default")
      (node (ref "SV48") (pin "1") (pinfunction "1_1") (pintype "passive"))
      (node (ref "SV48") (pin "3") (pinfunction "3_3") (pintype "passive"))
      (node (ref "SV48") (pin "5") (pinfunction "5_5") (pintype "passive"))
      (node (ref "SV48") (pin "7") (pinfunction "7_7") (pintype "passive"))
      (node (ref "SV48") (pin "9") (pinfunction "9_9") (pintype "passive"))
    )
    (net (code "581") (name "Net-(SV48-Pad10)") (class "Default")
      (node (ref "SV48") (pin "10") (pinfunction "10_10") (pintype "passive"))
      (node (ref "SV48") (pin "2") (pinfunction "2_2") (pintype "passive"))
      (node (ref "SV48") (pin "4") (pinfunction "4_4") (pintype "passive"))
      (node (ref "SV48") (pin "6") (pinfunction "6_6") (pintype "passive"))
      (node (ref "SV48") (pin "8") (pinfunction "8_8") (pintype "passive"))
    )
    (net (code "582") (name "Net-(SV49-Pad1)") (class "Default")
      (node (ref "SV49") (pin "1") (pinfunction "1_1") (pintype "passive"))
      (node (ref "SV49") (pin "3") (pinfunction "3_3") (pintype "passive"))
      (node (ref "SV49") (pin "5") (pinfunction "5_5") (pintype "passive"))
      (node (ref "SV49") (pin "7") (pinfunction "7_7") (pintype "passive"))
      (node (ref "SV49") (pin "9") (pinfunction "9_9") (pintype "passive"))
    )
    (net (code "583") (name "Net-(SV49-Pad10)") (class "Default")
      (node (ref "SV49") (pin "10") (pinfunction "10_10") (pintype "passive"))
      (node (ref "SV49") (pin "2") (pinfunction "2_2") (pintype "passive"))
      (node (ref "SV49") (pin "4") (pinfunction "4_4") (pintype "passive"))
      (node (ref "SV49") (pin "6") (pinfunction "6_6") (pintype "passive"))
      (node (ref "SV49") (pin "8") (pinfunction "8_8") (pintype "passive"))
    )
    (net (code "584") (name "Net-(SV50-Pad1)") (class "Default")
      (node (ref "SV50") (pin "1") (pinfunction "1_1") (pintype "passive"))
      (node (ref "SV50") (pin "3") (pinfunction "3_3") (pintype "passive"))
      (node (ref "SV50") (pin "5") (pinfunction "5_5") (pintype "passive"))
      (node (ref "SV50") (pin "7") (pinfunction "7_7") (pintype "passive"))
      (node (ref "SV50") (pin "9") (pinfunction "9_9") (pintype "passive"))
    )
    (net (code "585") (name "Net-(SV50-Pad10)") (class "Default")
      (node (ref "SV50") (pin "10") (pinfunction "10_10") (pintype "passive"))
      (node (ref "SV50") (pin "2") (pinfunction "2_2") (pintype "passive"))
      (node (ref "SV50") (pin "4") (pinfunction "4_4") (pintype "passive"))
      (node (ref "SV50") (pin "6") (pinfunction "6_6") (pintype "passive"))
      (node (ref "SV50") (pin "8") (pinfunction "8_8") (pintype "passive"))
    )
    (net (code "586") (name "Net-(SV51-Pad1)") (class "Default")
      (node (ref "SV51") (pin "1") (pinfunction "1_1") (pintype "passive"))
      (node (ref "SV51") (pin "3") (pinfunction "3_3") (pintype "passive"))
      (node (ref "SV51") (pin "5") (pinfunction "5_5") (pintype "passive"))
      (node (ref "SV51") (pin "7") (pinfunction "7_7") (pintype "passive"))
      (node (ref "SV51") (pin "9") (pinfunction "9_9") (pintype "passive"))
    )
    (net (code "587") (name "Net-(SV51-Pad10)") (class "Default")
      (node (ref "SV51") (pin "10") (pinfunction "10_10") (pintype "passive"))
      (node (ref "SV51") (pin "2") (pinfunction "2_2") (pintype "passive"))
      (node (ref "SV51") (pin "4") (pinfunction "4_4") (pintype "passive"))
      (node (ref "SV51") (pin "6") (pinfunction "6_6") (pintype "passive"))
      (node (ref "SV51") (pin "8") (pinfunction "8_8") (pintype "passive"))
    )
    (net (code "588") (name "Net-(SV52-Pad1)") (class "Default")
      (node (ref "SV52") (pin "1") (pinfunction "1_1") (pintype "passive"))
      (node (ref "SV52") (pin "3") (pinfunction "3_3") (pintype "passive"))
      (node (ref "SV52") (pin "5") (pinfunction "5_5") (pintype "passive"))
      (node (ref "SV52") (pin "7") (pinfunction "7_7") (pintype "passive"))
      (node (ref "SV52") (pin "9") (pinfunction "9_9") (pintype "passive"))
    )
    (net (code "589") (name "Net-(SV52-Pad10)") (class "Default")
      (node (ref "SV52") (pin "10") (pinfunction "10_10") (pintype "passive"))
      (node (ref "SV52") (pin "2") (pinfunction "2_2") (pintype "passive"))
      (node (ref "SV52") (pin "4") (pinfunction "4_4") (pintype "passive"))
      (node (ref "SV52") (pin "6") (pinfunction "6_6") (pintype "passive"))
      (node (ref "SV52") (pin "8") (pinfunction "8_8") (pintype "passive"))
    )
    (net (code "590") (name "Net-(SV53-Pad1)") (class "Default")
      (node (ref "SV53") (pin "1") (pinfunction "1_1") (pintype "passive"))
      (node (ref "SV53") (pin "3") (pinfunction "3_3") (pintype "passive"))
      (node (ref "SV53") (pin "5") (pinfunction "5_5") (pintype "passive"))
      (node (ref "SV53") (pin "7") (pinfunction "7_7") (pintype "passive"))
      (node (ref "SV53") (pin "9") (pinfunction "9_9") (pintype "passive"))
    )
    (net (code "591") (name "Net-(SV53-Pad10)") (class "Default")
      (node (ref "SV53") (pin "10") (pinfunction "10_10") (pintype "passive"))
      (node (ref "SV53") (pin "2") (pinfunction "2_2") (pintype "passive"))
      (node (ref "SV53") (pin "4") (pinfunction "4_4") (pintype "passive"))
      (node (ref "SV53") (pin "6") (pinfunction "6_6") (pintype "passive"))
      (node (ref "SV53") (pin "8") (pinfunction "8_8") (pintype "passive"))
    )
    (net (code "592") (name "Net-(SV54-Pad1)") (class "Default")
      (node (ref "SV54") (pin "1") (pinfunction "1_1") (pintype "passive"))
      (node (ref "SV54") (pin "3") (pinfunction "3_3") (pintype "passive"))
      (node (ref "SV54") (pin "5") (pinfunction "5_5") (pintype "passive"))
      (node (ref "SV54") (pin "7") (pinfunction "7_7") (pintype "passive"))
      (node (ref "SV54") (pin "9") (pinfunction "9_9") (pintype "passive"))
    )
    (net (code "593") (name "Net-(SV54-Pad10)") (class "Default")
      (node (ref "SV54") (pin "10") (pinfunction "10_10") (pintype "passive"))
      (node (ref "SV54") (pin "2") (pinfunction "2_2") (pintype "passive"))
      (node (ref "SV54") (pin "4") (pinfunction "4_4") (pintype "passive"))
      (node (ref "SV54") (pin "6") (pinfunction "6_6") (pintype "passive"))
      (node (ref "SV54") (pin "8") (pinfunction "8_8") (pintype "passive"))
    )
    (net (code "594") (name "Net-(SV55-Pad1)") (class "Default")
      (node (ref "SV55") (pin "1") (pinfunction "1_1") (pintype "passive"))
      (node (ref "SV55") (pin "3") (pinfunction "3_3") (pintype "passive"))
      (node (ref "SV55") (pin "5") (pinfunction "5_5") (pintype "passive"))
      (node (ref "SV55") (pin "7") (pinfunction "7_7") (pintype "passive"))
      (node (ref "SV55") (pin "9") (pinfunction "9_9") (pintype "passive"))
    )
    (net (code "595") (name "Net-(SV55-Pad10)") (class "Default")
      (node (ref "SV55") (pin "10") (pinfunction "10_10") (pintype "passive"))
      (node (ref "SV55") (pin "2") (pinfunction "2_2") (pintype "passive"))
      (node (ref "SV55") (pin "4") (pinfunction "4_4") (pintype "passive"))
      (node (ref "SV55") (pin "6") (pinfunction "6_6") (pintype "passive"))
      (node (ref "SV55") (pin "8") (pinfunction "8_8") (pintype "passive"))
    )
    (net (code "596") (name "Net-(SV56-Pad1)") (class "Default")
      (node (ref "SV56") (pin "1") (pinfunction "1_1") (pintype "passive"))
      (node (ref "SV56") (pin "3") (pinfunction "3_3") (pintype "passive"))
      (node (ref "SV56") (pin "5") (pinfunction "5_5") (pintype "passive"))
      (node (ref "SV56") (pin "7") (pinfunction "7_7") (pintype "passive"))
      (node (ref "SV56") (pin "9") (pinfunction "9_9") (pintype "passive"))
    )
    (net (code "597") (name "Net-(SV56-Pad10)") (class "Default")
      (node (ref "SV56") (pin "10") (pinfunction "10_10") (pintype "passive"))
      (node (ref "SV56") (pin "2") (pinfunction "2_2") (pintype "passive"))
      (node (ref "SV56") (pin "4") (pinfunction "4_4") (pintype "passive"))
      (node (ref "SV56") (pin "6") (pinfunction "6_6") (pintype "passive"))
      (node (ref "SV56") (pin "8") (pinfunction "8_8") (pintype "passive"))
    )
    (net (code "598") (name "Net-(SV57-Pad1)") (class "Default")
      (node (ref "SV57") (pin "1") (pinfunction "1_1") (pintype "passive"))
      (node (ref "SV57") (pin "3") (pinfunction "3_3") (pintype "passive"))
      (node (ref "SV57") (pin "5") (pinfunction "5_5") (pintype "passive"))
      (node (ref "SV57") (pin "7") (pinfunction "7_7") (pintype "passive"))
      (node (ref "SV57") (pin "9") (pinfunction "9_9") (pintype "passive"))
    )
    (net (code "599") (name "Net-(SV57-Pad10)") (class "Default")
      (node (ref "SV57") (pin "10") (pinfunction "10_10") (pintype "passive"))
      (node (ref "SV57") (pin "2") (pinfunction "2_2") (pintype "passive"))
      (node (ref "SV57") (pin "4") (pinfunction "4_4") (pintype "passive"))
      (node (ref "SV57") (pin "6") (pinfunction "6_6") (pintype "passive"))
      (node (ref "SV57") (pin "8") (pinfunction "8_8") (pintype "passive"))
    )
    (net (code "600") (name "Net-(SV58-Pad1)") (class "Default")
      (node (ref "SV58") (pin "1") (pinfunction "1_1") (pintype "passive"))
      (node (ref "SV58") (pin "3") (pinfunction "3_3") (pintype "passive"))
      (node (ref "SV58") (pin "5") (pinfunction "5_5") (pintype "passive"))
      (node (ref "SV58") (pin "7") (pinfunction "7_7") (pintype "passive"))
      (node (ref "SV58") (pin "9") (pinfunction "9_9") (pintype "passive"))
    )
    (net (code "601") (name "Net-(SV58-Pad10)") (class "Default")
      (node (ref "SV58") (pin "10") (pinfunction "10_10") (pintype "passive"))
      (node (ref "SV58") (pin "2") (pinfunction "2_2") (pintype "passive"))
      (node (ref "SV58") (pin "4") (pinfunction "4_4") (pintype "passive"))
      (node (ref "SV58") (pin "6") (pinfunction "6_6") (pintype "passive"))
      (node (ref "SV58") (pin "8") (pinfunction "8_8") (pintype "passive"))
    )
    (net (code "602") (name "Net-(SV59-Pad1)") (class "Default")
      (node (ref "SV59") (pin "1") (pinfunction "1_1") (pintype "passive"))
      (node (ref "SV59") (pin "3") (pinfunction "3_3") (pintype "passive"))
      (node (ref "SV59") (pin "5") (pinfunction "5_5") (pintype "passive"))
      (node (ref "SV59") (pin "7") (pinfunction "7_7") (pintype "passive"))
      (node (ref "SV59") (pin "9") (pinfunction "9_9") (pintype "passive"))
    )
    (net (code "603") (name "Net-(SV59-Pad10)") (class "Default")
      (node (ref "SV59") (pin "10") (pinfunction "10_10") (pintype "passive"))
      (node (ref "SV59") (pin "2") (pinfunction "2_2") (pintype "passive"))
      (node (ref "SV59") (pin "4") (pinfunction "4_4") (pintype "passive"))
      (node (ref "SV59") (pin "6") (pinfunction "6_6") (pintype "passive"))
      (node (ref "SV59") (pin "8") (pinfunction "8_8") (pintype "passive"))
    )
    (net (code "604") (name "Net-(SV60-Pad1)") (class "Default")
      (node (ref "SV60") (pin "1") (pinfunction "1_1") (pintype "passive"))
      (node (ref "SV60") (pin "3") (pinfunction "3_3") (pintype "passive"))
      (node (ref "SV60") (pin "5") (pinfunction "5_5") (pintype "passive"))
      (node (ref "SV60") (pin "7") (pinfunction "7_7") (pintype "passive"))
      (node (ref "SV60") (pin "9") (pinfunction "9_9") (pintype "passive"))
    )
    (net (code "605") (name "Net-(SV60-Pad10)") (class "Default")
      (node (ref "SV60") (pin "10") (pinfunction "10_10") (pintype "passive"))
      (node (ref "SV60") (pin "2") (pinfunction "2_2") (pintype "passive"))
      (node (ref "SV60") (pin "4") (pinfunction "4_4") (pintype "passive"))
      (node (ref "SV60") (pin "6") (pinfunction "6_6") (pintype "passive"))
      (node (ref "SV60") (pin "8") (pinfunction "8_8") (pintype "passive"))
    )
    (net (code "606") (name "Net-(SV61-Pad1)") (class "Default")
      (node (ref "SV61") (pin "1") (pinfunction "1_1") (pintype "passive"))
      (node (ref "SV61") (pin "3") (pinfunction "3_3") (pintype "passive"))
      (node (ref "SV61") (pin "5") (pinfunction "5_5") (pintype "passive"))
      (node (ref "SV61") (pin "7") (pinfunction "7_7") (pintype "passive"))
      (node (ref "SV61") (pin "9") (pinfunction "9_9") (pintype "passive"))
    )
    (net (code "607") (name "Net-(SV61-Pad10)") (class "Default")
      (node (ref "SV61") (pin "10") (pinfunction "10_10") (pintype "passive"))
      (node (ref "SV61") (pin "2") (pinfunction "2_2") (pintype "passive"))
      (node (ref "SV61") (pin "4") (pinfunction "4_4") (pintype "passive"))
      (node (ref "SV61") (pin "6") (pinfunction "6_6") (pintype "passive"))
      (node (ref "SV61") (pin "8") (pinfunction "8_8") (pintype "passive"))
    )
    (net (code "608") (name "Net-(SV62-Pad1)") (class "Default")
      (node (ref "SV62") (pin "1") (pinfunction "1_1") (pintype "passive"))
      (node (ref "SV62") (pin "3") (pinfunction "3_3") (pintype "passive"))
      (node (ref "SV62") (pin "5") (pinfunction "5_5") (pintype "passive"))
      (node (ref "SV62") (pin "7") (pinfunction "7_7") (pintype "passive"))
      (node (ref "SV62") (pin "9") (pinfunction "9_9") (pintype "passive"))
    )
    (net (code "609") (name "Net-(SV62-Pad10)") (class "Default")
      (node (ref "SV62") (pin "10") (pinfunction "10_10") (pintype "passive"))
      (node (ref "SV62") (pin "2") (pinfunction "2_2") (pintype "passive"))
      (node (ref "SV62") (pin "4") (pinfunction "4_4") (pintype "passive"))
      (node (ref "SV62") (pin "6") (pinfunction "6_6") (pintype "passive"))
      (node (ref "SV62") (pin "8") (pinfunction "8_8") (pintype "passive"))
    )
    (net (code "610") (name "Net-(SV63-Pad1)") (class "Default")
      (node (ref "SV63") (pin "1") (pinfunction "1_1") (pintype "passive"))
      (node (ref "SV63") (pin "3") (pinfunction "3_3") (pintype "passive"))
      (node (ref "SV63") (pin "5") (pinfunction "5_5") (pintype "passive"))
      (node (ref "SV63") (pin "7") (pinfunction "7_7") (pintype "passive"))
      (node (ref "SV63") (pin "9") (pinfunction "9_9") (pintype "passive"))
    )
    (net (code "611") (name "Net-(SV63-Pad10)") (class "Default")
      (node (ref "SV63") (pin "10") (pinfunction "10_10") (pintype "passive"))
      (node (ref "SV63") (pin "2") (pinfunction "2_2") (pintype "passive"))
      (node (ref "SV63") (pin "4") (pinfunction "4_4") (pintype "passive"))
      (node (ref "SV63") (pin "6") (pinfunction "6_6") (pintype "passive"))
      (node (ref "SV63") (pin "8") (pinfunction "8_8") (pintype "passive"))
    )
    (net (code "612") (name "Net-(SV64-Pad1)") (class "Default")
      (node (ref "SV64") (pin "1") (pinfunction "1_1") (pintype "passive"))
      (node (ref "SV64") (pin "3") (pinfunction "3_3") (pintype "passive"))
      (node (ref "SV64") (pin "5") (pinfunction "5_5") (pintype "passive"))
      (node (ref "SV64") (pin "7") (pinfunction "7_7") (pintype "passive"))
      (node (ref "SV64") (pin "9") (pinfunction "9_9") (pintype "passive"))
    )
    (net (code "613") (name "Net-(SV64-Pad10)") (class "Default")
      (node (ref "SV64") (pin "10") (pinfunction "10_10") (pintype "passive"))
      (node (ref "SV64") (pin "2") (pinfunction "2_2") (pintype "passive"))
      (node (ref "SV64") (pin "4") (pinfunction "4_4") (pintype "passive"))
      (node (ref "SV64") (pin "6") (pinfunction "6_6") (pintype "passive"))
      (node (ref "SV64") (pin "8") (pinfunction "8_8") (pintype "passive"))
    )
    (net (code "614") (name "Net-(SV65-Pad1)") (class "Default")
      (node (ref "SV65") (pin "1") (pinfunction "1_1") (pintype "passive"))
      (node (ref "SV65") (pin "3") (pinfunction "3_3") (pintype "passive"))
      (node (ref "SV65") (pin "5") (pinfunction "5_5") (pintype "passive"))
      (node (ref "SV65") (pin "7") (pinfunction "7_7") (pintype "passive"))
      (node (ref "SV65") (pin "9") (pinfunction "9_9") (pintype "passive"))
    )
    (net (code "615") (name "Net-(SV65-Pad10)") (class "Default")
      (node (ref "SV65") (pin "10") (pinfunction "10_10") (pintype "passive"))
      (node (ref "SV65") (pin "2") (pinfunction "2_2") (pintype "passive"))
      (node (ref "SV65") (pin "4") (pinfunction "4_4") (pintype "passive"))
      (node (ref "SV65") (pin "6") (pinfunction "6_6") (pintype "passive"))
      (node (ref "SV65") (pin "8") (pinfunction "8_8") (pintype "passive"))
    )
    (net (code "616") (name "Net-(SV66-Pad1)") (class "Default")
      (node (ref "SV66") (pin "1") (pinfunction "1_1") (pintype "passive"))
      (node (ref "SV66") (pin "3") (pinfunction "3_3") (pintype "passive"))
      (node (ref "SV66") (pin "5") (pinfunction "5_5") (pintype "passive"))
      (node (ref "SV66") (pin "7") (pinfunction "7_7") (pintype "passive"))
      (node (ref "SV66") (pin "9") (pinfunction "9_9") (pintype "passive"))
    )
    (net (code "617") (name "Net-(SV66-Pad10)") (class "Default")
      (node (ref "SV66") (pin "10") (pinfunction "10_10") (pintype "passive"))
      (node (ref "SV66") (pin "2") (pinfunction "2_2") (pintype "passive"))
      (node (ref "SV66") (pin "4") (pinfunction "4_4") (pintype "passive"))
      (node (ref "SV66") (pin "6") (pinfunction "6_6") (pintype "passive"))
      (node (ref "SV66") (pin "8") (pinfunction "8_8") (pintype "passive"))
    )
    (net (code "618") (name "Net-(SV67-Pad1)") (class "Default")
      (node (ref "SV67") (pin "1") (pinfunction "1_1") (pintype "passive"))
      (node (ref "SV67") (pin "3") (pinfunction "3_3") (pintype "passive"))
      (node (ref "SV67") (pin "5") (pinfunction "5_5") (pintype "passive"))
      (node (ref "SV67") (pin "7") (pinfunction "7_7") (pintype "passive"))
      (node (ref "SV67") (pin "9") (pinfunction "9_9") (pintype "passive"))
    )
    (net (code "619") (name "Net-(SV67-Pad10)") (class "Default")
      (node (ref "SV67") (pin "10") (pinfunction "10_10") (pintype "passive"))
      (node (ref "SV67") (pin "2") (pinfunction "2_2") (pintype "passive"))
      (node (ref "SV67") (pin "4") (pinfunction "4_4") (pintype "passive"))
      (node (ref "SV67") (pin "6") (pinfunction "6_6") (pintype "passive"))
      (node (ref "SV67") (pin "8") (pinfunction "8_8") (pintype "passive"))
    )
    (net (code "620") (name "Net-(SV68-Pad1)") (class "Default")
      (node (ref "SV68") (pin "1") (pinfunction "1_1") (pintype "passive"))
      (node (ref "SV68") (pin "3") (pinfunction "3_3") (pintype "passive"))
      (node (ref "SV68") (pin "5") (pinfunction "5_5") (pintype "passive"))
      (node (ref "SV68") (pin "7") (pinfunction "7_7") (pintype "passive"))
      (node (ref "SV68") (pin "9") (pinfunction "9_9") (pintype "passive"))
    )
    (net (code "621") (name "Net-(SV68-Pad10)") (class "Default")
      (node (ref "SV68") (pin "10") (pinfunction "10_10") (pintype "passive"))
      (node (ref "SV68") (pin "2") (pinfunction "2_2") (pintype "passive"))
      (node (ref "SV68") (pin "4") (pinfunction "4_4") (pintype "passive"))
      (node (ref "SV68") (pin "6") (pinfunction "6_6") (pintype "passive"))
      (node (ref "SV68") (pin "8") (pinfunction "8_8") (pintype "passive"))
    )
    (net (code "622") (name "Net-(SV69-Pad1)") (class "Default")
      (node (ref "SV69") (pin "1") (pinfunction "1_1") (pintype "passive"))
      (node (ref "SV69") (pin "3") (pinfunction "3_3") (pintype "passive"))
      (node (ref "SV69") (pin "5") (pinfunction "5_5") (pintype "passive"))
      (node (ref "SV69") (pin "7") (pinfunction "7_7") (pintype "passive"))
      (node (ref "SV69") (pin "9") (pinfunction "9_9") (pintype "passive"))
    )
    (net (code "623") (name "Net-(SV69-Pad10)") (class "Default")
      (node (ref "SV69") (pin "10") (pinfunction "10_10") (pintype "passive"))
      (node (ref "SV69") (pin "2") (pinfunction "2_2") (pintype "passive"))
      (node (ref "SV69") (pin "4") (pinfunction "4_4") (pintype "passive"))
      (node (ref "SV69") (pin "6") (pinfunction "6_6") (pintype "passive"))
      (node (ref "SV69") (pin "8") (pinfunction "8_8") (pintype "passive"))
    )
    (net (code "624") (name "Net-(SV70-Pad1)") (class "Default")
      (node (ref "SV70") (pin "1") (pinfunction "1_1") (pintype "passive"))
      (node (ref "SV70") (pin "3") (pinfunction "3_3") (pintype "passive"))
      (node (ref "SV70") (pin "5") (pinfunction "5_5") (pintype "passive"))
      (node (ref "SV70") (pin "7") (pinfunction "7_7") (pintype "passive"))
      (node (ref "SV70") (pin "9") (pinfunction "9_9") (pintype "passive"))
    )
    (net (code "625") (name "Net-(SV70-Pad10)") (class "Default")
      (node (ref "SV70") (pin "10") (pinfunction "10_10") (pintype "passive"))
      (node (ref "SV70") (pin "2") (pinfunction "2_2") (pintype "passive"))
      (node (ref "SV70") (pin "4") (pinfunction "4_4") (pintype "passive"))
      (node (ref "SV70") (pin "6") (pinfunction "6_6") (pintype "passive"))
      (node (ref "SV70") (pin "8") (pinfunction "8_8") (pintype "passive"))
    )
    (net (code "626") (name "Net-(SV71-Pad1)") (class "Default")
      (node (ref "SV71") (pin "1") (pinfunction "1_1") (pintype "passive"))
      (node (ref "SV71") (pin "3") (pinfunction "3_3") (pintype "passive"))
      (node (ref "SV71") (pin "5") (pinfunction "5_5") (pintype "passive"))
      (node (ref "SV71") (pin "7") (pinfunction "7_7") (pintype "passive"))
      (node (ref "SV71") (pin "9") (pinfunction "9_9") (pintype "passive"))
    )
    (net (code "627") (name "Net-(SV71-Pad10)") (class "Default")
      (node (ref "SV71") (pin "10") (pinfunction "10_10") (pintype "passive"))
      (node (ref "SV71") (pin "2") (pinfunction "2_2") (pintype "passive"))
      (node (ref "SV71") (pin "4") (pinfunction "4_4") (pintype "passive"))
      (node (ref "SV71") (pin "6") (pinfunction "6_6") (pintype "passive"))
      (node (ref "SV71") (pin "8") (pinfunction "8_8") (pintype "passive"))
    )
    (net (code "628") (name "Net-(SV72-Pad1)") (class "Default")
      (node (ref "SV72") (pin "1") (pinfunction "1_1") (pintype "passive"))
      (node (ref "SV72") (pin "3") (pinfunction "3_3") (pintype "passive"))
      (node (ref "SV72") (pin "5") (pinfunction "5_5") (pintype "passive"))
      (node (ref "SV72") (pin "7") (pinfunction "7_7") (pintype "passive"))
      (node (ref "SV72") (pin "9") (pinfunction "9_9") (pintype "passive"))
    )
    (net (code "629") (name "Net-(SV72-Pad10)") (class "Default")
      (node (ref "SV72") (pin "10") (pinfunction "10_10") (pintype "passive"))
      (node (ref "SV72") (pin "2") (pinfunction "2_2") (pintype "passive"))
      (node (ref "SV72") (pin "4") (pinfunction "4_4") (pintype "passive"))
      (node (ref "SV72") (pin "6") (pinfunction "6_6") (pintype "passive"))
      (node (ref "SV72") (pin "8") (pinfunction "8_8") (pintype "passive"))
    )
    (net (code "630") (name "Net-(SV73-Pad1)") (class "Default")
      (node (ref "SV73") (pin "1") (pinfunction "1_1") (pintype "passive"))
      (node (ref "SV73") (pin "3") (pinfunction "3_3") (pintype "passive"))
      (node (ref "SV73") (pin "5") (pinfunction "5_5") (pintype "passive"))
      (node (ref "SV73") (pin "7") (pinfunction "7_7") (pintype "passive"))
      (node (ref "SV73") (pin "9") (pinfunction "9_9") (pintype "passive"))
    )
    (net (code "631") (name "Net-(SV73-Pad10)") (class "Default")
      (node (ref "SV73") (pin "10") (pinfunction "10_10") (pintype "passive"))
      (node (ref "SV73") (pin "2") (pinfunction "2_2") (pintype "passive"))
      (node (ref "SV73") (pin "4") (pinfunction "4_4") (pintype "passive"))
      (node (ref "SV73") (pin "6") (pinfunction "6_6") (pintype "passive"))
      (node (ref "SV73") (pin "8") (pinfunction "8_8") (pintype "passive"))
    )
    (net (code "632") (name "Net-(SV74-Pad1)") (class "Default")
      (node (ref "SV74") (pin "1") (pinfunction "1_1") (pintype "passive"))
      (node (ref "SV74") (pin "3") (pinfunction "3_3") (pintype "passive"))
      (node (ref "SV74") (pin "5") (pinfunction "5_5") (pintype "passive"))
      (node (ref "SV74") (pin "7") (pinfunction "7_7") (pintype "passive"))
      (node (ref "SV74") (pin "9") (pinfunction "9_9") (pintype "passive"))
    )
    (net (code "633") (name "Net-(SV74-Pad10)") (class "Default")
      (node (ref "SV74") (pin "10") (pinfunction "10_10") (pintype "passive"))
      (node (ref "SV74") (pin "2") (pinfunction "2_2") (pintype "passive"))
      (node (ref "SV74") (pin "4") (pinfunction "4_4") (pintype "passive"))
      (node (ref "SV74") (pin "6") (pinfunction "6_6") (pintype "passive"))
      (node (ref "SV74") (pin "8") (pinfunction "8_8") (pintype "passive"))
    )
    (net (code "634") (name "Net-(SV75-Pad1)") (class "Default")
      (node (ref "SV75") (pin "1") (pinfunction "1_1") (pintype "passive"))
      (node (ref "SV75") (pin "3") (pinfunction "3_3") (pintype "passive"))
      (node (ref "SV75") (pin "5") (pinfunction "5_5") (pintype "passive"))
      (node (ref "SV75") (pin "7") (pinfunction "7_7") (pintype "passive"))
      (node (ref "SV75") (pin "9") (pinfunction "9_9") (pintype "passive"))
    )
    (net (code "635") (name "Net-(SV75-Pad10)") (class "Default")
      (node (ref "SV75") (pin "10") (pinfunction "10_10") (pintype "passive"))
      (node (ref "SV75") (pin "2") (pinfunction "2_2") (pintype "passive"))
      (node (ref "SV75") (pin "4") (pinfunction "4_4") (pintype "passive"))
      (node (ref "SV75") (pin "6") (pinfunction "6_6") (pintype "passive"))
      (node (ref "SV75") (pin "8") (pinfunction "8_8") (pintype "passive"))
    )
    (net (code "636") (name "Net-(SV76-Pad1)") (class "Default")
      (node (ref "SV76") (pin "1") (pinfunction "1_1") (pintype "passive"))
      (node (ref "SV76") (pin "3") (pinfunction "3_3") (pintype "passive"))
      (node (ref "SV76") (pin "5") (pinfunction "5_5") (pintype "passive"))
      (node (ref "SV76") (pin "7") (pinfunction "7_7") (pintype "passive"))
      (node (ref "SV76") (pin "9") (pinfunction "9_9") (pintype "passive"))
    )
    (net (code "637") (name "Net-(SV76-Pad10)") (class "Default")
      (node (ref "SV76") (pin "10") (pinfunction "10_10") (pintype "passive"))
      (node (ref "SV76") (pin "2") (pinfunction "2_2") (pintype "passive"))
      (node (ref "SV76") (pin "4") (pinfunction "4_4") (pintype "passive"))
      (node (ref "SV76") (pin "6") (pinfunction "6_6") (pintype "passive"))
      (node (ref "SV76") (pin "8") (pinfunction "8_8") (pintype "passive"))
    )
    (net (code "638") (name "Net-(SV77-Pad1)") (class "Default")
      (node (ref "SV77") (pin "1") (pinfunction "1_1") (pintype "passive"))
      (node (ref "SV77") (pin "3") (pinfunction "3_3") (pintype "passive"))
      (node (ref "SV77") (pin "5") (pinfunction "5_5") (pintype "passive"))
      (node (ref "SV77") (pin "7") (pinfunction "7_7") (pintype "passive"))
      (node (ref "SV77") (pin "9") (pinfunction "9_9") (pintype "passive"))
    )
    (net (code "639") (name "Net-(SV77-Pad10)") (class "Default")
      (node (ref "SV77") (pin "10") (pinfunction "10_10") (pintype "passive"))
      (node (ref "SV77") (pin "2") (pinfunction "2_2") (pintype "passive"))
      (node (ref "SV77") (pin "4") (pinfunction "4_4") (pintype "passive"))
      (node (ref "SV77") (pin "6") (pinfunction "6_6") (pintype "passive"))
      (node (ref "SV77") (pin "8") (pinfunction "8_8") (pintype "passive"))
    )
    (net (code "640") (name "Net-(SV78-Pad1)") (class "Default")
      (node (ref "SV78") (pin "1") (pinfunction "1_1") (pintype "passive"))
      (node (ref "SV78") (pin "3") (pinfunction "3_3") (pintype "passive"))
      (node (ref "SV78") (pin "5") (pinfunction "5_5") (pintype "passive"))
      (node (ref "SV78") (pin "7") (pinfunction "7_7") (pintype "passive"))
      (node (ref "SV78") (pin "9") (pinfunction "9_9") (pintype "passive"))
    )
    (net (code "641") (name "Net-(SV78-Pad10)") (class "Default")
      (node (ref "SV78") (pin "10") (pinfunction "10_10") (pintype "passive"))
      (node (ref "SV78") (pin "2") (pinfunction "2_2") (pintype "passive"))
      (node (ref "SV78") (pin "4") (pinfunction "4_4") (pintype "passive"))
      (node (ref "SV78") (pin "6") (pinfunction "6_6") (pintype "passive"))
      (node (ref "SV78") (pin "8") (pinfunction "8_8") (pintype "passive"))
    )
    (net (code "642") (name "Net-(SV79-Pad1)") (class "Default")
      (node (ref "SV79") (pin "1") (pinfunction "1_1") (pintype "passive"))
      (node (ref "SV79") (pin "3") (pinfunction "3_3") (pintype "passive"))
      (node (ref "SV79") (pin "5") (pinfunction "5_5") (pintype "passive"))
      (node (ref "SV79") (pin "7") (pinfunction "7_7") (pintype "passive"))
      (node (ref "SV79") (pin "9") (pinfunction "9_9") (pintype "passive"))
    )
    (net (code "643") (name "Net-(SV79-Pad10)") (class "Default")
      (node (ref "SV79") (pin "10") (pinfunction "10_10") (pintype "passive"))
      (node (ref "SV79") (pin "2") (pinfunction "2_2") (pintype "passive"))
      (node (ref "SV79") (pin "4") (pinfunction "4_4") (pintype "passive"))
      (node (ref "SV79") (pin "6") (pinfunction "6_6") (pintype "passive"))
      (node (ref "SV79") (pin "8") (pinfunction "8_8") (pintype "passive"))
    )
    (net (code "644") (name "Net-(SV80-Pad1)") (class "Default")
      (node (ref "SV80") (pin "1") (pinfunction "1_1") (pintype "passive"))
      (node (ref "SV80") (pin "3") (pinfunction "3_3") (pintype "passive"))
      (node (ref "SV80") (pin "5") (pinfunction "5_5") (pintype "passive"))
      (node (ref "SV80") (pin "7") (pinfunction "7_7") (pintype "passive"))
      (node (ref "SV80") (pin "9") (pinfunction "9_9") (pintype "passive"))
    )
    (net (code "645") (name "Net-(SV80-Pad10)") (class "Default")
      (node (ref "SV80") (pin "10") (pinfunction "10_10") (pintype "passive"))
      (node (ref "SV80") (pin "2") (pinfunction "2_2") (pintype "passive"))
      (node (ref "SV80") (pin "4") (pinfunction "4_4") (pintype "passive"))
      (node (ref "SV80") (pin "6") (pinfunction "6_6") (pintype "passive"))
      (node (ref "SV80") (pin "8") (pinfunction "8_8") (pintype "passive"))
    )
    (net (code "646") (name "Net-(SV81-Pad1)") (class "Default")
      (node (ref "SV81") (pin "1") (pinfunction "1_1") (pintype "passive"))
      (node (ref "SV81") (pin "3") (pinfunction "3_3") (pintype "passive"))
      (node (ref "SV81") (pin "5") (pinfunction "5_5") (pintype "passive"))
      (node (ref "SV81") (pin "7") (pinfunction "7_7") (pintype "passive"))
      (node (ref "SV81") (pin "9") (pinfunction "9_9") (pintype "passive"))
    )
    (net (code "647") (name "Net-(SV81-Pad10)") (class "Default")
      (node (ref "SV81") (pin "10") (pinfunction "10_10") (pintype "passive"))
      (node (ref "SV81") (pin "2") (pinfunction "2_2") (pintype "passive"))
      (node (ref "SV81") (pin "4") (pinfunction "4_4") (pintype "passive"))
      (node (ref "SV81") (pin "6") (pinfunction "6_6") (pintype "passive"))
      (node (ref "SV81") (pin "8") (pinfunction "8_8") (pintype "passive"))
    )
    (net (code "648") (name "Net-(SV82-Pad1)") (class "Default")
      (node (ref "SV82") (pin "1") (pinfunction "1_1") (pintype "passive"))
      (node (ref "SV82") (pin "3") (pinfunction "3_3") (pintype "passive"))
      (node (ref "SV82") (pin "5") (pinfunction "5_5") (pintype "passive"))
      (node (ref "SV82") (pin "7") (pinfunction "7_7") (pintype "passive"))
      (node (ref "SV82") (pin "9") (pinfunction "9_9") (pintype "passive"))
    )
    (net (code "649") (name "Net-(SV82-Pad10)") (class "Default")
      (node (ref "SV82") (pin "10") (pinfunction "10_10") (pintype "passive"))
      (node (ref "SV82") (pin "2") (pinfunction "2_2") (pintype "passive"))
      (node (ref "SV82") (pin "4") (pinfunction "4_4") (pintype "passive"))
      (node (ref "SV82") (pin "6") (pinfunction "6_6") (pintype "passive"))
      (node (ref "SV82") (pin "8") (pinfunction "8_8") (pintype "passive"))
    )
    (net (code "650") (name "Net-(SV83-Pad1)") (class "Default")
      (node (ref "SV83") (pin "1") (pinfunction "1_1") (pintype "passive"))
      (node (ref "SV83") (pin "3") (pinfunction "3_3") (pintype "passive"))
      (node (ref "SV83") (pin "5") (pinfunction "5_5") (pintype "passive"))
      (node (ref "SV83") (pin "7") (pinfunction "7_7") (pintype "passive"))
      (node (ref "SV83") (pin "9") (pinfunction "9_9") (pintype "passive"))
    )
    (net (code "651") (name "Net-(SV83-Pad10)") (class "Default")
      (node (ref "SV83") (pin "10") (pinfunction "10_10") (pintype "passive"))
      (node (ref "SV83") (pin "2") (pinfunction "2_2") (pintype "passive"))
      (node (ref "SV83") (pin "4") (pinfunction "4_4") (pintype "passive"))
      (node (ref "SV83") (pin "6") (pinfunction "6_6") (pintype "passive"))
      (node (ref "SV83") (pin "8") (pinfunction "8_8") (pintype "passive"))
    )
    (net (code "652") (name "Net-(SV84-Pad1)") (class "Default")
      (node (ref "SV84") (pin "1") (pinfunction "1_1") (pintype "passive"))
      (node (ref "SV84") (pin "3") (pinfunction "3_3") (pintype "passive"))
      (node (ref "SV84") (pin "5") (pinfunction "5_5") (pintype "passive"))
      (node (ref "SV84") (pin "7") (pinfunction "7_7") (pintype "passive"))
      (node (ref "SV84") (pin "9") (pinfunction "9_9") (pintype "passive"))
    )
    (net (code "653") (name "Net-(SV84-Pad10)") (class "Default")
      (node (ref "SV84") (pin "10") (pinfunction "10_10") (pintype "passive"))
      (node (ref "SV84") (pin "2") (pinfunction "2_2") (pintype "passive"))
      (node (ref "SV84") (pin "4") (pinfunction "4_4") (pintype "passive"))
      (node (ref "SV84") (pin "6") (pinfunction "6_6") (pintype "passive"))
      (node (ref "SV84") (pin "8") (pinfunction "8_8") (pintype "passive"))
    )
    (net (code "654") (name "Net-(SV85-Pad1)") (class "Default")
      (node (ref "SV85") (pin "1") (pinfunction "1_1") (pintype "passive"))
      (node (ref "SV85") (pin "3") (pinfunction "3_3") (pintype "passive"))
      (node (ref "SV85") (pin "5") (pinfunction "5_5") (pintype "passive"))
      (node (ref "SV85") (pin "7") (pinfunction "7_7") (pintype "passive"))
      (node (ref "SV85") (pin "9") (pinfunction "9_9") (pintype "passive"))
    )
    (net (code "655") (name "Net-(SV85-Pad10)") (class "Default")
      (node (ref "SV85") (pin "10") (pinfunction "10_10") (pintype "passive"))
      (node (ref "SV85") (pin "2") (pinfunction "2_2") (pintype "passive"))
      (node (ref "SV85") (pin "4") (pinfunction "4_4") (pintype "passive"))
      (node (ref "SV85") (pin "6") (pinfunction "6_6") (pintype "passive"))
      (node (ref "SV85") (pin "8") (pinfunction "8_8") (pintype "passive"))
    )
    (net (code "656") (name "Net-(SV86-Pad1)") (class "Default")
      (node (ref "SV86") (pin "1") (pinfunction "1_1") (pintype "passive"))
      (node (ref "SV86") (pin "3") (pinfunction "3_3") (pintype "passive"))
      (node (ref "SV86") (pin "5") (pinfunction "5_5") (pintype "passive"))
      (node (ref "SV86") (pin "7") (pinfunction "7_7") (pintype "passive"))
      (node (ref "SV86") (pin "9") (pinfunction "9_9") (pintype "passive"))
    )
    (net (code "657") (name "Net-(SV86-Pad10)") (class "Default")
      (node (ref "SV86") (pin "10") (pinfunction "10_10") (pintype "passive"))
      (node (ref "SV86") (pin "2") (pinfunction "2_2") (pintype "passive"))
      (node (ref "SV86") (pin "4") (pinfunction "4_4") (pintype "passive"))
      (node (ref "SV86") (pin "6") (pinfunction "6_6") (pintype "passive"))
      (node (ref "SV86") (pin "8") (pinfunction "8_8") (pintype "passive"))
    )
    (net (code "658") (name "Net-(SV87-Pad1)") (class "Default")
      (node (ref "SV87") (pin "1") (pinfunction "1_1") (pintype "passive"))
      (node (ref "SV87") (pin "3") (pinfunction "3_3") (pintype "passive"))
      (node (ref "SV87") (pin "5") (pinfunction "5_5") (pintype "passive"))
      (node (ref "SV87") (pin "7") (pinfunction "7_7") (pintype "passive"))
      (node (ref "SV87") (pin "9") (pinfunction "9_9") (pintype "passive"))
    )
    (net (code "659") (name "Net-(SV87-Pad10)") (class "Default")
      (node (ref "SV87") (pin "10") (pinfunction "10_10") (pintype "passive"))
      (node (ref "SV87") (pin "2") (pinfunction "2_2") (pintype "passive"))
      (node (ref "SV87") (pin "4") (pinfunction "4_4") (pintype "passive"))
      (node (ref "SV87") (pin "6") (pinfunction "6_6") (pintype "passive"))
      (node (ref "SV87") (pin "8") (pinfunction "8_8") (pintype "passive"))
    )
    (net (code "660") (name "Net-(SV88-Pad1)") (class "Default")
      (node (ref "SV88") (pin "1") (pinfunction "1_1") (pintype "passive"))
      (node (ref "SV88") (pin "3") (pinfunction "3_3") (pintype "passive"))
      (node (ref "SV88") (pin "5") (pinfunction "5_5") (pintype "passive"))
      (node (ref "SV88") (pin "7") (pinfunction "7_7") (pintype "passive"))
      (node (ref "SV88") (pin "9") (pinfunction "9_9") (pintype "passive"))
    )
    (net (code "661") (name "Net-(SV88-Pad10)") (class "Default")
      (node (ref "SV88") (pin "10") (pinfunction "10_10") (pintype "passive"))
      (node (ref "SV88") (pin "2") (pinfunction "2_2") (pintype "passive"))
      (node (ref "SV88") (pin "4") (pinfunction "4_4") (pintype "passive"))
      (node (ref "SV88") (pin "6") (pinfunction "6_6") (pintype "passive"))
      (node (ref "SV88") (pin "8") (pinfunction "8_8") (pintype "passive"))
    )
    (net (code "662") (name "Net-(SV89-Pad1)") (class "Default")
      (node (ref "SV89") (pin "1") (pinfunction "1_1") (pintype "passive"))
      (node (ref "SV89") (pin "3") (pinfunction "3_3") (pintype "passive"))
      (node (ref "SV89") (pin "5") (pinfunction "5_5") (pintype "passive"))
      (node (ref "SV89") (pin "7") (pinfunction "7_7") (pintype "passive"))
      (node (ref "SV89") (pin "9") (pinfunction "9_9") (pintype "passive"))
    )
    (net (code "663") (name "Net-(SV89-Pad10)") (class "Default")
      (node (ref "SV89") (pin "10") (pinfunction "10_10") (pintype "passive"))
      (node (ref "SV89") (pin "2") (pinfunction "2_2") (pintype "passive"))
      (node (ref "SV89") (pin "4") (pinfunction "4_4") (pintype "passive"))
      (node (ref "SV89") (pin "6") (pinfunction "6_6") (pintype "passive"))
      (node (ref "SV89") (pin "8") (pinfunction "8_8") (pintype "passive"))
    )
    (net (code "664") (name "Net-(SV90-Pad1)") (class "Default")
      (node (ref "SV90") (pin "1") (pinfunction "1_1") (pintype "passive"))
      (node (ref "SV90") (pin "3") (pinfunction "3_3") (pintype "passive"))
      (node (ref "SV90") (pin "5") (pinfunction "5_5") (pintype "passive"))
      (node (ref "SV90") (pin "7") (pinfunction "7_7") (pintype "passive"))
      (node (ref "SV90") (pin "9") (pinfunction "9_9") (pintype "passive"))
    )
    (net (code "665") (name "Net-(SV90-Pad10)") (class "Default")
      (node (ref "SV90") (pin "10") (pinfunction "10_10") (pintype "passive"))
      (node (ref "SV90") (pin "2") (pinfunction "2_2") (pintype "passive"))
      (node (ref "SV90") (pin "4") (pinfunction "4_4") (pintype "passive"))
      (node (ref "SV90") (pin "6") (pinfunction "6_6") (pintype "passive"))
      (node (ref "SV90") (pin "8") (pinfunction "8_8") (pintype "passive"))
    )
    (net (code "666") (name "Net-(SV91-Pad1)") (class "Default")
      (node (ref "SV91") (pin "1") (pinfunction "1_1") (pintype "passive"))
      (node (ref "SV91") (pin "3") (pinfunction "3_3") (pintype "passive"))
      (node (ref "SV91") (pin "5") (pinfunction "5_5") (pintype "passive"))
      (node (ref "SV91") (pin "7") (pinfunction "7_7") (pintype "passive"))
      (node (ref "SV91") (pin "9") (pinfunction "9_9") (pintype "passive"))
    )
    (net (code "667") (name "Net-(SV91-Pad10)") (class "Default")
      (node (ref "SV91") (pin "10") (pinfunction "10_10") (pintype "passive"))
      (node (ref "SV91") (pin "2") (pinfunction "2_2") (pintype "passive"))
      (node (ref "SV91") (pin "4") (pinfunction "4_4") (pintype "passive"))
      (node (ref "SV91") (pin "6") (pinfunction "6_6") (pintype "passive"))
      (node (ref "SV91") (pin "8") (pinfunction "8_8") (pintype "passive"))
    )
    (net (code "668") (name "Net-(SV92-Pad1)") (class "Default")
      (node (ref "SV92") (pin "1") (pinfunction "1_1") (pintype "passive"))
      (node (ref "SV92") (pin "3") (pinfunction "3_3") (pintype "passive"))
      (node (ref "SV92") (pin "5") (pinfunction "5_5") (pintype "passive"))
      (node (ref "SV92") (pin "7") (pinfunction "7_7") (pintype "passive"))
      (node (ref "SV92") (pin "9") (pinfunction "9_9") (pintype "passive"))
    )
    (net (code "669") (name "Net-(SV92-Pad10)") (class "Default")
      (node (ref "SV92") (pin "10") (pinfunction "10_10") (pintype "passive"))
      (node (ref "SV92") (pin "2") (pinfunction "2_2") (pintype "passive"))
      (node (ref "SV92") (pin "4") (pinfunction "4_4") (pintype "passive"))
      (node (ref "SV92") (pin "6") (pinfunction "6_6") (pintype "passive"))
      (node (ref "SV92") (pin "8") (pinfunction "8_8") (pintype "passive"))
    )
    (net (code "670") (name "Net-(SV93-Pad1)") (class "Default")
      (node (ref "SV93") (pin "1") (pinfunction "1_1") (pintype "passive"))
      (node (ref "SV93") (pin "3") (pinfunction "3_3") (pintype "passive"))
      (node (ref "SV93") (pin "5") (pinfunction "5_5") (pintype "passive"))
      (node (ref "SV93") (pin "7") (pinfunction "7_7") (pintype "passive"))
      (node (ref "SV93") (pin "9") (pinfunction "9_9") (pintype "passive"))
    )
    (net (code "671") (name "Net-(SV93-Pad10)") (class "Default")
      (node (ref "SV93") (pin "10") (pinfunction "10_10") (pintype "passive"))
      (node (ref "SV93") (pin "2") (pinfunction "2_2") (pintype "passive"))
      (node (ref "SV93") (pin "4") (pinfunction "4_4") (pintype "passive"))
      (node (ref "SV93") (pin "6") (pinfunction "6_6") (pintype "passive"))
      (node (ref "SV93") (pin "8") (pinfunction "8_8") (pintype "passive"))
    )
    (net (code "672") (name "Net-(SV94-Pad1)") (class "Default")
      (node (ref "SV94") (pin "1") (pinfunction "1_1") (pintype "passive"))
      (node (ref "SV94") (pin "3") (pinfunction "3_3") (pintype "passive"))
      (node (ref "SV94") (pin "5") (pinfunction "5_5") (pintype "passive"))
      (node (ref "SV94") (pin "7") (pinfunction "7_7") (pintype "passive"))
      (node (ref "SV94") (pin "9") (pinfunction "9_9") (pintype "passive"))
    )
    (net (code "673") (name "Net-(SV94-Pad10)") (class "Default")
      (node (ref "SV94") (pin "10") (pinfunction "10_10") (pintype "passive"))
      (node (ref "SV94") (pin "2") (pinfunction "2_2") (pintype "passive"))
      (node (ref "SV94") (pin "4") (pinfunction "4_4") (pintype "passive"))
      (node (ref "SV94") (pin "6") (pinfunction "6_6") (pintype "passive"))
      (node (ref "SV94") (pin "8") (pinfunction "8_8") (pintype "passive"))
    )
    (net (code "674") (name "Net-(SV95-Pad1)") (class "Default")
      (node (ref "SV95") (pin "1") (pinfunction "1_1") (pintype "passive"))
      (node (ref "SV95") (pin "3") (pinfunction "3_3") (pintype "passive"))
      (node (ref "SV95") (pin "5") (pinfunction "5_5") (pintype "passive"))
      (node (ref "SV95") (pin "7") (pinfunction "7_7") (pintype "passive"))
      (node (ref "SV95") (pin "9") (pinfunction "9_9") (pintype "passive"))
    )
    (net (code "675") (name "Net-(SV95-Pad10)") (class "Default")
      (node (ref "SV95") (pin "10") (pinfunction "10_10") (pintype "passive"))
      (node (ref "SV95") (pin "2") (pinfunction "2_2") (pintype "passive"))
      (node (ref "SV95") (pin "4") (pinfunction "4_4") (pintype "passive"))
      (node (ref "SV95") (pin "6") (pinfunction "6_6") (pintype "passive"))
      (node (ref "SV95") (pin "8") (pinfunction "8_8") (pintype "passive"))
    )
    (net (code "676") (name "Net-(SV96-Pad1)") (class "Default")
      (node (ref "SV96") (pin "1") (pinfunction "1_1") (pintype "passive"))
      (node (ref "SV96") (pin "3") (pinfunction "3_3") (pintype "passive"))
      (node (ref "SV96") (pin "5") (pinfunction "5_5") (pintype "passive"))
      (node (ref "SV96") (pin "7") (pinfunction "7_7") (pintype "passive"))
      (node (ref "SV96") (pin "9") (pinfunction "9_9") (pintype "passive"))
    )
    (net (code "677") (name "Net-(SV96-Pad10)") (class "Default")
      (node (ref "SV96") (pin "10") (pinfunction "10_10") (pintype "passive"))
      (node (ref "SV96") (pin "2") (pinfunction "2_2") (pintype "passive"))
      (node (ref "SV96") (pin "4") (pinfunction "4_4") (pintype "passive"))
      (node (ref "SV96") (pin "6") (pinfunction "6_6") (pintype "passive"))
      (node (ref "SV96") (pin "8") (pinfunction "8_8") (pintype "passive"))
    )
    (net (code "678") (name "Net-(SV97-Pad1)") (class "Default")
      (node (ref "SV97") (pin "1") (pinfunction "1_1") (pintype "passive"))
      (node (ref "SV97") (pin "3") (pinfunction "3_3") (pintype "passive"))
      (node (ref "SV97") (pin "5") (pinfunction "5_5") (pintype "passive"))
      (node (ref "SV97") (pin "7") (pinfunction "7_7") (pintype "passive"))
      (node (ref "SV97") (pin "9") (pinfunction "9_9") (pintype "passive"))
    )
    (net (code "679") (name "Net-(SV97-Pad10)") (class "Default")
      (node (ref "SV97") (pin "10") (pinfunction "10_10") (pintype "passive"))
      (node (ref "SV97") (pin "2") (pinfunction "2_2") (pintype "passive"))
      (node (ref "SV97") (pin "4") (pinfunction "4_4") (pintype "passive"))
      (node (ref "SV97") (pin "6") (pinfunction "6_6") (pintype "passive"))
      (node (ref "SV97") (pin "8") (pinfunction "8_8") (pintype "passive"))
    )
    (net (code "680") (name "Net-(SV98-Pad1)") (class "Default")
      (node (ref "SV98") (pin "1") (pinfunction "1_1") (pintype "passive"))
      (node (ref "SV98") (pin "3") (pinfunction "3_3") (pintype "passive"))
      (node (ref "SV98") (pin "5") (pinfunction "5_5") (pintype "passive"))
      (node (ref "SV98") (pin "7") (pinfunction "7_7") (pintype "passive"))
      (node (ref "SV98") (pin "9") (pinfunction "9_9") (pintype "passive"))
    )
    (net (code "681") (name "Net-(SV98-Pad10)") (class "Default")
      (node (ref "SV98") (pin "10") (pinfunction "10_10") (pintype "passive"))
      (node (ref "SV98") (pin "2") (pinfunction "2_2") (pintype "passive"))
      (node (ref "SV98") (pin "4") (pinfunction "4_4") (pintype "passive"))
      (node (ref "SV98") (pin "6") (pinfunction "6_6") (pintype "passive"))
      (node (ref "SV98") (pin "8") (pinfunction "8_8") (pintype "passive"))
    )
    (net (code "682") (name "Net-(SV99-Pad1)") (class "Default")
      (node (ref "SV99") (pin "1") (pinfunction "1_1") (pintype "passive"))
      (node (ref "SV99") (pin "3") (pinfunction "3_3") (pintype "passive"))
      (node (ref "SV99") (pin "5") (pinfunction "5_5") (pintype "passive"))
      (node (ref "SV99") (pin "7") (pinfunction "7_7") (pintype "passive"))
      (node (ref "SV99") (pin "9") (pinfunction "9_9") (pintype "passive"))
    )
    (net (code "683") (name "Net-(SV99-Pad10)") (class "Default")
      (node (ref "SV99") (pin "10") (pinfunction "10_10") (pintype "passive"))
      (node (ref "SV99") (pin "2") (pinfunction "2_2") (pintype "passive"))
      (node (ref "SV99") (pin "4") (pinfunction "4_4") (pintype "passive"))
      (node (ref "SV99") (pin "6") (pinfunction "6_6") (pintype "passive"))
      (node (ref "SV99") (pin "8") (pinfunction "8_8") (pintype "passive"))
    )
    (net (code "684") (name "Net-(SV100-Pad1)") (class "Default")
      (node (ref "SV100") (pin "1") (pinfunction "1_1") (pintype "passive"))
      (node (ref "SV100") (pin "3") (pinfunction "3_3") (pintype "passive"))
      (node (ref "SV100") (pin "5") (pinfunction "5_5") (pintype "passive"))
      (node (ref "SV100") (pin "7") (pinfunction "7_7") (pintype "passive"))
      (node (ref "SV100") (pin "9") (pinfunction "9_9") (pintype "passive"))
    )
    (net (code "685") (name "Net-(SV100-Pad10)") (class "Default")
      (node (ref "SV100") (pin "10") (pinfunction "10_10") (pintype "passive"))
      (node (ref "SV100") (pin "2") (pinfunction "2_2") (pintype "passive"))
      (node (ref "SV100") (pin "4") (pinfunction "4_4") (pintype "passive"))
      (node (ref "SV100") (pin "6") (pinfunction "6_6") (pintype "passive"))
      (node (ref "SV100") (pin "8") (pinfunction "8_8") (pintype "passive"))
    )
    (net (code "686") (name "Net-(SV101-Pad1)") (class "Default")
      (node (ref "SV101") (pin "1") (pinfunction "1_1") (pintype "passive"))
      (node (ref "SV101") (pin "3") (pinfunction "3_3") (pintype "passive"))
      (node (ref "SV101") (pin "5") (pinfunction "5_5") (pintype "passive"))
      (node (ref "SV101") (pin "7") (pinfunction "7_7") (pintype "passive"))
      (node (ref "SV101") (pin "9") (pinfunction "9_9") (pintype "passive"))
    )
    (net (code "687") (name "Net-(SV101-Pad10)") (class "Default")
      (node (ref "SV101") (pin "10") (pinfunction "10_10") (pintype "passive"))
      (node (ref "SV101") (pin "2") (pinfunction "2_2") (pintype "passive"))
      (node (ref "SV101") (pin "4") (pinfunction "4_4") (pintype "passive"))
      (node (ref "SV101") (pin "6") (pinfunction "6_6") (pintype "passive"))
      (node (ref "SV101") (pin "8") (pinfunction "8_8") (pintype "passive"))
    )
    (net (code "688") (name "Net-(SV102-Pad1)") (class "Default")
      (node (ref "SV102") (pin "1") (pinfunction "1_1") (pintype "passive"))
      (node (ref "SV102") (pin "3") (pinfunction "3_3") (pintype "passive"))
      (node (ref "SV102") (pin "5") (pinfunction "5_5") (pintype "passive"))
      (node (ref "SV102") (pin "7") (pinfunction "7_7") (pintype "passive"))
      (node (ref "SV102") (pin "9") (pinfunction "9_9") (pintype "passive"))
    )
    (net (code "689") (name "Net-(SV102-Pad10)") (class "Default")
      (node (ref "SV102") (pin "10") (pinfunction "10_10") (pintype "passive"))
      (node (ref "SV102") (pin "2") (pinfunction "2_2") (pintype "passive"))
      (node (ref "SV102") (pin "4") (pinfunction "4_4") (pintype "passive"))
      (node (ref "SV102") (pin "6") (pinfunction "6_6") (pintype "passive"))
      (node (ref "SV102") (pin "8") (pinfunction "8_8") (pintype "passive"))
    )
    (net (code "690") (name "Net-(SV103-Pad1)") (class "Default")
      (node (ref "SV103") (pin "1") (pinfunction "1_1") (pintype "passive"))
      (node (ref "SV103") (pin "3") (pinfunction "3_3") (pintype "passive"))
      (node (ref "SV103") (pin "5") (pinfunction "5_5") (pintype "passive"))
      (node (ref "SV103") (pin "7") (pinfunction "7_7") (pintype "passive"))
      (node (ref "SV103") (pin "9") (pinfunction "9_9") (pintype "passive"))
    )
    (net (code "691") (name "Net-(SV103-Pad10)") (class "Default")
      (node (ref "SV103") (pin "10") (pinfunction "10_10") (pintype "passive"))
      (node (ref "SV103") (pin "2") (pinfunction "2_2") (pintype "passive"))
      (node (ref "SV103") (pin "4") (pinfunction "4_4") (pintype "passive"))
      (node (ref "SV103") (pin "6") (pinfunction "6_6") (pintype "passive"))
      (node (ref "SV103") (pin "8") (pinfunction "8_8") (pintype "passive"))
    )
    (net (code "692") (name "Net-(SV104-Pad1)") (class "Default")
      (node (ref "SV104") (pin "1") (pinfunction "1_1") (pintype "passive"))
      (node (ref "SV104") (pin "3") (pinfunction "3_3") (pintype "passive"))
      (node (ref "SV104") (pin "5") (pinfunction "5_5") (pintype "passive"))
      (node (ref "SV104") (pin "7") (pinfunction "7_7") (pintype "passive"))
      (node (ref "SV104") (pin "9") (pinfunction "9_9") (pintype "passive"))
    )
    (net (code "693") (name "Net-(SV104-Pad10)") (class "Default")
      (node (ref "SV104") (pin "10") (pinfunction "10_10") (pintype "passive"))
      (node (ref "SV104") (pin "2") (pinfunction "2_2") (pintype "passive"))
      (node (ref "SV104") (pin "4") (pinfunction "4_4") (pintype "passive"))
      (node (ref "SV104") (pin "6") (pinfunction "6_6") (pintype "passive"))
      (node (ref "SV104") (pin "8") (pinfunction "8_8") (pintype "passive"))
    )
    (net (code "694") (name "Net-(SV105-Pad1)") (class "Default")
      (node (ref "SV105") (pin "1") (pinfunction "1_1") (pintype "passive"))
      (node (ref "SV105") (pin "3") (pinfunction "3_3") (pintype "passive"))
      (node (ref "SV105") (pin "5") (pinfunction "5_5") (pintype "passive"))
      (node (ref "SV105") (pin "7") (pinfunction "7_7") (pintype "passive"))
      (node (ref "SV105") (pin "9") (pinfunction "9_9") (pintype "passive"))
    )
    (net (code "695") (name "Net-(SV105-Pad10)") (class "Default")
      (node (ref "SV105") (pin "10") (pinfunction "10_10") (pintype "passive"))
      (node (ref "SV105") (pin "2") (pinfunction "2_2") (pintype "passive"))
      (node (ref "SV105") (pin "4") (pinfunction "4_4") (pintype "passive"))
      (node (ref "SV105") (pin "6") (pinfunction "6_6") (pintype "passive"))
      (node (ref "SV105") (pin "8") (pinfunction "8_8") (pintype "passive"))
    )
    (net (code "696") (name "Net-(SV106-Pad1)") (class "Default")
      (node (ref "SV106") (pin "1") (pinfunction "1_1") (pintype "passive"))
      (node (ref "SV106") (pin "3") (pinfunction "3_3") (pintype "passive"))
      (node (ref "SV106") (pin "5") (pinfunction "5_5") (pintype "passive"))
      (node (ref "SV106") (pin "7") (pinfunction "7_7") (pintype "passive"))
      (node (ref "SV106") (pin "9") (pinfunction "9_9") (pintype "passive"))
    )
    (net (code "697") (name "Net-(SV106-Pad10)") (class "Default")
      (node (ref "SV106") (pin "10") (pinfunction "10_10") (pintype "passive"))
      (node (ref "SV106") (pin "2") (pinfunction "2_2") (pintype "passive"))
      (node (ref "SV106") (pin "4") (pinfunction "4_4") (pintype "passive"))
      (node (ref "SV106") (pin "6") (pinfunction "6_6") (pintype "passive"))
      (node (ref "SV106") (pin "8") (pinfunction "8_8") (pintype "passive"))
    )
    (net (code "698") (name "Net-(SV107-Pad1)") (class "Default")
      (node (ref "SV107") (pin "1") (pinfunction "1_1") (pintype "passive"))
      (node (ref "SV107") (pin "3") (pinfunction "3_3") (pintype "passive"))
      (node (ref "SV107") (pin "5") (pinfunction "5_5") (pintype "passive"))
      (node (ref "SV107") (pin "7") (pinfunction "7_7") (pintype "passive"))
      (node (ref "SV107") (pin "9") (pinfunction "9_9") (pintype "passive"))
    )
    (net (code "699") (name "Net-(SV107-Pad10)") (class "Default")
      (node (ref "SV107") (pin "10") (pinfunction "10_10") (pintype "passive"))
      (node (ref "SV107") (pin "2") (pinfunction "2_2") (pintype "passive"))
      (node (ref "SV107") (pin "4") (pinfunction "4_4") (pintype "passive"))
      (node (ref "SV107") (pin "6") (pinfunction "6_6") (pintype "passive"))
      (node (ref "SV107") (pin "8") (pinfunction "8_8") (pintype "passive"))
    )
    (net (code "700") (name "Net-(SV108-Pad1)") (class "Default")
      (node (ref "SV108") (pin "1") (pinfunction "1_1") (pintype "passive"))
      (node (ref "SV108") (pin "3") (pinfunction "3_3") (pintype "passive"))
      (node (ref "SV108") (pin "5") (pinfunction "5_5") (pintype "passive"))
      (node (ref "SV108") (pin "7") (pinfunction "7_7") (pintype "passive"))
      (node (ref "SV108") (pin "9") (pinfunction "9_9") (pintype "passive"))
    )
    (net (code "701") (name "Net-(SV108-Pad10)") (class "Default")
      (node (ref "SV108") (pin "10") (pinfunction "10_10") (pintype "passive"))
      (node (ref "SV108") (pin "2") (pinfunction "2_2") (pintype "passive"))
      (node (ref "SV108") (pin "4") (pinfunction "4_4") (pintype "passive"))
      (node (ref "SV108") (pin "6") (pinfunction "6_6") (pintype "passive"))
      (node (ref "SV108") (pin "8") (pinfunction "8_8") (pintype "passive"))
    )
    (net (code "702") (name "Net-(SV109-Pad1)") (class "Default")
      (node (ref "SV109") (pin "1") (pinfunction "1_1") (pintype "passive"))
      (node (ref "SV109") (pin "3") (pinfunction "3_3") (pintype "passive"))
      (node (ref "SV109") (pin "5") (pinfunction "5_5") (pintype "passive"))
      (node (ref "SV109") (pin "7") (pinfunction "7_7") (pintype "passive"))
      (node (ref "SV109") (pin "9") (pinfunction "9_9") (pintype "passive"))
    )
    (net (code "703") (name "Net-(SV109-Pad10)") (class "Default")
      (node (ref "SV109") (pin "10") (pinfunction "10_10") (pintype "passive"))
      (node (ref "SV109") (pin "2") (pinfunction "2_2") (pintype "passive"))
      (node (ref "SV109") (pin "4") (pinfunction "4_4") (pintype "passive"))
      (node (ref "SV109") (pin "6") (pinfunction "6_6") (pintype "passive"))
      (node (ref "SV109") (pin "8") (pinfunction "8_8") (pintype "passive"))
    )
    (net (code "704") (name "Net-(SV110-Pad1)") (class "Default")
      (node (ref "SV110") (pin "1") (pinfunction "1_1") (pintype "passive"))
      (node (ref "SV110") (pin "3") (pinfunction "3_3") (pintype "passive"))
      (node (ref "SV110") (pin "5") (pinfunction "5_5") (pintype "passive"))
      (node (ref "SV110") (pin "7") (pinfunction "7_7") (pintype "passive"))
      (node (ref "SV110") (pin "9") (pinfunction "9_9") (pintype "passive"))
    )
    (net (code "705") (name "Net-(SV110-Pad10)") (class "Default")
      (node (ref "SV110") (pin "10") (pinfunction "10_10") (pintype "passive"))
      (node (ref "SV110") (pin "2") (pinfunction "2_2") (pintype "passive"))
      (node (ref "SV110") (pin "4") (pinfunction "4_4") (pintype "passive"))
      (node (ref "SV110") (pin "6") (pinfunction "6_6") (pintype "passive"))
      (node (ref "SV110") (pin "8") (pinfunction "8_8") (pintype "passive"))
    )
    (net (code "706") (name "Net-(SV111-Pad1)") (class "Default")
      (node (ref "SV111") (pin "1") (pinfunction "1_1") (pintype "passive"))
      (node (ref "SV111") (pin "3") (pinfunction "3_3") (pintype "passive"))
      (node (ref "SV111") (pin "5") (pinfunction "5_5") (pintype "passive"))
      (node (ref "SV111") (pin "7") (pinfunction "7_7") (pintype "passive"))
      (node (ref "SV111") (pin "9") (pinfunction "9_9") (pintype "passive"))
    )
    (net (code "707") (name "Net-(SV111-Pad10)") (class "Default")
      (node (ref "SV111") (pin "10") (pinfunction "10_10") (pintype "passive"))
      (node (ref "SV111") (pin "2") (pinfunction "2_2") (pintype "passive"))
      (node (ref "SV111") (pin "4") (pinfunction "4_4") (pintype "passive"))
      (node (ref "SV111") (pin "6") (pinfunction "6_6") (pintype "passive"))
      (node (ref "SV111") (pin "8") (pinfunction "8_8") (pintype "passive"))
    )
    (net (code "708") (name "Net-(SV112-Pad1)") (class "Default")
      (node (ref "SV112") (pin "1") (pinfunction "1_1") (pintype "passive"))
      (node (ref "SV112") (pin "3") (pinfunction "3_3") (pintype "passive"))
      (node (ref "SV112") (pin "5") (pinfunction "5_5") (pintype "passive"))
      (node (ref "SV112") (pin "7") (pinfunction "7_7") (pintype "passive"))
      (node (ref "SV112") (pin "9") (pinfunction "9_9") (pintype "passive"))
    )
    (net (code "709") (name "Net-(SV112-Pad10)") (class "Default")
      (node (ref "SV112") (pin "10") (pinfunction "10_10") (pintype "passive"))
      (node (ref "SV112") (pin "2") (pinfunction "2_2") (pintype "passive"))
      (node (ref "SV112") (pin "4") (pinfunction "4_4") (pintype "passive"))
      (node (ref "SV112") (pin "6") (pinfunction "6_6") (pintype "passive"))
      (node (ref "SV112") (pin "8") (pinfunction "8_8") (pintype "passive"))
    )
    (net (code "710") (name "Net-(SV113-Pad1)") (class "Default")
      (node (ref "SV113") (pin "1") (pinfunction "1_1") (pintype "passive"))
      (node (ref "SV113") (pin "3") (pinfunction "3_3") (pintype "passive"))
      (node (ref "SV113") (pin "5") (pinfunction "5_5") (pintype "passive"))
      (node (ref "SV113") (pin "7") (pinfunction "7_7") (pintype "passive"))
      (node (ref "SV113") (pin "9") (pinfunction "9_9") (pintype "passive"))
    )
    (net (code "711") (name "Net-(SV113-Pad10)") (class "Default")
      (node (ref "SV113") (pin "10") (pinfunction "10_10") (pintype "passive"))
      (node (ref "SV113") (pin "2") (pinfunction "2_2") (pintype "passive"))
      (node (ref "SV113") (pin "4") (pinfunction "4_4") (pintype "passive"))
      (node (ref "SV113") (pin "6") (pinfunction "6_6") (pintype "passive"))
      (node (ref "SV113") (pin "8") (pinfunction "8_8") (pintype "passive"))
    )
    (net (code "712") (name "Net-(SV114-Pad1)") (class "Default")
      (node (ref "SV114") (pin "1") (pinfunction "1_1") (pintype "passive"))
      (node (ref "SV114") (pin "3") (pinfunction "3_3") (pintype "passive"))
      (node (ref "SV114") (pin "5") (pinfunction "5_5") (pintype "passive"))
      (node (ref "SV114") (pin "7") (pinfunction "7_7") (pintype "passive"))
      (node (ref "SV114") (pin "9") (pinfunction "9_9") (pintype "passive"))
    )
    (net (code "713") (name "Net-(SV114-Pad10)") (class "Default")
      (node (ref "SV114") (pin "10") (pinfunction "10_10") (pintype "passive"))
      (node (ref "SV114") (pin "2") (pinfunction "2_2") (pintype "passive"))
      (node (ref "SV114") (pin "4") (pinfunction "4_4") (pintype "passive"))
      (node (ref "SV114") (pin "6") (pinfunction "6_6") (pintype "passive"))
      (node (ref "SV114") (pin "8") (pinfunction "8_8") (pintype "passive"))
    )
    (net (code "714") (name "Net-(SV115-Pad1)") (class "Default")
      (node (ref "SV115") (pin "1") (pinfunction "1_1") (pintype "passive"))
      (node (ref "SV115") (pin "3") (pinfunction "3_3") (pintype "passive"))
      (node (ref "SV115") (pin "5") (pinfunction "5_5") (pintype "passive"))
      (node (ref "SV115") (pin "7") (pinfunction "7_7") (pintype "passive"))
      (node (ref "SV115") (pin "9") (pinfunction "9_9") (pintype "passive"))
    )
    (net (code "715") (name "Net-(SV115-Pad10)") (class "Default")
      (node (ref "SV115") (pin "10") (pinfunction "10_10") (pintype "passive"))
      (node (ref "SV115") (pin "2") (pinfunction "2_2") (pintype "passive"))
      (node (ref "SV115") (pin "4") (pinfunction "4_4") (pintype "passive"))
      (node (ref "SV115") (pin "6") (pinfunction "6_6") (pintype "passive"))
      (node (ref "SV115") (pin "8") (pinfunction "8_8") (pintype "passive"))
    )
    (net (code "716") (name "Net-(SV116-Pad1)") (class "Default")
      (node (ref "SV116") (pin "1") (pinfunction "1_1") (pintype "passive"))
      (node (ref "SV116") (pin "3") (pinfunction "3_3") (pintype "passive"))
      (node (ref "SV116") (pin "5") (pinfunction "5_5") (pintype "passive"))
      (node (ref "SV116") (pin "7") (pinfunction "7_7") (pintype "passive"))
      (node (ref "SV116") (pin "9") (pinfunction "9_9") (pintype "passive"))
    )
    (net (code "717") (name "Net-(SV116-Pad10)") (class "Default")
      (node (ref "SV116") (pin "10") (pinfunction "10_10") (pintype "passive"))
      (node (ref "SV116") (pin "2") (pinfunction "2_2") (pintype "passive"))
      (node (ref "SV116") (pin "4") (pinfunction "4_4") (pintype "passive"))
      (node (ref "SV116") (pin "6") (pinfunction "6_6") (pintype "passive"))
      (node (ref "SV116") (pin "8") (pinfunction "8_8") (pintype "passive"))
    )
    (net (code "718") (name "Net-(SV117-Pad1)") (class "Default")
      (node (ref "SV117") (pin "1") (pinfunction "1_1") (pintype "passive"))
      (node (ref "SV117") (pin "3") (pinfunction "3_3") (pintype "passive"))
      (node (ref "SV117") (pin "5") (pinfunction "5_5") (pintype "passive"))
      (node (ref "SV117") (pin "7") (pinfunction "7_7") (pintype "passive"))
      (node (ref "SV117") (pin "9") (pinfunction "9_9") (pintype "passive"))
    )
    (net (code "719") (name "Net-(SV117-Pad10)") (class "Default")
      (node (ref "SV117") (pin "10") (pinfunction "10_10") (pintype "passive"))
      (node (ref "SV117") (pin "2") (pinfunction "2_2") (pintype "passive"))
      (node (ref "SV117") (pin "4") (pinfunction "4_4") (pintype "passive"))
      (node (ref "SV117") (pin "6") (pinfunction "6_6") (pintype "passive"))
      (node (ref "SV117") (pin "8") (pinfunction "8_8") (pintype "passive"))
    )
    (net (code "720") (name "Net-(SV118-Pad1)") (class "Default")
      (node (ref "SV118") (pin "1") (pinfunction "1_1") (pintype "passive"))
      (node (ref "SV118") (pin "3") (pinfunction "3_3") (pintype "passive"))
      (node (ref "SV118") (pin "5") (pinfunction "5_5") (pintype "passive"))
      (node (ref "SV118") (pin "7") (pinfunction "7_7") (pintype "passive"))
      (node (ref "SV118") (pin "9") (pinfunction "9_9") (pintype "passive"))
    )
    (net (code "721") (name "Net-(SV118-Pad10)") (class "Default")
      (node (ref "SV118") (pin "10") (pinfunction "10_10") (pintype "passive"))
      (node (ref "SV118") (pin "2") (pinfunction "2_2") (pintype "passive"))
      (node (ref "SV118") (pin "4") (pinfunction "4_4") (pintype "passive"))
      (node (ref "SV118") (pin "6") (pinfunction "6_6") (pintype "passive"))
      (node (ref "SV118") (pin "8") (pinfunction "8_8") (pintype "passive"))
    )
    (net (code "722") (name "Net-(SV119-Pad1)") (class "Default")
      (node (ref "SV119") (pin "1") (pinfunction "1_1") (pintype "passive"))
      (node (ref "SV119") (pin "3") (pinfunction "3_3") (pintype "passive"))
      (node (ref "SV119") (pin "5") (pinfunction "5_5") (pintype "passive"))
      (node (ref "SV119") (pin "7") (pinfunction "7_7") (pintype "passive"))
      (node (ref "SV119") (pin "9") (pinfunction "9_9") (pintype "passive"))
    )
    (net (code "723") (name "Net-(SV119-Pad10)") (class "Default")
      (node (ref "SV119") (pin "10") (pinfunction "10_10") (pintype "passive"))
      (node (ref "SV119") (pin "2") (pinfunction "2_2") (pintype "passive"))
      (node (ref "SV119") (pin "4") (pinfunction "4_4") (pintype "passive"))
      (node (ref "SV119") (pin "6") (pinfunction "6_6") (pintype "passive"))
      (node (ref "SV119") (pin "8") (pinfunction "8_8") (pintype "passive"))
    )
    (net (code "724") (name "Net-(SV120-Pad1)") (class "Default")
      (node (ref "SV120") (pin "1") (pinfunction "1_1") (pintype "passive"))
      (node (ref "SV120") (pin "3") (pinfunction "3_3") (pintype "passive"))
      (node (ref "SV120") (pin "5") (pinfunction "5_5") (pintype "passive"))
      (node (ref "SV120") (pin "7") (pinfunction "7_7") (pintype "passive"))
      (node (ref "SV120") (pin "9") (pinfunction "9_9") (pintype "passive"))
    )
    (net (code "725") (name "Net-(SV120-Pad10)") (class "Default")
      (node (ref "SV120") (pin "10") (pinfunction "10_10") (pintype "passive"))
      (node (ref "SV120") (pin "2") (pinfunction "2_2") (pintype "passive"))
      (node (ref "SV120") (pin "4") (pinfunction "4_4") (pintype "passive"))
      (node (ref "SV120") (pin "6") (pinfunction "6_6") (pintype "passive"))
      (node (ref "SV120") (pin "8") (pinfunction "8_8") (pintype "passive"))
    )
    (net (code "726") (name "Net-(SV121-Pad1)") (class "Default")
      (node (ref "SV121") (pin "1") (pinfunction "1_1") (pintype "passive"))
      (node (ref "SV121") (pin "3") (pinfunction "3_3") (pintype "passive"))
      (node (ref "SV121") (pin "5") (pinfunction "5_5") (pintype "passive"))
      (node (ref "SV121") (pin "7") (pinfunction "7_7") (pintype "passive"))
      (node (ref "SV121") (pin "9") (pinfunction "9_9") (pintype "passive"))
    )
    (net (code "727") (name "Net-(SV121-Pad10)") (class "Default")
      (node (ref "SV121") (pin "10") (pinfunction "10_10") (pintype "passive"))
      (node (ref "SV121") (pin "2") (pinfunction "2_2") (pintype "passive"))
      (node (ref "SV121") (pin "4") (pinfunction "4_4") (pintype "passive"))
      (node (ref "SV121") (pin "6") (pinfunction "6_6") (pintype "passive"))
      (node (ref "SV121") (pin "8") (pinfunction "8_8") (pintype "passive"))
    )
    (net (code "728") (name "Net-(SV122-Pad1)") (class "Default")
      (node (ref "SV122") (pin "1") (pinfunction "1_1") (pintype "passive"))
      (node (ref "SV122") (pin "3") (pinfunction "3_3") (pintype "passive"))
      (node (ref "SV122") (pin "5") (pinfunction "5_5") (pintype "passive"))
      (node (ref "SV122") (pin "7") (pinfunction "7_7") (pintype "passive"))
      (node (ref "SV122") (pin "9") (pinfunction "9_9") (pintype "passive"))
    )
    (net (code "729") (name "Net-(SV122-Pad10)") (class "Default")
      (node (ref "SV122") (pin "10") (pinfunction "10_10") (pintype "passive"))
      (node (ref "SV122") (pin "2") (pinfunction "2_2") (pintype "passive"))
      (node (ref "SV122") (pin "4") (pinfunction "4_4") (pintype "passive"))
      (node (ref "SV122") (pin "6") (pinfunction "6_6") (pintype "passive"))
      (node (ref "SV122") (pin "8") (pinfunction "8_8") (pintype "passive"))
    )
    (net (code "730") (name "Net-(SV123-Pad1)") (class "Default")
      (node (ref "SV123") (pin "1") (pinfunction "1_1") (pintype "passive"))
      (node (ref "SV123") (pin "3") (pinfunction "3_3") (pintype "passive"))
      (node (ref "SV123") (pin "5") (pinfunction "5_5") (pintype "passive"))
      (node (ref "SV123") (pin "7") (pinfunction "7_7") (pintype "passive"))
      (node (ref "SV123") (pin "9") (pinfunction "9_9") (pintype "passive"))
    )
    (net (code "731") (name "Net-(SV123-Pad10)") (class "Default")
      (node (ref "SV123") (pin "10") (pinfunction "10_10") (pintype "passive"))
      (node (ref "SV123") (pin "2") (pinfunction "2_2") (pintype "passive"))
      (node (ref "SV123") (pin "4") (pinfunction "4_4") (pintype "passive"))
      (node (ref "SV123") (pin "6") (pinfunction "6_6") (pintype "passive"))
      (node (ref "SV123") (pin "8") (pinfunction "8_8") (pintype "passive"))
    )
    (net (code "732") (name "Net-(SV124-Pad1)") (class "Default")
      (node (ref "SV124") (pin "1") (pinfunction "1_1") (pintype "passive"))
      (node (ref "SV124") (pin "3") (pinfunction "3_3") (pintype "passive"))
      (node (ref "SV124") (pin "5") (pinfunction "5_5") (pintype "passive"))
      (node (ref "SV124") (pin "7") (pinfunction "7_7") (pintype "passive"))
      (node (ref "SV124") (pin "9") (pinfunction "9_9") (pintype "passive"))
    )
    (net (code "733") (name "Net-(SV124-Pad10)") (class "Default")
      (node (ref "SV124") (pin "10") (pinfunction "10_10") (pintype "passive"))
      (node (ref "SV124") (pin "2") (pinfunction "2_2") (pintype "passive"))
      (node (ref "SV124") (pin "4") (pinfunction "4_4") (pintype "passive"))
      (node (ref "SV124") (pin "6") (pinfunction "6_6") (pintype "passive"))
      (node (ref "SV124") (pin "8") (pinfunction "8_8") (pintype "passive"))
    )
    (net (code "734") (name "Net-(SV126-Pad1)") (class "Default")
      (node (ref "SV126") (pin "1") (pinfunction "1_1") (pintype "passive"))
      (node (ref "SV126") (pin "3") (pinfunction "3_3") (pintype "passive"))
      (node (ref "SV126") (pin "5") (pinfunction "5_5") (pintype "passive"))
      (node (ref "SV126") (pin "7") (pinfunction "7_7") (pintype "passive"))
      (node (ref "SV126") (pin "9") (pinfunction "9_9") (pintype "passive"))
    )
    (net (code "735") (name "Net-(SV126-Pad10)") (class "Default")
      (node (ref "SV126") (pin "10") (pinfunction "10_10") (pintype "passive"))
      (node (ref "SV126") (pin "2") (pinfunction "2_2") (pintype "passive"))
      (node (ref "SV126") (pin "4") (pinfunction "4_4") (pintype "passive"))
      (node (ref "SV126") (pin "6") (pinfunction "6_6") (pintype "passive"))
      (node (ref "SV126") (pin "8") (pinfunction "8_8") (pintype "passive"))
    )
    (net (code "736") (name "Net-(SV128-Pad1)") (class "Default")
      (node (ref "SV128") (pin "1") (pinfunction "1_1") (pintype "passive"))
      (node (ref "SV128") (pin "3") (pinfunction "3_3") (pintype "passive"))
      (node (ref "SV128") (pin "5") (pinfunction "5_5") (pintype "passive"))
      (node (ref "SV128") (pin "7") (pinfunction "7_7") (pintype "passive"))
      (node (ref "SV128") (pin "9") (pinfunction "9_9") (pintype "passive"))
    )
    (net (code "737") (name "Net-(SV128-Pad10)") (class "Default")
      (node (ref "SV128") (pin "10") (pinfunction "10_10") (pintype "passive"))
      (node (ref "SV128") (pin "2") (pinfunction "2_2") (pintype "passive"))
      (node (ref "SV128") (pin "4") (pinfunction "4_4") (pintype "passive"))
      (node (ref "SV128") (pin "6") (pinfunction "6_6") (pintype "passive"))
      (node (ref "SV128") (pin "8") (pinfunction "8_8") (pintype "passive"))
    )
    (net (code "738") (name "Net-(SV130-Pad1)") (class "Default")
      (node (ref "SV130") (pin "1") (pinfunction "1_1") (pintype "passive"))
      (node (ref "SV130") (pin "3") (pinfunction "3_3") (pintype "passive"))
      (node (ref "SV130") (pin "5") (pinfunction "5_5") (pintype "passive"))
      (node (ref "SV130") (pin "7") (pinfunction "7_7") (pintype "passive"))
      (node (ref "SV130") (pin "9") (pinfunction "9_9") (pintype "passive"))
    )
    (net (code "739") (name "Net-(SV130-Pad10)") (class "Default")
      (node (ref "SV130") (pin "10") (pinfunction "10_10") (pintype "passive"))
      (node (ref "SV130") (pin "2") (pinfunction "2_2") (pintype "passive"))
      (node (ref "SV130") (pin "4") (pinfunction "4_4") (pintype "passive"))
      (node (ref "SV130") (pin "6") (pinfunction "6_6") (pintype "passive"))
      (node (ref "SV130") (pin "8") (pinfunction "8_8") (pintype "passive"))
    )
    (net (code "740") (name "Net-(SV132-Pad1)") (class "Default")
      (node (ref "SV132") (pin "1") (pinfunction "1_1") (pintype "passive"))
      (node (ref "SV132") (pin "3") (pinfunction "3_3") (pintype "passive"))
      (node (ref "SV132") (pin "5") (pinfunction "5_5") (pintype "passive"))
      (node (ref "SV132") (pin "7") (pinfunction "7_7") (pintype "passive"))
      (node (ref "SV132") (pin "9") (pinfunction "9_9") (pintype "passive"))
    )
    (net (code "741") (name "Net-(SV132-Pad10)") (class "Default")
      (node (ref "SV132") (pin "10") (pinfunction "10_10") (pintype "passive"))
      (node (ref "SV132") (pin "2") (pinfunction "2_2") (pintype "passive"))
      (node (ref "SV132") (pin "4") (pinfunction "4_4") (pintype "passive"))
      (node (ref "SV132") (pin "6") (pinfunction "6_6") (pintype "passive"))
      (node (ref "SV132") (pin "8") (pinfunction "8_8") (pintype "passive"))
    )
    (net (code "742") (name "Net-(SV133-Pad1)") (class "Default")
      (node (ref "SV133") (pin "1") (pinfunction "1_1") (pintype "passive"))
      (node (ref "SV133") (pin "3") (pinfunction "3_3") (pintype "passive"))
      (node (ref "SV133") (pin "5") (pinfunction "5_5") (pintype "passive"))
      (node (ref "SV133") (pin "7") (pinfunction "7_7") (pintype "passive"))
      (node (ref "SV133") (pin "9") (pinfunction "9_9") (pintype "passive"))
    )
    (net (code "743") (name "Net-(SV133-Pad10)") (class "Default")
      (node (ref "SV133") (pin "10") (pinfunction "10_10") (pintype "passive"))
      (node (ref "SV133") (pin "2") (pinfunction "2_2") (pintype "passive"))
      (node (ref "SV133") (pin "4") (pinfunction "4_4") (pintype "passive"))
      (node (ref "SV133") (pin "6") (pinfunction "6_6") (pintype "passive"))
      (node (ref "SV133") (pin "8") (pinfunction "8_8") (pintype "passive"))
    )
    (net (code "744") (name "Net-(SV134-Pad1)") (class "Default")
      (node (ref "SV134") (pin "1") (pinfunction "1_1") (pintype "passive"))
      (node (ref "SV134") (pin "3") (pinfunction "3_3") (pintype "passive"))
      (node (ref "SV134") (pin "5") (pinfunction "5_5") (pintype "passive"))
      (node (ref "SV134") (pin "7") (pinfunction "7_7") (pintype "passive"))
      (node (ref "SV134") (pin "9") (pinfunction "9_9") (pintype "passive"))
    )
    (net (code "745") (name "Net-(SV134-Pad10)") (class "Default")
      (node (ref "SV134") (pin "10") (pinfunction "10_10") (pintype "passive"))
      (node (ref "SV134") (pin "2") (pinfunction "2_2") (pintype "passive"))
      (node (ref "SV134") (pin "4") (pinfunction "4_4") (pintype "passive"))
      (node (ref "SV134") (pin "6") (pinfunction "6_6") (pintype "passive"))
      (node (ref "SV134") (pin "8") (pinfunction "8_8") (pintype "passive"))
    )
    (net (code "746") (name "Net-(SV135-Pad1)") (class "Default")
      (node (ref "SV135") (pin "1") (pinfunction "1_1") (pintype "passive"))
      (node (ref "SV135") (pin "3") (pinfunction "3_3") (pintype "passive"))
      (node (ref "SV135") (pin "5") (pinfunction "5_5") (pintype "passive"))
      (node (ref "SV135") (pin "7") (pinfunction "7_7") (pintype "passive"))
      (node (ref "SV135") (pin "9") (pinfunction "9_9") (pintype "passive"))
    )
    (net (code "747") (name "Net-(SV135-Pad10)") (class "Default")
      (node (ref "SV135") (pin "10") (pinfunction "10_10") (pintype "passive"))
      (node (ref "SV135") (pin "2") (pinfunction "2_2") (pintype "passive"))
      (node (ref "SV135") (pin "4") (pinfunction "4_4") (pintype "passive"))
      (node (ref "SV135") (pin "6") (pinfunction "6_6") (pintype "passive"))
      (node (ref "SV135") (pin "8") (pinfunction "8_8") (pintype "passive"))
    )
    (net (code "748") (name "Net-(SV136-Pad1)") (class "Default")
      (node (ref "SV136") (pin "1") (pinfunction "1_1") (pintype "passive"))
      (node (ref "SV136") (pin "3") (pinfunction "3_3") (pintype "passive"))
      (node (ref "SV136") (pin "5") (pinfunction "5_5") (pintype "passive"))
      (node (ref "SV136") (pin "7") (pinfunction "7_7") (pintype "passive"))
      (node (ref "SV136") (pin "9") (pinfunction "9_9") (pintype "passive"))
    )
    (net (code "749") (name "Net-(SV136-Pad10)") (class "Default")
      (node (ref "SV136") (pin "10") (pinfunction "10_10") (pintype "passive"))
      (node (ref "SV136") (pin "2") (pinfunction "2_2") (pintype "passive"))
      (node (ref "SV136") (pin "4") (pinfunction "4_4") (pintype "passive"))
      (node (ref "SV136") (pin "6") (pinfunction "6_6") (pintype "passive"))
      (node (ref "SV136") (pin "8") (pinfunction "8_8") (pintype "passive"))
    )
    (net (code "750") (name "Net-(SV137-Pad1)") (class "Default")
      (node (ref "SV137") (pin "1") (pinfunction "1_1") (pintype "passive"))
      (node (ref "SV137") (pin "3") (pinfunction "3_3") (pintype "passive"))
      (node (ref "SV137") (pin "5") (pinfunction "5_5") (pintype "passive"))
      (node (ref "SV137") (pin "7") (pinfunction "7_7") (pintype "passive"))
      (node (ref "SV137") (pin "9") (pinfunction "9_9") (pintype "passive"))
    )
    (net (code "751") (name "Net-(SV137-Pad10)") (class "Default")
      (node (ref "SV137") (pin "10") (pinfunction "10_10") (pintype "passive"))
      (node (ref "SV137") (pin "2") (pinfunction "2_2") (pintype "passive"))
      (node (ref "SV137") (pin "4") (pinfunction "4_4") (pintype "passive"))
      (node (ref "SV137") (pin "6") (pinfunction "6_6") (pintype "passive"))
      (node (ref "SV137") (pin "8") (pinfunction "8_8") (pintype "passive"))
    )
    (net (code "752") (name "Net-(SV138-Pad1)") (class "Default")
      (node (ref "SV138") (pin "1") (pinfunction "1_1") (pintype "passive"))
      (node (ref "SV138") (pin "3") (pinfunction "3_3") (pintype "passive"))
      (node (ref "SV138") (pin "5") (pinfunction "5_5") (pintype "passive"))
      (node (ref "SV138") (pin "7") (pinfunction "7_7") (pintype "passive"))
      (node (ref "SV138") (pin "9") (pinfunction "9_9") (pintype "passive"))
    )
    (net (code "753") (name "Net-(SV138-Pad10)") (class "Default")
      (node (ref "SV138") (pin "10") (pinfunction "10_10") (pintype "passive"))
      (node (ref "SV138") (pin "2") (pinfunction "2_2") (pintype "passive"))
      (node (ref "SV138") (pin "4") (pinfunction "4_4") (pintype "passive"))
      (node (ref "SV138") (pin "6") (pinfunction "6_6") (pintype "passive"))
      (node (ref "SV138") (pin "8") (pinfunction "8_8") (pintype "passive"))
    )
    (net (code "754") (name "Net-(SV139-Pad1)") (class "Default")
      (node (ref "SV139") (pin "1") (pinfunction "1_1") (pintype "passive"))
      (node (ref "SV139") (pin "3") (pinfunction "3_3") (pintype "passive"))
      (node (ref "SV139") (pin "5") (pinfunction "5_5") (pintype "passive"))
      (node (ref "SV139") (pin "7") (pinfunction "7_7") (pintype "passive"))
      (node (ref "SV139") (pin "9") (pinfunction "9_9") (pintype "passive"))
    )
    (net (code "755") (name "Net-(SV139-Pad10)") (class "Default")
      (node (ref "SV139") (pin "10") (pinfunction "10_10") (pintype "passive"))
      (node (ref "SV139") (pin "2") (pinfunction "2_2") (pintype "passive"))
      (node (ref "SV139") (pin "4") (pinfunction "4_4") (pintype "passive"))
      (node (ref "SV139") (pin "6") (pinfunction "6_6") (pintype "passive"))
      (node (ref "SV139") (pin "8") (pinfunction "8_8") (pintype "passive"))
    )
    (net (code "756") (name "Net-(SV140-Pad1)") (class "Default")
      (node (ref "SV140") (pin "1") (pinfunction "1_1") (pintype "passive"))
      (node (ref "SV140") (pin "3") (pinfunction "3_3") (pintype "passive"))
      (node (ref "SV140") (pin "5") (pinfunction "5_5") (pintype "passive"))
      (node (ref "SV140") (pin "7") (pinfunction "7_7") (pintype "passive"))
      (node (ref "SV140") (pin "9") (pinfunction "9_9") (pintype "passive"))
    )
    (net (code "757") (name "Net-(SV140-Pad10)") (class "Default")
      (node (ref "SV140") (pin "10") (pinfunction "10_10") (pintype "passive"))
      (node (ref "SV140") (pin "2") (pinfunction "2_2") (pintype "passive"))
      (node (ref "SV140") (pin "4") (pinfunction "4_4") (pintype "passive"))
      (node (ref "SV140") (pin "6") (pinfunction "6_6") (pintype "passive"))
      (node (ref "SV140") (pin "8") (pinfunction "8_8") (pintype "passive"))
    )
    (net (code "758") (name "Net-(SV141-Pad1)") (class "Default")
      (node (ref "SV141") (pin "1") (pinfunction "1_1") (pintype "passive"))
      (node (ref "SV141") (pin "3") (pinfunction "3_3") (pintype "passive"))
      (node (ref "SV141") (pin "5") (pinfunction "5_5") (pintype "passive"))
      (node (ref "SV141") (pin "7") (pinfunction "7_7") (pintype "passive"))
      (node (ref "SV141") (pin "9") (pinfunction "9_9") (pintype "passive"))
    )
    (net (code "759") (name "Net-(SV141-Pad10)") (class "Default")
      (node (ref "SV141") (pin "10") (pinfunction "10_10") (pintype "passive"))
      (node (ref "SV141") (pin "2") (pinfunction "2_2") (pintype "passive"))
      (node (ref "SV141") (pin "4") (pinfunction "4_4") (pintype "passive"))
      (node (ref "SV141") (pin "6") (pinfunction "6_6") (pintype "passive"))
      (node (ref "SV141") (pin "8") (pinfunction "8_8") (pintype "passive"))
    )
    (net (code "760") (name "Net-(SV142-Pad1)") (class "Default")
      (node (ref "SV142") (pin "1") (pinfunction "1_1") (pintype "passive"))
      (node (ref "SV142") (pin "3") (pinfunction "3_3") (pintype "passive"))
      (node (ref "SV142") (pin "5") (pinfunction "5_5") (pintype "passive"))
      (node (ref "SV142") (pin "7") (pinfunction "7_7") (pintype "passive"))
      (node (ref "SV142") (pin "9") (pinfunction "9_9") (pintype "passive"))
    )
    (net (code "761") (name "Net-(SV142-Pad10)") (class "Default")
      (node (ref "SV142") (pin "10") (pinfunction "10_10") (pintype "passive"))
      (node (ref "SV142") (pin "2") (pinfunction "2_2") (pintype "passive"))
      (node (ref "SV142") (pin "4") (pinfunction "4_4") (pintype "passive"))
      (node (ref "SV142") (pin "6") (pinfunction "6_6") (pintype "passive"))
      (node (ref "SV142") (pin "8") (pinfunction "8_8") (pintype "passive"))
    )
    (net (code "762") (name "Net-(SV143-Pad1)") (class "Default")
      (node (ref "SV143") (pin "1") (pinfunction "1_1") (pintype "passive"))
      (node (ref "SV143") (pin "3") (pinfunction "3_3") (pintype "passive"))
      (node (ref "SV143") (pin "5") (pinfunction "5_5") (pintype "passive"))
      (node (ref "SV143") (pin "7") (pinfunction "7_7") (pintype "passive"))
      (node (ref "SV143") (pin "9") (pinfunction "9_9") (pintype "passive"))
    )
    (net (code "763") (name "Net-(SV143-Pad10)") (class "Default")
      (node (ref "SV143") (pin "10") (pinfunction "10_10") (pintype "passive"))
      (node (ref "SV143") (pin "2") (pinfunction "2_2") (pintype "passive"))
      (node (ref "SV143") (pin "4") (pinfunction "4_4") (pintype "passive"))
      (node (ref "SV143") (pin "6") (pinfunction "6_6") (pintype "passive"))
      (node (ref "SV143") (pin "8") (pinfunction "8_8") (pintype "passive"))
    )
    (net (code "764") (name "Net-(SV144-Pad1)") (class "Default")
      (node (ref "SV144") (pin "1") (pinfunction "1_1") (pintype "passive"))
      (node (ref "SV144") (pin "3") (pinfunction "3_3") (pintype "passive"))
      (node (ref "SV144") (pin "5") (pinfunction "5_5") (pintype "passive"))
      (node (ref "SV144") (pin "7") (pinfunction "7_7") (pintype "passive"))
      (node (ref "SV144") (pin "9") (pinfunction "9_9") (pintype "passive"))
    )
    (net (code "765") (name "Net-(SV144-Pad10)") (class "Default")
      (node (ref "SV144") (pin "10") (pinfunction "10_10") (pintype "passive"))
      (node (ref "SV144") (pin "2") (pinfunction "2_2") (pintype "passive"))
      (node (ref "SV144") (pin "4") (pinfunction "4_4") (pintype "passive"))
      (node (ref "SV144") (pin "6") (pinfunction "6_6") (pintype "passive"))
      (node (ref "SV144") (pin "8") (pinfunction "8_8") (pintype "passive"))
    )
    (net (code "766") (name "Net-(SV145-Pad1)") (class "Default")
      (node (ref "SV145") (pin "1") (pinfunction "1_1") (pintype "passive"))
      (node (ref "SV145") (pin "3") (pinfunction "3_3") (pintype "passive"))
      (node (ref "SV145") (pin "5") (pinfunction "5_5") (pintype "passive"))
      (node (ref "SV145") (pin "7") (pinfunction "7_7") (pintype "passive"))
      (node (ref "SV145") (pin "9") (pinfunction "9_9") (pintype "passive"))
    )
    (net (code "767") (name "Net-(SV145-Pad10)") (class "Default")
      (node (ref "SV145") (pin "10") (pinfunction "10_10") (pintype "passive"))
      (node (ref "SV145") (pin "2") (pinfunction "2_2") (pintype "passive"))
      (node (ref "SV145") (pin "4") (pinfunction "4_4") (pintype "passive"))
      (node (ref "SV145") (pin "6") (pinfunction "6_6") (pintype "passive"))
      (node (ref "SV145") (pin "8") (pinfunction "8_8") (pintype "passive"))
    )
    (net (code "768") (name "Net-(SV146-Pad1)") (class "Default")
      (node (ref "SV146") (pin "1") (pinfunction "1_1") (pintype "passive"))
      (node (ref "SV146") (pin "3") (pinfunction "3_3") (pintype "passive"))
      (node (ref "SV146") (pin "5") (pinfunction "5_5") (pintype "passive"))
      (node (ref "SV146") (pin "7") (pinfunction "7_7") (pintype "passive"))
      (node (ref "SV146") (pin "9") (pinfunction "9_9") (pintype "passive"))
    )
    (net (code "769") (name "Net-(SV146-Pad10)") (class "Default")
      (node (ref "SV146") (pin "10") (pinfunction "10_10") (pintype "passive"))
      (node (ref "SV146") (pin "2") (pinfunction "2_2") (pintype "passive"))
      (node (ref "SV146") (pin "4") (pinfunction "4_4") (pintype "passive"))
      (node (ref "SV146") (pin "6") (pinfunction "6_6") (pintype "passive"))
      (node (ref "SV146") (pin "8") (pinfunction "8_8") (pintype "passive"))
    )
    (net (code "770") (name "Net-(SV147-Pad1)") (class "Default")
      (node (ref "SV147") (pin "1") (pinfunction "1_1") (pintype "passive"))
      (node (ref "SV147") (pin "3") (pinfunction "3_3") (pintype "passive"))
      (node (ref "SV147") (pin "5") (pinfunction "5_5") (pintype "passive"))
      (node (ref "SV147") (pin "7") (pinfunction "7_7") (pintype "passive"))
      (node (ref "SV147") (pin "9") (pinfunction "9_9") (pintype "passive"))
    )
    (net (code "771") (name "Net-(SV147-Pad10)") (class "Default")
      (node (ref "SV147") (pin "10") (pinfunction "10_10") (pintype "passive"))
      (node (ref "SV147") (pin "2") (pinfunction "2_2") (pintype "passive"))
      (node (ref "SV147") (pin "4") (pinfunction "4_4") (pintype "passive"))
      (node (ref "SV147") (pin "6") (pinfunction "6_6") (pintype "passive"))
      (node (ref "SV147") (pin "8") (pinfunction "8_8") (pintype "passive"))
    )
    (net (code "772") (name "Net-(SV148-Pad1)") (class "Default")
      (node (ref "SV148") (pin "1") (pinfunction "1_1") (pintype "passive"))
      (node (ref "SV148") (pin "3") (pinfunction "3_3") (pintype "passive"))
      (node (ref "SV148") (pin "5") (pinfunction "5_5") (pintype "passive"))
      (node (ref "SV148") (pin "7") (pinfunction "7_7") (pintype "passive"))
      (node (ref "SV148") (pin "9") (pinfunction "9_9") (pintype "passive"))
    )
    (net (code "773") (name "Net-(SV148-Pad10)") (class "Default")
      (node (ref "SV148") (pin "10") (pinfunction "10_10") (pintype "passive"))
      (node (ref "SV148") (pin "2") (pinfunction "2_2") (pintype "passive"))
      (node (ref "SV148") (pin "4") (pinfunction "4_4") (pintype "passive"))
      (node (ref "SV148") (pin "6") (pinfunction "6_6") (pintype "passive"))
      (node (ref "SV148") (pin "8") (pinfunction "8_8") (pintype "passive"))
    )
    (net (code "774") (name "Net-(SV149-Pad1)") (class "Default")
      (node (ref "SV149") (pin "1") (pinfunction "1_1") (pintype "passive"))
      (node (ref "SV149") (pin "3") (pinfunction "3_3") (pintype "passive"))
      (node (ref "SV149") (pin "5") (pinfunction "5_5") (pintype "passive"))
      (node (ref "SV149") (pin "7") (pinfunction "7_7") (pintype "passive"))
      (node (ref "SV149") (pin "9") (pinfunction "9_9") (pintype "passive"))
    )
    (net (code "775") (name "Net-(SV149-Pad10)") (class "Default")
      (node (ref "SV149") (pin "10") (pinfunction "10_10") (pintype "passive"))
      (node (ref "SV149") (pin "2") (pinfunction "2_2") (pintype "passive"))
      (node (ref "SV149") (pin "4") (pinfunction "4_4") (pintype "passive"))
      (node (ref "SV149") (pin "6") (pinfunction "6_6") (pintype "passive"))
      (node (ref "SV149") (pin "8") (pinfunction "8_8") (pintype "passive"))
    )
    (net (code "776") (name "Net-(SV150-Pad1)") (class "Default")
      (node (ref "SV150") (pin "1") (pinfunction "1_1") (pintype "passive"))
      (node (ref "SV150") (pin "3") (pinfunction "3_3") (pintype "passive"))
      (node (ref "SV150") (pin "5") (pinfunction "5_5") (pintype "passive"))
      (node (ref "SV150") (pin "7") (pinfunction "7_7") (pintype "passive"))
      (node (ref "SV150") (pin "9") (pinfunction "9_9") (pintype "passive"))
    )
    (net (code "777") (name "Net-(SV150-Pad10)") (class "Default")
      (node (ref "SV150") (pin "10") (pinfunction "10_10") (pintype "passive"))
      (node (ref "SV150") (pin "2") (pinfunction "2_2") (pintype "passive"))
      (node (ref "SV150") (pin "4") (pinfunction "4_4") (pintype "passive"))
      (node (ref "SV150") (pin "6") (pinfunction "6_6") (pintype "passive"))
      (node (ref "SV150") (pin "8") (pinfunction "8_8") (pintype "passive"))
    )
    (net (code "778") (name "Net-(SV151-Pad1)") (class "Default")
      (node (ref "SV151") (pin "1") (pinfunction "1_1") (pintype "passive"))
      (node (ref "SV151") (pin "3") (pinfunction "3_3") (pintype "passive"))
      (node (ref "SV151") (pin "5") (pinfunction "5_5") (pintype "passive"))
      (node (ref "SV151") (pin "7") (pinfunction "7_7") (pintype "passive"))
      (node (ref "SV151") (pin "9") (pinfunction "9_9") (pintype "passive"))
    )
    (net (code "779") (name "Net-(SV151-Pad10)") (class "Default")
      (node (ref "SV151") (pin "10") (pinfunction "10_10") (pintype "passive"))
      (node (ref "SV151") (pin "2") (pinfunction "2_2") (pintype "passive"))
      (node (ref "SV151") (pin "4") (pinfunction "4_4") (pintype "passive"))
      (node (ref "SV151") (pin "6") (pinfunction "6_6") (pintype "passive"))
      (node (ref "SV151") (pin "8") (pinfunction "8_8") (pintype "passive"))
    )
    (net (code "780") (name "Net-(SV152-Pad1)") (class "Default")
      (node (ref "SV152") (pin "1") (pinfunction "1_1") (pintype "passive"))
      (node (ref "SV152") (pin "3") (pinfunction "3_3") (pintype "passive"))
      (node (ref "SV152") (pin "5") (pinfunction "5_5") (pintype "passive"))
      (node (ref "SV152") (pin "7") (pinfunction "7_7") (pintype "passive"))
      (node (ref "SV152") (pin "9") (pinfunction "9_9") (pintype "passive"))
    )
    (net (code "781") (name "Net-(SV152-Pad10)") (class "Default")
      (node (ref "SV152") (pin "10") (pinfunction "10_10") (pintype "passive"))
      (node (ref "SV152") (pin "2") (pinfunction "2_2") (pintype "passive"))
      (node (ref "SV152") (pin "4") (pinfunction "4_4") (pintype "passive"))
      (node (ref "SV152") (pin "6") (pinfunction "6_6") (pintype "passive"))
      (node (ref "SV152") (pin "8") (pinfunction "8_8") (pintype "passive"))
    )
    (net (code "782") (name "Net-(SV153-Pad1)") (class "Default")
      (node (ref "SV153") (pin "1") (pinfunction "1_1") (pintype "passive"))
      (node (ref "SV153") (pin "3") (pinfunction "3_3") (pintype "passive"))
      (node (ref "SV153") (pin "5") (pinfunction "5_5") (pintype "passive"))
      (node (ref "SV153") (pin "7") (pinfunction "7_7") (pintype "passive"))
      (node (ref "SV153") (pin "9") (pinfunction "9_9") (pintype "passive"))
    )
    (net (code "783") (name "Net-(SV153-Pad10)") (class "Default")
      (node (ref "SV153") (pin "10") (pinfunction "10_10") (pintype "passive"))
      (node (ref "SV153") (pin "2") (pinfunction "2_2") (pintype "passive"))
      (node (ref "SV153") (pin "4") (pinfunction "4_4") (pintype "passive"))
      (node (ref "SV153") (pin "6") (pinfunction "6_6") (pintype "passive"))
      (node (ref "SV153") (pin "8") (pinfunction "8_8") (pintype "passive"))
    )
    (net (code "784") (name "Net-(SV154-Pad1)") (class "Default")
      (node (ref "SV154") (pin "1") (pinfunction "1_1") (pintype "passive"))
      (node (ref "SV154") (pin "3") (pinfunction "3_3") (pintype "passive"))
      (node (ref "SV154") (pin "5") (pinfunction "5_5") (pintype "passive"))
      (node (ref "SV154") (pin "7") (pinfunction "7_7") (pintype "passive"))
      (node (ref "SV154") (pin "9") (pinfunction "9_9") (pintype "passive"))
    )
    (net (code "785") (name "Net-(SV154-Pad10)") (class "Default")
      (node (ref "SV154") (pin "10") (pinfunction "10_10") (pintype "passive"))
      (node (ref "SV154") (pin "2") (pinfunction "2_2") (pintype "passive"))
      (node (ref "SV154") (pin "4") (pinfunction "4_4") (pintype "passive"))
      (node (ref "SV154") (pin "6") (pinfunction "6_6") (pintype "passive"))
      (node (ref "SV154") (pin "8") (pinfunction "8_8") (pintype "passive"))
    )
    (net (code "786") (name "Net-(SV155-Pad1)") (class "Default")
      (node (ref "SV155") (pin "1") (pinfunction "1_1") (pintype "passive"))
      (node (ref "SV155") (pin "3") (pinfunction "3_3") (pintype "passive"))
      (node (ref "SV155") (pin "5") (pinfunction "5_5") (pintype "passive"))
      (node (ref "SV155") (pin "7") (pinfunction "7_7") (pintype "passive"))
      (node (ref "SV155") (pin "9") (pinfunction "9_9") (pintype "passive"))
    )
    (net (code "787") (name "Net-(SV155-Pad10)") (class "Default")
      (node (ref "SV155") (pin "10") (pinfunction "10_10") (pintype "passive"))
      (node (ref "SV155") (pin "2") (pinfunction "2_2") (pintype "passive"))
      (node (ref "SV155") (pin "4") (pinfunction "4_4") (pintype "passive"))
      (node (ref "SV155") (pin "6") (pinfunction "6_6") (pintype "passive"))
      (node (ref "SV155") (pin "8") (pinfunction "8_8") (pintype "passive"))
    )
    (net (code "788") (name "Net-(SV156-Pad1)") (class "Default")
      (node (ref "SV156") (pin "1") (pinfunction "1_1") (pintype "passive"))
      (node (ref "SV156") (pin "3") (pinfunction "3_3") (pintype "passive"))
      (node (ref "SV156") (pin "5") (pinfunction "5_5") (pintype "passive"))
      (node (ref "SV156") (pin "7") (pinfunction "7_7") (pintype "passive"))
      (node (ref "SV156") (pin "9") (pinfunction "9_9") (pintype "passive"))
    )
    (net (code "789") (name "Net-(SV156-Pad10)") (class "Default")
      (node (ref "SV156") (pin "10") (pinfunction "10_10") (pintype "passive"))
      (node (ref "SV156") (pin "2") (pinfunction "2_2") (pintype "passive"))
      (node (ref "SV156") (pin "4") (pinfunction "4_4") (pintype "passive"))
      (node (ref "SV156") (pin "6") (pinfunction "6_6") (pintype "passive"))
      (node (ref "SV156") (pin "8") (pinfunction "8_8") (pintype "passive"))
    )
    (net (code "790") (name "Net-(SV157-Pad1)") (class "Default")
      (node (ref "SV157") (pin "1") (pinfunction "1_1") (pintype "passive"))
      (node (ref "SV157") (pin "3") (pinfunction "3_3") (pintype "passive"))
      (node (ref "SV157") (pin "5") (pinfunction "5_5") (pintype "passive"))
      (node (ref "SV157") (pin "7") (pinfunction "7_7") (pintype "passive"))
      (node (ref "SV157") (pin "9") (pinfunction "9_9") (pintype "passive"))
    )
    (net (code "791") (name "Net-(SV157-Pad10)") (class "Default")
      (node (ref "SV157") (pin "10") (pinfunction "10_10") (pintype "passive"))
      (node (ref "SV157") (pin "2") (pinfunction "2_2") (pintype "passive"))
      (node (ref "SV157") (pin "4") (pinfunction "4_4") (pintype "passive"))
      (node (ref "SV157") (pin "6") (pinfunction "6_6") (pintype "passive"))
      (node (ref "SV157") (pin "8") (pinfunction "8_8") (pintype "passive"))
    )
    (net (code "792") (name "Net-(SV158-Pad1)") (class "Default")
      (node (ref "SV158") (pin "1") (pinfunction "1_1") (pintype "passive"))
      (node (ref "SV158") (pin "3") (pinfunction "3_3") (pintype "passive"))
      (node (ref "SV158") (pin "5") (pinfunction "5_5") (pintype "passive"))
      (node (ref "SV158") (pin "7") (pinfunction "7_7") (pintype "passive"))
      (node (ref "SV158") (pin "9") (pinfunction "9_9") (pintype "passive"))
    )
    (net (code "793") (name "Net-(SV158-Pad10)") (class "Default")
      (node (ref "SV158") (pin "10") (pinfunction "10_10") (pintype "passive"))
      (node (ref "SV158") (pin "2") (pinfunction "2_2") (pintype "passive"))
      (node (ref "SV158") (pin "4") (pinfunction "4_4") (pintype "passive"))
      (node (ref "SV158") (pin "6") (pinfunction "6_6") (pintype "passive"))
      (node (ref "SV158") (pin "8") (pinfunction "8_8") (pintype "passive"))
    )
    (net (code "794") (name "Net-(SV159-Pad1)") (class "Default")
      (node (ref "SV159") (pin "1") (pinfunction "1_1") (pintype "passive"))
      (node (ref "SV159") (pin "3") (pinfunction "3_3") (pintype "passive"))
      (node (ref "SV159") (pin "5") (pinfunction "5_5") (pintype "passive"))
      (node (ref "SV159") (pin "7") (pinfunction "7_7") (pintype "passive"))
      (node (ref "SV159") (pin "9") (pinfunction "9_9") (pintype "passive"))
    )
    (net (code "795") (name "Net-(SV159-Pad10)") (class "Default")
      (node (ref "SV159") (pin "10") (pinfunction "10_10") (pintype "passive"))
      (node (ref "SV159") (pin "2") (pinfunction "2_2") (pintype "passive"))
      (node (ref "SV159") (pin "4") (pinfunction "4_4") (pintype "passive"))
      (node (ref "SV159") (pin "6") (pinfunction "6_6") (pintype "passive"))
      (node (ref "SV159") (pin "8") (pinfunction "8_8") (pintype "passive"))
    )
    (net (code "796") (name "Net-(SV160-Pad1)") (class "Default")
      (node (ref "SV160") (pin "1") (pinfunction "1_1") (pintype "passive"))
      (node (ref "SV160") (pin "3") (pinfunction "3_3") (pintype "passive"))
      (node (ref "SV160") (pin "5") (pinfunction "5_5") (pintype "passive"))
      (node (ref "SV160") (pin "7") (pinfunction "7_7") (pintype "passive"))
      (node (ref "SV160") (pin "9") (pinfunction "9_9") (pintype "passive"))
    )
    (net (code "797") (name "Net-(SV160-Pad10)") (class "Default")
      (node (ref "SV160") (pin "10") (pinfunction "10_10") (pintype "passive"))
      (node (ref "SV160") (pin "2") (pinfunction "2_2") (pintype "passive"))
      (node (ref "SV160") (pin "4") (pinfunction "4_4") (pintype "passive"))
      (node (ref "SV160") (pin "6") (pinfunction "6_6") (pintype "passive"))
      (node (ref "SV160") (pin "8") (pinfunction "8_8") (pintype "passive"))
    )
    (net (code "798") (name "Net-(SV161-Pad1)") (class "Default")
      (node (ref "SV161") (pin "1") (pinfunction "1_1") (pintype "passive"))
      (node (ref "SV161") (pin "3") (pinfunction "3_3") (pintype "passive"))
      (node (ref "SV161") (pin "5") (pinfunction "5_5") (pintype "passive"))
      (node (ref "SV161") (pin "7") (pinfunction "7_7") (pintype "passive"))
      (node (ref "SV161") (pin "9") (pinfunction "9_9") (pintype "passive"))
    )
    (net (code "799") (name "Net-(SV161-Pad10)") (class "Default")
      (node (ref "SV161") (pin "10") (pinfunction "10_10") (pintype "passive"))
      (node (ref "SV161") (pin "2") (pinfunction "2_2") (pintype "passive"))
      (node (ref "SV161") (pin "4") (pinfunction "4_4") (pintype "passive"))
      (node (ref "SV161") (pin "6") (pinfunction "6_6") (pintype "passive"))
      (node (ref "SV161") (pin "8") (pinfunction "8_8") (pintype "passive"))
    )
    (net (code "800") (name "Net-(SV162-Pad1)") (class "Default")
      (node (ref "SV162") (pin "1") (pinfunction "1_1") (pintype "passive"))
      (node (ref "SV162") (pin "3") (pinfunction "3_3") (pintype "passive"))
      (node (ref "SV162") (pin "5") (pinfunction "5_5") (pintype "passive"))
      (node (ref "SV162") (pin "7") (pinfunction "7_7") (pintype "passive"))
      (node (ref "SV162") (pin "9") (pinfunction "9_9") (pintype "passive"))
    )
    (net (code "801") (name "Net-(SV162-Pad10)") (class "Default")
      (node (ref "SV162") (pin "10") (pinfunction "10_10") (pintype "passive"))
      (node (ref "SV162") (pin "2") (pinfunction "2_2") (pintype "passive"))
      (node (ref "SV162") (pin "4") (pinfunction "4_4") (pintype "passive"))
      (node (ref "SV162") (pin "6") (pinfunction "6_6") (pintype "passive"))
      (node (ref "SV162") (pin "8") (pinfunction "8_8") (pintype "passive"))
    )
    (net (code "802") (name "Net-(SV163-Pad1)") (class "Default")
      (node (ref "SV163") (pin "1") (pinfunction "1_1") (pintype "passive"))
      (node (ref "SV163") (pin "3") (pinfunction "3_3") (pintype "passive"))
      (node (ref "SV163") (pin "5") (pinfunction "5_5") (pintype "passive"))
      (node (ref "SV163") (pin "7") (pinfunction "7_7") (pintype "passive"))
      (node (ref "SV163") (pin "9") (pinfunction "9_9") (pintype "passive"))
    )
    (net (code "803") (name "Net-(SV163-Pad10)") (class "Default")
      (node (ref "SV163") (pin "10") (pinfunction "10_10") (pintype "passive"))
      (node (ref "SV163") (pin "2") (pinfunction "2_2") (pintype "passive"))
      (node (ref "SV163") (pin "4") (pinfunction "4_4") (pintype "passive"))
      (node (ref "SV163") (pin "6") (pinfunction "6_6") (pintype "passive"))
      (node (ref "SV163") (pin "8") (pinfunction "8_8") (pintype "passive"))
    )
    (net (code "804") (name "Net-(SV164-Pad1)") (class "Default")
      (node (ref "SV164") (pin "1") (pinfunction "1_1") (pintype "passive"))
      (node (ref "SV164") (pin "3") (pinfunction "3_3") (pintype "passive"))
      (node (ref "SV164") (pin "5") (pinfunction "5_5") (pintype "passive"))
      (node (ref "SV164") (pin "7") (pinfunction "7_7") (pintype "passive"))
      (node (ref "SV164") (pin "9") (pinfunction "9_9") (pintype "passive"))
    )
    (net (code "805") (name "Net-(SV164-Pad10)") (class "Default")
      (node (ref "SV164") (pin "10") (pinfunction "10_10") (pintype "passive"))
      (node (ref "SV164") (pin "2") (pinfunction "2_2") (pintype "passive"))
      (node (ref "SV164") (pin "4") (pinfunction "4_4") (pintype "passive"))
      (node (ref "SV164") (pin "6") (pinfunction "6_6") (pintype "passive"))
      (node (ref "SV164") (pin "8") (pinfunction "8_8") (pintype "passive"))
    )
    (net (code "806") (name "Net-(SV165-Pad1)") (class "Default")
      (node (ref "SV165") (pin "1") (pinfunction "1_1") (pintype "passive"))
      (node (ref "SV165") (pin "3") (pinfunction "3_3") (pintype "passive"))
      (node (ref "SV165") (pin "5") (pinfunction "5_5") (pintype "passive"))
      (node (ref "SV165") (pin "7") (pinfunction "7_7") (pintype "passive"))
      (node (ref "SV165") (pin "9") (pinfunction "9_9") (pintype "passive"))
    )
    (net (code "807") (name "Net-(SV165-Pad10)") (class "Default")
      (node (ref "SV165") (pin "10") (pinfunction "10_10") (pintype "passive"))
      (node (ref "SV165") (pin "2") (pinfunction "2_2") (pintype "passive"))
      (node (ref "SV165") (pin "4") (pinfunction "4_4") (pintype "passive"))
      (node (ref "SV165") (pin "6") (pinfunction "6_6") (pintype "passive"))
      (node (ref "SV165") (pin "8") (pinfunction "8_8") (pintype "passive"))
    )
    (net (code "808") (name "Net-(SV166-Pad1)") (class "Default")
      (node (ref "SV166") (pin "1") (pinfunction "1_1") (pintype "passive"))
      (node (ref "SV166") (pin "3") (pinfunction "3_3") (pintype "passive"))
      (node (ref "SV166") (pin "5") (pinfunction "5_5") (pintype "passive"))
      (node (ref "SV166") (pin "7") (pinfunction "7_7") (pintype "passive"))
      (node (ref "SV166") (pin "9") (pinfunction "9_9") (pintype "passive"))
    )
    (net (code "809") (name "Net-(SV166-Pad10)") (class "Default")
      (node (ref "SV166") (pin "10") (pinfunction "10_10") (pintype "passive"))
      (node (ref "SV166") (pin "2") (pinfunction "2_2") (pintype "passive"))
      (node (ref "SV166") (pin "4") (pinfunction "4_4") (pintype "passive"))
      (node (ref "SV166") (pin "6") (pinfunction "6_6") (pintype "passive"))
      (node (ref "SV166") (pin "8") (pinfunction "8_8") (pintype "passive"))
    )
    (net (code "810") (name "Net-(SV167-Pad1)") (class "Default")
      (node (ref "SV167") (pin "1") (pinfunction "1_1") (pintype "passive"))
      (node (ref "SV167") (pin "3") (pinfunction "3_3") (pintype "passive"))
      (node (ref "SV167") (pin "5") (pinfunction "5_5") (pintype "passive"))
      (node (ref "SV167") (pin "7") (pinfunction "7_7") (pintype "passive"))
      (node (ref "SV167") (pin "9") (pinfunction "9_9") (pintype "passive"))
    )
    (net (code "811") (name "Net-(SV167-Pad10)") (class "Default")
      (node (ref "SV167") (pin "10") (pinfunction "10_10") (pintype "passive"))
      (node (ref "SV167") (pin "2") (pinfunction "2_2") (pintype "passive"))
      (node (ref "SV167") (pin "4") (pinfunction "4_4") (pintype "passive"))
      (node (ref "SV167") (pin "6") (pinfunction "6_6") (pintype "passive"))
      (node (ref "SV167") (pin "8") (pinfunction "8_8") (pintype "passive"))
    )
    (net (code "812") (name "Net-(SV168-Pad1)") (class "Default")
      (node (ref "SV168") (pin "1") (pinfunction "1_1") (pintype "passive"))
      (node (ref "SV168") (pin "3") (pinfunction "3_3") (pintype "passive"))
      (node (ref "SV168") (pin "5") (pinfunction "5_5") (pintype "passive"))
      (node (ref "SV168") (pin "7") (pinfunction "7_7") (pintype "passive"))
      (node (ref "SV168") (pin "9") (pinfunction "9_9") (pintype "passive"))
    )
    (net (code "813") (name "Net-(SV168-Pad10)") (class "Default")
      (node (ref "SV168") (pin "10") (pinfunction "10_10") (pintype "passive"))
      (node (ref "SV168") (pin "2") (pinfunction "2_2") (pintype "passive"))
      (node (ref "SV168") (pin "4") (pinfunction "4_4") (pintype "passive"))
      (node (ref "SV168") (pin "6") (pinfunction "6_6") (pintype "passive"))
      (node (ref "SV168") (pin "8") (pinfunction "8_8") (pintype "passive"))
    )
    (net (code "814") (name "Net-(SV169-Pad1)") (class "Default")
      (node (ref "SV169") (pin "1") (pinfunction "1_1") (pintype "passive"))
      (node (ref "SV169") (pin "3") (pinfunction "3_3") (pintype "passive"))
      (node (ref "SV169") (pin "5") (pinfunction "5_5") (pintype "passive"))
      (node (ref "SV169") (pin "7") (pinfunction "7_7") (pintype "passive"))
      (node (ref "SV169") (pin "9") (pinfunction "9_9") (pintype "passive"))
    )
    (net (code "815") (name "Net-(SV169-Pad10)") (class "Default")
      (node (ref "SV169") (pin "10") (pinfunction "10_10") (pintype "passive"))
      (node (ref "SV169") (pin "2") (pinfunction "2_2") (pintype "passive"))
      (node (ref "SV169") (pin "4") (pinfunction "4_4") (pintype "passive"))
      (node (ref "SV169") (pin "6") (pinfunction "6_6") (pintype "passive"))
      (node (ref "SV169") (pin "8") (pinfunction "8_8") (pintype "passive"))
    )
    (net (code "816") (name "Net-(SV170-Pad1)") (class "Default")
      (node (ref "SV170") (pin "1") (pinfunction "1_1") (pintype "passive"))
      (node (ref "SV170") (pin "3") (pinfunction "3_3") (pintype "passive"))
      (node (ref "SV170") (pin "5") (pinfunction "5_5") (pintype "passive"))
      (node (ref "SV170") (pin "7") (pinfunction "7_7") (pintype "passive"))
      (node (ref "SV170") (pin "9") (pinfunction "9_9") (pintype "passive"))
    )
    (net (code "817") (name "Net-(SV170-Pad10)") (class "Default")
      (node (ref "SV170") (pin "10") (pinfunction "10_10") (pintype "passive"))
      (node (ref "SV170") (pin "2") (pinfunction "2_2") (pintype "passive"))
      (node (ref "SV170") (pin "4") (pinfunction "4_4") (pintype "passive"))
      (node (ref "SV170") (pin "6") (pinfunction "6_6") (pintype "passive"))
      (node (ref "SV170") (pin "8") (pinfunction "8_8") (pintype "passive"))
    )
    (net (code "818") (name "Net-(SV171-Pad1)") (class "Default")
      (node (ref "SV171") (pin "1") (pinfunction "1_1") (pintype "passive"))
      (node (ref "SV171") (pin "3") (pinfunction "3_3") (pintype "passive"))
      (node (ref "SV171") (pin "5") (pinfunction "5_5") (pintype "passive"))
      (node (ref "SV171") (pin "7") (pinfunction "7_7") (pintype "passive"))
      (node (ref "SV171") (pin "9") (pinfunction "9_9") (pintype "passive"))
    )
    (net (code "819") (name "Net-(SV171-Pad10)") (class "Default")
      (node (ref "SV171") (pin "10") (pinfunction "10_10") (pintype "passive"))
      (node (ref "SV171") (pin "2") (pinfunction "2_2") (pintype "passive"))
      (node (ref "SV171") (pin "4") (pinfunction "4_4") (pintype "passive"))
      (node (ref "SV171") (pin "6") (pinfunction "6_6") (pintype "passive"))
      (node (ref "SV171") (pin "8") (pinfunction "8_8") (pintype "passive"))
    )
    (net (code "820") (name "Net-(SV172-Pad1)") (class "Default")
      (node (ref "SV172") (pin "1") (pinfunction "1_1") (pintype "passive"))
      (node (ref "SV172") (pin "3") (pinfunction "3_3") (pintype "passive"))
      (node (ref "SV172") (pin "5") (pinfunction "5_5") (pintype "passive"))
      (node (ref "SV172") (pin "7") (pinfunction "7_7") (pintype "passive"))
      (node (ref "SV172") (pin "9") (pinfunction "9_9") (pintype "passive"))
    )
    (net (code "821") (name "Net-(SV172-Pad10)") (class "Default")
      (node (ref "SV172") (pin "10") (pinfunction "10_10") (pintype "passive"))
      (node (ref "SV172") (pin "2") (pinfunction "2_2") (pintype "passive"))
      (node (ref "SV172") (pin "4") (pinfunction "4_4") (pintype "passive"))
      (node (ref "SV172") (pin "6") (pinfunction "6_6") (pintype "passive"))
      (node (ref "SV172") (pin "8") (pinfunction "8_8") (pintype "passive"))
    )
    (net (code "822") (name "Net-(SV173-Pad1)") (class "Default")
      (node (ref "SV173") (pin "1") (pinfunction "1_1") (pintype "passive"))
      (node (ref "SV173") (pin "3") (pinfunction "3_3") (pintype "passive"))
      (node (ref "SV173") (pin "5") (pinfunction "5_5") (pintype "passive"))
      (node (ref "SV173") (pin "7") (pinfunction "7_7") (pintype "passive"))
      (node (ref "SV173") (pin "9") (pinfunction "9_9") (pintype "passive"))
    )
    (net (code "823") (name "Net-(SV173-Pad10)") (class "Default")
      (node (ref "SV173") (pin "10") (pinfunction "10_10") (pintype "passive"))
      (node (ref "SV173") (pin "2") (pinfunction "2_2") (pintype "passive"))
      (node (ref "SV173") (pin "4") (pinfunction "4_4") (pintype "passive"))
      (node (ref "SV173") (pin "6") (pinfunction "6_6") (pintype "passive"))
      (node (ref "SV173") (pin "8") (pinfunction "8_8") (pintype "passive"))
    )
    (net (code "824") (name "Net-(SV174-Pad1)") (class "Default")
      (node (ref "SV174") (pin "1") (pinfunction "1_1") (pintype "passive"))
      (node (ref "SV174") (pin "3") (pinfunction "3_3") (pintype "passive"))
      (node (ref "SV174") (pin "5") (pinfunction "5_5") (pintype "passive"))
      (node (ref "SV174") (pin "7") (pinfunction "7_7") (pintype "passive"))
      (node (ref "SV174") (pin "9") (pinfunction "9_9") (pintype "passive"))
    )
    (net (code "825") (name "Net-(SV174-Pad10)") (class "Default")
      (node (ref "SV174") (pin "10") (pinfunction "10_10") (pintype "passive"))
      (node (ref "SV174") (pin "2") (pinfunction "2_2") (pintype "passive"))
      (node (ref "SV174") (pin "4") (pinfunction "4_4") (pintype "passive"))
      (node (ref "SV174") (pin "6") (pinfunction "6_6") (pintype "passive"))
      (node (ref "SV174") (pin "8") (pinfunction "8_8") (pintype "passive"))
    )
    (net (code "826") (name "Net-(U$2A-1)") (class "Default")
      (node (ref "D9") (pin "1") (pinfunction "1_1") (pintype "passive"))
      (node (ref "U$2") (pin "AA1") (pinfunction "1_AA1") (pintype "passive"))
    )
    (net (code "827") (name "Net-(U$2AK-1)") (class "Default")
      (node (ref "D7") (pin "1") (pinfunction "1_1") (pintype "passive"))
      (node (ref "U$2") (pin "BA1") (pinfunction "1_BA1") (pintype "passive"))
    )
    (net (code "828") (name "Net-(U$2AM-1)") (class "Default")
      (node (ref "D7") (pin "2") (pinfunction "2_2") (pintype "passive"))
      (node (ref "U$2") (pin "BB1") (pinfunction "1_BB1") (pintype "passive"))
    )
    (net (code "829") (name "Net-(U$2BN-1)") (class "Default")
      (node (ref "D8") (pin "15") (pinfunction "15_15") (pintype "passive"))
      (node (ref "U$2") (pin "BS2") (pinfunction "1_BS2") (pintype "passive"))
    )
    (net (code "830") (name "Net-(U$2BU-1)") (class "Default")
      (node (ref "D11") (pin "1") (pinfunction "1_1") (pintype "passive"))
      (node (ref "U$2") (pin "CA1") (pinfunction "1_CA1") (pintype "passive"))
    )
    (net (code "831") (name "Net-(U$2BW-1)") (class "Default")
      (node (ref "D11") (pin "2") (pinfunction "2_2") (pintype "passive"))
      (node (ref "U$2") (pin "CB1") (pinfunction "1_CB1") (pintype "passive"))
    )
    (net (code "832") (name "Net-(U$2C-1)") (class "Default")
      (node (ref "D9") (pin "2") (pinfunction "2_2") (pintype "passive"))
      (node (ref "U$2") (pin "AB1") (pinfunction "1_AB1") (pintype "passive"))
    )
    (net (code "833") (name "Net-(U$2DE-1)") (class "Default")
      (node (ref "D13") (pin "1") (pinfunction "1_1") (pintype "passive"))
      (node (ref "U$2") (pin "DA1") (pinfunction "1_DA1") (pintype "passive"))
    )
    (net (code "834") (name "Net-(U$2DG-1)") (class "Default")
      (node (ref "D13") (pin "2") (pinfunction "2_2") (pintype "passive"))
      (node (ref "U$2") (pin "DB1") (pinfunction "1_DB1") (pintype "passive"))
    )
    (net (code "835") (name "POWER_OK") (class "Default")
      (node (ref "D8") (pin "18") (pinfunction "18_18") (pintype "passive"))
      (node (ref "R6") (pin "1") (pinfunction "1_1") (pintype "passive"))
      (node (ref "U$2") (pin "BV2") (pinfunction "1_BV2") (pintype "passive"))
    )
    (net (code "836") (name "PULSE_LA") (class "Default")
      (node (ref "D14") (pin "14") (pinfunction "14_14") (pintype "passive"))
      (node (ref "U$2") (pin "DR2") (pinfunction "1_DR2") (pintype "passive"))
    )
    (net (code "837") (name "RETURN") (class "Default")
      (node (ref "D10") (pin "14") (pinfunction "14_14") (pintype "passive"))
      (node (ref "U$2") (pin "AR2") (pinfunction "1_AR2") (pintype "passive"))
    )
    (net (code "838") (name "SOURCE") (class "Default")
      (node (ref "D10") (pin "10") (pinfunction "10_10") (pintype "passive"))
      (node (ref "IC8") (pin "6") (pinfunction "A5_6") (pintype "input"))
      (node (ref "U$2") (pin "AL2") (pinfunction "1_AL2") (pintype "passive"))
    )
    (net (code "839") (name "STROBE") (class "Default")
      (node (ref "D10") (pin "11") (pinfunction "11_11") (pintype "passive"))
      (node (ref "U$2") (pin "AM2") (pinfunction "1_AM2") (pintype "passive"))
    )
    (net (code "840") (name "SWITCH") (class "Default")
      (node (ref "D14") (pin "18") (pinfunction "18_18") (pintype "passive"))
      (node (ref "U$2") (pin "DV2") (pinfunction "1_DV2") (pintype "passive"))
    )
    (net (code "841") (name "TP1") (class "Default")
      (node (ref "D12") (pin "4") (pinfunction "4_4") (pintype "passive"))
      (node (ref "U$2") (pin "CD2") (pinfunction "1_CD2") (pintype "passive"))
    )
    (net (code "842") (name "TP2") (class "Default")
      (node (ref "D12") (pin "5") (pinfunction "5_5") (pintype "passive"))
      (node (ref "U$2") (pin "CE2") (pinfunction "1_CE2") (pintype "passive"))
    )
    (net (code "843") (name "TP3") (class "Default")
      (node (ref "D12") (pin "7") (pinfunction "7_7") (pintype "passive"))
      (node (ref "U$2") (pin "CH2") (pinfunction "1_CH2") (pintype "passive"))
    )
    (net (code "844") (name "TP4") (class "Default")
      (node (ref "D12") (pin "8") (pinfunction "8_8") (pintype "passive"))
      (node (ref "U$2") (pin "CJ2") (pinfunction "1_CJ2") (pintype "passive"))
    )
    (net (code "845") (name "V+") (class "Default")
      (node (ref "C1") (pin "1") (pinfunction "1_1") (pintype "passive"))
      (node (ref "C3") (pin "1") (pinfunction "1_1") (pintype "passive"))
      (node (ref "D1") (pin "C") (pinfunction "C_C") (pintype "passive"))
      (node (ref "D2") (pin "C") (pinfunction "C_C") (pintype "passive"))
      (node (ref "IC3") (pin "28") (pinfunction "VCC_28") (pintype "power_in"))
      (node (ref "IC4") (pin "28") (pinfunction "VCC_28") (pintype "power_in"))
      (node (ref "R7") (pin "2") (pinfunction "2_2") (pintype "passive"))
    )
    (net (code "846") (name "VCC") (class "Default")
      (node (ref "C10") (pin "+") (pinfunction "+_+") (pintype "passive"))
      (node (ref "C4") (pin "1") (pinfunction "1_1") (pintype "passive"))
      (node (ref "C5") (pin "1") (pinfunction "1_1") (pintype "passive"))
      (node (ref "C6") (pin "1") (pinfunction "1_1") (pintype "passive"))
      (node (ref "C7") (pin "1") (pinfunction "1_1") (pintype "passive"))
      (node (ref "C8") (pin "1") (pinfunction "1_1") (pintype "passive"))
      (node (ref "C9") (pin "1") (pinfunction "1_1") (pintype "passive"))
      (node (ref "D10") (pin "1") (pinfunction "1_1") (pintype "passive"))
      (node (ref "D12") (pin "1") (pinfunction "1_1") (pintype "passive"))
      (node (ref "D2") (pin "A") (pinfunction "A_A") (pintype "passive"))
      (node (ref "D8") (pin "1") (pinfunction "1_1") (pintype "passive"))
      (node (ref "IC7") (pin "1") (pinfunction "I0_1") (pintype "input"))
      (node (ref "IC7") (pin "12") (pinfunction "I2_12") (pintype "input"))
      (node (ref "IC7") (pin "13") (pinfunction "I3_13") (pintype "input"))
      (node (ref "R5") (pin "10") (pinfunction "2_10") (pintype "passive"))
      (node (ref "R5") (pin "11") (pinfunction "2_11") (pintype "passive"))
      (node (ref "R5") (pin "12") (pinfunction "2_12") (pintype "passive"))
      (node (ref "R5") (pin "13") (pinfunction "2_13") (pintype "passive"))
      (node (ref "R5") (pin "14") (pinfunction "2_14") (pintype "passive"))
      (node (ref "R5") (pin "15") (pinfunction "2_15") (pintype "passive"))
      (node (ref "R5") (pin "16") (pinfunction "2_16") (pintype "passive"))
      (node (ref "R5") (pin "9") (pinfunction "2_9") (pintype "passive"))
      (node (ref "SV11") (pin "1") (pinfunction "1_1") (pintype "passive"))
      (node (ref "SV11") (pin "10") (pinfunction "10_10") (pintype "passive"))
      (node (ref "SV11") (pin "2") (pinfunction "2_2") (pintype "passive"))
      (node (ref "SV11") (pin "3") (pinfunction "3_3") (pintype "passive"))
      (node (ref "SV11") (pin "4") (pinfunction "4_4") (pintype "passive"))
      (node (ref "SV11") (pin "5") (pinfunction "5_5") (pintype "passive"))
      (node (ref "SV11") (pin "6") (pinfunction "6_6") (pintype "passive"))
      (node (ref "SV11") (pin "7") (pinfunction "7_7") (pintype "passive"))
      (node (ref "SV11") (pin "8") (pinfunction "8_8") (pintype "passive"))
      (node (ref "SV11") (pin "9") (pinfunction "9_9") (pintype "passive"))
      (node (ref "SV125") (pin "1") (pinfunction "1_1") (pintype "passive"))
      (node (ref "SV125") (pin "10") (pinfunction "10_10") (pintype "passive"))
      (node (ref "SV125") (pin "11") (pinfunction "11_11") (pintype "passive"))
      (node (ref "SV125") (pin "12") (pinfunction "12_12") (pintype "passive"))
      (node (ref "SV125") (pin "13") (pinfunction "13_13") (pintype "passive"))
      (node (ref "SV125") (pin "14") (pinfunction "14_14") (pintype "passive"))
      (node (ref "SV125") (pin "15") (pinfunction "15_15") (pintype "passive"))
      (node (ref "SV125") (pin "16") (pinfunction "16_16") (pintype "passive"))
      (node (ref "SV125") (pin "17") (pinfunction "17_17") (pintype "passive"))
      (node (ref "SV125") (pin "18") (pinfunction "18_18") (pintype "passive"))
      (node (ref "SV125") (pin "19") (pinfunction "19_19") (pintype "passive"))
      (node (ref "SV125") (pin "2") (pinfunction "2_2") (pintype "passive"))
      (node (ref "SV125") (pin "20") (pinfunction "20_20") (pintype "passive"))
      (node (ref "SV125") (pin "3") (pinfunction "3_3") (pintype "passive"))
      (node (ref "SV125") (pin "4") (pinfunction "4_4") (pintype "passive"))
      (node (ref "SV125") (pin "5") (pinfunction "5_5") (pintype "passive"))
      (node (ref "SV125") (pin "6") (pinfunction "6_6") (pintype "passive"))
      (node (ref "SV125") (pin "7") (pinfunction "7_7") (pintype "passive"))
      (node (ref "SV125") (pin "8") (pinfunction "8_8") (pintype "passive"))
      (node (ref "SV125") (pin "9") (pinfunction "9_9") (pintype "passive"))
      (node (ref "SV127") (pin "1") (pinfunction "1_1") (pintype "passive"))
      (node (ref "SV127") (pin "2") (pinfunction "2_2") (pintype "passive"))
      (node (ref "SV127") (pin "3") (pinfunction "3_3") (pintype "passive"))
      (node (ref "SV127") (pin "4") (pinfunction "4_4") (pintype "passive"))
      (node (ref "SV127") (pin "5") (pinfunction "5_5") (pintype "passive"))
      (node (ref "SV127") (pin "6") (pinfunction "6_6") (pintype "passive"))
      (node (ref "SV127") (pin "7") (pinfunction "7_7") (pintype "passive"))
      (node (ref "SV127") (pin "8") (pinfunction "8_8") (pintype "passive"))
      (node (ref "SV129") (pin "1") (pinfunction "1_1") (pintype "passive"))
      (node (ref "SV129") (pin "10") (pinfunction "10_10") (pintype "passive"))
      (node (ref "SV129") (pin "2") (pinfunction "2_2") (pintype "passive"))
      (node (ref "SV129") (pin "3") (pinfunction "3_3") (pintype "passive"))
      (node (ref "SV129") (pin "4") (pinfunction "4_4") (pintype "passive"))
      (node (ref "SV129") (pin "5") (pinfunction "5_5") (pintype "passive"))
      (node (ref "SV129") (pin "6") (pinfunction "6_6") (pintype "passive"))
      (node (ref "SV129") (pin "7") (pinfunction "7_7") (pintype "passive"))
      (node (ref "SV129") (pin "8") (pinfunction "8_8") (pintype "passive"))
      (node (ref "SV129") (pin "9") (pinfunction "9_9") (pintype "passive"))
      (node (ref "SV131") (pin "1") (pinfunction "1_1") (pintype "passive"))
      (node (ref "SV131") (pin "10") (pinfunction "10_10") (pintype "passive"))
      (node (ref "SV131") (pin "11") (pinfunction "11_11") (pintype "passive"))
      (node (ref "SV131") (pin "12") (pinfunction "12_12") (pintype "passive"))
      (node (ref "SV131") (pin "13") (pinfunction "13_13") (pintype "passive"))
      (node (ref "SV131") (pin "14") (pinfunction "14_14") (pintype "passive"))
      (node (ref "SV131") (pin "15") (pinfunction "15_15") (pintype "passive"))
      (node (ref "SV131") (pin "16") (pinfunction "16_16") (pintype "passive"))
      (node (ref "SV131") (pin "17") (pinfunction "17_17") (pintype "passive"))
      (node (ref "SV131") (pin "18") (pinfunction "18_18") (pintype "passive"))
      (node (ref "SV131") (pin "19") (pinfunction "19_19") (pintype "passive"))
      (node (ref "SV131") (pin "2") (pinfunction "2_2") (pintype "passive"))
      (node (ref "SV131") (pin "20") (pinfunction "20_20") (pintype "passive"))
      (node (ref "SV131") (pin "3") (pinfunction "3_3") (pintype "passive"))
      (node (ref "SV131") (pin "4") (pinfunction "4_4") (pintype "passive"))
      (node (ref "SV131") (pin "5") (pinfunction "5_5") (pintype "passive"))
      (node (ref "SV131") (pin "6") (pinfunction "6_6") (pintype "passive"))
      (node (ref "SV131") (pin "7") (pinfunction "7_7") (pintype "passive"))
      (node (ref "SV131") (pin "8") (pinfunction "8_8") (pintype "passive"))
      (node (ref "SV131") (pin "9") (pinfunction "9_9") (pintype "passive"))
      (node (ref "SV175") (pin "1") (pinfunction "1_1") (pintype "passive"))
      (node (ref "SV175") (pin "10") (pinfunction "10_10") (pintype "passive"))
      (node (ref "SV175") (pin "11") (pinfunction "11_11") (pintype "passive"))
      (node (ref "SV175") (pin "12") (pinfunction "12_12") (pintype "passive"))
      (node (ref "SV175") (pin "13") (pinfunction "13_13") (pintype "passive"))
      (node (ref "SV175") (pin "14") (pinfunction "14_14") (pintype "passive"))
      (node (ref "SV175") (pin "15") (pinfunction "15_15") (pintype "passive"))
      (node (ref "SV175") (pin "16") (pinfunction "16_16") (pintype "passive"))
      (node (ref "SV175") (pin "17") (pinfunction "17_17") (pintype "passive"))
      (node (ref "SV175") (pin "18") (pinfunction "18_18") (pintype "passive"))
      (node (ref "SV175") (pin "19") (pinfunction "19_19") (pintype "passive"))
      (node (ref "SV175") (pin "2") (pinfunction "2_2") (pintype "passive"))
      (node (ref "SV175") (pin "20") (pinfunction "20_20") (pintype "passive"))
      (node (ref "SV175") (pin "3") (pinfunction "3_3") (pintype "passive"))
      (node (ref "SV175") (pin "4") (pinfunction "4_4") (pintype "passive"))
      (node (ref "SV175") (pin "5") (pinfunction "5_5") (pintype "passive"))
      (node (ref "SV175") (pin "6") (pinfunction "6_6") (pintype "passive"))
      (node (ref "SV175") (pin "7") (pinfunction "7_7") (pintype "passive"))
      (node (ref "SV175") (pin "8") (pinfunction "8_8") (pintype "passive"))
      (node (ref "SV175") (pin "9") (pinfunction "9_9") (pintype "passive"))
      (node (ref "SV177") (pin "1") (pinfunction "1_1") (pintype "passive"))
      (node (ref "SV177") (pin "2") (pinfunction "2_2") (pintype "passive"))
      (node (ref "SV177") (pin "3") (pinfunction "3_3") (pintype "passive"))
      (node (ref "SV177") (pin "4") (pinfunction "4_4") (pintype "passive"))
      (node (ref "SV177") (pin "5") (pinfunction "5_5") (pintype "passive"))
      (node (ref "SV177") (pin "6") (pinfunction "6_6") (pintype "passive"))
      (node (ref "SV177") (pin "7") (pinfunction "7_7") (pintype "passive"))
      (node (ref "SV177") (pin "8") (pinfunction "8_8") (pintype "passive"))
      (node (ref "SV178") (pin "1") (pinfunction "1_1") (pintype "passive"))
      (node (ref "SV178") (pin "2") (pinfunction "2_2") (pintype "passive"))
      (node (ref "SV178") (pin "3") (pinfunction "3_3") (pintype "passive"))
      (node (ref "SV178") (pin "4") (pinfunction "4_4") (pintype "passive"))
      (node (ref "SV178") (pin "5") (pinfunction "5_5") (pintype "passive"))
      (node (ref "SV178") (pin "6") (pinfunction "6_6") (pintype "passive"))
      (node (ref "SV178") (pin "7") (pinfunction "7_7") (pintype "passive"))
      (node (ref "SV178") (pin "8") (pinfunction "8_8") (pintype "passive"))
      (node (ref "SV179") (pin "1") (pinfunction "1_1") (pintype "passive"))
      (node (ref "SV179") (pin "10") (pinfunction "10_10") (pintype "passive"))
      (node (ref "SV179") (pin "2") (pinfunction "2_2") (pintype "passive"))
      (node (ref "SV179") (pin "3") (pinfunction "3_3") (pintype "passive"))
      (node (ref "SV179") (pin "4") (pinfunction "4_4") (pintype "passive"))
      (node (ref "SV179") (pin "5") (pinfunction "5_5") (pintype "passive"))
      (node (ref "SV179") (pin "6") (pinfunction "6_6") (pintype "passive"))
      (node (ref "SV179") (pin "7") (pinfunction "7_7") (pintype "passive"))
      (node (ref "SV179") (pin "8") (pinfunction "8_8") (pintype "passive"))
      (node (ref "SV179") (pin "9") (pinfunction "9_9") (pintype "passive"))
      (node (ref "SV3") (pin "1") (pinfunction "1_1") (pintype "passive"))
      (node (ref "SV3") (pin "10") (pinfunction "10_10") (pintype "passive"))
      (node (ref "SV3") (pin "11") (pinfunction "11_11") (pintype "passive"))
      (node (ref "SV3") (pin "12") (pinfunction "12_12") (pintype "passive"))
      (node (ref "SV3") (pin "13") (pinfunction "13_13") (pintype "passive"))
      (node (ref "SV3") (pin "14") (pinfunction "14_14") (pintype "passive"))
      (node (ref "SV3") (pin "15") (pinfunction "15_15") (pintype "passive"))
      (node (ref "SV3") (pin "16") (pinfunction "16_16") (pintype "passive"))
      (node (ref "SV3") (pin "17") (pinfunction "17_17") (pintype "passive"))
      (node (ref "SV3") (pin "18") (pinfunction "18_18") (pintype "passive"))
      (node (ref "SV3") (pin "19") (pinfunction "19_19") (pintype "passive"))
      (node (ref "SV3") (pin "2") (pinfunction "2_2") (pintype "passive"))
      (node (ref "SV3") (pin "20") (pinfunction "20_20") (pintype "passive"))
      (node (ref "SV3") (pin "3") (pinfunction "3_3") (pintype "passive"))
      (node (ref "SV3") (pin "4") (pinfunction "4_4") (pintype "passive"))
      (node (ref "SV3") (pin "5") (pinfunction "5_5") (pintype "passive"))
      (node (ref "SV3") (pin "6") (pinfunction "6_6") (pintype "passive"))
      (node (ref "SV3") (pin "7") (pinfunction "7_7") (pintype "passive"))
      (node (ref "SV3") (pin "8") (pinfunction "8_8") (pintype "passive"))
      (node (ref "SV3") (pin "9") (pinfunction "9_9") (pintype "passive"))
      (node (ref "SV5") (pin "1") (pinfunction "1_1") (pintype "passive"))
      (node (ref "SV5") (pin "10") (pinfunction "10_10") (pintype "passive"))
      (node (ref "SV5") (pin "11") (pinfunction "11_11") (pintype "passive"))
      (node (ref "SV5") (pin "12") (pinfunction "12_12") (pintype "passive"))
      (node (ref "SV5") (pin "13") (pinfunction "13_13") (pintype "passive"))
      (node (ref "SV5") (pin "14") (pinfunction "14_14") (pintype "passive"))
      (node (ref "SV5") (pin "15") (pinfunction "15_15") (pintype "passive"))
      (node (ref "SV5") (pin "16") (pinfunction "16_16") (pintype "passive"))
      (node (ref "SV5") (pin "17") (pinfunction "17_17") (pintype "passive"))
      (node (ref "SV5") (pin "18") (pinfunction "18_18") (pintype "passive"))
      (node (ref "SV5") (pin "19") (pinfunction "19_19") (pintype "passive"))
      (node (ref "SV5") (pin "2") (pinfunction "2_2") (pintype "passive"))
      (node (ref "SV5") (pin "20") (pinfunction "20_20") (pintype "passive"))
      (node (ref "SV5") (pin "3") (pinfunction "3_3") (pintype "passive"))
      (node (ref "SV5") (pin "4") (pinfunction "4_4") (pintype "passive"))
      (node (ref "SV5") (pin "5") (pinfunction "5_5") (pintype "passive"))
      (node (ref "SV5") (pin "6") (pinfunction "6_6") (pintype "passive"))
      (node (ref "SV5") (pin "7") (pinfunction "7_7") (pintype "passive"))
      (node (ref "SV5") (pin "8") (pinfunction "8_8") (pintype "passive"))
      (node (ref "SV5") (pin "9") (pinfunction "9_9") (pintype "passive"))
      (node (ref "SV9") (pin "1") (pinfunction "1_1") (pintype "passive"))
      (node (ref "SV9") (pin "2") (pinfunction "2_2") (pintype "passive"))
      (node (ref "SV9") (pin "3") (pinfunction "3_3") (pintype "passive"))
      (node (ref "SV9") (pin "4") (pinfunction "4_4") (pintype "passive"))
      (node (ref "SV9") (pin "5") (pinfunction "5_5") (pintype "passive"))
      (node (ref "SV9") (pin "6") (pinfunction "6_6") (pintype "passive"))
      (node (ref "SV9") (pin "7") (pinfunction "7_7") (pintype "passive"))
      (node (ref "SV9") (pin "8") (pinfunction "8_8") (pintype "passive"))
      (node (ref "U$2") (pin "AA2") (pinfunction "1_AA2") (pintype "passive"))
      (node (ref "U$2") (pin "BA2") (pinfunction "1_BA2") (pintype "passive"))
      (node (ref "U$2") (pin "CA2") (pinfunction "1_CA2") (pintype "passive"))
      (node (ref "VCC1") (pin "1") (pinfunction "1_1") (pintype "passive"))
      (node (ref "VCC1") (pin "2") (pinfunction "2_2") (pintype "passive"))
      (node (ref "VCC10") (pin "1") (pinfunction "1_1") (pintype "passive"))
      (node (ref "VCC10") (pin "2") (pinfunction "2_2") (pintype "passive"))
      (node (ref "VCC11") (pin "1") (pinfunction "1_1") (pintype "passive"))
      (node (ref "VCC11") (pin "2") (pinfunction "2_2") (pintype "passive"))
      (node (ref "VCC12") (pin "1") (pinfunction "1_1") (pintype "passive"))
      (node (ref "VCC12") (pin "2") (pinfunction "2_2") (pintype "passive"))
      (node (ref "VCC13") (pin "1") (pinfunction "1_1") (pintype "passive"))
      (node (ref "VCC13") (pin "2") (pinfunction "2_2") (pintype "passive"))
      (node (ref "VCC14") (pin "1") (pinfunction "1_1") (pintype "passive"))
      (node (ref "VCC14") (pin "2") (pinfunction "2_2") (pintype "passive"))
      (node (ref "VCC15") (pin "1") (pinfunction "1_1") (pintype "passive"))
      (node (ref "VCC15") (pin "2") (pinfunction "2_2") (pintype "passive"))
      (node (ref "VCC16") (pin "1") (pinfunction "1_1") (pintype "passive"))
      (node (ref "VCC16") (pin "2") (pinfunction "2_2") (pintype "passive"))
      (node (ref "VCC17") (pin "1") (pinfunction "1_1") (pintype "passive"))
      (node (ref "VCC17") (pin "2") (pinfunction "2_2") (pintype "passive"))
      (node (ref "VCC18") (pin "1") (pinfunction "1_1") (pintype "passive"))
      (node (ref "VCC18") (pin "2") (pinfunction "2_2") (pintype "passive"))
      (node (ref "VCC19") (pin "1") (pinfunction "1_1") (pintype "passive"))
      (node (ref "VCC19") (pin "2") (pinfunction "2_2") (pintype "passive"))
      (node (ref "VCC2") (pin "1") (pinfunction "1_1") (pintype "passive"))
      (node (ref "VCC2") (pin "2") (pinfunction "2_2") (pintype "passive"))
      (node (ref "VCC20") (pin "1") (pinfunction "1_1") (pintype "passive"))
      (node (ref "VCC20") (pin "2") (pinfunction "2_2") (pintype "passive"))
      (node (ref "VCC21") (pin "1") (pinfunction "1_1") (pintype "passive"))
      (node (ref "VCC21") (pin "2") (pinfunction "2_2") (pintype "passive"))
      (node (ref "VCC22") (pin "1") (pinfunction "1_1") (pintype "passive"))
      (node (ref "VCC22") (pin "2") (pinfunction "2_2") (pintype "passive"))
      (node (ref "VCC23") (pin "1") (pinfunction "1_1") (pintype "passive"))
      (node (ref "VCC23") (pin "2") (pinfunction "2_2") (pintype "passive"))
      (node (ref "VCC24") (pin "1") (pinfunction "1_1") (pintype "passive"))
      (node (ref "VCC24") (pin "2") (pinfunction "2_2") (pintype "passive"))
      (node (ref "VCC25") (pin "1") (pinfunction "1_1") (pintype "passive"))
      (node (ref "VCC25") (pin "2") (pinfunction "2_2") (pintype "passive"))
      (node (ref "VCC26") (pin "1") (pinfunction "1_1") (pintype "passive"))
      (node (ref "VCC26") (pin "2") (pinfunction "2_2") (pintype "passive"))
      (node (ref "VCC27") (pin "1") (pinfunction "1_1") (pintype "passive"))
      (node (ref "VCC27") (pin "2") (pinfunction "2_2") (pintype "passive"))
      (node (ref "VCC28") (pin "1") (pinfunction "1_1") (pintype "passive"))
      (node (ref "VCC28") (pin "2") (pinfunction "2_2") (pintype "passive"))
      (node (ref "VCC29") (pin "1") (pinfunction "1_1") (pintype "passive"))
      (node (ref "VCC29") (pin "2") (pinfunction "2_2") (pintype "passive"))
      (node (ref "VCC3") (pin "1") (pinfunction "1_1") (pintype "passive"))
      (node (ref "VCC3") (pin "2") (pinfunction "2_2") (pintype "passive"))
      (node (ref "VCC30") (pin "1") (pinfunction "1_1") (pintype "passive"))
      (node (ref "VCC30") (pin "2") (pinfunction "2_2") (pintype "passive"))
      (node (ref "VCC31") (pin "1") (pinfunction "1_1") (pintype "passive"))
      (node (ref "VCC31") (pin "2") (pinfunction "2_2") (pintype "passive"))
      (node (ref "VCC32") (pin "1") (pinfunction "1_1") (pintype "passive"))
      (node (ref "VCC32") (pin "2") (pinfunction "2_2") (pintype "passive"))
      (node (ref "VCC33") (pin "1") (pinfunction "1_1") (pintype "passive"))
      (node (ref "VCC33") (pin "2") (pinfunction "2_2") (pintype "passive"))
      (node (ref "VCC34") (pin "1") (pinfunction "1_1") (pintype "passive"))
      (node (ref "VCC34") (pin "2") (pinfunction "2_2") (pintype "passive"))
      (node (ref "VCC35") (pin "1") (pinfunction "1_1") (pintype "passive"))
      (node (ref "VCC35") (pin "2") (pinfunction "2_2") (pintype "passive"))
      (node (ref "VCC36") (pin "1") (pinfunction "1_1") (pintype "passive"))
      (node (ref "VCC36") (pin "2") (pinfunction "2_2") (pintype "passive"))
      (node (ref "VCC37") (pin "1") (pinfunction "1_1") (pintype "passive"))
      (node (ref "VCC37") (pin "2") (pinfunction "2_2") (pintype "passive"))
      (node (ref "VCC38") (pin "1") (pinfunction "1_1") (pintype "passive"))
      (node (ref "VCC38") (pin "2") (pinfunction "2_2") (pintype "passive"))
      (node (ref "VCC39") (pin "1") (pinfunction "1_1") (pintype "passive"))
      (node (ref "VCC39") (pin "2") (pinfunction "2_2") (pintype "passive"))
      (node (ref "VCC4") (pin "1") (pinfunction "1_1") (pintype "passive"))
      (node (ref "VCC4") (pin "2") (pinfunction "2_2") (pintype "passive"))
      (node (ref "VCC40") (pin "1") (pinfunction "1_1") (pintype "passive"))
      (node (ref "VCC40") (pin "2") (pinfunction "2_2") (pintype "passive"))
      (node (ref "VCC41") (pin "1") (pinfunction "1_1") (pintype "passive"))
      (node (ref "VCC41") (pin "2") (pinfunction "2_2") (pintype "passive"))
      (node (ref "VCC42") (pin "1") (pinfunction "1_1") (pintype "passive"))
      (node (ref "VCC42") (pin "2") (pinfunction "2_2") (pintype "passive"))
      (node (ref "VCC43") (pin "1") (pinfunction "1_1") (pintype "passive"))
      (node (ref "VCC43") (pin "2") (pinfunction "2_2") (pintype "passive"))
      (node (ref "VCC44") (pin "1") (pinfunction "1_1") (pintype "passive"))
      (node (ref "VCC44") (pin "2") (pinfunction "2_2") (pintype "passive"))
      (node (ref "VCC5") (pin "1") (pinfunction "1_1") (pintype "passive"))
      (node (ref "VCC5") (pin "2") (pinfunction "2_2") (pintype "passive"))
      (node (ref "VCC6") (pin "1") (pinfunction "1_1") (pintype "passive"))
      (node (ref "VCC6") (pin "2") (pinfunction "2_2") (pintype "passive"))
      (node (ref "VCC7") (pin "1") (pinfunction "1_1") (pintype "passive"))
      (node (ref "VCC7") (pin "2") (pinfunction "2_2") (pintype "passive"))
      (node (ref "VCC8") (pin "1") (pinfunction "1_1") (pintype "passive"))
      (node (ref "VCC8") (pin "2") (pinfunction "2_2") (pintype "passive"))
      (node (ref "VCC9") (pin "1") (pinfunction "1_1") (pintype "passive"))
      (node (ref "VCC9") (pin "2") (pinfunction "2_2") (pintype "passive"))
    )
    (net (code "847") (name "WRITE") (class "Default")
      (node (ref "D10") (pin "15") (pinfunction "15_15") (pintype "passive"))
      (node (ref "IC8") (pin "4") (pinfunction "A3_4") (pintype "input"))
      (node (ref "U$2") (pin "AS2") (pinfunction "1_AS2") (pintype "passive"))
    )
    (net (code "848") (name "unconnected-(IC8A-Y8-Pad11)") (class "Default")
      (node (ref "IC8") (pin "11") (pinfunction "Y8_11") (pintype "tri_state"))
    )
    (net (code "849") (name "~{BREAK_CYCLE}") (class "Default")
      (node (ref "D8") (pin "10") (pinfunction "10_10") (pintype "passive"))
      (node (ref "U$2") (pin "BL2") (pinfunction "1_BL2") (pintype "passive"))
    )
    (net (code "850") (name "~{BRK_DATA_CONT}") (class "Default")
      (node (ref "D8") (pin "9") (pinfunction "9_9") (pintype "passive"))
      (node (ref "U$2") (pin "BK2") (pinfunction "1_BK2") (pintype "passive"))
    )
    (net (code "851") (name "~{BRK_IN_PROG}") (class "Default")
      (node (ref "D8") (pin "5") (pinfunction "5_5") (pintype "passive"))
      (node (ref "U$2") (pin "BE2") (pinfunction "1_BE2") (pintype "passive"))
    )
    (net (code "852") (name "~{BUS_STROBE}") (class "Default")
      (node (ref "D11") (pin "9") (pinfunction "9_9") (pintype "passive"))
      (node (ref "U$2") (pin "CK1") (pinfunction "1_CK1") (pintype "passive"))
    )
    (net (code "853") (name "~{C0}") (class "Default")
      (node (ref "D11") (pin "5") (pinfunction "5_5") (pintype "passive"))
      (node (ref "U$2") (pin "CE1") (pinfunction "1_CE1") (pintype "passive"))
    )
    (net (code "854") (name "~{C1}") (class "Default")
      (node (ref "D11") (pin "7") (pinfunction "7_7") (pintype "passive"))
      (node (ref "U$2") (pin "CH1") (pinfunction "1_CH1") (pintype "passive"))
    )
    (net (code "855") (name "~{C2}") (class "Default")
      (node (ref "D11") (pin "8") (pinfunction "8_8") (pintype "passive"))
      (node (ref "U$2") (pin "CJ1") (pinfunction "1_CJ1") (pintype "passive"))
    )
    (net (code "856") (name "~{CE}") (class "Default")
      (node (ref "C2") (pin "1") (pinfunction "1_1") (pintype "passive"))
      (node (ref "IC3") (pin "20") (pinfunction "~{CE}_20") (pintype "input"))
      (node (ref "IC4") (pin "20") (pinfunction "~{CE}_20") (pintype "input"))
      (node (ref "Q1") (pin "1") (pinfunction "C_1") (pintype "passive"))
      (node (ref "R7") (pin "1") (pinfunction "1_1") (pintype "passive"))
    )
    (net (code "857") (name "~{CPMA_DISABLE}") (class "Default")
      (node (ref "D11") (pin "17") (pinfunction "17_17") (pintype "passive"))
      (node (ref "U$2") (pin "CU1") (pinfunction "1_CU1") (pintype "passive"))
    )
    (net (code "858") (name "~{DATA0}") (class "Default")
      (node (ref "D9") (pin "14") (pinfunction "14_14") (pintype "passive"))
      (node (ref "U$2") (pin "AR1") (pinfunction "1_AR1") (pintype "passive"))
    )
    (net (code "859") (name "~{DATA1}") (class "Default")
      (node (ref "D9") (pin "15") (pinfunction "15_15") (pintype "passive"))
      (node (ref "U$2") (pin "AS1") (pinfunction "1_AS1") (pintype "passive"))
    )
    (net (code "860") (name "~{DATA2}") (class "Default")
      (node (ref "D9") (pin "17") (pinfunction "17_17") (pintype "passive"))
      (node (ref "U$2") (pin "AU1") (pinfunction "1_AU1") (pintype "passive"))
    )
    (net (code "861") (name "~{DATA3}") (class "Default")
      (node (ref "D9") (pin "18") (pinfunction "18_18") (pintype "passive"))
      (node (ref "U$2") (pin "AV1") (pinfunction "1_AV1") (pintype "passive"))
    )
    (net (code "862") (name "~{DATA4}") (class "Default")
      (node (ref "D7") (pin "14") (pinfunction "14_14") (pintype "passive"))
      (node (ref "U$2") (pin "BR1") (pinfunction "1_BR1") (pintype "passive"))
    )
    (net (code "863") (name "~{DATA5}") (class "Default")
      (node (ref "D7") (pin "15") (pinfunction "15_15") (pintype "passive"))
      (node (ref "U$2") (pin "BS1") (pinfunction "1_BS1") (pintype "passive"))
    )
    (net (code "864") (name "~{DATA6}") (class "Default")
      (node (ref "D7") (pin "17") (pinfunction "17_17") (pintype "passive"))
      (node (ref "U$2") (pin "BU1") (pinfunction "1_BU1") (pintype "passive"))
    )
    (net (code "865") (name "~{DATA7}") (class "Default")
      (node (ref "D7") (pin "18") (pinfunction "18_18") (pintype "passive"))
      (node (ref "U$2") (pin "BV1") (pinfunction "1_BV1") (pintype "passive"))
    )
    (net (code "866") (name "~{DATA8}") (class "Default")
      (node (ref "D13") (pin "14") (pinfunction "14_14") (pintype "passive"))
      (node (ref "U$2") (pin "DR1") (pinfunction "1_DR1") (pintype "passive"))
    )
    (net (code "867") (name "~{DATA9}") (class "Default")
      (node (ref "D13") (pin "15") (pinfunction "15_15") (pintype "passive"))
      (node (ref "U$2") (pin "DS1") (pinfunction "1_DS1") (pintype "passive"))
    )
    (net (code "868") (name "~{DATA10}") (class "Default")
      (node (ref "D13") (pin "17") (pinfunction "17_17") (pintype "passive"))
      (node (ref "U$2") (pin "DU1") (pinfunction "1_DU1") (pintype "passive"))
    )
    (net (code "869") (name "~{DATA11}") (class "Default")
      (node (ref "D13") (pin "18") (pinfunction "18_18") (pintype "passive"))
      (node (ref "U$2") (pin "DV1") (pinfunction "1_DV1") (pintype "passive"))
    )
    (net (code "870") (name "~{D}") (class "Default")
      (node (ref "D14") (pin "9") (pinfunction "9_9") (pintype "passive"))
      (node (ref "U$2") (pin "DK2") (pinfunction "1_DK2") (pintype "passive"))
    )
    (net (code "871") (name "~{EMA0}") (class "Default")
      (node (ref "D10") (pin "4") (pinfunction "4_4") (pintype "passive"))
      (node (ref "IC3") (pin "8") (pinfunction "A2_8") (pintype "input"))
      (node (ref "IC4") (pin "8") (pinfunction "A2_8") (pintype "input"))
      (node (ref "IC5") (pin "1") (pinfunction "A_1") (pintype "input"))
      (node (ref "U$2") (pin "AD2") (pinfunction "1_AD2") (pintype "passive"))
    )
    (net (code "872") (name "~{EMA1}") (class "Default")
      (node (ref "D10") (pin "5") (pinfunction "5_5") (pintype "passive"))
      (node (ref "IC3") (pin "9") (pinfunction "A1_9") (pintype "input"))
      (node (ref "IC4") (pin "9") (pinfunction "A1_9") (pintype "input"))
      (node (ref "IC5") (pin "2") (pinfunction "B_2") (pintype "input"))
      (node (ref "U$2") (pin "AE2") (pinfunction "1_AE2") (pintype "passive"))
    )
    (net (code "873") (name "~{EMA2}") (class "Default")
      (node (ref "D10") (pin "7") (pinfunction "7_7") (pintype "passive"))
      (node (ref "IC3") (pin "10") (pinfunction "A0_10") (pintype "input"))
      (node (ref "IC4") (pin "10") (pinfunction "A0_10") (pintype "input"))
      (node (ref "IC5") (pin "3") (pinfunction "C_3") (pintype "input"))
      (node (ref "U$2") (pin "AH2") (pinfunction "1_AH2") (pintype "passive"))
    )
    (net (code "874") (name "~{E}") (class "Default")
      (node (ref "D14") (pin "10") (pinfunction "10_10") (pintype "passive"))
      (node (ref "U$2") (pin "DL2") (pinfunction "1_DL2") (pintype "passive"))
    )
    (net (code "875") (name "~{FSET}") (class "Default")
      (node (ref "D14") (pin "13") (pinfunction "13_13") (pintype "passive"))
      (node (ref "U$2") (pin "DP2") (pinfunction "1_DP2") (pintype "passive"))
    )
    (net (code "876") (name "~{F}") (class "Default")
      (node (ref "D14") (pin "8") (pinfunction "8_8") (pintype "passive"))
      (node (ref "U$2") (pin "DJ2") (pinfunction "1_DJ2") (pintype "passive"))
    )
    (net (code "877") (name "~{IND1}") (class "Default")
      (node (ref "D12") (pin "17") (pinfunction "17_17") (pintype "passive"))
      (node (ref "U$2") (pin "CU2") (pinfunction "1_CU2") (pintype "passive"))
    )
    (net (code "878") (name "~{IND2}") (class "Default")
      (node (ref "D12") (pin "18") (pinfunction "18_18") (pintype "passive"))
      (node (ref "U$2") (pin "CV2") (pinfunction "1_CV2") (pintype "passive"))
    )
    (net (code "879") (name "~{INTERNAL_IO}") (class "Default")
      (node (ref "D11") (pin "10") (pinfunction "10_10") (pintype "passive"))
      (node (ref "U$2") (pin "CL1") (pinfunction "1_CL1") (pintype "passive"))
    )
    (net (code "880") (name "~{INT_RQST}") (class "Default")
      (node (ref "D11") (pin "13") (pinfunction "13_13") (pintype "passive"))
      (node (ref "U$2") (pin "CP1") (pinfunction "1_CP1") (pintype "passive"))
    )
    (net (code "881") (name "~{IO_PAUSE}") (class "Default")
      (node (ref "D11") (pin "4") (pinfunction "4_4") (pintype "passive"))
      (node (ref "U$2") (pin "CD1") (pinfunction "1_CD1") (pintype "passive"))
    )
    (net (code "882") (name "~{IR0}") (class "Default")
      (node (ref "D14") (pin "4") (pinfunction "4_4") (pintype "passive"))
      (node (ref "U$2") (pin "DD2") (pinfunction "1_DD2") (pintype "passive"))
    )
    (net (code "883") (name "~{IR1}") (class "Default")
      (node (ref "D14") (pin "5") (pinfunction "5_5") (pintype "passive"))
      (node (ref "U$2") (pin "DE2") (pinfunction "1_DE2") (pintype "passive"))
    )
    (net (code "884") (name "~{IR2}") (class "Default")
      (node (ref "D14") (pin "7") (pinfunction "7_7") (pintype "passive"))
      (node (ref "U$2") (pin "DH2") (pinfunction "1_DH2") (pintype "passive"))
    )
    (net (code "885") (name "~{KEY_CONT}") (class "Default")
      (node (ref "D14") (pin "17") (pinfunction "17_17") (pintype "passive"))
      (node (ref "U$2") (pin "DU2") (pinfunction "1_DU2") (pintype "passive"))
    )
    (net (code "886") (name "~{LA_ENABLE}") (class "Default")
      (node (ref "D8") (pin "11") (pinfunction "11_11") (pintype "passive"))
      (node (ref "U$2") (pin "BM2") (pinfunction "1_BM2") (pintype "passive"))
    )
    (net (code "887") (name "~{LINK_DATA}") (class "Default")
      (node (ref "D12") (pin "14") (pinfunction "14_14") (pintype "passive"))
      (node (ref "U$2") (pin "CR2") (pinfunction "1_CR2") (pintype "passive"))
    )
    (net (code "888") (name "~{LINK_LOAD}") (class "Default")
      (node (ref "D12") (pin "15") (pinfunction "15_15") (pintype "passive"))
      (node (ref "U$2") (pin "CS2") (pinfunction "1_CS2") (pintype "passive"))
    )
    (net (code "889") (name "~{LINK}") (class "Default")
      (node (ref "D10") (pin "18") (pinfunction "18_18") (pintype "passive"))
      (node (ref "U$2") (pin "AV2") (pinfunction "1_AV2") (pintype "passive"))
    )
    (net (code "890") (name "~{LOAD_CONT}") (class "Default")
      (node (ref "D8") (pin "7") (pinfunction "7_7") (pintype "passive"))
      (node (ref "U$2") (pin "BH2") (pinfunction "1_BH2") (pintype "passive"))
    )
    (net (code "891") (name "~{MA00}") (class "Default")
      (node (ref "D9") (pin "4") (pinfunction "4_4") (pintype "passive"))
      (node (ref "IC3") (pin "21") (pinfunction "A10_21") (pintype "input"))
      (node (ref "IC4") (pin "21") (pinfunction "A10_21") (pintype "input"))
      (node (ref "U$2") (pin "AD1") (pinfunction "1_AD1") (pintype "passive"))
    )
    (net (code "892") (name "~{MA01}") (class "Default")
      (node (ref "D9") (pin "5") (pinfunction "5_5") (pintype "passive"))
      (node (ref "IC3") (pin "23") (pinfunction "A11_23") (pintype "input"))
      (node (ref "IC4") (pin "23") (pinfunction "A11_23") (pintype "input"))
      (node (ref "U$2") (pin "AE1") (pinfunction "1_AE1") (pintype "passive"))
    )
    (net (code "893") (name "~{MA02}") (class "Default")
      (node (ref "D9") (pin "7") (pinfunction "7_7") (pintype "passive"))
      (node (ref "IC3") (pin "24") (pinfunction "A9_24") (pintype "input"))
      (node (ref "IC4") (pin "24") (pinfunction "A9_24") (pintype "input"))
      (node (ref "U$2") (pin "AH1") (pinfunction "1_AH1") (pintype "passive"))
    )
    (net (code "894") (name "~{MA03}") (class "Default")
      (node (ref "D9") (pin "8") (pinfunction "8_8") (pintype "passive"))
      (node (ref "IC3") (pin "25") (pinfunction "A8_25") (pintype "input"))
      (node (ref "IC4") (pin "25") (pinfunction "A8_25") (pintype "input"))
      (node (ref "U$2") (pin "AJ1") (pinfunction "1_AJ1") (pintype "passive"))
    )
    (net (code "895") (name "~{MA04}") (class "Default")
      (node (ref "D7") (pin "4") (pinfunction "4_4") (pintype "passive"))
      (node (ref "IC3") (pin "26") (pinfunction "A13_26") (pintype "input"))
      (node (ref "IC4") (pin "26") (pinfunction "A13_26") (pintype "input"))
      (node (ref "U$2") (pin "BD1") (pinfunction "1_BD1") (pintype "passive"))
    )
    (net (code "896") (name "~{MA05}") (class "Default")
      (node (ref "D7") (pin "5") (pinfunction "5_5") (pintype "passive"))
      (node (ref "IC3") (pin "1") (pinfunction "A14_1") (pintype "input"))
      (node (ref "IC4") (pin "1") (pinfunction "A14_1") (pintype "input"))
      (node (ref "U$2") (pin "BE1") (pinfunction "1_BE1") (pintype "passive"))
    )
    (net (code "897") (name "~{MA06}") (class "Default")
      (node (ref "D7") (pin "7") (pinfunction "7_7") (pintype "passive"))
      (node (ref "IC3") (pin "2") (pinfunction "A12_2") (pintype "input"))
      (node (ref "IC4") (pin "2") (pinfunction "A12_2") (pintype "input"))
      (node (ref "U$2") (pin "BH1") (pinfunction "1_BH1") (pintype "passive"))
    )
    (net (code "898") (name "~{MA07}") (class "Default")
      (node (ref "D7") (pin "8") (pinfunction "8_8") (pintype "passive"))
      (node (ref "IC3") (pin "3") (pinfunction "A7_3") (pintype "input"))
      (node (ref "IC4") (pin "3") (pinfunction "A7_3") (pintype "input"))
      (node (ref "U$2") (pin "BJ1") (pinfunction "1_BJ1") (pintype "passive"))
    )
    (net (code "899") (name "~{MA08}") (class "Default")
      (node (ref "D13") (pin "4") (pinfunction "4_4") (pintype "passive"))
      (node (ref "IC3") (pin "4") (pinfunction "A6_4") (pintype "input"))
      (node (ref "IC4") (pin "4") (pinfunction "A6_4") (pintype "input"))
      (node (ref "U$2") (pin "DD1") (pinfunction "1_DD1") (pintype "passive"))
    )
    (net (code "900") (name "~{MA09}") (class "Default")
      (node (ref "D13") (pin "5") (pinfunction "5_5") (pintype "passive"))
      (node (ref "IC3") (pin "5") (pinfunction "A5_5") (pintype "input"))
      (node (ref "IC4") (pin "5") (pinfunction "A5_5") (pintype "input"))
      (node (ref "U$2") (pin "DE1") (pinfunction "1_DE1") (pintype "passive"))
    )
    (net (code "901") (name "~{MA10}") (class "Default")
      (node (ref "D13") (pin "7") (pinfunction "7_7") (pintype "passive"))
      (node (ref "IC3") (pin "6") (pinfunction "A4_6") (pintype "input"))
      (node (ref "IC4") (pin "6") (pinfunction "A4_6") (pintype "input"))
      (node (ref "U$2") (pin "DH1") (pinfunction "1_DH1") (pintype "passive"))
    )
    (net (code "902") (name "~{MA11}") (class "Default")
      (node (ref "D13") (pin "8") (pinfunction "8_8") (pintype "passive"))
      (node (ref "IC3") (pin "7") (pinfunction "A3_7") (pintype "input"))
      (node (ref "IC4") (pin "7") (pinfunction "A3_7") (pintype "input"))
      (node (ref "U$2") (pin "DJ1") (pinfunction "1_DJ1") (pintype "passive"))
    )
    (net (code "903") (name "~{MD00}") (class "Default")
      (node (ref "D9") (pin "9") (pinfunction "9_9") (pintype "passive"))
      (node (ref "IC1") (pin "2") (pinfunction "A1_2") (pintype "bidirectional"))
      (node (ref "U$2") (pin "AK1") (pinfunction "1_AK1") (pintype "passive"))
    )
    (net (code "904") (name "~{MD01}") (class "Default")
      (node (ref "D9") (pin "10") (pinfunction "10_10") (pintype "passive"))
      (node (ref "IC1") (pin "3") (pinfunction "A2_3") (pintype "bidirectional"))
      (node (ref "U$2") (pin "AL1") (pinfunction "1_AL1") (pintype "passive"))
    )
    (net (code "905") (name "~{MD02}") (class "Default")
      (node (ref "D9") (pin "11") (pinfunction "11_11") (pintype "passive"))
      (node (ref "IC1") (pin "4") (pinfunction "A3_4") (pintype "bidirectional"))
      (node (ref "U$2") (pin "AM1") (pinfunction "1_AM1") (pintype "passive"))
    )
    (net (code "906") (name "~{MD03}") (class "Default")
      (node (ref "D9") (pin "13") (pinfunction "13_13") (pintype "passive"))
      (node (ref "IC1") (pin "5") (pinfunction "A4_5") (pintype "bidirectional"))
      (node (ref "U$2") (pin "AP1") (pinfunction "1_AP1") (pintype "passive"))
    )
    (net (code "907") (name "~{MD04}") (class "Default")
      (node (ref "D7") (pin "9") (pinfunction "9_9") (pintype "passive"))
      (node (ref "IC1") (pin "6") (pinfunction "A5_6") (pintype "bidirectional"))
      (node (ref "U$2") (pin "BK1") (pinfunction "1_BK1") (pintype "passive"))
    )
    (net (code "908") (name "~{MD05}") (class "Default")
      (node (ref "D7") (pin "10") (pinfunction "10_10") (pintype "passive"))
      (node (ref "IC1") (pin "7") (pinfunction "A6_7") (pintype "bidirectional"))
      (node (ref "U$2") (pin "BL1") (pinfunction "1_BL1") (pintype "passive"))
    )
    (net (code "909") (name "~{MD06}") (class "Default")
      (node (ref "D7") (pin "11") (pinfunction "11_11") (pintype "passive"))
      (node (ref "IC1") (pin "8") (pinfunction "A7_8") (pintype "bidirectional"))
      (node (ref "U$2") (pin "BM1") (pinfunction "1_BM1") (pintype "passive"))
    )
    (net (code "910") (name "~{MD07}") (class "Default")
      (node (ref "D7") (pin "13") (pinfunction "13_13") (pintype "passive"))
      (node (ref "IC1") (pin "9") (pinfunction "A8_9") (pintype "bidirectional"))
      (node (ref "U$2") (pin "BP1") (pinfunction "1_BP1") (pintype "passive"))
    )
    (net (code "911") (name "~{MD08}") (class "Default")
      (node (ref "D13") (pin "9") (pinfunction "9_9") (pintype "passive"))
      (node (ref "IC2") (pin "2") (pinfunction "A1_2") (pintype "bidirectional"))
      (node (ref "U$2") (pin "DK1") (pinfunction "1_DK1") (pintype "passive"))
    )
    (net (code "912") (name "~{MD09}") (class "Default")
      (node (ref "D13") (pin "10") (pinfunction "10_10") (pintype "passive"))
      (node (ref "IC2") (pin "3") (pinfunction "A2_3") (pintype "bidirectional"))
      (node (ref "U$2") (pin "DL1") (pinfunction "1_DL1") (pintype "passive"))
    )
    (net (code "913") (name "~{MD10}") (class "Default")
      (node (ref "D13") (pin "11") (pinfunction "11_11") (pintype "passive"))
      (node (ref "IC2") (pin "4") (pinfunction "A3_4") (pintype "bidirectional"))
      (node (ref "U$2") (pin "DM1") (pinfunction "1_DM1") (pintype "passive"))
    )
    (net (code "914") (name "~{MD11}") (class "Default")
      (node (ref "D13") (pin "13") (pinfunction "13_13") (pintype "passive"))
      (node (ref "IC2") (pin "5") (pinfunction "A4_5") (pintype "bidirectional"))
      (node (ref "U$2") (pin "DP1") (pinfunction "1_DP1") (pintype "passive"))
    )
    (net (code "915") (name "~{MD_DIR}") (class "Default")
      (node (ref "D10") (pin "9") (pinfunction "9_9") (pintype "passive"))
      (node (ref "IC8") (pin "2") (pinfunction "A1_2") (pintype "input"))
      (node (ref "U$2") (pin "AK2") (pinfunction "1_AK2") (pintype "passive"))
    )
    (net (code "916") (name "~{MEM_START}") (class "Default")
      (node (ref "D10") (pin "8") (pinfunction "8_8") (pintype "passive"))
      (node (ref "U$2") (pin "AJ2") (pinfunction "1_AJ2") (pintype "passive"))
    )
    (net (code "917") (name "~{MS_DISABLE}") (class "Default")
      (node (ref "D11") (pin "18") (pinfunction "18_18") (pintype "passive"))
      (node (ref "U$2") (pin "CV1") (pinfunction "1_CV1") (pintype "passive"))
    )
    (net (code "918") (name "~{NOT_LAST_TR}") (class "Default")
      (node (ref "D11") (pin "11") (pinfunction "11_11") (pintype "passive"))
      (node (ref "U$2") (pin "CM1") (pinfunction "1_CM1") (pintype "passive"))
    )
    (net (code "919") (name "~{NTS_STALL}") (class "Default")
      (node (ref "D8") (pin "14") (pinfunction "14_14") (pintype "passive"))
      (node (ref "U$2") (pin "BR2") (pinfunction "1_BR2") (pintype "passive"))
    )
    (net (code "920") (name "~{OVERFLOW}") (class "Default")
      (node (ref "D8") (pin "8") (pinfunction "8_8") (pintype "passive"))
      (node (ref "U$2") (pin "BJ2") (pinfunction "1_BJ2") (pintype "passive"))
    )
    (net (code "921") (name "~{READ_EN}") (class "Default")
      (node (ref "IC1") (pin "1") (pinfunction "DIR_1") (pintype "input"))
      (node (ref "IC2") (pin "1") (pinfunction "DIR_1") (pintype "input"))
      (node (ref "IC3") (pin "22") (pinfunction "~{OE}_22") (pintype "input"))
      (node (ref "IC4") (pin "22") (pinfunction "~{OE}_22") (pintype "input"))
      (node (ref "IC7") (pin "8") (pinfunction "O_8") (pintype "output"))
    )
    (net (code "922") (name "~{ROM_ADDR}") (class "Default")
      (node (ref "D10") (pin "17") (pinfunction "17_17") (pintype "passive"))
      (node (ref "IC5") (pin "6") (pinfunction "G1_6") (pintype "input"))
      (node (ref "U$2") (pin "AU2") (pinfunction "1_AU2") (pintype "passive"))
    )
    (net (code "923") (name "~{RUN}") (class "Default")
      (node (ref "D8") (pin "17") (pinfunction "17_17") (pintype "passive"))
      (node (ref "U$2") (pin "BU2") (pinfunction "1_BU2") (pintype "passive"))
    )
    (net (code "924") (name "~{SKIP}") (class "Default")
      (node (ref "D11") (pin "15") (pinfunction "15_15") (pintype "passive"))
      (node (ref "U$2") (pin "CS1") (pinfunction "1_CS1") (pintype "passive"))
    )
    (net (code "925") (name "~{STOP}") (class "Default")
      (node (ref "D14") (pin "15") (pinfunction "15_15") (pintype "passive"))
      (node (ref "U$2") (pin "DS2") (pinfunction "1_DS2") (pintype "passive"))
    )
    (net (code "926") (name "~{TS1}") (class "Default")
      (node (ref "D12") (pin "9") (pinfunction "9_9") (pintype "passive"))
      (node (ref "U$2") (pin "CK2") (pinfunction "1_CK2") (pintype "passive"))
    )
    (net (code "927") (name "~{TS2}") (class "Default")
      (node (ref "D12") (pin "10") (pinfunction "10_10") (pintype "passive"))
      (node (ref "U$2") (pin "CL2") (pinfunction "1_CL2") (pintype "passive"))
    )
    (net (code "928") (name "~{TS3}") (class "Default")
      (node (ref "D12") (pin "11") (pinfunction "11_11") (pintype "passive"))
      (node (ref "U$2") (pin "CM2") (pinfunction "1_CM2") (pintype "passive"))
    )
    (net (code "929") (name "~{TS4}") (class "Default")
      (node (ref "D12") (pin "13") (pinfunction "13_13") (pintype "passive"))
      (node (ref "U$2") (pin "CP2") (pinfunction "1_CP2") (pintype "passive"))
    )
    (net (code "930") (name "~{USER_MODE}") (class "Default")
      (node (ref "D14") (pin "11") (pinfunction "11_11") (pintype "passive"))
      (node (ref "U$2") (pin "DM2") (pinfunction "1_DM2") (pintype "passive"))
    )
    (net (code "931") (name "~{WRITE_EN}") (class "Default")
      (node (ref "IC3") (pin "27") (pinfunction "~{WE}_27") (pintype "input"))
      (node (ref "IC4") (pin "27") (pinfunction "~{WE}_27") (pintype "input"))
      (node (ref "IC7") (pin "6") (pinfunction "O_6") (pintype "output"))
    )
  )
)
